# proto.net
KiCad netlist of a schematic drawn in EAGLE
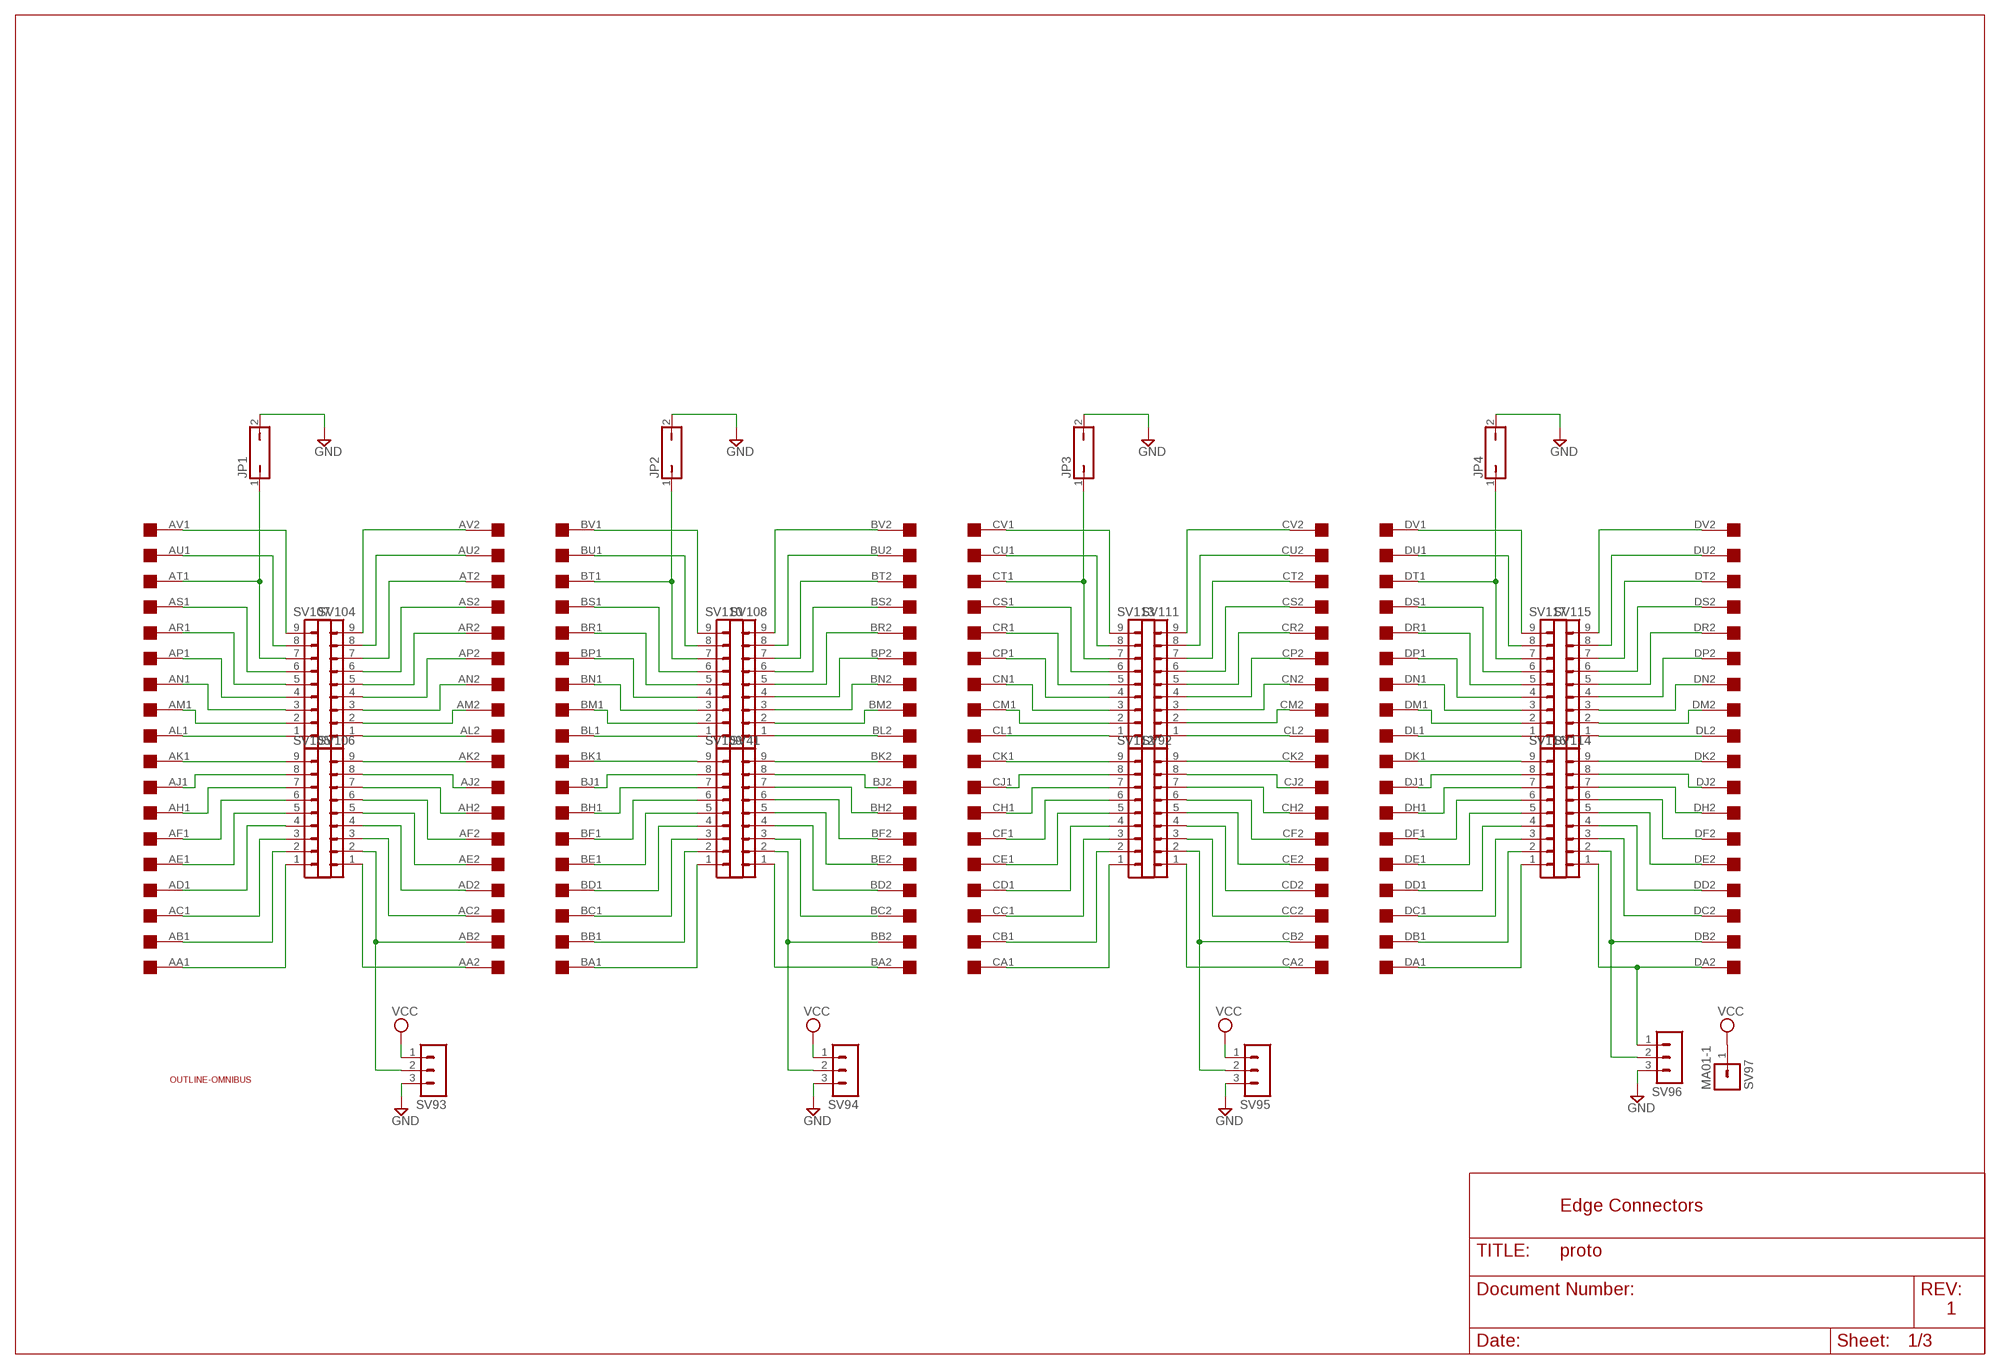
[diagram p0: schematic, sheet 1]
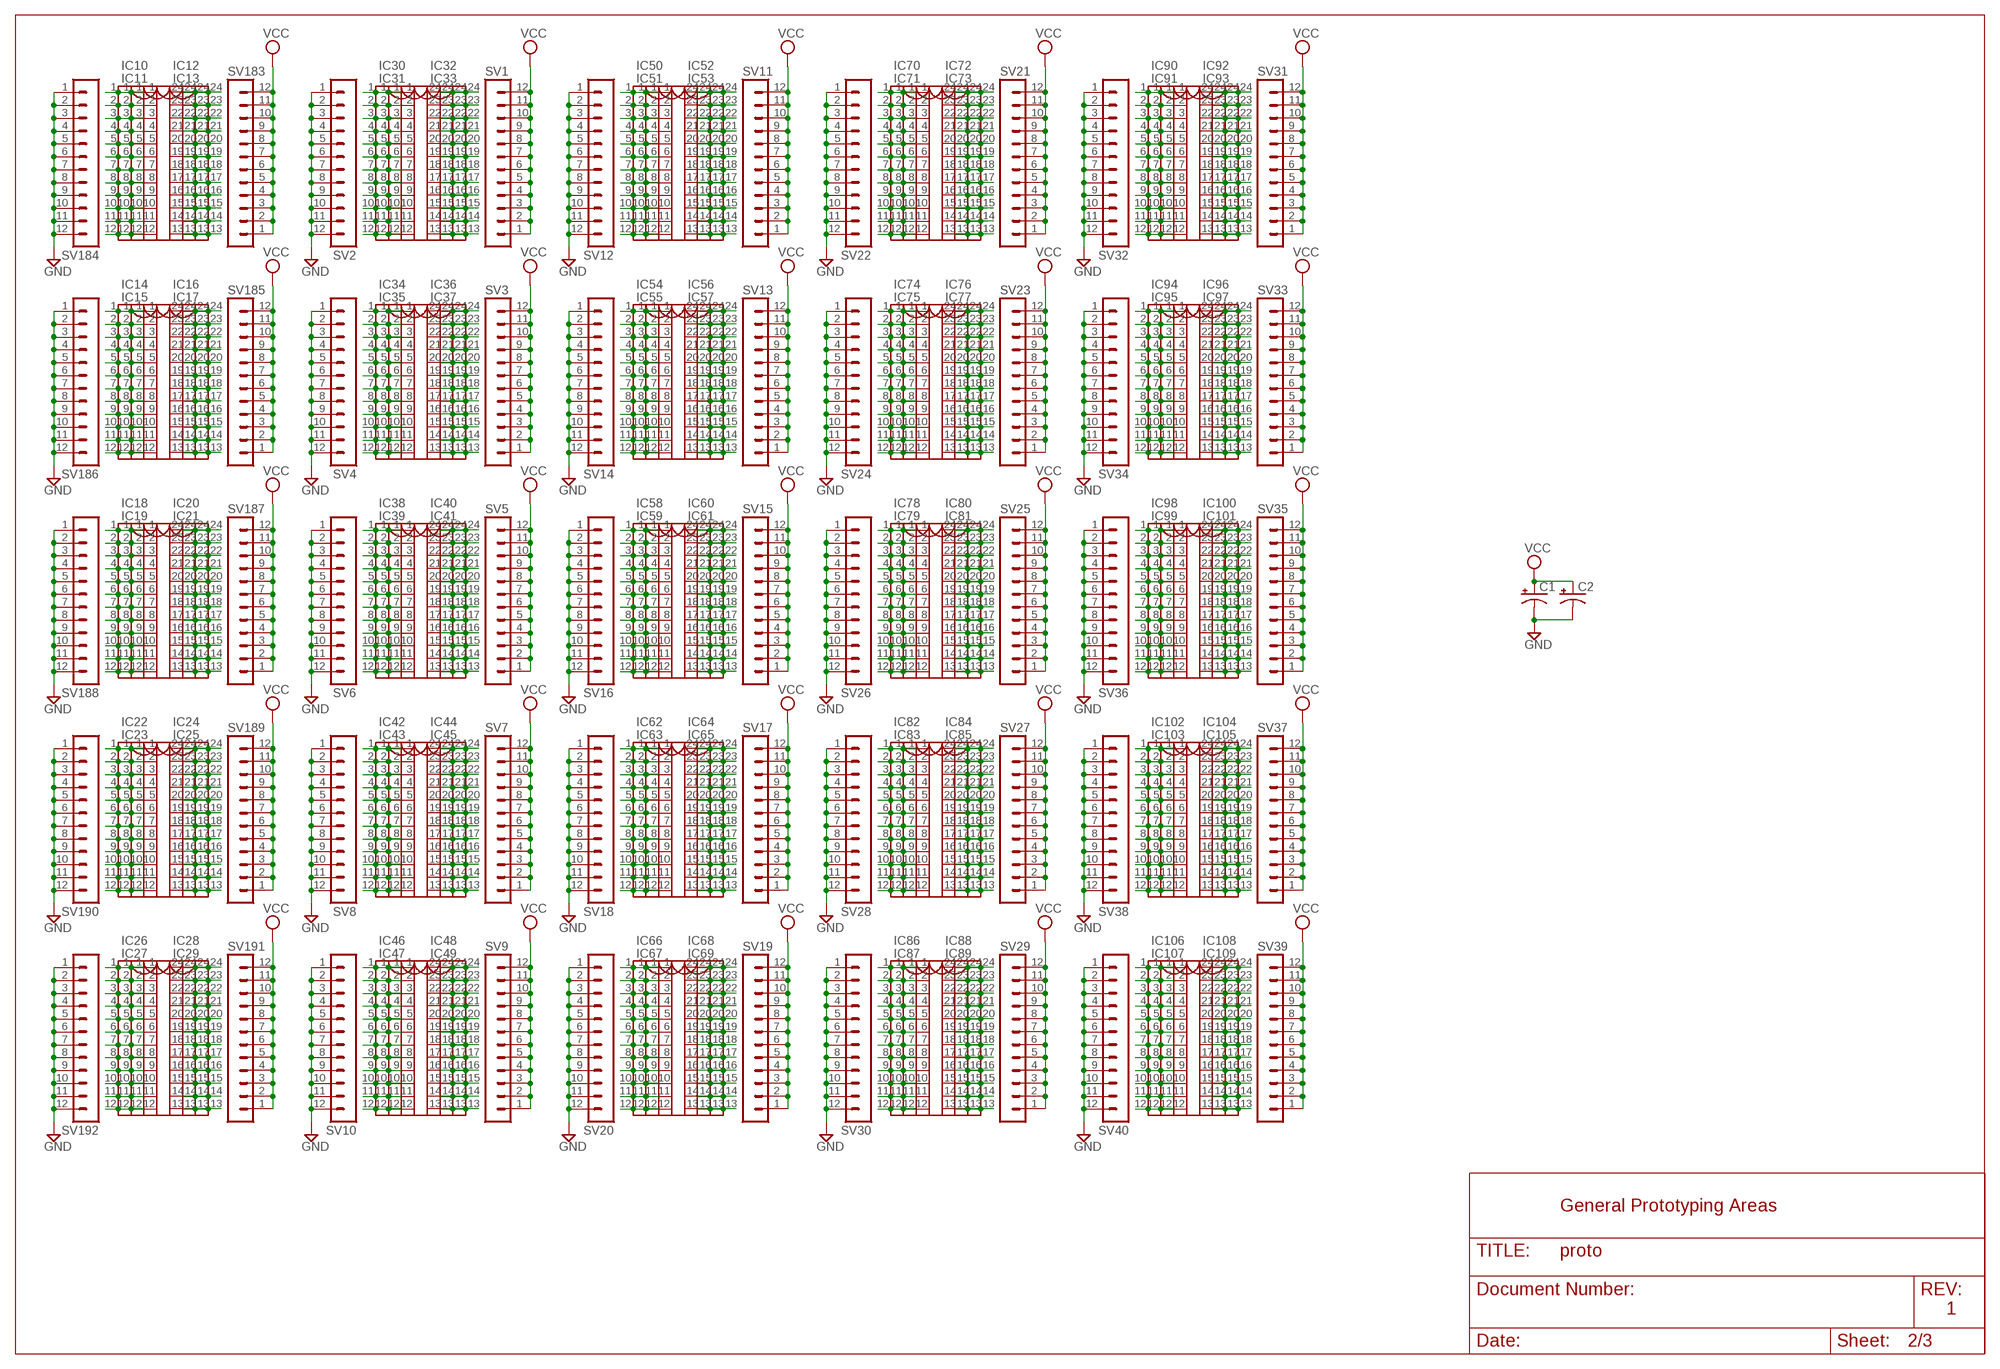
[diagram p1: schematic, sheet 2]
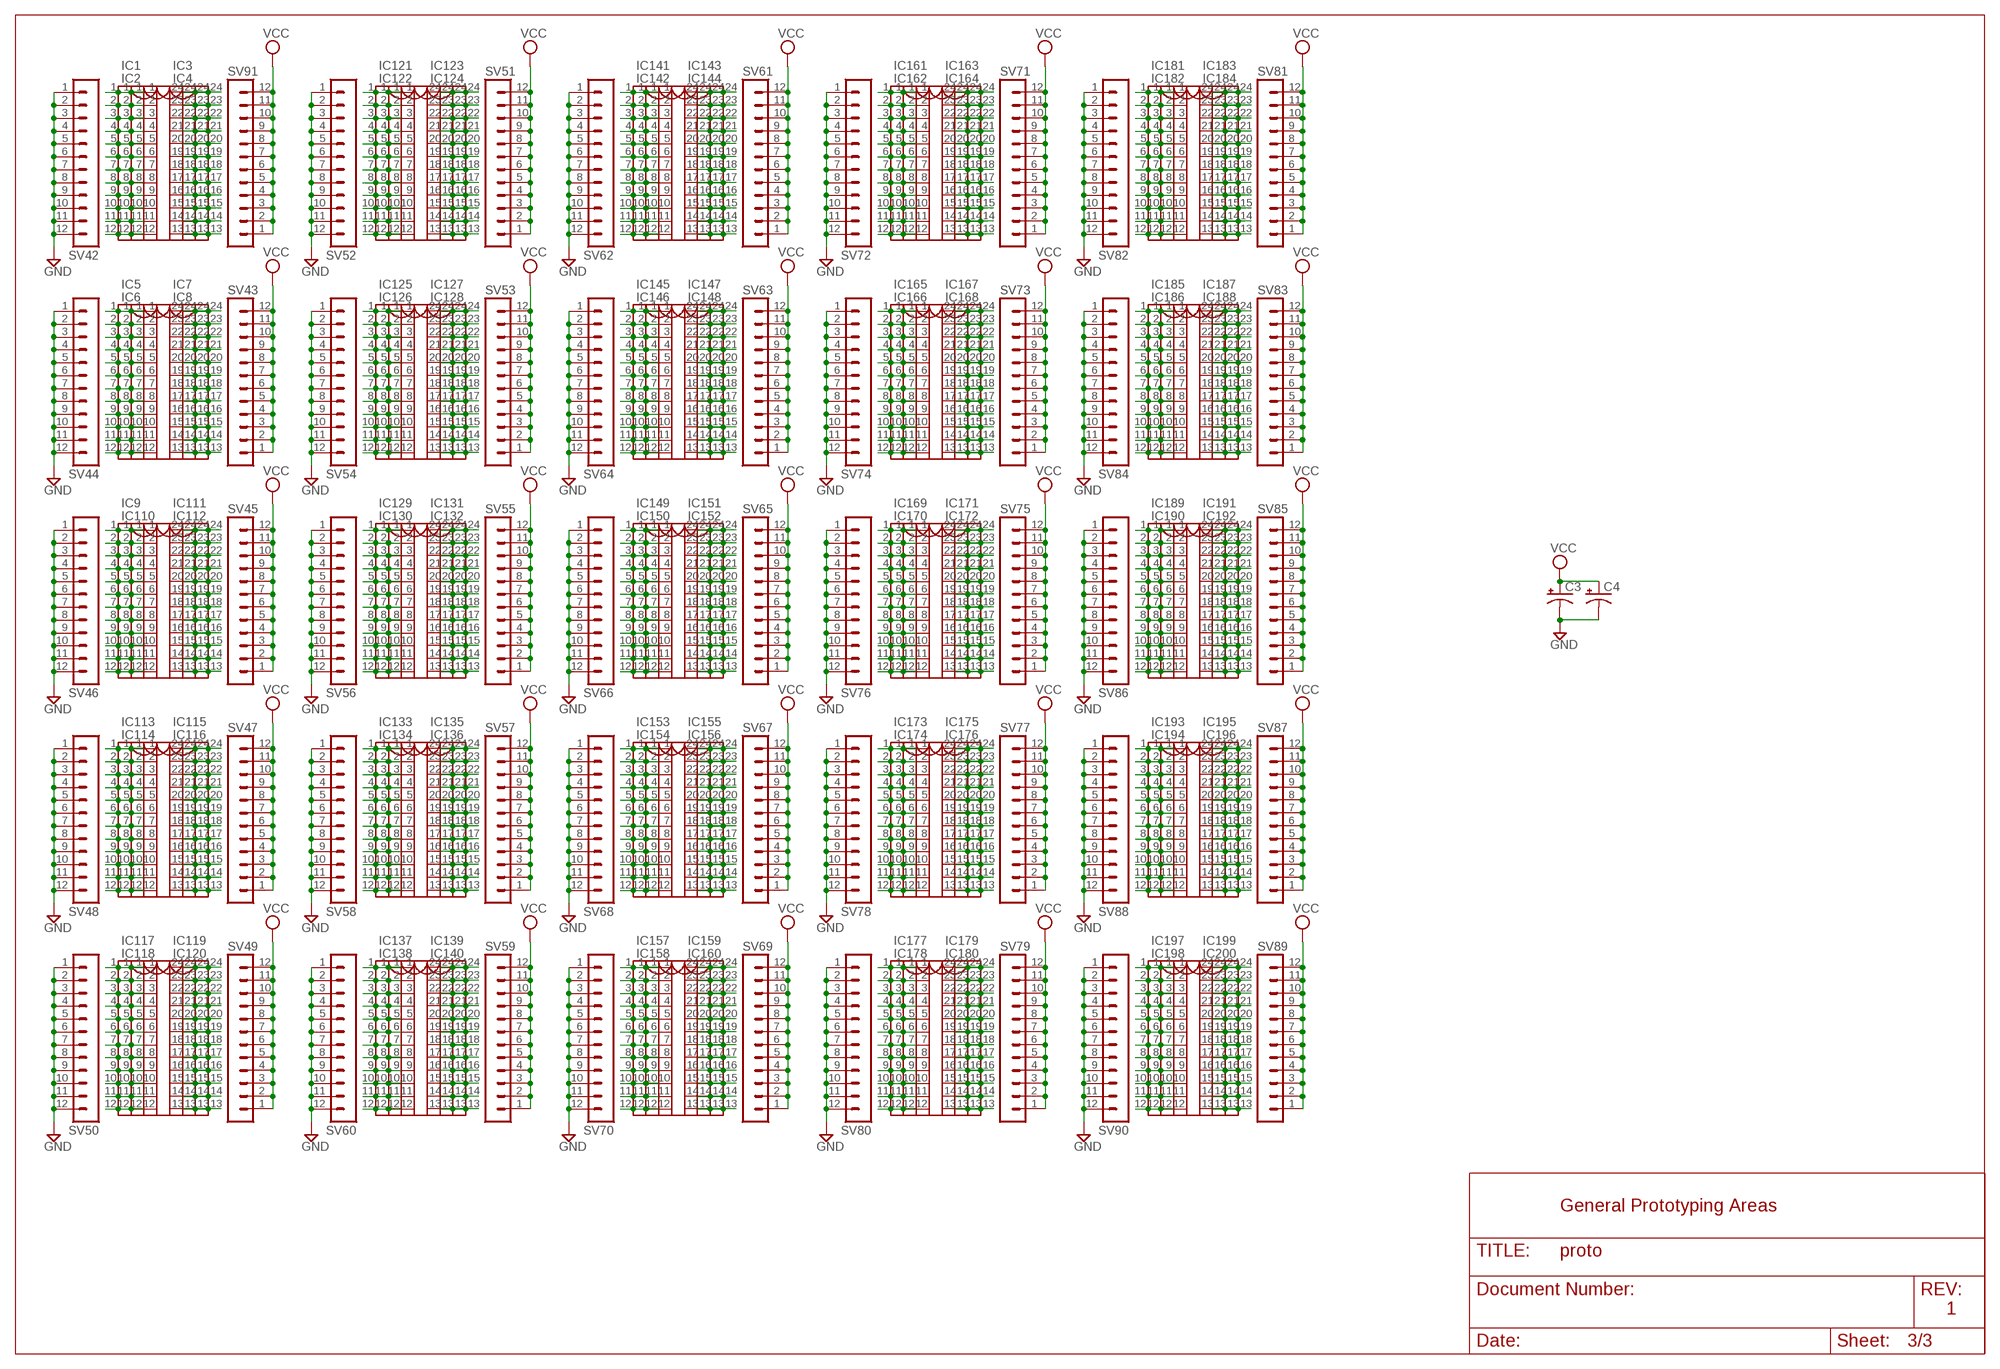
[diagram p2: schematic, sheet 3]

(export (version "E")
  (design (tool "Eeschema 10.0.6"))
  (components
    (comp (ref "C3")
      (value "CPOL-USE20-8AXIAL")
      (footprint "eagle-import:E12-8")
      (libsource (lib "eagle-import") (part "CPOL-USE20-8AXIAL"))
    )
    (comp (ref "C4")
      (value "CPOL-USE20-8AXIAL")
      (footprint "eagle-import:E12-8")
      (libsource (lib "eagle-import") (part "CPOL-USE20-8AXIAL"))
    )
    (comp (ref "IC1")
      (value "DIL24-3")
      (footprint "eagle-import:DIL24-3")
      (libsource (lib "eagle-import") (part "DIL24-3"))
    )
    (comp (ref "IC2")
      (value "DIL24-6")
      (footprint "eagle-import:DIL24-6")
      (libsource (lib "eagle-import") (part "DIL24-6"))
    )
    (comp (ref "IC3")
      (value "DIL24-9")
      (footprint "eagle-import:DIL24-9")
      (libsource (lib "eagle-import") (part "DIL24-9"))
    )
    (comp (ref "IC4")
      (value "DIL24-6")
      (footprint "eagle-import:DIL24-6")
      (libsource (lib "eagle-import") (part "DIL24-6"))
    )
    (comp (ref "IC5")
      (value "DIL24-3")
      (footprint "eagle-import:DIL24-3")
      (libsource (lib "eagle-import") (part "DIL24-3"))
    )
    (comp (ref "IC6")
      (value "DIL24-6")
      (footprint "eagle-import:DIL24-6")
      (libsource (lib "eagle-import") (part "DIL24-6"))
    )
    (comp (ref "IC7")
      (value "DIL24-9")
      (footprint "eagle-import:DIL24-9")
      (libsource (lib "eagle-import") (part "DIL24-9"))
    )
    (comp (ref "IC8")
      (value "DIL24-6")
      (footprint "eagle-import:DIL24-6")
      (libsource (lib "eagle-import") (part "DIL24-6"))
    )
    (comp (ref "IC9")
      (value "DIL24-3")
      (footprint "eagle-import:DIL24-3")
      (libsource (lib "eagle-import") (part "DIL24-3"))
    )
    (comp (ref "IC110")
      (value "DIL24-6")
      (footprint "eagle-import:DIL24-6")
      (libsource (lib "eagle-import") (part "DIL24-6"))
    )
    (comp (ref "IC111")
      (value "DIL24-9")
      (footprint "eagle-import:DIL24-9")
      (libsource (lib "eagle-import") (part "DIL24-9"))
    )
    (comp (ref "IC112")
      (value "DIL24-6")
      (footprint "eagle-import:DIL24-6")
      (libsource (lib "eagle-import") (part "DIL24-6"))
    )
    (comp (ref "IC113")
      (value "DIL24-3")
      (footprint "eagle-import:DIL24-3")
      (libsource (lib "eagle-import") (part "DIL24-3"))
    )
    (comp (ref "IC114")
      (value "DIL24-6")
      (footprint "eagle-import:DIL24-6")
      (libsource (lib "eagle-import") (part "DIL24-6"))
    )
    (comp (ref "IC115")
      (value "DIL24-9")
      (footprint "eagle-import:DIL24-9")
      (libsource (lib "eagle-import") (part "DIL24-9"))
    )
    (comp (ref "IC116")
      (value "DIL24-6")
      (footprint "eagle-import:DIL24-6")
      (libsource (lib "eagle-import") (part "DIL24-6"))
    )
    (comp (ref "IC117")
      (value "DIL24-3")
      (footprint "eagle-import:DIL24-3")
      (libsource (lib "eagle-import") (part "DIL24-3"))
    )
    (comp (ref "IC118")
      (value "DIL24-6")
      (footprint "eagle-import:DIL24-6")
      (libsource (lib "eagle-import") (part "DIL24-6"))
    )
    (comp (ref "IC119")
      (value "DIL24-9")
      (footprint "eagle-import:DIL24-9")
      (libsource (lib "eagle-import") (part "DIL24-9"))
    )
    (comp (ref "IC120")
      (value "DIL24-6")
      (footprint "eagle-import:DIL24-6")
      (libsource (lib "eagle-import") (part "DIL24-6"))
    )
    (comp (ref "IC121")
      (value "DIL24-3")
      (footprint "eagle-import:DIL24-3")
      (libsource (lib "eagle-import") (part "DIL24-3"))
    )
    (comp (ref "IC122")
      (value "DIL24-6")
      (footprint "eagle-import:DIL24-6")
      (libsource (lib "eagle-import") (part "DIL24-6"))
    )
    (comp (ref "IC123")
      (value "DIL24-9")
      (footprint "eagle-import:DIL24-9")
      (libsource (lib "eagle-import") (part "DIL24-9"))
    )
    (comp (ref "IC124")
      (value "DIL24-6")
      (footprint "eagle-import:DIL24-6")
      (libsource (lib "eagle-import") (part "DIL24-6"))
    )
    (comp (ref "IC125")
      (value "DIL24-3")
      (footprint "eagle-import:DIL24-3")
      (libsource (lib "eagle-import") (part "DIL24-3"))
    )
    (comp (ref "IC126")
      (value "DIL24-6")
      (footprint "eagle-import:DIL24-6")
      (libsource (lib "eagle-import") (part "DIL24-6"))
    )
    (comp (ref "IC127")
      (value "DIL24-9")
      (footprint "eagle-import:DIL24-9")
      (libsource (lib "eagle-import") (part "DIL24-9"))
    )
    (comp (ref "IC128")
      (value "DIL24-6")
      (footprint "eagle-import:DIL24-6")
      (libsource (lib "eagle-import") (part "DIL24-6"))
    )
    (comp (ref "IC129")
      (value "DIL24-3")
      (footprint "eagle-import:DIL24-3")
      (libsource (lib "eagle-import") (part "DIL24-3"))
    )
    (comp (ref "IC130")
      (value "DIL24-6")
      (footprint "eagle-import:DIL24-6")
      (libsource (lib "eagle-import") (part "DIL24-6"))
    )
    (comp (ref "IC131")
      (value "DIL24-9")
      (footprint "eagle-import:DIL24-9")
      (libsource (lib "eagle-import") (part "DIL24-9"))
    )
    (comp (ref "IC132")
      (value "DIL24-6")
      (footprint "eagle-import:DIL24-6")
      (libsource (lib "eagle-import") (part "DIL24-6"))
    )
    (comp (ref "IC133")
      (value "DIL24-3")
      (footprint "eagle-import:DIL24-3")
      (libsource (lib "eagle-import") (part "DIL24-3"))
    )
    (comp (ref "IC134")
      (value "DIL24-6")
      (footprint "eagle-import:DIL24-6")
      (libsource (lib "eagle-import") (part "DIL24-6"))
    )
    (comp (ref "IC135")
      (value "DIL24-9")
      (footprint "eagle-import:DIL24-9")
      (libsource (lib "eagle-import") (part "DIL24-9"))
    )
    (comp (ref "IC136")
      (value "DIL24-6")
      (footprint "eagle-import:DIL24-6")
      (libsource (lib "eagle-import") (part "DIL24-6"))
    )
    (comp (ref "IC137")
      (value "DIL24-3")
      (footprint "eagle-import:DIL24-3")
      (libsource (lib "eagle-import") (part "DIL24-3"))
    )
    (comp (ref "IC138")
      (value "DIL24-6")
      (footprint "eagle-import:DIL24-6")
      (libsource (lib "eagle-import") (part "DIL24-6"))
    )
    (comp (ref "IC139")
      (value "DIL24-9")
      (footprint "eagle-import:DIL24-9")
      (libsource (lib "eagle-import") (part "DIL24-9"))
    )
    (comp (ref "IC140")
      (value "DIL24-6")
      (footprint "eagle-import:DIL24-6")
      (libsource (lib "eagle-import") (part "DIL24-6"))
    )
    (comp (ref "IC141")
      (value "DIL24-3")
      (footprint "eagle-import:DIL24-3")
      (libsource (lib "eagle-import") (part "DIL24-3"))
    )
    (comp (ref "IC142")
      (value "DIL24-6")
      (footprint "eagle-import:DIL24-6")
      (libsource (lib "eagle-import") (part "DIL24-6"))
    )
    (comp (ref "IC143")
      (value "DIL24-9")
      (footprint "eagle-import:DIL24-9")
      (libsource (lib "eagle-import") (part "DIL24-9"))
    )
    (comp (ref "IC144")
      (value "DIL24-6")
      (footprint "eagle-import:DIL24-6")
      (libsource (lib "eagle-import") (part "DIL24-6"))
    )
    (comp (ref "IC145")
      (value "DIL24-3")
      (footprint "eagle-import:DIL24-3")
      (libsource (lib "eagle-import") (part "DIL24-3"))
    )
    (comp (ref "IC146")
      (value "DIL24-6")
      (footprint "eagle-import:DIL24-6")
      (libsource (lib "eagle-import") (part "DIL24-6"))
    )
    (comp (ref "IC147")
      (value "DIL24-9")
      (footprint "eagle-import:DIL24-9")
      (libsource (lib "eagle-import") (part "DIL24-9"))
    )
    (comp (ref "IC148")
      (value "DIL24-6")
      (footprint "eagle-import:DIL24-6")
      (libsource (lib "eagle-import") (part "DIL24-6"))
    )
    (comp (ref "IC149")
      (value "DIL24-3")
      (footprint "eagle-import:DIL24-3")
      (libsource (lib "eagle-import") (part "DIL24-3"))
    )
    (comp (ref "IC150")
      (value "DIL24-6")
      (footprint "eagle-import:DIL24-6")
      (libsource (lib "eagle-import") (part "DIL24-6"))
    )
    (comp (ref "IC151")
      (value "DIL24-9")
      (footprint "eagle-import:DIL24-9")
      (libsource (lib "eagle-import") (part "DIL24-9"))
    )
    (comp (ref "IC152")
      (value "DIL24-6")
      (footprint "eagle-import:DIL24-6")
      (libsource (lib "eagle-import") (part "DIL24-6"))
    )
    (comp (ref "IC153")
      (value "DIL24-3")
      (footprint "eagle-import:DIL24-3")
      (libsource (lib "eagle-import") (part "DIL24-3"))
    )
    (comp (ref "IC154")
      (value "DIL24-6")
      (footprint "eagle-import:DIL24-6")
      (libsource (lib "eagle-import") (part "DIL24-6"))
    )
    (comp (ref "IC155")
      (value "DIL24-9")
      (footprint "eagle-import:DIL24-9")
      (libsource (lib "eagle-import") (part "DIL24-9"))
    )
    (comp (ref "IC156")
      (value "DIL24-6")
      (footprint "eagle-import:DIL24-6")
      (libsource (lib "eagle-import") (part "DIL24-6"))
    )
    (comp (ref "IC157")
      (value "DIL24-3")
      (footprint "eagle-import:DIL24-3")
      (libsource (lib "eagle-import") (part "DIL24-3"))
    )
    (comp (ref "IC158")
      (value "DIL24-6")
      (footprint "eagle-import:DIL24-6")
      (libsource (lib "eagle-import") (part "DIL24-6"))
    )
    (comp (ref "IC159")
      (value "DIL24-9")
      (footprint "eagle-import:DIL24-9")
      (libsource (lib "eagle-import") (part "DIL24-9"))
    )
    (comp (ref "IC160")
      (value "DIL24-6")
      (footprint "eagle-import:DIL24-6")
      (libsource (lib "eagle-import") (part "DIL24-6"))
    )
    (comp (ref "IC161")
      (value "DIL24-3")
      (footprint "eagle-import:DIL24-3")
      (libsource (lib "eagle-import") (part "DIL24-3"))
    )
    (comp (ref "IC162")
      (value "DIL24-6")
      (footprint "eagle-import:DIL24-6")
      (libsource (lib "eagle-import") (part "DIL24-6"))
    )
    (comp (ref "IC163")
      (value "DIL24-9")
      (footprint "eagle-import:DIL24-9")
      (libsource (lib "eagle-import") (part "DIL24-9"))
    )
    (comp (ref "IC164")
      (value "DIL24-6")
      (footprint "eagle-import:DIL24-6")
      (libsource (lib "eagle-import") (part "DIL24-6"))
    )
    (comp (ref "IC165")
      (value "DIL24-3")
      (footprint "eagle-import:DIL24-3")
      (libsource (lib "eagle-import") (part "DIL24-3"))
    )
    (comp (ref "IC166")
      (value "DIL24-6")
      (footprint "eagle-import:DIL24-6")
      (libsource (lib "eagle-import") (part "DIL24-6"))
    )
    (comp (ref "IC167")
      (value "DIL24-9")
      (footprint "eagle-import:DIL24-9")
      (libsource (lib "eagle-import") (part "DIL24-9"))
    )
    (comp (ref "IC168")
      (value "DIL24-6")
      (footprint "eagle-import:DIL24-6")
      (libsource (lib "eagle-import") (part "DIL24-6"))
    )
    (comp (ref "IC169")
      (value "DIL24-3")
      (footprint "eagle-import:DIL24-3")
      (libsource (lib "eagle-import") (part "DIL24-3"))
    )
    (comp (ref "IC170")
      (value "DIL24-6")
      (footprint "eagle-import:DIL24-6")
      (libsource (lib "eagle-import") (part "DIL24-6"))
    )
    (comp (ref "IC171")
      (value "DIL24-9")
      (footprint "eagle-import:DIL24-9")
      (libsource (lib "eagle-import") (part "DIL24-9"))
    )
    (comp (ref "IC172")
      (value "DIL24-6")
      (footprint "eagle-import:DIL24-6")
      (libsource (lib "eagle-import") (part "DIL24-6"))
    )
    (comp (ref "IC173")
      (value "DIL24-3")
      (footprint "eagle-import:DIL24-3")
      (libsource (lib "eagle-import") (part "DIL24-3"))
    )
    (comp (ref "IC174")
      (value "DIL24-6")
      (footprint "eagle-import:DIL24-6")
      (libsource (lib "eagle-import") (part "DIL24-6"))
    )
    (comp (ref "IC175")
      (value "DIL24-9")
      (footprint "eagle-import:DIL24-9")
      (libsource (lib "eagle-import") (part "DIL24-9"))
    )
    (comp (ref "IC176")
      (value "DIL24-6")
      (footprint "eagle-import:DIL24-6")
      (libsource (lib "eagle-import") (part "DIL24-6"))
    )
    (comp (ref "IC177")
      (value "DIL24-3")
      (footprint "eagle-import:DIL24-3")
      (libsource (lib "eagle-import") (part "DIL24-3"))
    )
    (comp (ref "IC178")
      (value "DIL24-6")
      (footprint "eagle-import:DIL24-6")
      (libsource (lib "eagle-import") (part "DIL24-6"))
    )
    (comp (ref "IC179")
      (value "DIL24-9")
      (footprint "eagle-import:DIL24-9")
      (libsource (lib "eagle-import") (part "DIL24-9"))
    )
    (comp (ref "IC180")
      (value "DIL24-6")
      (footprint "eagle-import:DIL24-6")
      (libsource (lib "eagle-import") (part "DIL24-6"))
    )
    (comp (ref "IC181")
      (value "DIL24-3")
      (footprint "eagle-import:DIL24-3")
      (libsource (lib "eagle-import") (part "DIL24-3"))
    )
    (comp (ref "IC182")
      (value "DIL24-6")
      (footprint "eagle-import:DIL24-6")
      (libsource (lib "eagle-import") (part "DIL24-6"))
    )
    (comp (ref "IC183")
      (value "DIL24-9")
      (footprint "eagle-import:DIL24-9")
      (libsource (lib "eagle-import") (part "DIL24-9"))
    )
    (comp (ref "IC184")
      (value "DIL24-6")
      (footprint "eagle-import:DIL24-6")
      (libsource (lib "eagle-import") (part "DIL24-6"))
    )
    (comp (ref "IC185")
      (value "DIL24-3")
      (footprint "eagle-import:DIL24-3")
      (libsource (lib "eagle-import") (part "DIL24-3"))
    )
    (comp (ref "IC186")
      (value "DIL24-6")
      (footprint "eagle-import:DIL24-6")
      (libsource (lib "eagle-import") (part "DIL24-6"))
    )
    (comp (ref "IC187")
      (value "DIL24-9")
      (footprint "eagle-import:DIL24-9")
      (libsource (lib "eagle-import") (part "DIL24-9"))
    )
    (comp (ref "IC188")
      (value "DIL24-6")
      (footprint "eagle-import:DIL24-6")
      (libsource (lib "eagle-import") (part "DIL24-6"))
    )
    (comp (ref "IC189")
      (value "DIL24-3")
      (footprint "eagle-import:DIL24-3")
      (libsource (lib "eagle-import") (part "DIL24-3"))
    )
    (comp (ref "IC190")
      (value "DIL24-6")
      (footprint "eagle-import:DIL24-6")
      (libsource (lib "eagle-import") (part "DIL24-6"))
    )
    (comp (ref "IC191")
      (value "DIL24-9")
      (footprint "eagle-import:DIL24-9")
      (libsource (lib "eagle-import") (part "DIL24-9"))
    )
    (comp (ref "IC192")
      (value "DIL24-6")
      (footprint "eagle-import:DIL24-6")
      (libsource (lib "eagle-import") (part "DIL24-6"))
    )
    (comp (ref "IC193")
      (value "DIL24-3")
      (footprint "eagle-import:DIL24-3")
      (libsource (lib "eagle-import") (part "DIL24-3"))
    )
    (comp (ref "IC194")
      (value "DIL24-6")
      (footprint "eagle-import:DIL24-6")
      (libsource (lib "eagle-import") (part "DIL24-6"))
    )
    (comp (ref "IC195")
      (value "DIL24-9")
      (footprint "eagle-import:DIL24-9")
      (libsource (lib "eagle-import") (part "DIL24-9"))
    )
    (comp (ref "IC196")
      (value "DIL24-6")
      (footprint "eagle-import:DIL24-6")
      (libsource (lib "eagle-import") (part "DIL24-6"))
    )
    (comp (ref "IC197")
      (value "DIL24-3")
      (footprint "eagle-import:DIL24-3")
      (libsource (lib "eagle-import") (part "DIL24-3"))
    )
    (comp (ref "IC198")
      (value "DIL24-6")
      (footprint "eagle-import:DIL24-6")
      (libsource (lib "eagle-import") (part "DIL24-6"))
    )
    (comp (ref "IC199")
      (value "DIL24-9")
      (footprint "eagle-import:DIL24-9")
      (libsource (lib "eagle-import") (part "DIL24-9"))
    )
    (comp (ref "IC200")
      (value "DIL24-6")
      (footprint "eagle-import:DIL24-6")
      (libsource (lib "eagle-import") (part "DIL24-6"))
    )
    (comp (ref "SV42")
      (value "MA12-1")
      (footprint "eagle-import:MA12-1")
      (libsource (lib "eagle-import") (part "MA12-1"))
    )
    (comp (ref "SV43")
      (value "MA12-1")
      (footprint "eagle-import:MA12-1")
      (libsource (lib "eagle-import") (part "MA12-1"))
    )
    (comp (ref "SV44")
      (value "MA12-1")
      (footprint "eagle-import:MA12-1")
      (libsource (lib "eagle-import") (part "MA12-1"))
    )
    (comp (ref "SV45")
      (value "MA12-1")
      (footprint "eagle-import:MA12-1")
      (libsource (lib "eagle-import") (part "MA12-1"))
    )
    (comp (ref "SV46")
      (value "MA12-1")
      (footprint "eagle-import:MA12-1")
      (libsource (lib "eagle-import") (part "MA12-1"))
    )
    (comp (ref "SV47")
      (value "MA12-1")
      (footprint "eagle-import:MA12-1")
      (libsource (lib "eagle-import") (part "MA12-1"))
    )
    (comp (ref "SV48")
      (value "MA12-1")
      (footprint "eagle-import:MA12-1")
      (libsource (lib "eagle-import") (part "MA12-1"))
    )
    (comp (ref "SV49")
      (value "MA12-1")
      (footprint "eagle-import:MA12-1")
      (libsource (lib "eagle-import") (part "MA12-1"))
    )
    (comp (ref "SV50")
      (value "MA12-1")
      (footprint "eagle-import:MA12-1")
      (libsource (lib "eagle-import") (part "MA12-1"))
    )
    (comp (ref "SV51")
      (value "MA12-1")
      (footprint "eagle-import:MA12-1")
      (libsource (lib "eagle-import") (part "MA12-1"))
    )
    (comp (ref "SV52")
      (value "MA12-1")
      (footprint "eagle-import:MA12-1")
      (libsource (lib "eagle-import") (part "MA12-1"))
    )
    (comp (ref "SV53")
      (value "MA12-1")
      (footprint "eagle-import:MA12-1")
      (libsource (lib "eagle-import") (part "MA12-1"))
    )
    (comp (ref "SV54")
      (value "MA12-1")
      (footprint "eagle-import:MA12-1")
      (libsource (lib "eagle-import") (part "MA12-1"))
    )
    (comp (ref "SV55")
      (value "MA12-1")
      (footprint "eagle-import:MA12-1")
      (libsource (lib "eagle-import") (part "MA12-1"))
    )
    (comp (ref "SV56")
      (value "MA12-1")
      (footprint "eagle-import:MA12-1")
      (libsource (lib "eagle-import") (part "MA12-1"))
    )
    (comp (ref "SV57")
      (value "MA12-1")
      (footprint "eagle-import:MA12-1")
      (libsource (lib "eagle-import") (part "MA12-1"))
    )
    (comp (ref "SV58")
      (value "MA12-1")
      (footprint "eagle-import:MA12-1")
      (libsource (lib "eagle-import") (part "MA12-1"))
    )
    (comp (ref "SV59")
      (value "MA12-1")
      (footprint "eagle-import:MA12-1")
      (libsource (lib "eagle-import") (part "MA12-1"))
    )
    (comp (ref "SV60")
      (value "MA12-1")
      (footprint "eagle-import:MA12-1")
      (libsource (lib "eagle-import") (part "MA12-1"))
    )
    (comp (ref "SV61")
      (value "MA12-1")
      (footprint "eagle-import:MA12-1")
      (libsource (lib "eagle-import") (part "MA12-1"))
    )
    (comp (ref "SV62")
      (value "MA12-1")
      (footprint "eagle-import:MA12-1")
      (libsource (lib "eagle-import") (part "MA12-1"))
    )
    (comp (ref "SV63")
      (value "MA12-1")
      (footprint "eagle-import:MA12-1")
      (libsource (lib "eagle-import") (part "MA12-1"))
    )
    (comp (ref "SV64")
      (value "MA12-1")
      (footprint "eagle-import:MA12-1")
      (libsource (lib "eagle-import") (part "MA12-1"))
    )
    (comp (ref "SV65")
      (value "MA12-1")
      (footprint "eagle-import:MA12-1")
      (libsource (lib "eagle-import") (part "MA12-1"))
    )
    (comp (ref "SV66")
      (value "MA12-1")
      (footprint "eagle-import:MA12-1")
      (libsource (lib "eagle-import") (part "MA12-1"))
    )
    (comp (ref "SV67")
      (value "MA12-1")
      (footprint "eagle-import:MA12-1")
      (libsource (lib "eagle-import") (part "MA12-1"))
    )
    (comp (ref "SV68")
      (value "MA12-1")
      (footprint "eagle-import:MA12-1")
      (libsource (lib "eagle-import") (part "MA12-1"))
    )
    (comp (ref "SV69")
      (value "MA12-1")
      (footprint "eagle-import:MA12-1")
      (libsource (lib "eagle-import") (part "MA12-1"))
    )
    (comp (ref "SV70")
      (value "MA12-1")
      (footprint "eagle-import:MA12-1")
      (libsource (lib "eagle-import") (part "MA12-1"))
    )
    (comp (ref "SV71")
      (value "MA12-1")
      (footprint "eagle-import:MA12-1")
      (libsource (lib "eagle-import") (part "MA12-1"))
    )
    (comp (ref "SV72")
      (value "MA12-1")
      (footprint "eagle-import:MA12-1")
      (libsource (lib "eagle-import") (part "MA12-1"))
    )
    (comp (ref "SV73")
      (value "MA12-1")
      (footprint "eagle-import:MA12-1")
      (libsource (lib "eagle-import") (part "MA12-1"))
    )
    (comp (ref "SV74")
      (value "MA12-1")
      (footprint "eagle-import:MA12-1")
      (libsource (lib "eagle-import") (part "MA12-1"))
    )
    (comp (ref "SV75")
      (value "MA12-1")
      (footprint "eagle-import:MA12-1")
      (libsource (lib "eagle-import") (part "MA12-1"))
    )
    (comp (ref "SV76")
      (value "MA12-1")
      (footprint "eagle-import:MA12-1")
      (libsource (lib "eagle-import") (part "MA12-1"))
    )
    (comp (ref "SV77")
      (value "MA12-1")
      (footprint "eagle-import:MA12-1")
      (libsource (lib "eagle-import") (part "MA12-1"))
    )
    (comp (ref "SV78")
      (value "MA12-1")
      (footprint "eagle-import:MA12-1")
      (libsource (lib "eagle-import") (part "MA12-1"))
    )
    (comp (ref "SV79")
      (value "MA12-1")
      (footprint "eagle-import:MA12-1")
      (libsource (lib "eagle-import") (part "MA12-1"))
    )
    (comp (ref "SV80")
      (value "MA12-1")
      (footprint "eagle-import:MA12-1")
      (libsource (lib "eagle-import") (part "MA12-1"))
    )
    (comp (ref "SV81")
      (value "MA12-1")
      (footprint "eagle-import:MA12-1")
      (libsource (lib "eagle-import") (part "MA12-1"))
    )
    (comp (ref "SV82")
      (value "MA12-1")
      (footprint "eagle-import:MA12-1")
      (libsource (lib "eagle-import") (part "MA12-1"))
    )
    (comp (ref "SV83")
      (value "MA12-1")
      (footprint "eagle-import:MA12-1")
      (libsource (lib "eagle-import") (part "MA12-1"))
    )
    (comp (ref "SV84")
      (value "MA12-1")
      (footprint "eagle-import:MA12-1")
      (libsource (lib "eagle-import") (part "MA12-1"))
    )
    (comp (ref "SV85")
      (value "MA12-1")
      (footprint "eagle-import:MA12-1")
      (libsource (lib "eagle-import") (part "MA12-1"))
    )
    (comp (ref "SV86")
      (value "MA12-1")
      (footprint "eagle-import:MA12-1")
      (libsource (lib "eagle-import") (part "MA12-1"))
    )
    (comp (ref "SV87")
      (value "MA12-1")
      (footprint "eagle-import:MA12-1")
      (libsource (lib "eagle-import") (part "MA12-1"))
    )
    (comp (ref "SV88")
      (value "MA12-1")
      (footprint "eagle-import:MA12-1")
      (libsource (lib "eagle-import") (part "MA12-1"))
    )
    (comp (ref "SV89")
      (value "MA12-1")
      (footprint "eagle-import:MA12-1")
      (libsource (lib "eagle-import") (part "MA12-1"))
    )
    (comp (ref "SV90")
      (value "MA12-1")
      (footprint "eagle-import:MA12-1")
      (libsource (lib "eagle-import") (part "MA12-1"))
    )
    (comp (ref "SV91")
      (value "MA12-1")
      (footprint "eagle-import:MA12-1")
      (libsource (lib "eagle-import") (part "MA12-1"))
    )
    (comp (ref "C1")
      (value "CPOL-USE20-8AXIAL")
      (footprint "eagle-import:E12-8")
      (libsource (lib "eagle-import") (part "CPOL-USE20-8AXIAL"))
    )
    (comp (ref "C2")
      (value "CPOL-USE20-8AXIAL")
      (footprint "eagle-import:E12-8")
      (libsource (lib "eagle-import") (part "CPOL-USE20-8AXIAL"))
    )
    (comp (ref "IC10")
      (value "DIL24-3")
      (footprint "eagle-import:DIL24-3")
      (libsource (lib "eagle-import") (part "DIL24-3"))
    )
    (comp (ref "IC11")
      (value "DIL24-6")
      (footprint "eagle-import:DIL24-6")
      (libsource (lib "eagle-import") (part "DIL24-6"))
    )
    (comp (ref "IC12")
      (value "DIL24-9")
      (footprint "eagle-import:DIL24-9")
      (libsource (lib "eagle-import") (part "DIL24-9"))
    )
    (comp (ref "IC13")
      (value "DIL24-6")
      (footprint "eagle-import:DIL24-6")
      (libsource (lib "eagle-import") (part "DIL24-6"))
    )
    (comp (ref "IC14")
      (value "DIL24-3")
      (footprint "eagle-import:DIL24-3")
      (libsource (lib "eagle-import") (part "DIL24-3"))
    )
    (comp (ref "IC15")
      (value "DIL24-6")
      (footprint "eagle-import:DIL24-6")
      (libsource (lib "eagle-import") (part "DIL24-6"))
    )
    (comp (ref "IC16")
      (value "DIL24-9")
      (footprint "eagle-import:DIL24-9")
      (libsource (lib "eagle-import") (part "DIL24-9"))
    )
    (comp (ref "IC17")
      (value "DIL24-6")
      (footprint "eagle-import:DIL24-6")
      (libsource (lib "eagle-import") (part "DIL24-6"))
    )
    (comp (ref "IC18")
      (value "DIL24-3")
      (footprint "eagle-import:DIL24-3")
      (libsource (lib "eagle-import") (part "DIL24-3"))
    )
    (comp (ref "IC19")
      (value "DIL24-6")
      (footprint "eagle-import:DIL24-6")
      (libsource (lib "eagle-import") (part "DIL24-6"))
    )
    (comp (ref "IC20")
      (value "DIL24-9")
      (footprint "eagle-import:DIL24-9")
      (libsource (lib "eagle-import") (part "DIL24-9"))
    )
    (comp (ref "IC21")
      (value "DIL24-6")
      (footprint "eagle-import:DIL24-6")
      (libsource (lib "eagle-import") (part "DIL24-6"))
    )
    (comp (ref "IC22")
      (value "DIL24-3")
      (footprint "eagle-import:DIL24-3")
      (libsource (lib "eagle-import") (part "DIL24-3"))
    )
    (comp (ref "IC23")
      (value "DIL24-6")
      (footprint "eagle-import:DIL24-6")
      (libsource (lib "eagle-import") (part "DIL24-6"))
    )
    (comp (ref "IC24")
      (value "DIL24-9")
      (footprint "eagle-import:DIL24-9")
      (libsource (lib "eagle-import") (part "DIL24-9"))
    )
    (comp (ref "IC25")
      (value "DIL24-6")
      (footprint "eagle-import:DIL24-6")
      (libsource (lib "eagle-import") (part "DIL24-6"))
    )
    (comp (ref "IC26")
      (value "DIL24-3")
      (footprint "eagle-import:DIL24-3")
      (libsource (lib "eagle-import") (part "DIL24-3"))
    )
    (comp (ref "IC27")
      (value "DIL24-6")
      (footprint "eagle-import:DIL24-6")
      (libsource (lib "eagle-import") (part "DIL24-6"))
    )
    (comp (ref "IC28")
      (value "DIL24-9")
      (footprint "eagle-import:DIL24-9")
      (libsource (lib "eagle-import") (part "DIL24-9"))
    )
    (comp (ref "IC29")
      (value "DIL24-6")
      (footprint "eagle-import:DIL24-6")
      (libsource (lib "eagle-import") (part "DIL24-6"))
    )
    (comp (ref "IC30")
      (value "DIL24-3")
      (footprint "eagle-import:DIL24-3")
      (libsource (lib "eagle-import") (part "DIL24-3"))
    )
    (comp (ref "IC31")
      (value "DIL24-6")
      (footprint "eagle-import:DIL24-6")
      (libsource (lib "eagle-import") (part "DIL24-6"))
    )
    (comp (ref "IC32")
      (value "DIL24-9")
      (footprint "eagle-import:DIL24-9")
      (libsource (lib "eagle-import") (part "DIL24-9"))
    )
    (comp (ref "IC33")
      (value "DIL24-6")
      (footprint "eagle-import:DIL24-6")
      (libsource (lib "eagle-import") (part "DIL24-6"))
    )
    (comp (ref "IC34")
      (value "DIL24-3")
      (footprint "eagle-import:DIL24-3")
      (libsource (lib "eagle-import") (part "DIL24-3"))
    )
    (comp (ref "IC35")
      (value "DIL24-6")
      (footprint "eagle-import:DIL24-6")
      (libsource (lib "eagle-import") (part "DIL24-6"))
    )
    (comp (ref "IC36")
      (value "DIL24-9")
      (footprint "eagle-import:DIL24-9")
      (libsource (lib "eagle-import") (part "DIL24-9"))
    )
    (comp (ref "IC37")
      (value "DIL24-6")
      (footprint "eagle-import:DIL24-6")
      (libsource (lib "eagle-import") (part "DIL24-6"))
    )
    (comp (ref "IC38")
      (value "DIL24-3")
      (footprint "eagle-import:DIL24-3")
      (libsource (lib "eagle-import") (part "DIL24-3"))
    )
    (comp (ref "IC39")
      (value "DIL24-6")
      (footprint "eagle-import:DIL24-6")
      (libsource (lib "eagle-import") (part "DIL24-6"))
    )
    (comp (ref "IC40")
      (value "DIL24-9")
      (footprint "eagle-import:DIL24-9")
      (libsource (lib "eagle-import") (part "DIL24-9"))
    )
    (comp (ref "IC41")
      (value "DIL24-6")
      (footprint "eagle-import:DIL24-6")
      (libsource (lib "eagle-import") (part "DIL24-6"))
    )
    (comp (ref "IC42")
      (value "DIL24-3")
      (footprint "eagle-import:DIL24-3")
      (libsource (lib "eagle-import") (part "DIL24-3"))
    )
    (comp (ref "IC43")
      (value "DIL24-6")
      (footprint "eagle-import:DIL24-6")
      (libsource (lib "eagle-import") (part "DIL24-6"))
    )
    (comp (ref "IC44")
      (value "DIL24-9")
      (footprint "eagle-import:DIL24-9")
      (libsource (lib "eagle-import") (part "DIL24-9"))
    )
    (comp (ref "IC45")
      (value "DIL24-6")
      (footprint "eagle-import:DIL24-6")
      (libsource (lib "eagle-import") (part "DIL24-6"))
    )
    (comp (ref "IC46")
      (value "DIL24-3")
      (footprint "eagle-import:DIL24-3")
      (libsource (lib "eagle-import") (part "DIL24-3"))
    )
    (comp (ref "IC47")
      (value "DIL24-6")
      (footprint "eagle-import:DIL24-6")
      (libsource (lib "eagle-import") (part "DIL24-6"))
    )
    (comp (ref "IC48")
      (value "DIL24-9")
      (footprint "eagle-import:DIL24-9")
      (libsource (lib "eagle-import") (part "DIL24-9"))
    )
    (comp (ref "IC49")
      (value "DIL24-6")
      (footprint "eagle-import:DIL24-6")
      (libsource (lib "eagle-import") (part "DIL24-6"))
    )
    (comp (ref "IC50")
      (value "DIL24-3")
      (footprint "eagle-import:DIL24-3")
      (libsource (lib "eagle-import") (part "DIL24-3"))
    )
    (comp (ref "IC51")
      (value "DIL24-6")
      (footprint "eagle-import:DIL24-6")
      (libsource (lib "eagle-import") (part "DIL24-6"))
    )
    (comp (ref "IC52")
      (value "DIL24-9")
      (footprint "eagle-import:DIL24-9")
      (libsource (lib "eagle-import") (part "DIL24-9"))
    )
    (comp (ref "IC53")
      (value "DIL24-6")
      (footprint "eagle-import:DIL24-6")
      (libsource (lib "eagle-import") (part "DIL24-6"))
    )
    (comp (ref "IC54")
      (value "DIL24-3")
      (footprint "eagle-import:DIL24-3")
      (libsource (lib "eagle-import") (part "DIL24-3"))
    )
    (comp (ref "IC55")
      (value "DIL24-6")
      (footprint "eagle-import:DIL24-6")
      (libsource (lib "eagle-import") (part "DIL24-6"))
    )
    (comp (ref "IC56")
      (value "DIL24-9")
      (footprint "eagle-import:DIL24-9")
      (libsource (lib "eagle-import") (part "DIL24-9"))
    )
    (comp (ref "IC57")
      (value "DIL24-6")
      (footprint "eagle-import:DIL24-6")
      (libsource (lib "eagle-import") (part "DIL24-6"))
    )
    (comp (ref "IC58")
      (value "DIL24-3")
      (footprint "eagle-import:DIL24-3")
      (libsource (lib "eagle-import") (part "DIL24-3"))
    )
    (comp (ref "IC59")
      (value "DIL24-6")
      (footprint "eagle-import:DIL24-6")
      (libsource (lib "eagle-import") (part "DIL24-6"))
    )
    (comp (ref "IC60")
      (value "DIL24-9")
      (footprint "eagle-import:DIL24-9")
      (libsource (lib "eagle-import") (part "DIL24-9"))
    )
    (comp (ref "IC61")
      (value "DIL24-6")
      (footprint "eagle-import:DIL24-6")
      (libsource (lib "eagle-import") (part "DIL24-6"))
    )
    (comp (ref "IC62")
      (value "DIL24-3")
      (footprint "eagle-import:DIL24-3")
      (libsource (lib "eagle-import") (part "DIL24-3"))
    )
    (comp (ref "IC63")
      (value "DIL24-6")
      (footprint "eagle-import:DIL24-6")
      (libsource (lib "eagle-import") (part "DIL24-6"))
    )
    (comp (ref "IC64")
      (value "DIL24-9")
      (footprint "eagle-import:DIL24-9")
      (libsource (lib "eagle-import") (part "DIL24-9"))
    )
    (comp (ref "IC65")
      (value "DIL24-6")
      (footprint "eagle-import:DIL24-6")
      (libsource (lib "eagle-import") (part "DIL24-6"))
    )
    (comp (ref "IC66")
      (value "DIL24-3")
      (footprint "eagle-import:DIL24-3")
      (libsource (lib "eagle-import") (part "DIL24-3"))
    )
    (comp (ref "IC67")
      (value "DIL24-6")
      (footprint "eagle-import:DIL24-6")
      (libsource (lib "eagle-import") (part "DIL24-6"))
    )
    (comp (ref "IC68")
      (value "DIL24-9")
      (footprint "eagle-import:DIL24-9")
      (libsource (lib "eagle-import") (part "DIL24-9"))
    )
    (comp (ref "IC69")
      (value "DIL24-6")
      (footprint "eagle-import:DIL24-6")
      (libsource (lib "eagle-import") (part "DIL24-6"))
    )
    (comp (ref "IC70")
      (value "DIL24-3")
      (footprint "eagle-import:DIL24-3")
      (libsource (lib "eagle-import") (part "DIL24-3"))
    )
    (comp (ref "IC71")
      (value "DIL24-6")
      (footprint "eagle-import:DIL24-6")
      (libsource (lib "eagle-import") (part "DIL24-6"))
    )
    (comp (ref "IC72")
      (value "DIL24-9")
      (footprint "eagle-import:DIL24-9")
      (libsource (lib "eagle-import") (part "DIL24-9"))
    )
    (comp (ref "IC73")
      (value "DIL24-6")
      (footprint "eagle-import:DIL24-6")
      (libsource (lib "eagle-import") (part "DIL24-6"))
    )
    (comp (ref "IC74")
      (value "DIL24-3")
      (footprint "eagle-import:DIL24-3")
      (libsource (lib "eagle-import") (part "DIL24-3"))
    )
    (comp (ref "IC75")
      (value "DIL24-6")
      (footprint "eagle-import:DIL24-6")
      (libsource (lib "eagle-import") (part "DIL24-6"))
    )
    (comp (ref "IC76")
      (value "DIL24-9")
      (footprint "eagle-import:DIL24-9")
      (libsource (lib "eagle-import") (part "DIL24-9"))
    )
    (comp (ref "IC77")
      (value "DIL24-6")
      (footprint "eagle-import:DIL24-6")
      (libsource (lib "eagle-import") (part "DIL24-6"))
    )
    (comp (ref "IC78")
      (value "DIL24-3")
      (footprint "eagle-import:DIL24-3")
      (libsource (lib "eagle-import") (part "DIL24-3"))
    )
    (comp (ref "IC79")
      (value "DIL24-6")
      (footprint "eagle-import:DIL24-6")
      (libsource (lib "eagle-import") (part "DIL24-6"))
    )
    (comp (ref "IC80")
      (value "DIL24-9")
      (footprint "eagle-import:DIL24-9")
      (libsource (lib "eagle-import") (part "DIL24-9"))
    )
    (comp (ref "IC81")
      (value "DIL24-6")
      (footprint "eagle-import:DIL24-6")
      (libsource (lib "eagle-import") (part "DIL24-6"))
    )
    (comp (ref "IC82")
      (value "DIL24-3")
      (footprint "eagle-import:DIL24-3")
      (libsource (lib "eagle-import") (part "DIL24-3"))
    )
    (comp (ref "IC83")
      (value "DIL24-6")
      (footprint "eagle-import:DIL24-6")
      (libsource (lib "eagle-import") (part "DIL24-6"))
    )
    (comp (ref "IC84")
      (value "DIL24-9")
      (footprint "eagle-import:DIL24-9")
      (libsource (lib "eagle-import") (part "DIL24-9"))
    )
    (comp (ref "IC85")
      (value "DIL24-6")
      (footprint "eagle-import:DIL24-6")
      (libsource (lib "eagle-import") (part "DIL24-6"))
    )
    (comp (ref "IC86")
      (value "DIL24-3")
      (footprint "eagle-import:DIL24-3")
      (libsource (lib "eagle-import") (part "DIL24-3"))
    )
    (comp (ref "IC87")
      (value "DIL24-6")
      (footprint "eagle-import:DIL24-6")
      (libsource (lib "eagle-import") (part "DIL24-6"))
    )
    (comp (ref "IC88")
      (value "DIL24-9")
      (footprint "eagle-import:DIL24-9")
      (libsource (lib "eagle-import") (part "DIL24-9"))
    )
    (comp (ref "IC89")
      (value "DIL24-6")
      (footprint "eagle-import:DIL24-6")
      (libsource (lib "eagle-import") (part "DIL24-6"))
    )
    (comp (ref "IC90")
      (value "DIL24-3")
      (footprint "eagle-import:DIL24-3")
      (libsource (lib "eagle-import") (part "DIL24-3"))
    )
    (comp (ref "IC91")
      (value "DIL24-6")
      (footprint "eagle-import:DIL24-6")
      (libsource (lib "eagle-import") (part "DIL24-6"))
    )
    (comp (ref "IC92")
      (value "DIL24-9")
      (footprint "eagle-import:DIL24-9")
      (libsource (lib "eagle-import") (part "DIL24-9"))
    )
    (comp (ref "IC93")
      (value "DIL24-6")
      (footprint "eagle-import:DIL24-6")
      (libsource (lib "eagle-import") (part "DIL24-6"))
    )
    (comp (ref "IC94")
      (value "DIL24-3")
      (footprint "eagle-import:DIL24-3")
      (libsource (lib "eagle-import") (part "DIL24-3"))
    )
    (comp (ref "IC95")
      (value "DIL24-6")
      (footprint "eagle-import:DIL24-6")
      (libsource (lib "eagle-import") (part "DIL24-6"))
    )
    (comp (ref "IC96")
      (value "DIL24-9")
      (footprint "eagle-import:DIL24-9")
      (libsource (lib "eagle-import") (part "DIL24-9"))
    )
    (comp (ref "IC97")
      (value "DIL24-6")
      (footprint "eagle-import:DIL24-6")
      (libsource (lib "eagle-import") (part "DIL24-6"))
    )
    (comp (ref "IC98")
      (value "DIL24-3")
      (footprint "eagle-import:DIL24-3")
      (libsource (lib "eagle-import") (part "DIL24-3"))
    )
    (comp (ref "IC99")
      (value "DIL24-6")
      (footprint "eagle-import:DIL24-6")
      (libsource (lib "eagle-import") (part "DIL24-6"))
    )
    (comp (ref "IC100")
      (value "DIL24-9")
      (footprint "eagle-import:DIL24-9")
      (libsource (lib "eagle-import") (part "DIL24-9"))
    )
    (comp (ref "IC101")
      (value "DIL24-6")
      (footprint "eagle-import:DIL24-6")
      (libsource (lib "eagle-import") (part "DIL24-6"))
    )
    (comp (ref "IC102")
      (value "DIL24-3")
      (footprint "eagle-import:DIL24-3")
      (libsource (lib "eagle-import") (part "DIL24-3"))
    )
    (comp (ref "IC103")
      (value "DIL24-6")
      (footprint "eagle-import:DIL24-6")
      (libsource (lib "eagle-import") (part "DIL24-6"))
    )
    (comp (ref "IC104")
      (value "DIL24-9")
      (footprint "eagle-import:DIL24-9")
      (libsource (lib "eagle-import") (part "DIL24-9"))
    )
    (comp (ref "IC105")
      (value "DIL24-6")
      (footprint "eagle-import:DIL24-6")
      (libsource (lib "eagle-import") (part "DIL24-6"))
    )
    (comp (ref "IC106")
      (value "DIL24-3")
      (footprint "eagle-import:DIL24-3")
      (libsource (lib "eagle-import") (part "DIL24-3"))
    )
    (comp (ref "IC107")
      (value "DIL24-6")
      (footprint "eagle-import:DIL24-6")
      (libsource (lib "eagle-import") (part "DIL24-6"))
    )
    (comp (ref "IC108")
      (value "DIL24-9")
      (footprint "eagle-import:DIL24-9")
      (libsource (lib "eagle-import") (part "DIL24-9"))
    )
    (comp (ref "IC109")
      (value "DIL24-6")
      (footprint "eagle-import:DIL24-6")
      (libsource (lib "eagle-import") (part "DIL24-6"))
    )
    (comp (ref "SV1")
      (value "MA12-1")
      (footprint "eagle-import:MA12-1")
      (libsource (lib "eagle-import") (part "MA12-1"))
    )
    (comp (ref "SV2")
      (value "MA12-1")
      (footprint "eagle-import:MA12-1")
      (libsource (lib "eagle-import") (part "MA12-1"))
    )
    (comp (ref "SV3")
      (value "MA12-1")
      (footprint "eagle-import:MA12-1")
      (libsource (lib "eagle-import") (part "MA12-1"))
    )
    (comp (ref "SV4")
      (value "MA12-1")
      (footprint "eagle-import:MA12-1")
      (libsource (lib "eagle-import") (part "MA12-1"))
    )
    (comp (ref "SV5")
      (value "MA12-1")
      (footprint "eagle-import:MA12-1")
      (libsource (lib "eagle-import") (part "MA12-1"))
    )
    (comp (ref "SV6")
      (value "MA12-1")
      (footprint "eagle-import:MA12-1")
      (libsource (lib "eagle-import") (part "MA12-1"))
    )
    (comp (ref "SV7")
      (value "MA12-1")
      (footprint "eagle-import:MA12-1")
      (libsource (lib "eagle-import") (part "MA12-1"))
    )
    (comp (ref "SV8")
      (value "MA12-1")
      (footprint "eagle-import:MA12-1")
      (libsource (lib "eagle-import") (part "MA12-1"))
    )
    (comp (ref "SV9")
      (value "MA12-1")
      (footprint "eagle-import:MA12-1")
      (libsource (lib "eagle-import") (part "MA12-1"))
    )
    (comp (ref "SV10")
      (value "MA12-1")
      (footprint "eagle-import:MA12-1")
      (libsource (lib "eagle-import") (part "MA12-1"))
    )
    (comp (ref "SV11")
      (value "MA12-1")
      (footprint "eagle-import:MA12-1")
      (libsource (lib "eagle-import") (part "MA12-1"))
    )
    (comp (ref "SV12")
      (value "MA12-1")
      (footprint "eagle-import:MA12-1")
      (libsource (lib "eagle-import") (part "MA12-1"))
    )
    (comp (ref "SV13")
      (value "MA12-1")
      (footprint "eagle-import:MA12-1")
      (libsource (lib "eagle-import") (part "MA12-1"))
    )
    (comp (ref "SV14")
      (value "MA12-1")
      (footprint "eagle-import:MA12-1")
      (libsource (lib "eagle-import") (part "MA12-1"))
    )
    (comp (ref "SV15")
      (value "MA12-1")
      (footprint "eagle-import:MA12-1")
      (libsource (lib "eagle-import") (part "MA12-1"))
    )
    (comp (ref "SV16")
      (value "MA12-1")
      (footprint "eagle-import:MA12-1")
      (libsource (lib "eagle-import") (part "MA12-1"))
    )
    (comp (ref "SV17")
      (value "MA12-1")
      (footprint "eagle-import:MA12-1")
      (libsource (lib "eagle-import") (part "MA12-1"))
    )
    (comp (ref "SV18")
      (value "MA12-1")
      (footprint "eagle-import:MA12-1")
      (libsource (lib "eagle-import") (part "MA12-1"))
    )
    (comp (ref "SV19")
      (value "MA12-1")
      (footprint "eagle-import:MA12-1")
      (libsource (lib "eagle-import") (part "MA12-1"))
    )
    (comp (ref "SV20")
      (value "MA12-1")
      (footprint "eagle-import:MA12-1")
      (libsource (lib "eagle-import") (part "MA12-1"))
    )
    (comp (ref "SV21")
      (value "MA12-1")
      (footprint "eagle-import:MA12-1")
      (libsource (lib "eagle-import") (part "MA12-1"))
    )
    (comp (ref "SV22")
      (value "MA12-1")
      (footprint "eagle-import:MA12-1")
      (libsource (lib "eagle-import") (part "MA12-1"))
    )
    (comp (ref "SV23")
      (value "MA12-1")
      (footprint "eagle-import:MA12-1")
      (libsource (lib "eagle-import") (part "MA12-1"))
    )
    (comp (ref "SV24")
      (value "MA12-1")
      (footprint "eagle-import:MA12-1")
      (libsource (lib "eagle-import") (part "MA12-1"))
    )
    (comp (ref "SV25")
      (value "MA12-1")
      (footprint "eagle-import:MA12-1")
      (libsource (lib "eagle-import") (part "MA12-1"))
    )
    (comp (ref "SV26")
      (value "MA12-1")
      (footprint "eagle-import:MA12-1")
      (libsource (lib "eagle-import") (part "MA12-1"))
    )
    (comp (ref "SV27")
      (value "MA12-1")
      (footprint "eagle-import:MA12-1")
      (libsource (lib "eagle-import") (part "MA12-1"))
    )
    (comp (ref "SV28")
      (value "MA12-1")
      (footprint "eagle-import:MA12-1")
      (libsource (lib "eagle-import") (part "MA12-1"))
    )
    (comp (ref "SV29")
      (value "MA12-1")
      (footprint "eagle-import:MA12-1")
      (libsource (lib "eagle-import") (part "MA12-1"))
    )
    (comp (ref "SV30")
      (value "MA12-1")
      (footprint "eagle-import:MA12-1")
      (libsource (lib "eagle-import") (part "MA12-1"))
    )
    (comp (ref "SV31")
      (value "MA12-1")
      (footprint "eagle-import:MA12-1")
      (libsource (lib "eagle-import") (part "MA12-1"))
    )
    (comp (ref "SV32")
      (value "MA12-1")
      (footprint "eagle-import:MA12-1")
      (libsource (lib "eagle-import") (part "MA12-1"))
    )
    (comp (ref "SV33")
      (value "MA12-1")
      (footprint "eagle-import:MA12-1")
      (libsource (lib "eagle-import") (part "MA12-1"))
    )
    (comp (ref "SV34")
      (value "MA12-1")
      (footprint "eagle-import:MA12-1")
      (libsource (lib "eagle-import") (part "MA12-1"))
    )
    (comp (ref "SV35")
      (value "MA12-1")
      (footprint "eagle-import:MA12-1")
      (libsource (lib "eagle-import") (part "MA12-1"))
    )
    (comp (ref "SV36")
      (value "MA12-1")
      (footprint "eagle-import:MA12-1")
      (libsource (lib "eagle-import") (part "MA12-1"))
    )
    (comp (ref "SV37")
      (value "MA12-1")
      (footprint "eagle-import:MA12-1")
      (libsource (lib "eagle-import") (part "MA12-1"))
    )
    (comp (ref "SV38")
      (value "MA12-1")
      (footprint "eagle-import:MA12-1")
      (libsource (lib "eagle-import") (part "MA12-1"))
    )
    (comp (ref "SV39")
      (value "MA12-1")
      (footprint "eagle-import:MA12-1")
      (libsource (lib "eagle-import") (part "MA12-1"))
    )
    (comp (ref "SV40")
      (value "MA12-1")
      (footprint "eagle-import:MA12-1")
      (libsource (lib "eagle-import") (part "MA12-1"))
    )
    (comp (ref "SV183")
      (value "MA12-1")
      (footprint "eagle-import:MA12-1")
      (libsource (lib "eagle-import") (part "MA12-1"))
    )
    (comp (ref "SV184")
      (value "MA12-1")
      (footprint "eagle-import:MA12-1")
      (libsource (lib "eagle-import") (part "MA12-1"))
    )
    (comp (ref "SV185")
      (value "MA12-1")
      (footprint "eagle-import:MA12-1")
      (libsource (lib "eagle-import") (part "MA12-1"))
    )
    (comp (ref "SV186")
      (value "MA12-1")
      (footprint "eagle-import:MA12-1")
      (libsource (lib "eagle-import") (part "MA12-1"))
    )
    (comp (ref "SV187")
      (value "MA12-1")
      (footprint "eagle-import:MA12-1")
      (libsource (lib "eagle-import") (part "MA12-1"))
    )
    (comp (ref "SV188")
      (value "MA12-1")
      (footprint "eagle-import:MA12-1")
      (libsource (lib "eagle-import") (part "MA12-1"))
    )
    (comp (ref "SV189")
      (value "MA12-1")
      (footprint "eagle-import:MA12-1")
      (libsource (lib "eagle-import") (part "MA12-1"))
    )
    (comp (ref "SV190")
      (value "MA12-1")
      (footprint "eagle-import:MA12-1")
      (libsource (lib "eagle-import") (part "MA12-1"))
    )
    (comp (ref "SV191")
      (value "MA12-1")
      (footprint "eagle-import:MA12-1")
      (libsource (lib "eagle-import") (part "MA12-1"))
    )
    (comp (ref "SV192")
      (value "MA12-1")
      (footprint "eagle-import:MA12-1")
      (libsource (lib "eagle-import") (part "MA12-1"))
    )
    (comp (ref "JP1")
      (value "JP1Q")
      (footprint "eagle-import:JP1")
      (libsource (lib "eagle-import") (part "JP1Q"))
    )
    (comp (ref "JP2")
      (value "JP1Q")
      (footprint "eagle-import:JP1")
      (libsource (lib "eagle-import") (part "JP1Q"))
    )
    (comp (ref "JP3")
      (value "JP1Q")
      (footprint "eagle-import:JP1")
      (libsource (lib "eagle-import") (part "JP1Q"))
    )
    (comp (ref "JP4")
      (value "JP1Q")
      (footprint "eagle-import:JP1")
      (libsource (lib "eagle-import") (part "JP1Q"))
    )
    (comp (ref "SV41")
      (value "MA09-1")
      (footprint "eagle-import:MA09-1")
      (libsource (lib "eagle-import") (part "MA09-1"))
    )
    (comp (ref "SV92")
      (value "MA09-1")
      (footprint "eagle-import:MA09-1")
      (libsource (lib "eagle-import") (part "MA09-1"))
    )
    (comp (ref "SV93")
      (value "MA03-1")
      (footprint "eagle-import:MA03-1")
      (libsource (lib "eagle-import") (part "MA03-1"))
    )
    (comp (ref "SV94")
      (value "MA03-1")
      (footprint "eagle-import:MA03-1")
      (libsource (lib "eagle-import") (part "MA03-1"))
    )
    (comp (ref "SV95")
      (value "MA03-1")
      (footprint "eagle-import:MA03-1")
      (libsource (lib "eagle-import") (part "MA03-1"))
    )
    (comp (ref "SV96")
      (value "MA03-1")
      (footprint "eagle-import:MA03-1")
      (libsource (lib "eagle-import") (part "MA03-1"))
    )
    (comp (ref "SV97")
      (value "MA01-1")
      (footprint "eagle-import:MA01-1")
      (libsource (lib "eagle-import") (part "MA01-1"))
    )
    (comp (ref "SV104")
      (value "MA09-1")
      (footprint "eagle-import:MA09-1")
      (libsource (lib "eagle-import") (part "MA09-1"))
    )
    (comp (ref "SV105")
      (value "MA09-1")
      (footprint "eagle-import:MA09-1")
      (libsource (lib "eagle-import") (part "MA09-1"))
    )
    (comp (ref "SV106")
      (value "MA09-1")
      (footprint "eagle-import:MA09-1")
      (libsource (lib "eagle-import") (part "MA09-1"))
    )
    (comp (ref "SV107")
      (value "MA09-1")
      (footprint "eagle-import:MA09-1")
      (libsource (lib "eagle-import") (part "MA09-1"))
    )
    (comp (ref "SV108")
      (value "MA09-1")
      (footprint "eagle-import:MA09-1")
      (libsource (lib "eagle-import") (part "MA09-1"))
    )
    (comp (ref "SV109")
      (value "MA09-1")
      (footprint "eagle-import:MA09-1")
      (libsource (lib "eagle-import") (part "MA09-1"))
    )
    (comp (ref "SV110")
      (value "MA09-1")
      (footprint "eagle-import:MA09-1")
      (libsource (lib "eagle-import") (part "MA09-1"))
    )
    (comp (ref "SV111")
      (value "MA09-1")
      (footprint "eagle-import:MA09-1")
      (libsource (lib "eagle-import") (part "MA09-1"))
    )
    (comp (ref "SV112")
      (value "MA09-1")
      (footprint "eagle-import:MA09-1")
      (libsource (lib "eagle-import") (part "MA09-1"))
    )
    (comp (ref "SV113")
      (value "MA09-1")
      (footprint "eagle-import:MA09-1")
      (libsource (lib "eagle-import") (part "MA09-1"))
    )
    (comp (ref "SV114")
      (value "MA09-1")
      (footprint "eagle-import:MA09-1")
      (libsource (lib "eagle-import") (part "MA09-1"))
    )
    (comp (ref "SV115")
      (value "MA09-1")
      (footprint "eagle-import:MA09-1")
      (libsource (lib "eagle-import") (part "MA09-1"))
    )
    (comp (ref "SV116")
      (value "MA09-1")
      (footprint "eagle-import:MA09-1")
      (libsource (lib "eagle-import") (part "MA09-1"))
    )
    (comp (ref "SV117")
      (value "MA09-1")
      (footprint "eagle-import:MA09-1")
      (libsource (lib "eagle-import") (part "MA09-1"))
    )
    (comp (ref "U$1")
      (value "OUTLINE-OMNIBUS")
      (footprint "eagle-import:OMNIBUS")
      (libsource (lib "eagle-import") (part "OUTLINE-OMNIBUS"))
    )
    (comp (ref "U$2")
      (value "QUAD")
      (footprint "eagle-import:EDGE-CON8")
      (libsource (lib "eagle-import") (part "QUAD"))
    )
  )
  (nets
    (net (code "1") (name "GND") (class "Default")
      (node (ref "C1") (pin "-") (pinfunction "-_-") (pintype "passive"))
      (node (ref "C2") (pin "-") (pinfunction "-_-") (pintype "passive"))
      (node (ref "C3") (pin "-") (pinfunction "-_-") (pintype "passive"))
      (node (ref "C4") (pin "-") (pinfunction "-_-") (pintype "passive"))
      (node (ref "JP1") (pin "2") (pinfunction "2_2") (pintype "passive"))
      (node (ref "JP2") (pin "2") (pinfunction "2_2") (pintype "passive"))
      (node (ref "JP3") (pin "2") (pinfunction "2_2") (pintype "passive"))
      (node (ref "JP4") (pin "2") (pinfunction "2_2") (pintype "passive"))
      (node (ref "SV10") (pin "1") (pinfunction "1_1") (pintype "passive"))
      (node (ref "SV10") (pin "10") (pinfunction "10_10") (pintype "passive"))
      (node (ref "SV10") (pin "11") (pinfunction "11_11") (pintype "passive"))
      (node (ref "SV10") (pin "12") (pinfunction "12_12") (pintype "passive"))
      (node (ref "SV10") (pin "2") (pinfunction "2_2") (pintype "passive"))
      (node (ref "SV10") (pin "3") (pinfunction "3_3") (pintype "passive"))
      (node (ref "SV10") (pin "4") (pinfunction "4_4") (pintype "passive"))
      (node (ref "SV10") (pin "5") (pinfunction "5_5") (pintype "passive"))
      (node (ref "SV10") (pin "6") (pinfunction "6_6") (pintype "passive"))
      (node (ref "SV10") (pin "7") (pinfunction "7_7") (pintype "passive"))
      (node (ref "SV10") (pin "8") (pinfunction "8_8") (pintype "passive"))
      (node (ref "SV10") (pin "9") (pinfunction "9_9") (pintype "passive"))
      (node (ref "SV12") (pin "1") (pinfunction "1_1") (pintype "passive"))
      (node (ref "SV12") (pin "10") (pinfunction "10_10") (pintype "passive"))
      (node (ref "SV12") (pin "11") (pinfunction "11_11") (pintype "passive"))
      (node (ref "SV12") (pin "12") (pinfunction "12_12") (pintype "passive"))
      (node (ref "SV12") (pin "2") (pinfunction "2_2") (pintype "passive"))
      (node (ref "SV12") (pin "3") (pinfunction "3_3") (pintype "passive"))
      (node (ref "SV12") (pin "4") (pinfunction "4_4") (pintype "passive"))
      (node (ref "SV12") (pin "5") (pinfunction "5_5") (pintype "passive"))
      (node (ref "SV12") (pin "6") (pinfunction "6_6") (pintype "passive"))
      (node (ref "SV12") (pin "7") (pinfunction "7_7") (pintype "passive"))
      (node (ref "SV12") (pin "8") (pinfunction "8_8") (pintype "passive"))
      (node (ref "SV12") (pin "9") (pinfunction "9_9") (pintype "passive"))
      (node (ref "SV14") (pin "1") (pinfunction "1_1") (pintype "passive"))
      (node (ref "SV14") (pin "10") (pinfunction "10_10") (pintype "passive"))
      (node (ref "SV14") (pin "11") (pinfunction "11_11") (pintype "passive"))
      (node (ref "SV14") (pin "12") (pinfunction "12_12") (pintype "passive"))
      (node (ref "SV14") (pin "2") (pinfunction "2_2") (pintype "passive"))
      (node (ref "SV14") (pin "3") (pinfunction "3_3") (pintype "passive"))
      (node (ref "SV14") (pin "4") (pinfunction "4_4") (pintype "passive"))
      (node (ref "SV14") (pin "5") (pinfunction "5_5") (pintype "passive"))
      (node (ref "SV14") (pin "6") (pinfunction "6_6") (pintype "passive"))
      (node (ref "SV14") (pin "7") (pinfunction "7_7") (pintype "passive"))
      (node (ref "SV14") (pin "8") (pinfunction "8_8") (pintype "passive"))
      (node (ref "SV14") (pin "9") (pinfunction "9_9") (pintype "passive"))
      (node (ref "SV16") (pin "1") (pinfunction "1_1") (pintype "passive"))
      (node (ref "SV16") (pin "10") (pinfunction "10_10") (pintype "passive"))
      (node (ref "SV16") (pin "11") (pinfunction "11_11") (pintype "passive"))
      (node (ref "SV16") (pin "12") (pinfunction "12_12") (pintype "passive"))
      (node (ref "SV16") (pin "2") (pinfunction "2_2") (pintype "passive"))
      (node (ref "SV16") (pin "3") (pinfunction "3_3") (pintype "passive"))
      (node (ref "SV16") (pin "4") (pinfunction "4_4") (pintype "passive"))
      (node (ref "SV16") (pin "5") (pinfunction "5_5") (pintype "passive"))
      (node (ref "SV16") (pin "6") (pinfunction "6_6") (pintype "passive"))
      (node (ref "SV16") (pin "7") (pinfunction "7_7") (pintype "passive"))
      (node (ref "SV16") (pin "8") (pinfunction "8_8") (pintype "passive"))
      (node (ref "SV16") (pin "9") (pinfunction "9_9") (pintype "passive"))
      (node (ref "SV18") (pin "1") (pinfunction "1_1") (pintype "passive"))
      (node (ref "SV18") (pin "10") (pinfunction "10_10") (pintype "passive"))
      (node (ref "SV18") (pin "11") (pinfunction "11_11") (pintype "passive"))
      (node (ref "SV18") (pin "12") (pinfunction "12_12") (pintype "passive"))
      (node (ref "SV18") (pin "2") (pinfunction "2_2") (pintype "passive"))
      (node (ref "SV18") (pin "3") (pinfunction "3_3") (pintype "passive"))
      (node (ref "SV18") (pin "4") (pinfunction "4_4") (pintype "passive"))
      (node (ref "SV18") (pin "5") (pinfunction "5_5") (pintype "passive"))
      (node (ref "SV18") (pin "6") (pinfunction "6_6") (pintype "passive"))
      (node (ref "SV18") (pin "7") (pinfunction "7_7") (pintype "passive"))
      (node (ref "SV18") (pin "8") (pinfunction "8_8") (pintype "passive"))
      (node (ref "SV18") (pin "9") (pinfunction "9_9") (pintype "passive"))
      (node (ref "SV184") (pin "1") (pinfunction "1_1") (pintype "passive"))
      (node (ref "SV184") (pin "10") (pinfunction "10_10") (pintype "passive"))
      (node (ref "SV184") (pin "11") (pinfunction "11_11") (pintype "passive"))
      (node (ref "SV184") (pin "12") (pinfunction "12_12") (pintype "passive"))
      (node (ref "SV184") (pin "2") (pinfunction "2_2") (pintype "passive"))
      (node (ref "SV184") (pin "3") (pinfunction "3_3") (pintype "passive"))
      (node (ref "SV184") (pin "4") (pinfunction "4_4") (pintype "passive"))
      (node (ref "SV184") (pin "5") (pinfunction "5_5") (pintype "passive"))
      (node (ref "SV184") (pin "6") (pinfunction "6_6") (pintype "passive"))
      (node (ref "SV184") (pin "7") (pinfunction "7_7") (pintype "passive"))
      (node (ref "SV184") (pin "8") (pinfunction "8_8") (pintype "passive"))
      (node (ref "SV184") (pin "9") (pinfunction "9_9") (pintype "passive"))
      (node (ref "SV186") (pin "1") (pinfunction "1_1") (pintype "passive"))
      (node (ref "SV186") (pin "10") (pinfunction "10_10") (pintype "passive"))
      (node (ref "SV186") (pin "11") (pinfunction "11_11") (pintype "passive"))
      (node (ref "SV186") (pin "12") (pinfunction "12_12") (pintype "passive"))
      (node (ref "SV186") (pin "2") (pinfunction "2_2") (pintype "passive"))
      (node (ref "SV186") (pin "3") (pinfunction "3_3") (pintype "passive"))
      (node (ref "SV186") (pin "4") (pinfunction "4_4") (pintype "passive"))
      (node (ref "SV186") (pin "5") (pinfunction "5_5") (pintype "passive"))
      (node (ref "SV186") (pin "6") (pinfunction "6_6") (pintype "passive"))
      (node (ref "SV186") (pin "7") (pinfunction "7_7") (pintype "passive"))
      (node (ref "SV186") (pin "8") (pinfunction "8_8") (pintype "passive"))
      (node (ref "SV186") (pin "9") (pinfunction "9_9") (pintype "passive"))
      (node (ref "SV188") (pin "1") (pinfunction "1_1") (pintype "passive"))
      (node (ref "SV188") (pin "10") (pinfunction "10_10") (pintype "passive"))
      (node (ref "SV188") (pin "11") (pinfunction "11_11") (pintype "passive"))
      (node (ref "SV188") (pin "12") (pinfunction "12_12") (pintype "passive"))
      (node (ref "SV188") (pin "2") (pinfunction "2_2") (pintype "passive"))
      (node (ref "SV188") (pin "3") (pinfunction "3_3") (pintype "passive"))
      (node (ref "SV188") (pin "4") (pinfunction "4_4") (pintype "passive"))
      (node (ref "SV188") (pin "5") (pinfunction "5_5") (pintype "passive"))
      (node (ref "SV188") (pin "6") (pinfunction "6_6") (pintype "passive"))
      (node (ref "SV188") (pin "7") (pinfunction "7_7") (pintype "passive"))
      (node (ref "SV188") (pin "8") (pinfunction "8_8") (pintype "passive"))
      (node (ref "SV188") (pin "9") (pinfunction "9_9") (pintype "passive"))
      (node (ref "SV190") (pin "1") (pinfunction "1_1") (pintype "passive"))
      (node (ref "SV190") (pin "10") (pinfunction "10_10") (pintype "passive"))
      (node (ref "SV190") (pin "11") (pinfunction "11_11") (pintype "passive"))
      (node (ref "SV190") (pin "12") (pinfunction "12_12") (pintype "passive"))
      (node (ref "SV190") (pin "2") (pinfunction "2_2") (pintype "passive"))
      (node (ref "SV190") (pin "3") (pinfunction "3_3") (pintype "passive"))
      (node (ref "SV190") (pin "4") (pinfunction "4_4") (pintype "passive"))
      (node (ref "SV190") (pin "5") (pinfunction "5_5") (pintype "passive"))
      (node (ref "SV190") (pin "6") (pinfunction "6_6") (pintype "passive"))
      (node (ref "SV190") (pin "7") (pinfunction "7_7") (pintype "passive"))
      (node (ref "SV190") (pin "8") (pinfunction "8_8") (pintype "passive"))
      (node (ref "SV190") (pin "9") (pinfunction "9_9") (pintype "passive"))
      (node (ref "SV192") (pin "1") (pinfunction "1_1") (pintype "passive"))
      (node (ref "SV192") (pin "10") (pinfunction "10_10") (pintype "passive"))
      (node (ref "SV192") (pin "11") (pinfunction "11_11") (pintype "passive"))
      (node (ref "SV192") (pin "12") (pinfunction "12_12") (pintype "passive"))
      (node (ref "SV192") (pin "2") (pinfunction "2_2") (pintype "passive"))
      (node (ref "SV192") (pin "3") (pinfunction "3_3") (pintype "passive"))
      (node (ref "SV192") (pin "4") (pinfunction "4_4") (pintype "passive"))
      (node (ref "SV192") (pin "5") (pinfunction "5_5") (pintype "passive"))
      (node (ref "SV192") (pin "6") (pinfunction "6_6") (pintype "passive"))
      (node (ref "SV192") (pin "7") (pinfunction "7_7") (pintype "passive"))
      (node (ref "SV192") (pin "8") (pinfunction "8_8") (pintype "passive"))
      (node (ref "SV192") (pin "9") (pinfunction "9_9") (pintype "passive"))
      (node (ref "SV2") (pin "1") (pinfunction "1_1") (pintype "passive"))
      (node (ref "SV2") (pin "10") (pinfunction "10_10") (pintype "passive"))
      (node (ref "SV2") (pin "11") (pinfunction "11_11") (pintype "passive"))
      (node (ref "SV2") (pin "12") (pinfunction "12_12") (pintype "passive"))
      (node (ref "SV2") (pin "2") (pinfunction "2_2") (pintype "passive"))
      (node (ref "SV2") (pin "3") (pinfunction "3_3") (pintype "passive"))
      (node (ref "SV2") (pin "4") (pinfunction "4_4") (pintype "passive"))
      (node (ref "SV2") (pin "5") (pinfunction "5_5") (pintype "passive"))
      (node (ref "SV2") (pin "6") (pinfunction "6_6") (pintype "passive"))
      (node (ref "SV2") (pin "7") (pinfunction "7_7") (pintype "passive"))
      (node (ref "SV2") (pin "8") (pinfunction "8_8") (pintype "passive"))
      (node (ref "SV2") (pin "9") (pinfunction "9_9") (pintype "passive"))
      (node (ref "SV20") (pin "1") (pinfunction "1_1") (pintype "passive"))
      (node (ref "SV20") (pin "10") (pinfunction "10_10") (pintype "passive"))
      (node (ref "SV20") (pin "11") (pinfunction "11_11") (pintype "passive"))
      (node (ref "SV20") (pin "12") (pinfunction "12_12") (pintype "passive"))
      (node (ref "SV20") (pin "2") (pinfunction "2_2") (pintype "passive"))
      (node (ref "SV20") (pin "3") (pinfunction "3_3") (pintype "passive"))
      (node (ref "SV20") (pin "4") (pinfunction "4_4") (pintype "passive"))
      (node (ref "SV20") (pin "5") (pinfunction "5_5") (pintype "passive"))
      (node (ref "SV20") (pin "6") (pinfunction "6_6") (pintype "passive"))
      (node (ref "SV20") (pin "7") (pinfunction "7_7") (pintype "passive"))
      (node (ref "SV20") (pin "8") (pinfunction "8_8") (pintype "passive"))
      (node (ref "SV20") (pin "9") (pinfunction "9_9") (pintype "passive"))
      (node (ref "SV22") (pin "1") (pinfunction "1_1") (pintype "passive"))
      (node (ref "SV22") (pin "10") (pinfunction "10_10") (pintype "passive"))
      (node (ref "SV22") (pin "11") (pinfunction "11_11") (pintype "passive"))
      (node (ref "SV22") (pin "12") (pinfunction "12_12") (pintype "passive"))
      (node (ref "SV22") (pin "2") (pinfunction "2_2") (pintype "passive"))
      (node (ref "SV22") (pin "3") (pinfunction "3_3") (pintype "passive"))
      (node (ref "SV22") (pin "4") (pinfunction "4_4") (pintype "passive"))
      (node (ref "SV22") (pin "5") (pinfunction "5_5") (pintype "passive"))
      (node (ref "SV22") (pin "6") (pinfunction "6_6") (pintype "passive"))
      (node (ref "SV22") (pin "7") (pinfunction "7_7") (pintype "passive"))
      (node (ref "SV22") (pin "8") (pinfunction "8_8") (pintype "passive"))
      (node (ref "SV22") (pin "9") (pinfunction "9_9") (pintype "passive"))
      (node (ref "SV24") (pin "1") (pinfunction "1_1") (pintype "passive"))
      (node (ref "SV24") (pin "10") (pinfunction "10_10") (pintype "passive"))
      (node (ref "SV24") (pin "11") (pinfunction "11_11") (pintype "passive"))
      (node (ref "SV24") (pin "12") (pinfunction "12_12") (pintype "passive"))
      (node (ref "SV24") (pin "2") (pinfunction "2_2") (pintype "passive"))
      (node (ref "SV24") (pin "3") (pinfunction "3_3") (pintype "passive"))
      (node (ref "SV24") (pin "4") (pinfunction "4_4") (pintype "passive"))
      (node (ref "SV24") (pin "5") (pinfunction "5_5") (pintype "passive"))
      (node (ref "SV24") (pin "6") (pinfunction "6_6") (pintype "passive"))
      (node (ref "SV24") (pin "7") (pinfunction "7_7") (pintype "passive"))
      (node (ref "SV24") (pin "8") (pinfunction "8_8") (pintype "passive"))
      (node (ref "SV24") (pin "9") (pinfunction "9_9") (pintype "passive"))
      (node (ref "SV26") (pin "1") (pinfunction "1_1") (pintype "passive"))
      (node (ref "SV26") (pin "10") (pinfunction "10_10") (pintype "passive"))
      (node (ref "SV26") (pin "11") (pinfunction "11_11") (pintype "passive"))
      (node (ref "SV26") (pin "12") (pinfunction "12_12") (pintype "passive"))
      (node (ref "SV26") (pin "2") (pinfunction "2_2") (pintype "passive"))
      (node (ref "SV26") (pin "3") (pinfunction "3_3") (pintype "passive"))
      (node (ref "SV26") (pin "4") (pinfunction "4_4") (pintype "passive"))
      (node (ref "SV26") (pin "5") (pinfunction "5_5") (pintype "passive"))
      (node (ref "SV26") (pin "6") (pinfunction "6_6") (pintype "passive"))
      (node (ref "SV26") (pin "7") (pinfunction "7_7") (pintype "passive"))
      (node (ref "SV26") (pin "8") (pinfunction "8_8") (pintype "passive"))
      (node (ref "SV26") (pin "9") (pinfunction "9_9") (pintype "passive"))
      (node (ref "SV28") (pin "1") (pinfunction "1_1") (pintype "passive"))
      (node (ref "SV28") (pin "10") (pinfunction "10_10") (pintype "passive"))
      (node (ref "SV28") (pin "11") (pinfunction "11_11") (pintype "passive"))
      (node (ref "SV28") (pin "12") (pinfunction "12_12") (pintype "passive"))
      (node (ref "SV28") (pin "2") (pinfunction "2_2") (pintype "passive"))
      (node (ref "SV28") (pin "3") (pinfunction "3_3") (pintype "passive"))
      (node (ref "SV28") (pin "4") (pinfunction "4_4") (pintype "passive"))
      (node (ref "SV28") (pin "5") (pinfunction "5_5") (pintype "passive"))
      (node (ref "SV28") (pin "6") (pinfunction "6_6") (pintype "passive"))
      (node (ref "SV28") (pin "7") (pinfunction "7_7") (pintype "passive"))
      (node (ref "SV28") (pin "8") (pinfunction "8_8") (pintype "passive"))
      (node (ref "SV28") (pin "9") (pinfunction "9_9") (pintype "passive"))
      (node (ref "SV30") (pin "1") (pinfunction "1_1") (pintype "passive"))
      (node (ref "SV30") (pin "10") (pinfunction "10_10") (pintype "passive"))
      (node (ref "SV30") (pin "11") (pinfunction "11_11") (pintype "passive"))
      (node (ref "SV30") (pin "12") (pinfunction "12_12") (pintype "passive"))
      (node (ref "SV30") (pin "2") (pinfunction "2_2") (pintype "passive"))
      (node (ref "SV30") (pin "3") (pinfunction "3_3") (pintype "passive"))
      (node (ref "SV30") (pin "4") (pinfunction "4_4") (pintype "passive"))
      (node (ref "SV30") (pin "5") (pinfunction "5_5") (pintype "passive"))
      (node (ref "SV30") (pin "6") (pinfunction "6_6") (pintype "passive"))
      (node (ref "SV30") (pin "7") (pinfunction "7_7") (pintype "passive"))
      (node (ref "SV30") (pin "8") (pinfunction "8_8") (pintype "passive"))
      (node (ref "SV30") (pin "9") (pinfunction "9_9") (pintype "passive"))
      (node (ref "SV32") (pin "1") (pinfunction "1_1") (pintype "passive"))
      (node (ref "SV32") (pin "10") (pinfunction "10_10") (pintype "passive"))
      (node (ref "SV32") (pin "11") (pinfunction "11_11") (pintype "passive"))
      (node (ref "SV32") (pin "12") (pinfunction "12_12") (pintype "passive"))
      (node (ref "SV32") (pin "2") (pinfunction "2_2") (pintype "passive"))
      (node (ref "SV32") (pin "3") (pinfunction "3_3") (pintype "passive"))
      (node (ref "SV32") (pin "4") (pinfunction "4_4") (pintype "passive"))
      (node (ref "SV32") (pin "5") (pinfunction "5_5") (pintype "passive"))
      (node (ref "SV32") (pin "6") (pinfunction "6_6") (pintype "passive"))
      (node (ref "SV32") (pin "7") (pinfunction "7_7") (pintype "passive"))
      (node (ref "SV32") (pin "8") (pinfunction "8_8") (pintype "passive"))
      (node (ref "SV32") (pin "9") (pinfunction "9_9") (pintype "passive"))
      (node (ref "SV34") (pin "1") (pinfunction "1_1") (pintype "passive"))
      (node (ref "SV34") (pin "10") (pinfunction "10_10") (pintype "passive"))
      (node (ref "SV34") (pin "11") (pinfunction "11_11") (pintype "passive"))
      (node (ref "SV34") (pin "12") (pinfunction "12_12") (pintype "passive"))
      (node (ref "SV34") (pin "2") (pinfunction "2_2") (pintype "passive"))
      (node (ref "SV34") (pin "3") (pinfunction "3_3") (pintype "passive"))
      (node (ref "SV34") (pin "4") (pinfunction "4_4") (pintype "passive"))
      (node (ref "SV34") (pin "5") (pinfunction "5_5") (pintype "passive"))
      (node (ref "SV34") (pin "6") (pinfunction "6_6") (pintype "passive"))
      (node (ref "SV34") (pin "7") (pinfunction "7_7") (pintype "passive"))
      (node (ref "SV34") (pin "8") (pinfunction "8_8") (pintype "passive"))
      (node (ref "SV34") (pin "9") (pinfunction "9_9") (pintype "passive"))
      (node (ref "SV36") (pin "1") (pinfunction "1_1") (pintype "passive"))
      (node (ref "SV36") (pin "10") (pinfunction "10_10") (pintype "passive"))
      (node (ref "SV36") (pin "11") (pinfunction "11_11") (pintype "passive"))
      (node (ref "SV36") (pin "12") (pinfunction "12_12") (pintype "passive"))
      (node (ref "SV36") (pin "2") (pinfunction "2_2") (pintype "passive"))
      (node (ref "SV36") (pin "3") (pinfunction "3_3") (pintype "passive"))
      (node (ref "SV36") (pin "4") (pinfunction "4_4") (pintype "passive"))
      (node (ref "SV36") (pin "5") (pinfunction "5_5") (pintype "passive"))
      (node (ref "SV36") (pin "6") (pinfunction "6_6") (pintype "passive"))
      (node (ref "SV36") (pin "7") (pinfunction "7_7") (pintype "passive"))
      (node (ref "SV36") (pin "8") (pinfunction "8_8") (pintype "passive"))
      (node (ref "SV36") (pin "9") (pinfunction "9_9") (pintype "passive"))
      (node (ref "SV38") (pin "1") (pinfunction "1_1") (pintype "passive"))
      (node (ref "SV38") (pin "10") (pinfunction "10_10") (pintype "passive"))
      (node (ref "SV38") (pin "11") (pinfunction "11_11") (pintype "passive"))
      (node (ref "SV38") (pin "12") (pinfunction "12_12") (pintype "passive"))
      (node (ref "SV38") (pin "2") (pinfunction "2_2") (pintype "passive"))
      (node (ref "SV38") (pin "3") (pinfunction "3_3") (pintype "passive"))
      (node (ref "SV38") (pin "4") (pinfunction "4_4") (pintype "passive"))
      (node (ref "SV38") (pin "5") (pinfunction "5_5") (pintype "passive"))
      (node (ref "SV38") (pin "6") (pinfunction "6_6") (pintype "passive"))
      (node (ref "SV38") (pin "7") (pinfunction "7_7") (pintype "passive"))
      (node (ref "SV38") (pin "8") (pinfunction "8_8") (pintype "passive"))
      (node (ref "SV38") (pin "9") (pinfunction "9_9") (pintype "passive"))
      (node (ref "SV4") (pin "1") (pinfunction "1_1") (pintype "passive"))
      (node (ref "SV4") (pin "10") (pinfunction "10_10") (pintype "passive"))
      (node (ref "SV4") (pin "11") (pinfunction "11_11") (pintype "passive"))
      (node (ref "SV4") (pin "12") (pinfunction "12_12") (pintype "passive"))
      (node (ref "SV4") (pin "2") (pinfunction "2_2") (pintype "passive"))
      (node (ref "SV4") (pin "3") (pinfunction "3_3") (pintype "passive"))
      (node (ref "SV4") (pin "4") (pinfunction "4_4") (pintype "passive"))
      (node (ref "SV4") (pin "5") (pinfunction "5_5") (pintype "passive"))
      (node (ref "SV4") (pin "6") (pinfunction "6_6") (pintype "passive"))
      (node (ref "SV4") (pin "7") (pinfunction "7_7") (pintype "passive"))
      (node (ref "SV4") (pin "8") (pinfunction "8_8") (pintype "passive"))
      (node (ref "SV4") (pin "9") (pinfunction "9_9") (pintype "passive"))
      (node (ref "SV40") (pin "1") (pinfunction "1_1") (pintype "passive"))
      (node (ref "SV40") (pin "10") (pinfunction "10_10") (pintype "passive"))
      (node (ref "SV40") (pin "11") (pinfunction "11_11") (pintype "passive"))
      (node (ref "SV40") (pin "12") (pinfunction "12_12") (pintype "passive"))
      (node (ref "SV40") (pin "2") (pinfunction "2_2") (pintype "passive"))
      (node (ref "SV40") (pin "3") (pinfunction "3_3") (pintype "passive"))
      (node (ref "SV40") (pin "4") (pinfunction "4_4") (pintype "passive"))
      (node (ref "SV40") (pin "5") (pinfunction "5_5") (pintype "passive"))
      (node (ref "SV40") (pin "6") (pinfunction "6_6") (pintype "passive"))
      (node (ref "SV40") (pin "7") (pinfunction "7_7") (pintype "passive"))
      (node (ref "SV40") (pin "8") (pinfunction "8_8") (pintype "passive"))
      (node (ref "SV40") (pin "9") (pinfunction "9_9") (pintype "passive"))
      (node (ref "SV42") (pin "1") (pinfunction "1_1") (pintype "passive"))
      (node (ref "SV42") (pin "10") (pinfunction "10_10") (pintype "passive"))
      (node (ref "SV42") (pin "11") (pinfunction "11_11") (pintype "passive"))
      (node (ref "SV42") (pin "12") (pinfunction "12_12") (pintype "passive"))
      (node (ref "SV42") (pin "2") (pinfunction "2_2") (pintype "passive"))
      (node (ref "SV42") (pin "3") (pinfunction "3_3") (pintype "passive"))
      (node (ref "SV42") (pin "4") (pinfunction "4_4") (pintype "passive"))
      (node (ref "SV42") (pin "5") (pinfunction "5_5") (pintype "passive"))
      (node (ref "SV42") (pin "6") (pinfunction "6_6") (pintype "passive"))
      (node (ref "SV42") (pin "7") (pinfunction "7_7") (pintype "passive"))
      (node (ref "SV42") (pin "8") (pinfunction "8_8") (pintype "passive"))
      (node (ref "SV42") (pin "9") (pinfunction "9_9") (pintype "passive"))
      (node (ref "SV44") (pin "1") (pinfunction "1_1") (pintype "passive"))
      (node (ref "SV44") (pin "10") (pinfunction "10_10") (pintype "passive"))
      (node (ref "SV44") (pin "11") (pinfunction "11_11") (pintype "passive"))
      (node (ref "SV44") (pin "12") (pinfunction "12_12") (pintype "passive"))
      (node (ref "SV44") (pin "2") (pinfunction "2_2") (pintype "passive"))
      (node (ref "SV44") (pin "3") (pinfunction "3_3") (pintype "passive"))
      (node (ref "SV44") (pin "4") (pinfunction "4_4") (pintype "passive"))
      (node (ref "SV44") (pin "5") (pinfunction "5_5") (pintype "passive"))
      (node (ref "SV44") (pin "6") (pinfunction "6_6") (pintype "passive"))
      (node (ref "SV44") (pin "7") (pinfunction "7_7") (pintype "passive"))
      (node (ref "SV44") (pin "8") (pinfunction "8_8") (pintype "passive"))
      (node (ref "SV44") (pin "9") (pinfunction "9_9") (pintype "passive"))
      (node (ref "SV46") (pin "1") (pinfunction "1_1") (pintype "passive"))
      (node (ref "SV46") (pin "10") (pinfunction "10_10") (pintype "passive"))
      (node (ref "SV46") (pin "11") (pinfunction "11_11") (pintype "passive"))
      (node (ref "SV46") (pin "12") (pinfunction "12_12") (pintype "passive"))
      (node (ref "SV46") (pin "2") (pinfunction "2_2") (pintype "passive"))
      (node (ref "SV46") (pin "3") (pinfunction "3_3") (pintype "passive"))
      (node (ref "SV46") (pin "4") (pinfunction "4_4") (pintype "passive"))
      (node (ref "SV46") (pin "5") (pinfunction "5_5") (pintype "passive"))
      (node (ref "SV46") (pin "6") (pinfunction "6_6") (pintype "passive"))
      (node (ref "SV46") (pin "7") (pinfunction "7_7") (pintype "passive"))
      (node (ref "SV46") (pin "8") (pinfunction "8_8") (pintype "passive"))
      (node (ref "SV46") (pin "9") (pinfunction "9_9") (pintype "passive"))
      (node (ref "SV48") (pin "1") (pinfunction "1_1") (pintype "passive"))
      (node (ref "SV48") (pin "10") (pinfunction "10_10") (pintype "passive"))
      (node (ref "SV48") (pin "11") (pinfunction "11_11") (pintype "passive"))
      (node (ref "SV48") (pin "12") (pinfunction "12_12") (pintype "passive"))
      (node (ref "SV48") (pin "2") (pinfunction "2_2") (pintype "passive"))
      (node (ref "SV48") (pin "3") (pinfunction "3_3") (pintype "passive"))
      (node (ref "SV48") (pin "4") (pinfunction "4_4") (pintype "passive"))
      (node (ref "SV48") (pin "5") (pinfunction "5_5") (pintype "passive"))
      (node (ref "SV48") (pin "6") (pinfunction "6_6") (pintype "passive"))
      (node (ref "SV48") (pin "7") (pinfunction "7_7") (pintype "passive"))
      (node (ref "SV48") (pin "8") (pinfunction "8_8") (pintype "passive"))
      (node (ref "SV48") (pin "9") (pinfunction "9_9") (pintype "passive"))
      (node (ref "SV50") (pin "1") (pinfunction "1_1") (pintype "passive"))
      (node (ref "SV50") (pin "10") (pinfunction "10_10") (pintype "passive"))
      (node (ref "SV50") (pin "11") (pinfunction "11_11") (pintype "passive"))
      (node (ref "SV50") (pin "12") (pinfunction "12_12") (pintype "passive"))
      (node (ref "SV50") (pin "2") (pinfunction "2_2") (pintype "passive"))
      (node (ref "SV50") (pin "3") (pinfunction "3_3") (pintype "passive"))
      (node (ref "SV50") (pin "4") (pinfunction "4_4") (pintype "passive"))
      (node (ref "SV50") (pin "5") (pinfunction "5_5") (pintype "passive"))
      (node (ref "SV50") (pin "6") (pinfunction "6_6") (pintype "passive"))
      (node (ref "SV50") (pin "7") (pinfunction "7_7") (pintype "passive"))
      (node (ref "SV50") (pin "8") (pinfunction "8_8") (pintype "passive"))
      (node (ref "SV50") (pin "9") (pinfunction "9_9") (pintype "passive"))
      (node (ref "SV52") (pin "1") (pinfunction "1_1") (pintype "passive"))
      (node (ref "SV52") (pin "10") (pinfunction "10_10") (pintype "passive"))
      (node (ref "SV52") (pin "11") (pinfunction "11_11") (pintype "passive"))
      (node (ref "SV52") (pin "12") (pinfunction "12_12") (pintype "passive"))
      (node (ref "SV52") (pin "2") (pinfunction "2_2") (pintype "passive"))
      (node (ref "SV52") (pin "3") (pinfunction "3_3") (pintype "passive"))
      (node (ref "SV52") (pin "4") (pinfunction "4_4") (pintype "passive"))
      (node (ref "SV52") (pin "5") (pinfunction "5_5") (pintype "passive"))
      (node (ref "SV52") (pin "6") (pinfunction "6_6") (pintype "passive"))
      (node (ref "SV52") (pin "7") (pinfunction "7_7") (pintype "passive"))
      (node (ref "SV52") (pin "8") (pinfunction "8_8") (pintype "passive"))
      (node (ref "SV52") (pin "9") (pinfunction "9_9") (pintype "passive"))
      (node (ref "SV54") (pin "1") (pinfunction "1_1") (pintype "passive"))
      (node (ref "SV54") (pin "10") (pinfunction "10_10") (pintype "passive"))
      (node (ref "SV54") (pin "11") (pinfunction "11_11") (pintype "passive"))
      (node (ref "SV54") (pin "12") (pinfunction "12_12") (pintype "passive"))
      (node (ref "SV54") (pin "2") (pinfunction "2_2") (pintype "passive"))
      (node (ref "SV54") (pin "3") (pinfunction "3_3") (pintype "passive"))
      (node (ref "SV54") (pin "4") (pinfunction "4_4") (pintype "passive"))
      (node (ref "SV54") (pin "5") (pinfunction "5_5") (pintype "passive"))
      (node (ref "SV54") (pin "6") (pinfunction "6_6") (pintype "passive"))
      (node (ref "SV54") (pin "7") (pinfunction "7_7") (pintype "passive"))
      (node (ref "SV54") (pin "8") (pinfunction "8_8") (pintype "passive"))
      (node (ref "SV54") (pin "9") (pinfunction "9_9") (pintype "passive"))
      (node (ref "SV56") (pin "1") (pinfunction "1_1") (pintype "passive"))
      (node (ref "SV56") (pin "10") (pinfunction "10_10") (pintype "passive"))
      (node (ref "SV56") (pin "11") (pinfunction "11_11") (pintype "passive"))
      (node (ref "SV56") (pin "12") (pinfunction "12_12") (pintype "passive"))
      (node (ref "SV56") (pin "2") (pinfunction "2_2") (pintype "passive"))
      (node (ref "SV56") (pin "3") (pinfunction "3_3") (pintype "passive"))
      (node (ref "SV56") (pin "4") (pinfunction "4_4") (pintype "passive"))
      (node (ref "SV56") (pin "5") (pinfunction "5_5") (pintype "passive"))
      (node (ref "SV56") (pin "6") (pinfunction "6_6") (pintype "passive"))
      (node (ref "SV56") (pin "7") (pinfunction "7_7") (pintype "passive"))
      (node (ref "SV56") (pin "8") (pinfunction "8_8") (pintype "passive"))
      (node (ref "SV56") (pin "9") (pinfunction "9_9") (pintype "passive"))
      (node (ref "SV58") (pin "1") (pinfunction "1_1") (pintype "passive"))
      (node (ref "SV58") (pin "10") (pinfunction "10_10") (pintype "passive"))
      (node (ref "SV58") (pin "11") (pinfunction "11_11") (pintype "passive"))
      (node (ref "SV58") (pin "12") (pinfunction "12_12") (pintype "passive"))
      (node (ref "SV58") (pin "2") (pinfunction "2_2") (pintype "passive"))
      (node (ref "SV58") (pin "3") (pinfunction "3_3") (pintype "passive"))
      (node (ref "SV58") (pin "4") (pinfunction "4_4") (pintype "passive"))
      (node (ref "SV58") (pin "5") (pinfunction "5_5") (pintype "passive"))
      (node (ref "SV58") (pin "6") (pinfunction "6_6") (pintype "passive"))
      (node (ref "SV58") (pin "7") (pinfunction "7_7") (pintype "passive"))
      (node (ref "SV58") (pin "8") (pinfunction "8_8") (pintype "passive"))
      (node (ref "SV58") (pin "9") (pinfunction "9_9") (pintype "passive"))
      (node (ref "SV6") (pin "1") (pinfunction "1_1") (pintype "passive"))
      (node (ref "SV6") (pin "10") (pinfunction "10_10") (pintype "passive"))
      (node (ref "SV6") (pin "11") (pinfunction "11_11") (pintype "passive"))
      (node (ref "SV6") (pin "12") (pinfunction "12_12") (pintype "passive"))
      (node (ref "SV6") (pin "2") (pinfunction "2_2") (pintype "passive"))
      (node (ref "SV6") (pin "3") (pinfunction "3_3") (pintype "passive"))
      (node (ref "SV6") (pin "4") (pinfunction "4_4") (pintype "passive"))
      (node (ref "SV6") (pin "5") (pinfunction "5_5") (pintype "passive"))
      (node (ref "SV6") (pin "6") (pinfunction "6_6") (pintype "passive"))
      (node (ref "SV6") (pin "7") (pinfunction "7_7") (pintype "passive"))
      (node (ref "SV6") (pin "8") (pinfunction "8_8") (pintype "passive"))
      (node (ref "SV6") (pin "9") (pinfunction "9_9") (pintype "passive"))
      (node (ref "SV60") (pin "1") (pinfunction "1_1") (pintype "passive"))
      (node (ref "SV60") (pin "10") (pinfunction "10_10") (pintype "passive"))
      (node (ref "SV60") (pin "11") (pinfunction "11_11") (pintype "passive"))
      (node (ref "SV60") (pin "12") (pinfunction "12_12") (pintype "passive"))
      (node (ref "SV60") (pin "2") (pinfunction "2_2") (pintype "passive"))
      (node (ref "SV60") (pin "3") (pinfunction "3_3") (pintype "passive"))
      (node (ref "SV60") (pin "4") (pinfunction "4_4") (pintype "passive"))
      (node (ref "SV60") (pin "5") (pinfunction "5_5") (pintype "passive"))
      (node (ref "SV60") (pin "6") (pinfunction "6_6") (pintype "passive"))
      (node (ref "SV60") (pin "7") (pinfunction "7_7") (pintype "passive"))
      (node (ref "SV60") (pin "8") (pinfunction "8_8") (pintype "passive"))
      (node (ref "SV60") (pin "9") (pinfunction "9_9") (pintype "passive"))
      (node (ref "SV62") (pin "1") (pinfunction "1_1") (pintype "passive"))
      (node (ref "SV62") (pin "10") (pinfunction "10_10") (pintype "passive"))
      (node (ref "SV62") (pin "11") (pinfunction "11_11") (pintype "passive"))
      (node (ref "SV62") (pin "12") (pinfunction "12_12") (pintype "passive"))
      (node (ref "SV62") (pin "2") (pinfunction "2_2") (pintype "passive"))
      (node (ref "SV62") (pin "3") (pinfunction "3_3") (pintype "passive"))
      (node (ref "SV62") (pin "4") (pinfunction "4_4") (pintype "passive"))
      (node (ref "SV62") (pin "5") (pinfunction "5_5") (pintype "passive"))
      (node (ref "SV62") (pin "6") (pinfunction "6_6") (pintype "passive"))
      (node (ref "SV62") (pin "7") (pinfunction "7_7") (pintype "passive"))
      (node (ref "SV62") (pin "8") (pinfunction "8_8") (pintype "passive"))
      (node (ref "SV62") (pin "9") (pinfunction "9_9") (pintype "passive"))
      (node (ref "SV64") (pin "1") (pinfunction "1_1") (pintype "passive"))
      (node (ref "SV64") (pin "10") (pinfunction "10_10") (pintype "passive"))
      (node (ref "SV64") (pin "11") (pinfunction "11_11") (pintype "passive"))
      (node (ref "SV64") (pin "12") (pinfunction "12_12") (pintype "passive"))
      (node (ref "SV64") (pin "2") (pinfunction "2_2") (pintype "passive"))
      (node (ref "SV64") (pin "3") (pinfunction "3_3") (pintype "passive"))
      (node (ref "SV64") (pin "4") (pinfunction "4_4") (pintype "passive"))
      (node (ref "SV64") (pin "5") (pinfunction "5_5") (pintype "passive"))
      (node (ref "SV64") (pin "6") (pinfunction "6_6") (pintype "passive"))
      (node (ref "SV64") (pin "7") (pinfunction "7_7") (pintype "passive"))
      (node (ref "SV64") (pin "8") (pinfunction "8_8") (pintype "passive"))
      (node (ref "SV64") (pin "9") (pinfunction "9_9") (pintype "passive"))
      (node (ref "SV66") (pin "1") (pinfunction "1_1") (pintype "passive"))
      (node (ref "SV66") (pin "10") (pinfunction "10_10") (pintype "passive"))
      (node (ref "SV66") (pin "11") (pinfunction "11_11") (pintype "passive"))
      (node (ref "SV66") (pin "12") (pinfunction "12_12") (pintype "passive"))
      (node (ref "SV66") (pin "2") (pinfunction "2_2") (pintype "passive"))
      (node (ref "SV66") (pin "3") (pinfunction "3_3") (pintype "passive"))
      (node (ref "SV66") (pin "4") (pinfunction "4_4") (pintype "passive"))
      (node (ref "SV66") (pin "5") (pinfunction "5_5") (pintype "passive"))
      (node (ref "SV66") (pin "6") (pinfunction "6_6") (pintype "passive"))
      (node (ref "SV66") (pin "7") (pinfunction "7_7") (pintype "passive"))
      (node (ref "SV66") (pin "8") (pinfunction "8_8") (pintype "passive"))
      (node (ref "SV66") (pin "9") (pinfunction "9_9") (pintype "passive"))
      (node (ref "SV68") (pin "1") (pinfunction "1_1") (pintype "passive"))
      (node (ref "SV68") (pin "10") (pinfunction "10_10") (pintype "passive"))
      (node (ref "SV68") (pin "11") (pinfunction "11_11") (pintype "passive"))
      (node (ref "SV68") (pin "12") (pinfunction "12_12") (pintype "passive"))
      (node (ref "SV68") (pin "2") (pinfunction "2_2") (pintype "passive"))
      (node (ref "SV68") (pin "3") (pinfunction "3_3") (pintype "passive"))
      (node (ref "SV68") (pin "4") (pinfunction "4_4") (pintype "passive"))
      (node (ref "SV68") (pin "5") (pinfunction "5_5") (pintype "passive"))
      (node (ref "SV68") (pin "6") (pinfunction "6_6") (pintype "passive"))
      (node (ref "SV68") (pin "7") (pinfunction "7_7") (pintype "passive"))
      (node (ref "SV68") (pin "8") (pinfunction "8_8") (pintype "passive"))
      (node (ref "SV68") (pin "9") (pinfunction "9_9") (pintype "passive"))
      (node (ref "SV70") (pin "1") (pinfunction "1_1") (pintype "passive"))
      (node (ref "SV70") (pin "10") (pinfunction "10_10") (pintype "passive"))
      (node (ref "SV70") (pin "11") (pinfunction "11_11") (pintype "passive"))
      (node (ref "SV70") (pin "12") (pinfunction "12_12") (pintype "passive"))
      (node (ref "SV70") (pin "2") (pinfunction "2_2") (pintype "passive"))
      (node (ref "SV70") (pin "3") (pinfunction "3_3") (pintype "passive"))
      (node (ref "SV70") (pin "4") (pinfunction "4_4") (pintype "passive"))
      (node (ref "SV70") (pin "5") (pinfunction "5_5") (pintype "passive"))
      (node (ref "SV70") (pin "6") (pinfunction "6_6") (pintype "passive"))
      (node (ref "SV70") (pin "7") (pinfunction "7_7") (pintype "passive"))
      (node (ref "SV70") (pin "8") (pinfunction "8_8") (pintype "passive"))
      (node (ref "SV70") (pin "9") (pinfunction "9_9") (pintype "passive"))
      (node (ref "SV72") (pin "1") (pinfunction "1_1") (pintype "passive"))
      (node (ref "SV72") (pin "10") (pinfunction "10_10") (pintype "passive"))
      (node (ref "SV72") (pin "11") (pinfunction "11_11") (pintype "passive"))
      (node (ref "SV72") (pin "12") (pinfunction "12_12") (pintype "passive"))
      (node (ref "SV72") (pin "2") (pinfunction "2_2") (pintype "passive"))
      (node (ref "SV72") (pin "3") (pinfunction "3_3") (pintype "passive"))
      (node (ref "SV72") (pin "4") (pinfunction "4_4") (pintype "passive"))
      (node (ref "SV72") (pin "5") (pinfunction "5_5") (pintype "passive"))
      (node (ref "SV72") (pin "6") (pinfunction "6_6") (pintype "passive"))
      (node (ref "SV72") (pin "7") (pinfunction "7_7") (pintype "passive"))
      (node (ref "SV72") (pin "8") (pinfunction "8_8") (pintype "passive"))
      (node (ref "SV72") (pin "9") (pinfunction "9_9") (pintype "passive"))
      (node (ref "SV74") (pin "1") (pinfunction "1_1") (pintype "passive"))
      (node (ref "SV74") (pin "10") (pinfunction "10_10") (pintype "passive"))
      (node (ref "SV74") (pin "11") (pinfunction "11_11") (pintype "passive"))
      (node (ref "SV74") (pin "12") (pinfunction "12_12") (pintype "passive"))
      (node (ref "SV74") (pin "2") (pinfunction "2_2") (pintype "passive"))
      (node (ref "SV74") (pin "3") (pinfunction "3_3") (pintype "passive"))
      (node (ref "SV74") (pin "4") (pinfunction "4_4") (pintype "passive"))
      (node (ref "SV74") (pin "5") (pinfunction "5_5") (pintype "passive"))
      (node (ref "SV74") (pin "6") (pinfunction "6_6") (pintype "passive"))
      (node (ref "SV74") (pin "7") (pinfunction "7_7") (pintype "passive"))
      (node (ref "SV74") (pin "8") (pinfunction "8_8") (pintype "passive"))
      (node (ref "SV74") (pin "9") (pinfunction "9_9") (pintype "passive"))
      (node (ref "SV76") (pin "1") (pinfunction "1_1") (pintype "passive"))
      (node (ref "SV76") (pin "10") (pinfunction "10_10") (pintype "passive"))
      (node (ref "SV76") (pin "11") (pinfunction "11_11") (pintype "passive"))
      (node (ref "SV76") (pin "12") (pinfunction "12_12") (pintype "passive"))
      (node (ref "SV76") (pin "2") (pinfunction "2_2") (pintype "passive"))
      (node (ref "SV76") (pin "3") (pinfunction "3_3") (pintype "passive"))
      (node (ref "SV76") (pin "4") (pinfunction "4_4") (pintype "passive"))
      (node (ref "SV76") (pin "5") (pinfunction "5_5") (pintype "passive"))
      (node (ref "SV76") (pin "6") (pinfunction "6_6") (pintype "passive"))
      (node (ref "SV76") (pin "7") (pinfunction "7_7") (pintype "passive"))
      (node (ref "SV76") (pin "8") (pinfunction "8_8") (pintype "passive"))
      (node (ref "SV76") (pin "9") (pinfunction "9_9") (pintype "passive"))
      (node (ref "SV78") (pin "1") (pinfunction "1_1") (pintype "passive"))
      (node (ref "SV78") (pin "10") (pinfunction "10_10") (pintype "passive"))
      (node (ref "SV78") (pin "11") (pinfunction "11_11") (pintype "passive"))
      (node (ref "SV78") (pin "12") (pinfunction "12_12") (pintype "passive"))
      (node (ref "SV78") (pin "2") (pinfunction "2_2") (pintype "passive"))
      (node (ref "SV78") (pin "3") (pinfunction "3_3") (pintype "passive"))
      (node (ref "SV78") (pin "4") (pinfunction "4_4") (pintype "passive"))
      (node (ref "SV78") (pin "5") (pinfunction "5_5") (pintype "passive"))
      (node (ref "SV78") (pin "6") (pinfunction "6_6") (pintype "passive"))
      (node (ref "SV78") (pin "7") (pinfunction "7_7") (pintype "passive"))
      (node (ref "SV78") (pin "8") (pinfunction "8_8") (pintype "passive"))
      (node (ref "SV78") (pin "9") (pinfunction "9_9") (pintype "passive"))
      (node (ref "SV8") (pin "1") (pinfunction "1_1") (pintype "passive"))
      (node (ref "SV8") (pin "10") (pinfunction "10_10") (pintype "passive"))
      (node (ref "SV8") (pin "11") (pinfunction "11_11") (pintype "passive"))
      (node (ref "SV8") (pin "12") (pinfunction "12_12") (pintype "passive"))
      (node (ref "SV8") (pin "2") (pinfunction "2_2") (pintype "passive"))
      (node (ref "SV8") (pin "3") (pinfunction "3_3") (pintype "passive"))
      (node (ref "SV8") (pin "4") (pinfunction "4_4") (pintype "passive"))
      (node (ref "SV8") (pin "5") (pinfunction "5_5") (pintype "passive"))
      (node (ref "SV8") (pin "6") (pinfunction "6_6") (pintype "passive"))
      (node (ref "SV8") (pin "7") (pinfunction "7_7") (pintype "passive"))
      (node (ref "SV8") (pin "8") (pinfunction "8_8") (pintype "passive"))
      (node (ref "SV8") (pin "9") (pinfunction "9_9") (pintype "passive"))
      (node (ref "SV80") (pin "1") (pinfunction "1_1") (pintype "passive"))
      (node (ref "SV80") (pin "10") (pinfunction "10_10") (pintype "passive"))
      (node (ref "SV80") (pin "11") (pinfunction "11_11") (pintype "passive"))
      (node (ref "SV80") (pin "12") (pinfunction "12_12") (pintype "passive"))
      (node (ref "SV80") (pin "2") (pinfunction "2_2") (pintype "passive"))
      (node (ref "SV80") (pin "3") (pinfunction "3_3") (pintype "passive"))
      (node (ref "SV80") (pin "4") (pinfunction "4_4") (pintype "passive"))
      (node (ref "SV80") (pin "5") (pinfunction "5_5") (pintype "passive"))
      (node (ref "SV80") (pin "6") (pinfunction "6_6") (pintype "passive"))
      (node (ref "SV80") (pin "7") (pinfunction "7_7") (pintype "passive"))
      (node (ref "SV80") (pin "8") (pinfunction "8_8") (pintype "passive"))
      (node (ref "SV80") (pin "9") (pinfunction "9_9") (pintype "passive"))
      (node (ref "SV82") (pin "1") (pinfunction "1_1") (pintype "passive"))
      (node (ref "SV82") (pin "10") (pinfunction "10_10") (pintype "passive"))
      (node (ref "SV82") (pin "11") (pinfunction "11_11") (pintype "passive"))
      (node (ref "SV82") (pin "12") (pinfunction "12_12") (pintype "passive"))
      (node (ref "SV82") (pin "2") (pinfunction "2_2") (pintype "passive"))
      (node (ref "SV82") (pin "3") (pinfunction "3_3") (pintype "passive"))
      (node (ref "SV82") (pin "4") (pinfunction "4_4") (pintype "passive"))
      (node (ref "SV82") (pin "5") (pinfunction "5_5") (pintype "passive"))
      (node (ref "SV82") (pin "6") (pinfunction "6_6") (pintype "passive"))
      (node (ref "SV82") (pin "7") (pinfunction "7_7") (pintype "passive"))
      (node (ref "SV82") (pin "8") (pinfunction "8_8") (pintype "passive"))
      (node (ref "SV82") (pin "9") (pinfunction "9_9") (pintype "passive"))
      (node (ref "SV84") (pin "1") (pinfunction "1_1") (pintype "passive"))
      (node (ref "SV84") (pin "10") (pinfunction "10_10") (pintype "passive"))
      (node (ref "SV84") (pin "11") (pinfunction "11_11") (pintype "passive"))
      (node (ref "SV84") (pin "12") (pinfunction "12_12") (pintype "passive"))
      (node (ref "SV84") (pin "2") (pinfunction "2_2") (pintype "passive"))
      (node (ref "SV84") (pin "3") (pinfunction "3_3") (pintype "passive"))
      (node (ref "SV84") (pin "4") (pinfunction "4_4") (pintype "passive"))
      (node (ref "SV84") (pin "5") (pinfunction "5_5") (pintype "passive"))
      (node (ref "SV84") (pin "6") (pinfunction "6_6") (pintype "passive"))
      (node (ref "SV84") (pin "7") (pinfunction "7_7") (pintype "passive"))
      (node (ref "SV84") (pin "8") (pinfunction "8_8") (pintype "passive"))
      (node (ref "SV84") (pin "9") (pinfunction "9_9") (pintype "passive"))
      (node (ref "SV86") (pin "1") (pinfunction "1_1") (pintype "passive"))
      (node (ref "SV86") (pin "10") (pinfunction "10_10") (pintype "passive"))
      (node (ref "SV86") (pin "11") (pinfunction "11_11") (pintype "passive"))
      (node (ref "SV86") (pin "12") (pinfunction "12_12") (pintype "passive"))
      (node (ref "SV86") (pin "2") (pinfunction "2_2") (pintype "passive"))
      (node (ref "SV86") (pin "3") (pinfunction "3_3") (pintype "passive"))
      (node (ref "SV86") (pin "4") (pinfunction "4_4") (pintype "passive"))
      (node (ref "SV86") (pin "5") (pinfunction "5_5") (pintype "passive"))
      (node (ref "SV86") (pin "6") (pinfunction "6_6") (pintype "passive"))
      (node (ref "SV86") (pin "7") (pinfunction "7_7") (pintype "passive"))
      (node (ref "SV86") (pin "8") (pinfunction "8_8") (pintype "passive"))
      (node (ref "SV86") (pin "9") (pinfunction "9_9") (pintype "passive"))
      (node (ref "SV88") (pin "1") (pinfunction "1_1") (pintype "passive"))
      (node (ref "SV88") (pin "10") (pinfunction "10_10") (pintype "passive"))
      (node (ref "SV88") (pin "11") (pinfunction "11_11") (pintype "passive"))
      (node (ref "SV88") (pin "12") (pinfunction "12_12") (pintype "passive"))
      (node (ref "SV88") (pin "2") (pinfunction "2_2") (pintype "passive"))
      (node (ref "SV88") (pin "3") (pinfunction "3_3") (pintype "passive"))
      (node (ref "SV88") (pin "4") (pinfunction "4_4") (pintype "passive"))
      (node (ref "SV88") (pin "5") (pinfunction "5_5") (pintype "passive"))
      (node (ref "SV88") (pin "6") (pinfunction "6_6") (pintype "passive"))
      (node (ref "SV88") (pin "7") (pinfunction "7_7") (pintype "passive"))
      (node (ref "SV88") (pin "8") (pinfunction "8_8") (pintype "passive"))
      (node (ref "SV88") (pin "9") (pinfunction "9_9") (pintype "passive"))
      (node (ref "SV90") (pin "1") (pinfunction "1_1") (pintype "passive"))
      (node (ref "SV90") (pin "10") (pinfunction "10_10") (pintype "passive"))
      (node (ref "SV90") (pin "11") (pinfunction "11_11") (pintype "passive"))
      (node (ref "SV90") (pin "12") (pinfunction "12_12") (pintype "passive"))
      (node (ref "SV90") (pin "2") (pinfunction "2_2") (pintype "passive"))
      (node (ref "SV90") (pin "3") (pinfunction "3_3") (pintype "passive"))
      (node (ref "SV90") (pin "4") (pinfunction "4_4") (pintype "passive"))
      (node (ref "SV90") (pin "5") (pinfunction "5_5") (pintype "passive"))
      (node (ref "SV90") (pin "6") (pinfunction "6_6") (pintype "passive"))
      (node (ref "SV90") (pin "7") (pinfunction "7_7") (pintype "passive"))
      (node (ref "SV90") (pin "8") (pinfunction "8_8") (pintype "passive"))
      (node (ref "SV90") (pin "9") (pinfunction "9_9") (pintype "passive"))
      (node (ref "SV93") (pin "3") (pinfunction "3_3") (pintype "passive"))
      (node (ref "SV94") (pin "3") (pinfunction "3_3") (pintype "passive"))
      (node (ref "SV95") (pin "3") (pinfunction "3_3") (pintype "passive"))
      (node (ref "SV96") (pin "3") (pinfunction "3_3") (pintype "passive"))
    )
    (net (code "2") (name "Net-(IC1-Pad1)") (class "Default")
      (node (ref "IC1") (pin "1") (pinfunction "1_1") (pintype "passive"))
      (node (ref "IC2") (pin "1") (pinfunction "1_1") (pintype "passive"))
      (node (ref "IC3") (pin "1") (pinfunction "1_1") (pintype "passive"))
      (node (ref "IC4") (pin "1") (pinfunction "1_1") (pintype "passive"))
    )
    (net (code "3") (name "Net-(IC1-Pad2)") (class "Default")
      (node (ref "IC1") (pin "2") (pinfunction "2_2") (pintype "passive"))
      (node (ref "IC2") (pin "2") (pinfunction "2_2") (pintype "passive"))
      (node (ref "IC3") (pin "2") (pinfunction "2_2") (pintype "passive"))
      (node (ref "IC4") (pin "2") (pinfunction "2_2") (pintype "passive"))
    )
    (net (code "4") (name "Net-(IC1-Pad3)") (class "Default")
      (node (ref "IC1") (pin "3") (pinfunction "3_3") (pintype "passive"))
      (node (ref "IC2") (pin "3") (pinfunction "3_3") (pintype "passive"))
      (node (ref "IC3") (pin "3") (pinfunction "3_3") (pintype "passive"))
      (node (ref "IC4") (pin "3") (pinfunction "3_3") (pintype "passive"))
    )
    (net (code "5") (name "Net-(IC1-Pad4)") (class "Default")
      (node (ref "IC1") (pin "4") (pinfunction "4_4") (pintype "passive"))
      (node (ref "IC2") (pin "4") (pinfunction "4_4") (pintype "passive"))
      (node (ref "IC3") (pin "4") (pinfunction "4_4") (pintype "passive"))
      (node (ref "IC4") (pin "4") (pinfunction "4_4") (pintype "passive"))
    )
    (net (code "6") (name "Net-(IC1-Pad5)") (class "Default")
      (node (ref "IC1") (pin "5") (pinfunction "5_5") (pintype "passive"))
      (node (ref "IC2") (pin "5") (pinfunction "5_5") (pintype "passive"))
      (node (ref "IC3") (pin "5") (pinfunction "5_5") (pintype "passive"))
      (node (ref "IC4") (pin "5") (pinfunction "5_5") (pintype "passive"))
    )
    (net (code "7") (name "Net-(IC1-Pad6)") (class "Default")
      (node (ref "IC1") (pin "6") (pinfunction "6_6") (pintype "passive"))
      (node (ref "IC2") (pin "6") (pinfunction "6_6") (pintype "passive"))
      (node (ref "IC3") (pin "6") (pinfunction "6_6") (pintype "passive"))
      (node (ref "IC4") (pin "6") (pinfunction "6_6") (pintype "passive"))
    )
    (net (code "8") (name "Net-(IC1-Pad7)") (class "Default")
      (node (ref "IC1") (pin "7") (pinfunction "7_7") (pintype "passive"))
      (node (ref "IC2") (pin "7") (pinfunction "7_7") (pintype "passive"))
      (node (ref "IC3") (pin "7") (pinfunction "7_7") (pintype "passive"))
      (node (ref "IC4") (pin "7") (pinfunction "7_7") (pintype "passive"))
    )
    (net (code "9") (name "Net-(IC1-Pad8)") (class "Default")
      (node (ref "IC1") (pin "8") (pinfunction "8_8") (pintype "passive"))
      (node (ref "IC2") (pin "8") (pinfunction "8_8") (pintype "passive"))
      (node (ref "IC3") (pin "8") (pinfunction "8_8") (pintype "passive"))
      (node (ref "IC4") (pin "8") (pinfunction "8_8") (pintype "passive"))
    )
    (net (code "10") (name "Net-(IC1-Pad9)") (class "Default")
      (node (ref "IC1") (pin "9") (pinfunction "9_9") (pintype "passive"))
      (node (ref "IC2") (pin "9") (pinfunction "9_9") (pintype "passive"))
      (node (ref "IC3") (pin "9") (pinfunction "9_9") (pintype "passive"))
      (node (ref "IC4") (pin "9") (pinfunction "9_9") (pintype "passive"))
    )
    (net (code "11") (name "Net-(IC1-Pad10)") (class "Default")
      (node (ref "IC1") (pin "10") (pinfunction "10_10") (pintype "passive"))
      (node (ref "IC2") (pin "10") (pinfunction "10_10") (pintype "passive"))
      (node (ref "IC3") (pin "10") (pinfunction "10_10") (pintype "passive"))
      (node (ref "IC4") (pin "10") (pinfunction "10_10") (pintype "passive"))
    )
    (net (code "12") (name "Net-(IC1-Pad11)") (class "Default")
      (node (ref "IC1") (pin "11") (pinfunction "11_11") (pintype "passive"))
      (node (ref "IC2") (pin "11") (pinfunction "11_11") (pintype "passive"))
      (node (ref "IC3") (pin "11") (pinfunction "11_11") (pintype "passive"))
      (node (ref "IC4") (pin "11") (pinfunction "11_11") (pintype "passive"))
    )
    (net (code "13") (name "Net-(IC1-Pad12)") (class "Default")
      (node (ref "IC1") (pin "12") (pinfunction "12_12") (pintype "passive"))
      (node (ref "IC2") (pin "12") (pinfunction "12_12") (pintype "passive"))
      (node (ref "IC3") (pin "12") (pinfunction "12_12") (pintype "passive"))
      (node (ref "IC4") (pin "12") (pinfunction "12_12") (pintype "passive"))
    )
    (net (code "14") (name "Net-(IC1-Pad13)") (class "Default")
      (node (ref "IC1") (pin "13") (pinfunction "13_13") (pintype "passive"))
      (node (ref "IC2") (pin "13") (pinfunction "13_13") (pintype "passive"))
      (node (ref "IC3") (pin "13") (pinfunction "13_13") (pintype "passive"))
      (node (ref "IC4") (pin "13") (pinfunction "13_13") (pintype "passive"))
    )
    (net (code "15") (name "Net-(IC1-Pad14)") (class "Default")
      (node (ref "IC1") (pin "14") (pinfunction "14_14") (pintype "passive"))
      (node (ref "IC2") (pin "14") (pinfunction "14_14") (pintype "passive"))
      (node (ref "IC3") (pin "14") (pinfunction "14_14") (pintype "passive"))
      (node (ref "IC4") (pin "14") (pinfunction "14_14") (pintype "passive"))
    )
    (net (code "16") (name "Net-(IC1-Pad15)") (class "Default")
      (node (ref "IC1") (pin "15") (pinfunction "15_15") (pintype "passive"))
      (node (ref "IC2") (pin "15") (pinfunction "15_15") (pintype "passive"))
      (node (ref "IC3") (pin "15") (pinfunction "15_15") (pintype "passive"))
      (node (ref "IC4") (pin "15") (pinfunction "15_15") (pintype "passive"))
    )
    (net (code "17") (name "Net-(IC1-Pad16)") (class "Default")
      (node (ref "IC1") (pin "16") (pinfunction "16_16") (pintype "passive"))
      (node (ref "IC2") (pin "16") (pinfunction "16_16") (pintype "passive"))
      (node (ref "IC3") (pin "16") (pinfunction "16_16") (pintype "passive"))
      (node (ref "IC4") (pin "16") (pinfunction "16_16") (pintype "passive"))
    )
    (net (code "18") (name "Net-(IC1-Pad17)") (class "Default")
      (node (ref "IC1") (pin "17") (pinfunction "17_17") (pintype "passive"))
      (node (ref "IC2") (pin "17") (pinfunction "17_17") (pintype "passive"))
      (node (ref "IC3") (pin "17") (pinfunction "17_17") (pintype "passive"))
      (node (ref "IC4") (pin "17") (pinfunction "17_17") (pintype "passive"))
    )
    (net (code "19") (name "Net-(IC1-Pad18)") (class "Default")
      (node (ref "IC1") (pin "18") (pinfunction "18_18") (pintype "passive"))
      (node (ref "IC2") (pin "18") (pinfunction "18_18") (pintype "passive"))
      (node (ref "IC3") (pin "18") (pinfunction "18_18") (pintype "passive"))
      (node (ref "IC4") (pin "18") (pinfunction "18_18") (pintype "passive"))
    )
    (net (code "20") (name "Net-(IC1-Pad19)") (class "Default")
      (node (ref "IC1") (pin "19") (pinfunction "19_19") (pintype "passive"))
      (node (ref "IC2") (pin "19") (pinfunction "19_19") (pintype "passive"))
      (node (ref "IC3") (pin "19") (pinfunction "19_19") (pintype "passive"))
      (node (ref "IC4") (pin "19") (pinfunction "19_19") (pintype "passive"))
    )
    (net (code "21") (name "Net-(IC1-Pad20)") (class "Default")
      (node (ref "IC1") (pin "20") (pinfunction "20_20") (pintype "passive"))
      (node (ref "IC2") (pin "20") (pinfunction "20_20") (pintype "passive"))
      (node (ref "IC3") (pin "20") (pinfunction "20_20") (pintype "passive"))
      (node (ref "IC4") (pin "20") (pinfunction "20_20") (pintype "passive"))
    )
    (net (code "22") (name "Net-(IC1-Pad21)") (class "Default")
      (node (ref "IC1") (pin "21") (pinfunction "21_21") (pintype "passive"))
      (node (ref "IC2") (pin "21") (pinfunction "21_21") (pintype "passive"))
      (node (ref "IC3") (pin "21") (pinfunction "21_21") (pintype "passive"))
      (node (ref "IC4") (pin "21") (pinfunction "21_21") (pintype "passive"))
    )
    (net (code "23") (name "Net-(IC1-Pad22)") (class "Default")
      (node (ref "IC1") (pin "22") (pinfunction "22_22") (pintype "passive"))
      (node (ref "IC2") (pin "22") (pinfunction "22_22") (pintype "passive"))
      (node (ref "IC3") (pin "22") (pinfunction "22_22") (pintype "passive"))
      (node (ref "IC4") (pin "22") (pinfunction "22_22") (pintype "passive"))
    )
    (net (code "24") (name "Net-(IC1-Pad23)") (class "Default")
      (node (ref "IC1") (pin "23") (pinfunction "23_23") (pintype "passive"))
      (node (ref "IC2") (pin "23") (pinfunction "23_23") (pintype "passive"))
      (node (ref "IC3") (pin "23") (pinfunction "23_23") (pintype "passive"))
      (node (ref "IC4") (pin "23") (pinfunction "23_23") (pintype "passive"))
    )
    (net (code "25") (name "Net-(IC1-Pad24)") (class "Default")
      (node (ref "IC1") (pin "24") (pinfunction "24_24") (pintype "passive"))
      (node (ref "IC2") (pin "24") (pinfunction "24_24") (pintype "passive"))
      (node (ref "IC3") (pin "24") (pinfunction "24_24") (pintype "passive"))
      (node (ref "IC4") (pin "24") (pinfunction "24_24") (pintype "passive"))
    )
    (net (code "26") (name "Net-(IC5-Pad1)") (class "Default")
      (node (ref "IC5") (pin "1") (pinfunction "1_1") (pintype "passive"))
      (node (ref "IC6") (pin "1") (pinfunction "1_1") (pintype "passive"))
      (node (ref "IC7") (pin "1") (pinfunction "1_1") (pintype "passive"))
      (node (ref "IC8") (pin "1") (pinfunction "1_1") (pintype "passive"))
    )
    (net (code "27") (name "Net-(IC5-Pad2)") (class "Default")
      (node (ref "IC5") (pin "2") (pinfunction "2_2") (pintype "passive"))
      (node (ref "IC6") (pin "2") (pinfunction "2_2") (pintype "passive"))
      (node (ref "IC7") (pin "2") (pinfunction "2_2") (pintype "passive"))
      (node (ref "IC8") (pin "2") (pinfunction "2_2") (pintype "passive"))
    )
    (net (code "28") (name "Net-(IC5-Pad3)") (class "Default")
      (node (ref "IC5") (pin "3") (pinfunction "3_3") (pintype "passive"))
      (node (ref "IC6") (pin "3") (pinfunction "3_3") (pintype "passive"))
      (node (ref "IC7") (pin "3") (pinfunction "3_3") (pintype "passive"))
      (node (ref "IC8") (pin "3") (pinfunction "3_3") (pintype "passive"))
    )
    (net (code "29") (name "Net-(IC5-Pad4)") (class "Default")
      (node (ref "IC5") (pin "4") (pinfunction "4_4") (pintype "passive"))
      (node (ref "IC6") (pin "4") (pinfunction "4_4") (pintype "passive"))
      (node (ref "IC7") (pin "4") (pinfunction "4_4") (pintype "passive"))
      (node (ref "IC8") (pin "4") (pinfunction "4_4") (pintype "passive"))
    )
    (net (code "30") (name "Net-(IC5-Pad5)") (class "Default")
      (node (ref "IC5") (pin "5") (pinfunction "5_5") (pintype "passive"))
      (node (ref "IC6") (pin "5") (pinfunction "5_5") (pintype "passive"))
      (node (ref "IC7") (pin "5") (pinfunction "5_5") (pintype "passive"))
      (node (ref "IC8") (pin "5") (pinfunction "5_5") (pintype "passive"))
    )
    (net (code "31") (name "Net-(IC5-Pad6)") (class "Default")
      (node (ref "IC5") (pin "6") (pinfunction "6_6") (pintype "passive"))
      (node (ref "IC6") (pin "6") (pinfunction "6_6") (pintype "passive"))
      (node (ref "IC7") (pin "6") (pinfunction "6_6") (pintype "passive"))
      (node (ref "IC8") (pin "6") (pinfunction "6_6") (pintype "passive"))
    )
    (net (code "32") (name "Net-(IC5-Pad7)") (class "Default")
      (node (ref "IC5") (pin "7") (pinfunction "7_7") (pintype "passive"))
      (node (ref "IC6") (pin "7") (pinfunction "7_7") (pintype "passive"))
      (node (ref "IC7") (pin "7") (pinfunction "7_7") (pintype "passive"))
      (node (ref "IC8") (pin "7") (pinfunction "7_7") (pintype "passive"))
    )
    (net (code "33") (name "Net-(IC5-Pad8)") (class "Default")
      (node (ref "IC5") (pin "8") (pinfunction "8_8") (pintype "passive"))
      (node (ref "IC6") (pin "8") (pinfunction "8_8") (pintype "passive"))
      (node (ref "IC7") (pin "8") (pinfunction "8_8") (pintype "passive"))
      (node (ref "IC8") (pin "8") (pinfunction "8_8") (pintype "passive"))
    )
    (net (code "34") (name "Net-(IC5-Pad9)") (class "Default")
      (node (ref "IC5") (pin "9") (pinfunction "9_9") (pintype "passive"))
      (node (ref "IC6") (pin "9") (pinfunction "9_9") (pintype "passive"))
      (node (ref "IC7") (pin "9") (pinfunction "9_9") (pintype "passive"))
      (node (ref "IC8") (pin "9") (pinfunction "9_9") (pintype "passive"))
    )
    (net (code "35") (name "Net-(IC5-Pad10)") (class "Default")
      (node (ref "IC5") (pin "10") (pinfunction "10_10") (pintype "passive"))
      (node (ref "IC6") (pin "10") (pinfunction "10_10") (pintype "passive"))
      (node (ref "IC7") (pin "10") (pinfunction "10_10") (pintype "passive"))
      (node (ref "IC8") (pin "10") (pinfunction "10_10") (pintype "passive"))
    )
    (net (code "36") (name "Net-(IC5-Pad11)") (class "Default")
      (node (ref "IC5") (pin "11") (pinfunction "11_11") (pintype "passive"))
      (node (ref "IC6") (pin "11") (pinfunction "11_11") (pintype "passive"))
      (node (ref "IC7") (pin "11") (pinfunction "11_11") (pintype "passive"))
      (node (ref "IC8") (pin "11") (pinfunction "11_11") (pintype "passive"))
    )
    (net (code "37") (name "Net-(IC5-Pad12)") (class "Default")
      (node (ref "IC5") (pin "12") (pinfunction "12_12") (pintype "passive"))
      (node (ref "IC6") (pin "12") (pinfunction "12_12") (pintype "passive"))
      (node (ref "IC7") (pin "12") (pinfunction "12_12") (pintype "passive"))
      (node (ref "IC8") (pin "12") (pinfunction "12_12") (pintype "passive"))
    )
    (net (code "38") (name "Net-(IC5-Pad13)") (class "Default")
      (node (ref "IC5") (pin "13") (pinfunction "13_13") (pintype "passive"))
      (node (ref "IC6") (pin "13") (pinfunction "13_13") (pintype "passive"))
      (node (ref "IC7") (pin "13") (pinfunction "13_13") (pintype "passive"))
      (node (ref "IC8") (pin "13") (pinfunction "13_13") (pintype "passive"))
    )
    (net (code "39") (name "Net-(IC5-Pad14)") (class "Default")
      (node (ref "IC5") (pin "14") (pinfunction "14_14") (pintype "passive"))
      (node (ref "IC6") (pin "14") (pinfunction "14_14") (pintype "passive"))
      (node (ref "IC7") (pin "14") (pinfunction "14_14") (pintype "passive"))
      (node (ref "IC8") (pin "14") (pinfunction "14_14") (pintype "passive"))
    )
    (net (code "40") (name "Net-(IC5-Pad15)") (class "Default")
      (node (ref "IC5") (pin "15") (pinfunction "15_15") (pintype "passive"))
      (node (ref "IC6") (pin "15") (pinfunction "15_15") (pintype "passive"))
      (node (ref "IC7") (pin "15") (pinfunction "15_15") (pintype "passive"))
      (node (ref "IC8") (pin "15") (pinfunction "15_15") (pintype "passive"))
    )
    (net (code "41") (name "Net-(IC5-Pad16)") (class "Default")
      (node (ref "IC5") (pin "16") (pinfunction "16_16") (pintype "passive"))
      (node (ref "IC6") (pin "16") (pinfunction "16_16") (pintype "passive"))
      (node (ref "IC7") (pin "16") (pinfunction "16_16") (pintype "passive"))
      (node (ref "IC8") (pin "16") (pinfunction "16_16") (pintype "passive"))
    )
    (net (code "42") (name "Net-(IC5-Pad17)") (class "Default")
      (node (ref "IC5") (pin "17") (pinfunction "17_17") (pintype "passive"))
      (node (ref "IC6") (pin "17") (pinfunction "17_17") (pintype "passive"))
      (node (ref "IC7") (pin "17") (pinfunction "17_17") (pintype "passive"))
      (node (ref "IC8") (pin "17") (pinfunction "17_17") (pintype "passive"))
    )
    (net (code "43") (name "Net-(IC5-Pad18)") (class "Default")
      (node (ref "IC5") (pin "18") (pinfunction "18_18") (pintype "passive"))
      (node (ref "IC6") (pin "18") (pinfunction "18_18") (pintype "passive"))
      (node (ref "IC7") (pin "18") (pinfunction "18_18") (pintype "passive"))
      (node (ref "IC8") (pin "18") (pinfunction "18_18") (pintype "passive"))
    )
    (net (code "44") (name "Net-(IC5-Pad19)") (class "Default")
      (node (ref "IC5") (pin "19") (pinfunction "19_19") (pintype "passive"))
      (node (ref "IC6") (pin "19") (pinfunction "19_19") (pintype "passive"))
      (node (ref "IC7") (pin "19") (pinfunction "19_19") (pintype "passive"))
      (node (ref "IC8") (pin "19") (pinfunction "19_19") (pintype "passive"))
    )
    (net (code "45") (name "Net-(IC5-Pad20)") (class "Default")
      (node (ref "IC5") (pin "20") (pinfunction "20_20") (pintype "passive"))
      (node (ref "IC6") (pin "20") (pinfunction "20_20") (pintype "passive"))
      (node (ref "IC7") (pin "20") (pinfunction "20_20") (pintype "passive"))
      (node (ref "IC8") (pin "20") (pinfunction "20_20") (pintype "passive"))
    )
    (net (code "46") (name "Net-(IC5-Pad21)") (class "Default")
      (node (ref "IC5") (pin "21") (pinfunction "21_21") (pintype "passive"))
      (node (ref "IC6") (pin "21") (pinfunction "21_21") (pintype "passive"))
      (node (ref "IC7") (pin "21") (pinfunction "21_21") (pintype "passive"))
      (node (ref "IC8") (pin "21") (pinfunction "21_21") (pintype "passive"))
    )
    (net (code "47") (name "Net-(IC5-Pad22)") (class "Default")
      (node (ref "IC5") (pin "22") (pinfunction "22_22") (pintype "passive"))
      (node (ref "IC6") (pin "22") (pinfunction "22_22") (pintype "passive"))
      (node (ref "IC7") (pin "22") (pinfunction "22_22") (pintype "passive"))
      (node (ref "IC8") (pin "22") (pinfunction "22_22") (pintype "passive"))
    )
    (net (code "48") (name "Net-(IC5-Pad23)") (class "Default")
      (node (ref "IC5") (pin "23") (pinfunction "23_23") (pintype "passive"))
      (node (ref "IC6") (pin "23") (pinfunction "23_23") (pintype "passive"))
      (node (ref "IC7") (pin "23") (pinfunction "23_23") (pintype "passive"))
      (node (ref "IC8") (pin "23") (pinfunction "23_23") (pintype "passive"))
    )
    (net (code "49") (name "Net-(IC5-Pad24)") (class "Default")
      (node (ref "IC5") (pin "24") (pinfunction "24_24") (pintype "passive"))
      (node (ref "IC6") (pin "24") (pinfunction "24_24") (pintype "passive"))
      (node (ref "IC7") (pin "24") (pinfunction "24_24") (pintype "passive"))
      (node (ref "IC8") (pin "24") (pinfunction "24_24") (pintype "passive"))
    )
    (net (code "50") (name "Net-(IC10-Pad1)") (class "Default")
      (node (ref "IC10") (pin "1") (pinfunction "1_1") (pintype "passive"))
      (node (ref "IC11") (pin "1") (pinfunction "1_1") (pintype "passive"))
      (node (ref "IC12") (pin "1") (pinfunction "1_1") (pintype "passive"))
      (node (ref "IC13") (pin "1") (pinfunction "1_1") (pintype "passive"))
    )
    (net (code "51") (name "Net-(IC10-Pad2)") (class "Default")
      (node (ref "IC10") (pin "2") (pinfunction "2_2") (pintype "passive"))
      (node (ref "IC11") (pin "2") (pinfunction "2_2") (pintype "passive"))
      (node (ref "IC12") (pin "2") (pinfunction "2_2") (pintype "passive"))
      (node (ref "IC13") (pin "2") (pinfunction "2_2") (pintype "passive"))
    )
    (net (code "52") (name "Net-(IC10-Pad3)") (class "Default")
      (node (ref "IC10") (pin "3") (pinfunction "3_3") (pintype "passive"))
      (node (ref "IC11") (pin "3") (pinfunction "3_3") (pintype "passive"))
      (node (ref "IC12") (pin "3") (pinfunction "3_3") (pintype "passive"))
      (node (ref "IC13") (pin "3") (pinfunction "3_3") (pintype "passive"))
    )
    (net (code "53") (name "Net-(IC10-Pad4)") (class "Default")
      (node (ref "IC10") (pin "4") (pinfunction "4_4") (pintype "passive"))
      (node (ref "IC11") (pin "4") (pinfunction "4_4") (pintype "passive"))
      (node (ref "IC12") (pin "4") (pinfunction "4_4") (pintype "passive"))
      (node (ref "IC13") (pin "4") (pinfunction "4_4") (pintype "passive"))
    )
    (net (code "54") (name "Net-(IC10-Pad5)") (class "Default")
      (node (ref "IC10") (pin "5") (pinfunction "5_5") (pintype "passive"))
      (node (ref "IC11") (pin "5") (pinfunction "5_5") (pintype "passive"))
      (node (ref "IC12") (pin "5") (pinfunction "5_5") (pintype "passive"))
      (node (ref "IC13") (pin "5") (pinfunction "5_5") (pintype "passive"))
    )
    (net (code "55") (name "Net-(IC10-Pad6)") (class "Default")
      (node (ref "IC10") (pin "6") (pinfunction "6_6") (pintype "passive"))
      (node (ref "IC11") (pin "6") (pinfunction "6_6") (pintype "passive"))
      (node (ref "IC12") (pin "6") (pinfunction "6_6") (pintype "passive"))
      (node (ref "IC13") (pin "6") (pinfunction "6_6") (pintype "passive"))
    )
    (net (code "56") (name "Net-(IC10-Pad7)") (class "Default")
      (node (ref "IC10") (pin "7") (pinfunction "7_7") (pintype "passive"))
      (node (ref "IC11") (pin "7") (pinfunction "7_7") (pintype "passive"))
      (node (ref "IC12") (pin "7") (pinfunction "7_7") (pintype "passive"))
      (node (ref "IC13") (pin "7") (pinfunction "7_7") (pintype "passive"))
    )
    (net (code "57") (name "Net-(IC10-Pad8)") (class "Default")
      (node (ref "IC10") (pin "8") (pinfunction "8_8") (pintype "passive"))
      (node (ref "IC11") (pin "8") (pinfunction "8_8") (pintype "passive"))
      (node (ref "IC12") (pin "8") (pinfunction "8_8") (pintype "passive"))
      (node (ref "IC13") (pin "8") (pinfunction "8_8") (pintype "passive"))
    )
    (net (code "58") (name "Net-(IC10-Pad9)") (class "Default")
      (node (ref "IC10") (pin "9") (pinfunction "9_9") (pintype "passive"))
      (node (ref "IC11") (pin "9") (pinfunction "9_9") (pintype "passive"))
      (node (ref "IC12") (pin "9") (pinfunction "9_9") (pintype "passive"))
      (node (ref "IC13") (pin "9") (pinfunction "9_9") (pintype "passive"))
    )
    (net (code "59") (name "Net-(IC10-Pad10)") (class "Default")
      (node (ref "IC10") (pin "10") (pinfunction "10_10") (pintype "passive"))
      (node (ref "IC11") (pin "10") (pinfunction "10_10") (pintype "passive"))
      (node (ref "IC12") (pin "10") (pinfunction "10_10") (pintype "passive"))
      (node (ref "IC13") (pin "10") (pinfunction "10_10") (pintype "passive"))
    )
    (net (code "60") (name "Net-(IC10-Pad11)") (class "Default")
      (node (ref "IC10") (pin "11") (pinfunction "11_11") (pintype "passive"))
      (node (ref "IC11") (pin "11") (pinfunction "11_11") (pintype "passive"))
      (node (ref "IC12") (pin "11") (pinfunction "11_11") (pintype "passive"))
      (node (ref "IC13") (pin "11") (pinfunction "11_11") (pintype "passive"))
    )
    (net (code "61") (name "Net-(IC10-Pad12)") (class "Default")
      (node (ref "IC10") (pin "12") (pinfunction "12_12") (pintype "passive"))
      (node (ref "IC11") (pin "12") (pinfunction "12_12") (pintype "passive"))
      (node (ref "IC12") (pin "12") (pinfunction "12_12") (pintype "passive"))
      (node (ref "IC13") (pin "12") (pinfunction "12_12") (pintype "passive"))
    )
    (net (code "62") (name "Net-(IC10-Pad13)") (class "Default")
      (node (ref "IC10") (pin "13") (pinfunction "13_13") (pintype "passive"))
      (node (ref "IC11") (pin "13") (pinfunction "13_13") (pintype "passive"))
      (node (ref "IC12") (pin "13") (pinfunction "13_13") (pintype "passive"))
      (node (ref "IC13") (pin "13") (pinfunction "13_13") (pintype "passive"))
    )
    (net (code "63") (name "Net-(IC10-Pad14)") (class "Default")
      (node (ref "IC10") (pin "14") (pinfunction "14_14") (pintype "passive"))
      (node (ref "IC11") (pin "14") (pinfunction "14_14") (pintype "passive"))
      (node (ref "IC12") (pin "14") (pinfunction "14_14") (pintype "passive"))
      (node (ref "IC13") (pin "14") (pinfunction "14_14") (pintype "passive"))
    )
    (net (code "64") (name "Net-(IC10-Pad15)") (class "Default")
      (node (ref "IC10") (pin "15") (pinfunction "15_15") (pintype "passive"))
      (node (ref "IC11") (pin "15") (pinfunction "15_15") (pintype "passive"))
      (node (ref "IC12") (pin "15") (pinfunction "15_15") (pintype "passive"))
      (node (ref "IC13") (pin "15") (pinfunction "15_15") (pintype "passive"))
    )
    (net (code "65") (name "Net-(IC10-Pad16)") (class "Default")
      (node (ref "IC10") (pin "16") (pinfunction "16_16") (pintype "passive"))
      (node (ref "IC11") (pin "16") (pinfunction "16_16") (pintype "passive"))
      (node (ref "IC12") (pin "16") (pinfunction "16_16") (pintype "passive"))
      (node (ref "IC13") (pin "16") (pinfunction "16_16") (pintype "passive"))
    )
    (net (code "66") (name "Net-(IC10-Pad17)") (class "Default")
      (node (ref "IC10") (pin "17") (pinfunction "17_17") (pintype "passive"))
      (node (ref "IC11") (pin "17") (pinfunction "17_17") (pintype "passive"))
      (node (ref "IC12") (pin "17") (pinfunction "17_17") (pintype "passive"))
      (node (ref "IC13") (pin "17") (pinfunction "17_17") (pintype "passive"))
    )
    (net (code "67") (name "Net-(IC10-Pad18)") (class "Default")
      (node (ref "IC10") (pin "18") (pinfunction "18_18") (pintype "passive"))
      (node (ref "IC11") (pin "18") (pinfunction "18_18") (pintype "passive"))
      (node (ref "IC12") (pin "18") (pinfunction "18_18") (pintype "passive"))
      (node (ref "IC13") (pin "18") (pinfunction "18_18") (pintype "passive"))
    )
    (net (code "68") (name "Net-(IC10-Pad19)") (class "Default")
      (node (ref "IC10") (pin "19") (pinfunction "19_19") (pintype "passive"))
      (node (ref "IC11") (pin "19") (pinfunction "19_19") (pintype "passive"))
      (node (ref "IC12") (pin "19") (pinfunction "19_19") (pintype "passive"))
      (node (ref "IC13") (pin "19") (pinfunction "19_19") (pintype "passive"))
    )
    (net (code "69") (name "Net-(IC10-Pad20)") (class "Default")
      (node (ref "IC10") (pin "20") (pinfunction "20_20") (pintype "passive"))
      (node (ref "IC11") (pin "20") (pinfunction "20_20") (pintype "passive"))
      (node (ref "IC12") (pin "20") (pinfunction "20_20") (pintype "passive"))
      (node (ref "IC13") (pin "20") (pinfunction "20_20") (pintype "passive"))
    )
    (net (code "70") (name "Net-(IC10-Pad21)") (class "Default")
      (node (ref "IC10") (pin "21") (pinfunction "21_21") (pintype "passive"))
      (node (ref "IC11") (pin "21") (pinfunction "21_21") (pintype "passive"))
      (node (ref "IC12") (pin "21") (pinfunction "21_21") (pintype "passive"))
      (node (ref "IC13") (pin "21") (pinfunction "21_21") (pintype "passive"))
    )
    (net (code "71") (name "Net-(IC10-Pad22)") (class "Default")
      (node (ref "IC10") (pin "22") (pinfunction "22_22") (pintype "passive"))
      (node (ref "IC11") (pin "22") (pinfunction "22_22") (pintype "passive"))
      (node (ref "IC12") (pin "22") (pinfunction "22_22") (pintype "passive"))
      (node (ref "IC13") (pin "22") (pinfunction "22_22") (pintype "passive"))
    )
    (net (code "72") (name "Net-(IC10-Pad23)") (class "Default")
      (node (ref "IC10") (pin "23") (pinfunction "23_23") (pintype "passive"))
      (node (ref "IC11") (pin "23") (pinfunction "23_23") (pintype "passive"))
      (node (ref "IC12") (pin "23") (pinfunction "23_23") (pintype "passive"))
      (node (ref "IC13") (pin "23") (pinfunction "23_23") (pintype "passive"))
    )
    (net (code "73") (name "Net-(IC10-Pad24)") (class "Default")
      (node (ref "IC10") (pin "24") (pinfunction "24_24") (pintype "passive"))
      (node (ref "IC11") (pin "24") (pinfunction "24_24") (pintype "passive"))
      (node (ref "IC12") (pin "24") (pinfunction "24_24") (pintype "passive"))
      (node (ref "IC13") (pin "24") (pinfunction "24_24") (pintype "passive"))
    )
    (net (code "74") (name "Net-(IC14-Pad1)") (class "Default")
      (node (ref "IC14") (pin "1") (pinfunction "1_1") (pintype "passive"))
      (node (ref "IC15") (pin "1") (pinfunction "1_1") (pintype "passive"))
      (node (ref "IC16") (pin "1") (pinfunction "1_1") (pintype "passive"))
      (node (ref "IC17") (pin "1") (pinfunction "1_1") (pintype "passive"))
    )
    (net (code "75") (name "Net-(IC14-Pad2)") (class "Default")
      (node (ref "IC14") (pin "2") (pinfunction "2_2") (pintype "passive"))
      (node (ref "IC15") (pin "2") (pinfunction "2_2") (pintype "passive"))
      (node (ref "IC16") (pin "2") (pinfunction "2_2") (pintype "passive"))
      (node (ref "IC17") (pin "2") (pinfunction "2_2") (pintype "passive"))
    )
    (net (code "76") (name "Net-(IC14-Pad3)") (class "Default")
      (node (ref "IC14") (pin "3") (pinfunction "3_3") (pintype "passive"))
      (node (ref "IC15") (pin "3") (pinfunction "3_3") (pintype "passive"))
      (node (ref "IC16") (pin "3") (pinfunction "3_3") (pintype "passive"))
      (node (ref "IC17") (pin "3") (pinfunction "3_3") (pintype "passive"))
    )
    (net (code "77") (name "Net-(IC14-Pad4)") (class "Default")
      (node (ref "IC14") (pin "4") (pinfunction "4_4") (pintype "passive"))
      (node (ref "IC15") (pin "4") (pinfunction "4_4") (pintype "passive"))
      (node (ref "IC16") (pin "4") (pinfunction "4_4") (pintype "passive"))
      (node (ref "IC17") (pin "4") (pinfunction "4_4") (pintype "passive"))
    )
    (net (code "78") (name "Net-(IC14-Pad5)") (class "Default")
      (node (ref "IC14") (pin "5") (pinfunction "5_5") (pintype "passive"))
      (node (ref "IC15") (pin "5") (pinfunction "5_5") (pintype "passive"))
      (node (ref "IC16") (pin "5") (pinfunction "5_5") (pintype "passive"))
      (node (ref "IC17") (pin "5") (pinfunction "5_5") (pintype "passive"))
    )
    (net (code "79") (name "Net-(IC14-Pad6)") (class "Default")
      (node (ref "IC14") (pin "6") (pinfunction "6_6") (pintype "passive"))
      (node (ref "IC15") (pin "6") (pinfunction "6_6") (pintype "passive"))
      (node (ref "IC16") (pin "6") (pinfunction "6_6") (pintype "passive"))
      (node (ref "IC17") (pin "6") (pinfunction "6_6") (pintype "passive"))
    )
    (net (code "80") (name "Net-(IC14-Pad7)") (class "Default")
      (node (ref "IC14") (pin "7") (pinfunction "7_7") (pintype "passive"))
      (node (ref "IC15") (pin "7") (pinfunction "7_7") (pintype "passive"))
      (node (ref "IC16") (pin "7") (pinfunction "7_7") (pintype "passive"))
      (node (ref "IC17") (pin "7") (pinfunction "7_7") (pintype "passive"))
    )
    (net (code "81") (name "Net-(IC14-Pad8)") (class "Default")
      (node (ref "IC14") (pin "8") (pinfunction "8_8") (pintype "passive"))
      (node (ref "IC15") (pin "8") (pinfunction "8_8") (pintype "passive"))
      (node (ref "IC16") (pin "8") (pinfunction "8_8") (pintype "passive"))
      (node (ref "IC17") (pin "8") (pinfunction "8_8") (pintype "passive"))
    )
    (net (code "82") (name "Net-(IC14-Pad9)") (class "Default")
      (node (ref "IC14") (pin "9") (pinfunction "9_9") (pintype "passive"))
      (node (ref "IC15") (pin "9") (pinfunction "9_9") (pintype "passive"))
      (node (ref "IC16") (pin "9") (pinfunction "9_9") (pintype "passive"))
      (node (ref "IC17") (pin "9") (pinfunction "9_9") (pintype "passive"))
    )
    (net (code "83") (name "Net-(IC14-Pad10)") (class "Default")
      (node (ref "IC14") (pin "10") (pinfunction "10_10") (pintype "passive"))
      (node (ref "IC15") (pin "10") (pinfunction "10_10") (pintype "passive"))
      (node (ref "IC16") (pin "10") (pinfunction "10_10") (pintype "passive"))
      (node (ref "IC17") (pin "10") (pinfunction "10_10") (pintype "passive"))
    )
    (net (code "84") (name "Net-(IC14-Pad11)") (class "Default")
      (node (ref "IC14") (pin "11") (pinfunction "11_11") (pintype "passive"))
      (node (ref "IC15") (pin "11") (pinfunction "11_11") (pintype "passive"))
      (node (ref "IC16") (pin "11") (pinfunction "11_11") (pintype "passive"))
      (node (ref "IC17") (pin "11") (pinfunction "11_11") (pintype "passive"))
    )
    (net (code "85") (name "Net-(IC14-Pad12)") (class "Default")
      (node (ref "IC14") (pin "12") (pinfunction "12_12") (pintype "passive"))
      (node (ref "IC15") (pin "12") (pinfunction "12_12") (pintype "passive"))
      (node (ref "IC16") (pin "12") (pinfunction "12_12") (pintype "passive"))
      (node (ref "IC17") (pin "12") (pinfunction "12_12") (pintype "passive"))
    )
    (net (code "86") (name "Net-(IC14-Pad13)") (class "Default")
      (node (ref "IC14") (pin "13") (pinfunction "13_13") (pintype "passive"))
      (node (ref "IC15") (pin "13") (pinfunction "13_13") (pintype "passive"))
      (node (ref "IC16") (pin "13") (pinfunction "13_13") (pintype "passive"))
      (node (ref "IC17") (pin "13") (pinfunction "13_13") (pintype "passive"))
    )
    (net (code "87") (name "Net-(IC14-Pad14)") (class "Default")
      (node (ref "IC14") (pin "14") (pinfunction "14_14") (pintype "passive"))
      (node (ref "IC15") (pin "14") (pinfunction "14_14") (pintype "passive"))
      (node (ref "IC16") (pin "14") (pinfunction "14_14") (pintype "passive"))
      (node (ref "IC17") (pin "14") (pinfunction "14_14") (pintype "passive"))
    )
    (net (code "88") (name "Net-(IC14-Pad15)") (class "Default")
      (node (ref "IC14") (pin "15") (pinfunction "15_15") (pintype "passive"))
      (node (ref "IC15") (pin "15") (pinfunction "15_15") (pintype "passive"))
      (node (ref "IC16") (pin "15") (pinfunction "15_15") (pintype "passive"))
      (node (ref "IC17") (pin "15") (pinfunction "15_15") (pintype "passive"))
    )
    (net (code "89") (name "Net-(IC14-Pad16)") (class "Default")
      (node (ref "IC14") (pin "16") (pinfunction "16_16") (pintype "passive"))
      (node (ref "IC15") (pin "16") (pinfunction "16_16") (pintype "passive"))
      (node (ref "IC16") (pin "16") (pinfunction "16_16") (pintype "passive"))
      (node (ref "IC17") (pin "16") (pinfunction "16_16") (pintype "passive"))
    )
    (net (code "90") (name "Net-(IC14-Pad17)") (class "Default")
      (node (ref "IC14") (pin "17") (pinfunction "17_17") (pintype "passive"))
      (node (ref "IC15") (pin "17") (pinfunction "17_17") (pintype "passive"))
      (node (ref "IC16") (pin "17") (pinfunction "17_17") (pintype "passive"))
      (node (ref "IC17") (pin "17") (pinfunction "17_17") (pintype "passive"))
    )
    (net (code "91") (name "Net-(IC14-Pad18)") (class "Default")
      (node (ref "IC14") (pin "18") (pinfunction "18_18") (pintype "passive"))
      (node (ref "IC15") (pin "18") (pinfunction "18_18") (pintype "passive"))
      (node (ref "IC16") (pin "18") (pinfunction "18_18") (pintype "passive"))
      (node (ref "IC17") (pin "18") (pinfunction "18_18") (pintype "passive"))
    )
    (net (code "92") (name "Net-(IC14-Pad19)") (class "Default")
      (node (ref "IC14") (pin "19") (pinfunction "19_19") (pintype "passive"))
      (node (ref "IC15") (pin "19") (pinfunction "19_19") (pintype "passive"))
      (node (ref "IC16") (pin "19") (pinfunction "19_19") (pintype "passive"))
      (node (ref "IC17") (pin "19") (pinfunction "19_19") (pintype "passive"))
    )
    (net (code "93") (name "Net-(IC14-Pad20)") (class "Default")
      (node (ref "IC14") (pin "20") (pinfunction "20_20") (pintype "passive"))
      (node (ref "IC15") (pin "20") (pinfunction "20_20") (pintype "passive"))
      (node (ref "IC16") (pin "20") (pinfunction "20_20") (pintype "passive"))
      (node (ref "IC17") (pin "20") (pinfunction "20_20") (pintype "passive"))
    )
    (net (code "94") (name "Net-(IC14-Pad21)") (class "Default")
      (node (ref "IC14") (pin "21") (pinfunction "21_21") (pintype "passive"))
      (node (ref "IC15") (pin "21") (pinfunction "21_21") (pintype "passive"))
      (node (ref "IC16") (pin "21") (pinfunction "21_21") (pintype "passive"))
      (node (ref "IC17") (pin "21") (pinfunction "21_21") (pintype "passive"))
    )
    (net (code "95") (name "Net-(IC14-Pad22)") (class "Default")
      (node (ref "IC14") (pin "22") (pinfunction "22_22") (pintype "passive"))
      (node (ref "IC15") (pin "22") (pinfunction "22_22") (pintype "passive"))
      (node (ref "IC16") (pin "22") (pinfunction "22_22") (pintype "passive"))
      (node (ref "IC17") (pin "22") (pinfunction "22_22") (pintype "passive"))
    )
    (net (code "96") (name "Net-(IC14-Pad23)") (class "Default")
      (node (ref "IC14") (pin "23") (pinfunction "23_23") (pintype "passive"))
      (node (ref "IC15") (pin "23") (pinfunction "23_23") (pintype "passive"))
      (node (ref "IC16") (pin "23") (pinfunction "23_23") (pintype "passive"))
      (node (ref "IC17") (pin "23") (pinfunction "23_23") (pintype "passive"))
    )
    (net (code "97") (name "Net-(IC14-Pad24)") (class "Default")
      (node (ref "IC14") (pin "24") (pinfunction "24_24") (pintype "passive"))
      (node (ref "IC15") (pin "24") (pinfunction "24_24") (pintype "passive"))
      (node (ref "IC16") (pin "24") (pinfunction "24_24") (pintype "passive"))
      (node (ref "IC17") (pin "24") (pinfunction "24_24") (pintype "passive"))
    )
    (net (code "98") (name "Net-(IC18-Pad1)") (class "Default")
      (node (ref "IC18") (pin "1") (pinfunction "1_1") (pintype "passive"))
      (node (ref "IC19") (pin "1") (pinfunction "1_1") (pintype "passive"))
      (node (ref "IC20") (pin "1") (pinfunction "1_1") (pintype "passive"))
      (node (ref "IC21") (pin "1") (pinfunction "1_1") (pintype "passive"))
    )
    (net (code "99") (name "Net-(IC18-Pad2)") (class "Default")
      (node (ref "IC18") (pin "2") (pinfunction "2_2") (pintype "passive"))
      (node (ref "IC19") (pin "2") (pinfunction "2_2") (pintype "passive"))
      (node (ref "IC20") (pin "2") (pinfunction "2_2") (pintype "passive"))
      (node (ref "IC21") (pin "2") (pinfunction "2_2") (pintype "passive"))
    )
    (net (code "100") (name "Net-(IC18-Pad3)") (class "Default")
      (node (ref "IC18") (pin "3") (pinfunction "3_3") (pintype "passive"))
      (node (ref "IC19") (pin "3") (pinfunction "3_3") (pintype "passive"))
      (node (ref "IC20") (pin "3") (pinfunction "3_3") (pintype "passive"))
      (node (ref "IC21") (pin "3") (pinfunction "3_3") (pintype "passive"))
    )
    (net (code "101") (name "Net-(IC18-Pad4)") (class "Default")
      (node (ref "IC18") (pin "4") (pinfunction "4_4") (pintype "passive"))
      (node (ref "IC19") (pin "4") (pinfunction "4_4") (pintype "passive"))
      (node (ref "IC20") (pin "4") (pinfunction "4_4") (pintype "passive"))
      (node (ref "IC21") (pin "4") (pinfunction "4_4") (pintype "passive"))
    )
    (net (code "102") (name "Net-(IC18-Pad5)") (class "Default")
      (node (ref "IC18") (pin "5") (pinfunction "5_5") (pintype "passive"))
      (node (ref "IC19") (pin "5") (pinfunction "5_5") (pintype "passive"))
      (node (ref "IC20") (pin "5") (pinfunction "5_5") (pintype "passive"))
      (node (ref "IC21") (pin "5") (pinfunction "5_5") (pintype "passive"))
    )
    (net (code "103") (name "Net-(IC18-Pad6)") (class "Default")
      (node (ref "IC18") (pin "6") (pinfunction "6_6") (pintype "passive"))
      (node (ref "IC19") (pin "6") (pinfunction "6_6") (pintype "passive"))
      (node (ref "IC20") (pin "6") (pinfunction "6_6") (pintype "passive"))
      (node (ref "IC21") (pin "6") (pinfunction "6_6") (pintype "passive"))
    )
    (net (code "104") (name "Net-(IC18-Pad7)") (class "Default")
      (node (ref "IC18") (pin "7") (pinfunction "7_7") (pintype "passive"))
      (node (ref "IC19") (pin "7") (pinfunction "7_7") (pintype "passive"))
      (node (ref "IC20") (pin "7") (pinfunction "7_7") (pintype "passive"))
      (node (ref "IC21") (pin "7") (pinfunction "7_7") (pintype "passive"))
    )
    (net (code "105") (name "Net-(IC18-Pad8)") (class "Default")
      (node (ref "IC18") (pin "8") (pinfunction "8_8") (pintype "passive"))
      (node (ref "IC19") (pin "8") (pinfunction "8_8") (pintype "passive"))
      (node (ref "IC20") (pin "8") (pinfunction "8_8") (pintype "passive"))
      (node (ref "IC21") (pin "8") (pinfunction "8_8") (pintype "passive"))
    )
    (net (code "106") (name "Net-(IC18-Pad9)") (class "Default")
      (node (ref "IC18") (pin "9") (pinfunction "9_9") (pintype "passive"))
      (node (ref "IC19") (pin "9") (pinfunction "9_9") (pintype "passive"))
      (node (ref "IC20") (pin "9") (pinfunction "9_9") (pintype "passive"))
      (node (ref "IC21") (pin "9") (pinfunction "9_9") (pintype "passive"))
    )
    (net (code "107") (name "Net-(IC18-Pad10)") (class "Default")
      (node (ref "IC18") (pin "10") (pinfunction "10_10") (pintype "passive"))
      (node (ref "IC19") (pin "10") (pinfunction "10_10") (pintype "passive"))
      (node (ref "IC20") (pin "10") (pinfunction "10_10") (pintype "passive"))
      (node (ref "IC21") (pin "10") (pinfunction "10_10") (pintype "passive"))
    )
    (net (code "108") (name "Net-(IC18-Pad11)") (class "Default")
      (node (ref "IC18") (pin "11") (pinfunction "11_11") (pintype "passive"))
      (node (ref "IC19") (pin "11") (pinfunction "11_11") (pintype "passive"))
      (node (ref "IC20") (pin "11") (pinfunction "11_11") (pintype "passive"))
      (node (ref "IC21") (pin "11") (pinfunction "11_11") (pintype "passive"))
    )
    (net (code "109") (name "Net-(IC18-Pad12)") (class "Default")
      (node (ref "IC18") (pin "12") (pinfunction "12_12") (pintype "passive"))
      (node (ref "IC19") (pin "12") (pinfunction "12_12") (pintype "passive"))
      (node (ref "IC20") (pin "12") (pinfunction "12_12") (pintype "passive"))
      (node (ref "IC21") (pin "12") (pinfunction "12_12") (pintype "passive"))
    )
    (net (code "110") (name "Net-(IC18-Pad13)") (class "Default")
      (node (ref "IC18") (pin "13") (pinfunction "13_13") (pintype "passive"))
      (node (ref "IC19") (pin "13") (pinfunction "13_13") (pintype "passive"))
      (node (ref "IC20") (pin "13") (pinfunction "13_13") (pintype "passive"))
      (node (ref "IC21") (pin "13") (pinfunction "13_13") (pintype "passive"))
    )
    (net (code "111") (name "Net-(IC18-Pad14)") (class "Default")
      (node (ref "IC18") (pin "14") (pinfunction "14_14") (pintype "passive"))
      (node (ref "IC19") (pin "14") (pinfunction "14_14") (pintype "passive"))
      (node (ref "IC20") (pin "14") (pinfunction "14_14") (pintype "passive"))
      (node (ref "IC21") (pin "14") (pinfunction "14_14") (pintype "passive"))
    )
    (net (code "112") (name "Net-(IC18-Pad15)") (class "Default")
      (node (ref "IC18") (pin "15") (pinfunction "15_15") (pintype "passive"))
      (node (ref "IC19") (pin "15") (pinfunction "15_15") (pintype "passive"))
      (node (ref "IC20") (pin "15") (pinfunction "15_15") (pintype "passive"))
      (node (ref "IC21") (pin "15") (pinfunction "15_15") (pintype "passive"))
    )
    (net (code "113") (name "Net-(IC18-Pad16)") (class "Default")
      (node (ref "IC18") (pin "16") (pinfunction "16_16") (pintype "passive"))
      (node (ref "IC19") (pin "16") (pinfunction "16_16") (pintype "passive"))
      (node (ref "IC20") (pin "16") (pinfunction "16_16") (pintype "passive"))
      (node (ref "IC21") (pin "16") (pinfunction "16_16") (pintype "passive"))
    )
    (net (code "114") (name "Net-(IC18-Pad17)") (class "Default")
      (node (ref "IC18") (pin "17") (pinfunction "17_17") (pintype "passive"))
      (node (ref "IC19") (pin "17") (pinfunction "17_17") (pintype "passive"))
      (node (ref "IC20") (pin "17") (pinfunction "17_17") (pintype "passive"))
      (node (ref "IC21") (pin "17") (pinfunction "17_17") (pintype "passive"))
    )
    (net (code "115") (name "Net-(IC18-Pad18)") (class "Default")
      (node (ref "IC18") (pin "18") (pinfunction "18_18") (pintype "passive"))
      (node (ref "IC19") (pin "18") (pinfunction "18_18") (pintype "passive"))
      (node (ref "IC20") (pin "18") (pinfunction "18_18") (pintype "passive"))
      (node (ref "IC21") (pin "18") (pinfunction "18_18") (pintype "passive"))
    )
    (net (code "116") (name "Net-(IC18-Pad19)") (class "Default")
      (node (ref "IC18") (pin "19") (pinfunction "19_19") (pintype "passive"))
      (node (ref "IC19") (pin "19") (pinfunction "19_19") (pintype "passive"))
      (node (ref "IC20") (pin "19") (pinfunction "19_19") (pintype "passive"))
      (node (ref "IC21") (pin "19") (pinfunction "19_19") (pintype "passive"))
    )
    (net (code "117") (name "Net-(IC18-Pad20)") (class "Default")
      (node (ref "IC18") (pin "20") (pinfunction "20_20") (pintype "passive"))
      (node (ref "IC19") (pin "20") (pinfunction "20_20") (pintype "passive"))
      (node (ref "IC20") (pin "20") (pinfunction "20_20") (pintype "passive"))
      (node (ref "IC21") (pin "20") (pinfunction "20_20") (pintype "passive"))
    )
    (net (code "118") (name "Net-(IC18-Pad21)") (class "Default")
      (node (ref "IC18") (pin "21") (pinfunction "21_21") (pintype "passive"))
      (node (ref "IC19") (pin "21") (pinfunction "21_21") (pintype "passive"))
      (node (ref "IC20") (pin "21") (pinfunction "21_21") (pintype "passive"))
      (node (ref "IC21") (pin "21") (pinfunction "21_21") (pintype "passive"))
    )
    (net (code "119") (name "Net-(IC18-Pad22)") (class "Default")
      (node (ref "IC18") (pin "22") (pinfunction "22_22") (pintype "passive"))
      (node (ref "IC19") (pin "22") (pinfunction "22_22") (pintype "passive"))
      (node (ref "IC20") (pin "22") (pinfunction "22_22") (pintype "passive"))
      (node (ref "IC21") (pin "22") (pinfunction "22_22") (pintype "passive"))
    )
    (net (code "120") (name "Net-(IC18-Pad23)") (class "Default")
      (node (ref "IC18") (pin "23") (pinfunction "23_23") (pintype "passive"))
      (node (ref "IC19") (pin "23") (pinfunction "23_23") (pintype "passive"))
      (node (ref "IC20") (pin "23") (pinfunction "23_23") (pintype "passive"))
      (node (ref "IC21") (pin "23") (pinfunction "23_23") (pintype "passive"))
    )
    (net (code "121") (name "Net-(IC18-Pad24)") (class "Default")
      (node (ref "IC18") (pin "24") (pinfunction "24_24") (pintype "passive"))
      (node (ref "IC19") (pin "24") (pinfunction "24_24") (pintype "passive"))
      (node (ref "IC20") (pin "24") (pinfunction "24_24") (pintype "passive"))
      (node (ref "IC21") (pin "24") (pinfunction "24_24") (pintype "passive"))
    )
    (net (code "122") (name "Net-(IC22-Pad1)") (class "Default")
      (node (ref "IC22") (pin "1") (pinfunction "1_1") (pintype "passive"))
      (node (ref "IC23") (pin "1") (pinfunction "1_1") (pintype "passive"))
      (node (ref "IC24") (pin "1") (pinfunction "1_1") (pintype "passive"))
      (node (ref "IC25") (pin "1") (pinfunction "1_1") (pintype "passive"))
    )
    (net (code "123") (name "Net-(IC22-Pad2)") (class "Default")
      (node (ref "IC22") (pin "2") (pinfunction "2_2") (pintype "passive"))
      (node (ref "IC23") (pin "2") (pinfunction "2_2") (pintype "passive"))
      (node (ref "IC24") (pin "2") (pinfunction "2_2") (pintype "passive"))
      (node (ref "IC25") (pin "2") (pinfunction "2_2") (pintype "passive"))
    )
    (net (code "124") (name "Net-(IC22-Pad3)") (class "Default")
      (node (ref "IC22") (pin "3") (pinfunction "3_3") (pintype "passive"))
      (node (ref "IC23") (pin "3") (pinfunction "3_3") (pintype "passive"))
      (node (ref "IC24") (pin "3") (pinfunction "3_3") (pintype "passive"))
      (node (ref "IC25") (pin "3") (pinfunction "3_3") (pintype "passive"))
    )
    (net (code "125") (name "Net-(IC22-Pad4)") (class "Default")
      (node (ref "IC22") (pin "4") (pinfunction "4_4") (pintype "passive"))
      (node (ref "IC23") (pin "4") (pinfunction "4_4") (pintype "passive"))
      (node (ref "IC24") (pin "4") (pinfunction "4_4") (pintype "passive"))
      (node (ref "IC25") (pin "4") (pinfunction "4_4") (pintype "passive"))
    )
    (net (code "126") (name "Net-(IC22-Pad5)") (class "Default")
      (node (ref "IC22") (pin "5") (pinfunction "5_5") (pintype "passive"))
      (node (ref "IC23") (pin "5") (pinfunction "5_5") (pintype "passive"))
      (node (ref "IC24") (pin "5") (pinfunction "5_5") (pintype "passive"))
      (node (ref "IC25") (pin "5") (pinfunction "5_5") (pintype "passive"))
    )
    (net (code "127") (name "Net-(IC22-Pad6)") (class "Default")
      (node (ref "IC22") (pin "6") (pinfunction "6_6") (pintype "passive"))
      (node (ref "IC23") (pin "6") (pinfunction "6_6") (pintype "passive"))
      (node (ref "IC24") (pin "6") (pinfunction "6_6") (pintype "passive"))
      (node (ref "IC25") (pin "6") (pinfunction "6_6") (pintype "passive"))
    )
    (net (code "128") (name "Net-(IC22-Pad7)") (class "Default")
      (node (ref "IC22") (pin "7") (pinfunction "7_7") (pintype "passive"))
      (node (ref "IC23") (pin "7") (pinfunction "7_7") (pintype "passive"))
      (node (ref "IC24") (pin "7") (pinfunction "7_7") (pintype "passive"))
      (node (ref "IC25") (pin "7") (pinfunction "7_7") (pintype "passive"))
    )
    (net (code "129") (name "Net-(IC22-Pad8)") (class "Default")
      (node (ref "IC22") (pin "8") (pinfunction "8_8") (pintype "passive"))
      (node (ref "IC23") (pin "8") (pinfunction "8_8") (pintype "passive"))
      (node (ref "IC24") (pin "8") (pinfunction "8_8") (pintype "passive"))
      (node (ref "IC25") (pin "8") (pinfunction "8_8") (pintype "passive"))
    )
    (net (code "130") (name "Net-(IC22-Pad9)") (class "Default")
      (node (ref "IC22") (pin "9") (pinfunction "9_9") (pintype "passive"))
      (node (ref "IC23") (pin "9") (pinfunction "9_9") (pintype "passive"))
      (node (ref "IC24") (pin "9") (pinfunction "9_9") (pintype "passive"))
      (node (ref "IC25") (pin "9") (pinfunction "9_9") (pintype "passive"))
    )
    (net (code "131") (name "Net-(IC22-Pad10)") (class "Default")
      (node (ref "IC22") (pin "10") (pinfunction "10_10") (pintype "passive"))
      (node (ref "IC23") (pin "10") (pinfunction "10_10") (pintype "passive"))
      (node (ref "IC24") (pin "10") (pinfunction "10_10") (pintype "passive"))
      (node (ref "IC25") (pin "10") (pinfunction "10_10") (pintype "passive"))
    )
    (net (code "132") (name "Net-(IC22-Pad11)") (class "Default")
      (node (ref "IC22") (pin "11") (pinfunction "11_11") (pintype "passive"))
      (node (ref "IC23") (pin "11") (pinfunction "11_11") (pintype "passive"))
      (node (ref "IC24") (pin "11") (pinfunction "11_11") (pintype "passive"))
      (node (ref "IC25") (pin "11") (pinfunction "11_11") (pintype "passive"))
    )
    (net (code "133") (name "Net-(IC22-Pad12)") (class "Default")
      (node (ref "IC22") (pin "12") (pinfunction "12_12") (pintype "passive"))
      (node (ref "IC23") (pin "12") (pinfunction "12_12") (pintype "passive"))
      (node (ref "IC24") (pin "12") (pinfunction "12_12") (pintype "passive"))
      (node (ref "IC25") (pin "12") (pinfunction "12_12") (pintype "passive"))
    )
    (net (code "134") (name "Net-(IC22-Pad13)") (class "Default")
      (node (ref "IC22") (pin "13") (pinfunction "13_13") (pintype "passive"))
      (node (ref "IC23") (pin "13") (pinfunction "13_13") (pintype "passive"))
      (node (ref "IC24") (pin "13") (pinfunction "13_13") (pintype "passive"))
      (node (ref "IC25") (pin "13") (pinfunction "13_13") (pintype "passive"))
    )
    (net (code "135") (name "Net-(IC22-Pad14)") (class "Default")
      (node (ref "IC22") (pin "14") (pinfunction "14_14") (pintype "passive"))
      (node (ref "IC23") (pin "14") (pinfunction "14_14") (pintype "passive"))
      (node (ref "IC24") (pin "14") (pinfunction "14_14") (pintype "passive"))
      (node (ref "IC25") (pin "14") (pinfunction "14_14") (pintype "passive"))
    )
    (net (code "136") (name "Net-(IC22-Pad15)") (class "Default")
      (node (ref "IC22") (pin "15") (pinfunction "15_15") (pintype "passive"))
      (node (ref "IC23") (pin "15") (pinfunction "15_15") (pintype "passive"))
      (node (ref "IC24") (pin "15") (pinfunction "15_15") (pintype "passive"))
      (node (ref "IC25") (pin "15") (pinfunction "15_15") (pintype "passive"))
    )
    (net (code "137") (name "Net-(IC22-Pad16)") (class "Default")
      (node (ref "IC22") (pin "16") (pinfunction "16_16") (pintype "passive"))
      (node (ref "IC23") (pin "16") (pinfunction "16_16") (pintype "passive"))
      (node (ref "IC24") (pin "16") (pinfunction "16_16") (pintype "passive"))
      (node (ref "IC25") (pin "16") (pinfunction "16_16") (pintype "passive"))
    )
    (net (code "138") (name "Net-(IC22-Pad17)") (class "Default")
      (node (ref "IC22") (pin "17") (pinfunction "17_17") (pintype "passive"))
      (node (ref "IC23") (pin "17") (pinfunction "17_17") (pintype "passive"))
      (node (ref "IC24") (pin "17") (pinfunction "17_17") (pintype "passive"))
      (node (ref "IC25") (pin "17") (pinfunction "17_17") (pintype "passive"))
    )
    (net (code "139") (name "Net-(IC22-Pad18)") (class "Default")
      (node (ref "IC22") (pin "18") (pinfunction "18_18") (pintype "passive"))
      (node (ref "IC23") (pin "18") (pinfunction "18_18") (pintype "passive"))
      (node (ref "IC24") (pin "18") (pinfunction "18_18") (pintype "passive"))
      (node (ref "IC25") (pin "18") (pinfunction "18_18") (pintype "passive"))
    )
    (net (code "140") (name "Net-(IC22-Pad19)") (class "Default")
      (node (ref "IC22") (pin "19") (pinfunction "19_19") (pintype "passive"))
      (node (ref "IC23") (pin "19") (pinfunction "19_19") (pintype "passive"))
      (node (ref "IC24") (pin "19") (pinfunction "19_19") (pintype "passive"))
      (node (ref "IC25") (pin "19") (pinfunction "19_19") (pintype "passive"))
    )
    (net (code "141") (name "Net-(IC22-Pad20)") (class "Default")
      (node (ref "IC22") (pin "20") (pinfunction "20_20") (pintype "passive"))
      (node (ref "IC23") (pin "20") (pinfunction "20_20") (pintype "passive"))
      (node (ref "IC24") (pin "20") (pinfunction "20_20") (pintype "passive"))
      (node (ref "IC25") (pin "20") (pinfunction "20_20") (pintype "passive"))
    )
    (net (code "142") (name "Net-(IC22-Pad21)") (class "Default")
      (node (ref "IC22") (pin "21") (pinfunction "21_21") (pintype "passive"))
      (node (ref "IC23") (pin "21") (pinfunction "21_21") (pintype "passive"))
      (node (ref "IC24") (pin "21") (pinfunction "21_21") (pintype "passive"))
      (node (ref "IC25") (pin "21") (pinfunction "21_21") (pintype "passive"))
    )
    (net (code "143") (name "Net-(IC22-Pad22)") (class "Default")
      (node (ref "IC22") (pin "22") (pinfunction "22_22") (pintype "passive"))
      (node (ref "IC23") (pin "22") (pinfunction "22_22") (pintype "passive"))
      (node (ref "IC24") (pin "22") (pinfunction "22_22") (pintype "passive"))
      (node (ref "IC25") (pin "22") (pinfunction "22_22") (pintype "passive"))
    )
    (net (code "144") (name "Net-(IC22-Pad23)") (class "Default")
      (node (ref "IC22") (pin "23") (pinfunction "23_23") (pintype "passive"))
      (node (ref "IC23") (pin "23") (pinfunction "23_23") (pintype "passive"))
      (node (ref "IC24") (pin "23") (pinfunction "23_23") (pintype "passive"))
      (node (ref "IC25") (pin "23") (pinfunction "23_23") (pintype "passive"))
    )
    (net (code "145") (name "Net-(IC22-Pad24)") (class "Default")
      (node (ref "IC22") (pin "24") (pinfunction "24_24") (pintype "passive"))
      (node (ref "IC23") (pin "24") (pinfunction "24_24") (pintype "passive"))
      (node (ref "IC24") (pin "24") (pinfunction "24_24") (pintype "passive"))
      (node (ref "IC25") (pin "24") (pinfunction "24_24") (pintype "passive"))
    )
    (net (code "146") (name "Net-(IC26-Pad1)") (class "Default")
      (node (ref "IC26") (pin "1") (pinfunction "1_1") (pintype "passive"))
      (node (ref "IC27") (pin "1") (pinfunction "1_1") (pintype "passive"))
      (node (ref "IC28") (pin "1") (pinfunction "1_1") (pintype "passive"))
      (node (ref "IC29") (pin "1") (pinfunction "1_1") (pintype "passive"))
    )
    (net (code "147") (name "Net-(IC26-Pad2)") (class "Default")
      (node (ref "IC26") (pin "2") (pinfunction "2_2") (pintype "passive"))
      (node (ref "IC27") (pin "2") (pinfunction "2_2") (pintype "passive"))
      (node (ref "IC28") (pin "2") (pinfunction "2_2") (pintype "passive"))
      (node (ref "IC29") (pin "2") (pinfunction "2_2") (pintype "passive"))
    )
    (net (code "148") (name "Net-(IC26-Pad3)") (class "Default")
      (node (ref "IC26") (pin "3") (pinfunction "3_3") (pintype "passive"))
      (node (ref "IC27") (pin "3") (pinfunction "3_3") (pintype "passive"))
      (node (ref "IC28") (pin "3") (pinfunction "3_3") (pintype "passive"))
      (node (ref "IC29") (pin "3") (pinfunction "3_3") (pintype "passive"))
    )
    (net (code "149") (name "Net-(IC26-Pad4)") (class "Default")
      (node (ref "IC26") (pin "4") (pinfunction "4_4") (pintype "passive"))
      (node (ref "IC27") (pin "4") (pinfunction "4_4") (pintype "passive"))
      (node (ref "IC28") (pin "4") (pinfunction "4_4") (pintype "passive"))
      (node (ref "IC29") (pin "4") (pinfunction "4_4") (pintype "passive"))
    )
    (net (code "150") (name "Net-(IC26-Pad5)") (class "Default")
      (node (ref "IC26") (pin "5") (pinfunction "5_5") (pintype "passive"))
      (node (ref "IC27") (pin "5") (pinfunction "5_5") (pintype "passive"))
      (node (ref "IC28") (pin "5") (pinfunction "5_5") (pintype "passive"))
      (node (ref "IC29") (pin "5") (pinfunction "5_5") (pintype "passive"))
    )
    (net (code "151") (name "Net-(IC26-Pad6)") (class "Default")
      (node (ref "IC26") (pin "6") (pinfunction "6_6") (pintype "passive"))
      (node (ref "IC27") (pin "6") (pinfunction "6_6") (pintype "passive"))
      (node (ref "IC28") (pin "6") (pinfunction "6_6") (pintype "passive"))
      (node (ref "IC29") (pin "6") (pinfunction "6_6") (pintype "passive"))
    )
    (net (code "152") (name "Net-(IC26-Pad7)") (class "Default")
      (node (ref "IC26") (pin "7") (pinfunction "7_7") (pintype "passive"))
      (node (ref "IC27") (pin "7") (pinfunction "7_7") (pintype "passive"))
      (node (ref "IC28") (pin "7") (pinfunction "7_7") (pintype "passive"))
      (node (ref "IC29") (pin "7") (pinfunction "7_7") (pintype "passive"))
    )
    (net (code "153") (name "Net-(IC26-Pad8)") (class "Default")
      (node (ref "IC26") (pin "8") (pinfunction "8_8") (pintype "passive"))
      (node (ref "IC27") (pin "8") (pinfunction "8_8") (pintype "passive"))
      (node (ref "IC28") (pin "8") (pinfunction "8_8") (pintype "passive"))
      (node (ref "IC29") (pin "8") (pinfunction "8_8") (pintype "passive"))
    )
    (net (code "154") (name "Net-(IC26-Pad9)") (class "Default")
      (node (ref "IC26") (pin "9") (pinfunction "9_9") (pintype "passive"))
      (node (ref "IC27") (pin "9") (pinfunction "9_9") (pintype "passive"))
      (node (ref "IC28") (pin "9") (pinfunction "9_9") (pintype "passive"))
      (node (ref "IC29") (pin "9") (pinfunction "9_9") (pintype "passive"))
    )
    (net (code "155") (name "Net-(IC26-Pad10)") (class "Default")
      (node (ref "IC26") (pin "10") (pinfunction "10_10") (pintype "passive"))
      (node (ref "IC27") (pin "10") (pinfunction "10_10") (pintype "passive"))
      (node (ref "IC28") (pin "10") (pinfunction "10_10") (pintype "passive"))
      (node (ref "IC29") (pin "10") (pinfunction "10_10") (pintype "passive"))
    )
    (net (code "156") (name "Net-(IC26-Pad11)") (class "Default")
      (node (ref "IC26") (pin "11") (pinfunction "11_11") (pintype "passive"))
      (node (ref "IC27") (pin "11") (pinfunction "11_11") (pintype "passive"))
      (node (ref "IC28") (pin "11") (pinfunction "11_11") (pintype "passive"))
      (node (ref "IC29") (pin "11") (pinfunction "11_11") (pintype "passive"))
    )
    (net (code "157") (name "Net-(IC26-Pad12)") (class "Default")
      (node (ref "IC26") (pin "12") (pinfunction "12_12") (pintype "passive"))
      (node (ref "IC27") (pin "12") (pinfunction "12_12") (pintype "passive"))
      (node (ref "IC28") (pin "12") (pinfunction "12_12") (pintype "passive"))
      (node (ref "IC29") (pin "12") (pinfunction "12_12") (pintype "passive"))
    )
    (net (code "158") (name "Net-(IC26-Pad13)") (class "Default")
      (node (ref "IC26") (pin "13") (pinfunction "13_13") (pintype "passive"))
      (node (ref "IC27") (pin "13") (pinfunction "13_13") (pintype "passive"))
      (node (ref "IC28") (pin "13") (pinfunction "13_13") (pintype "passive"))
      (node (ref "IC29") (pin "13") (pinfunction "13_13") (pintype "passive"))
    )
    (net (code "159") (name "Net-(IC26-Pad14)") (class "Default")
      (node (ref "IC26") (pin "14") (pinfunction "14_14") (pintype "passive"))
      (node (ref "IC27") (pin "14") (pinfunction "14_14") (pintype "passive"))
      (node (ref "IC28") (pin "14") (pinfunction "14_14") (pintype "passive"))
      (node (ref "IC29") (pin "14") (pinfunction "14_14") (pintype "passive"))
    )
    (net (code "160") (name "Net-(IC26-Pad15)") (class "Default")
      (node (ref "IC26") (pin "15") (pinfunction "15_15") (pintype "passive"))
      (node (ref "IC27") (pin "15") (pinfunction "15_15") (pintype "passive"))
      (node (ref "IC28") (pin "15") (pinfunction "15_15") (pintype "passive"))
      (node (ref "IC29") (pin "15") (pinfunction "15_15") (pintype "passive"))
    )
    (net (code "161") (name "Net-(IC26-Pad16)") (class "Default")
      (node (ref "IC26") (pin "16") (pinfunction "16_16") (pintype "passive"))
      (node (ref "IC27") (pin "16") (pinfunction "16_16") (pintype "passive"))
      (node (ref "IC28") (pin "16") (pinfunction "16_16") (pintype "passive"))
      (node (ref "IC29") (pin "16") (pinfunction "16_16") (pintype "passive"))
    )
    (net (code "162") (name "Net-(IC26-Pad17)") (class "Default")
      (node (ref "IC26") (pin "17") (pinfunction "17_17") (pintype "passive"))
      (node (ref "IC27") (pin "17") (pinfunction "17_17") (pintype "passive"))
      (node (ref "IC28") (pin "17") (pinfunction "17_17") (pintype "passive"))
      (node (ref "IC29") (pin "17") (pinfunction "17_17") (pintype "passive"))
    )
    (net (code "163") (name "Net-(IC26-Pad18)") (class "Default")
      (node (ref "IC26") (pin "18") (pinfunction "18_18") (pintype "passive"))
      (node (ref "IC27") (pin "18") (pinfunction "18_18") (pintype "passive"))
      (node (ref "IC28") (pin "18") (pinfunction "18_18") (pintype "passive"))
      (node (ref "IC29") (pin "18") (pinfunction "18_18") (pintype "passive"))
    )
    (net (code "164") (name "Net-(IC26-Pad19)") (class "Default")
      (node (ref "IC26") (pin "19") (pinfunction "19_19") (pintype "passive"))
      (node (ref "IC27") (pin "19") (pinfunction "19_19") (pintype "passive"))
      (node (ref "IC28") (pin "19") (pinfunction "19_19") (pintype "passive"))
      (node (ref "IC29") (pin "19") (pinfunction "19_19") (pintype "passive"))
    )
    (net (code "165") (name "Net-(IC26-Pad20)") (class "Default")
      (node (ref "IC26") (pin "20") (pinfunction "20_20") (pintype "passive"))
      (node (ref "IC27") (pin "20") (pinfunction "20_20") (pintype "passive"))
      (node (ref "IC28") (pin "20") (pinfunction "20_20") (pintype "passive"))
      (node (ref "IC29") (pin "20") (pinfunction "20_20") (pintype "passive"))
    )
    (net (code "166") (name "Net-(IC26-Pad21)") (class "Default")
      (node (ref "IC26") (pin "21") (pinfunction "21_21") (pintype "passive"))
      (node (ref "IC27") (pin "21") (pinfunction "21_21") (pintype "passive"))
      (node (ref "IC28") (pin "21") (pinfunction "21_21") (pintype "passive"))
      (node (ref "IC29") (pin "21") (pinfunction "21_21") (pintype "passive"))
    )
    (net (code "167") (name "Net-(IC26-Pad22)") (class "Default")
      (node (ref "IC26") (pin "22") (pinfunction "22_22") (pintype "passive"))
      (node (ref "IC27") (pin "22") (pinfunction "22_22") (pintype "passive"))
      (node (ref "IC28") (pin "22") (pinfunction "22_22") (pintype "passive"))
      (node (ref "IC29") (pin "22") (pinfunction "22_22") (pintype "passive"))
    )
    (net (code "168") (name "Net-(IC26-Pad23)") (class "Default")
      (node (ref "IC26") (pin "23") (pinfunction "23_23") (pintype "passive"))
      (node (ref "IC27") (pin "23") (pinfunction "23_23") (pintype "passive"))
      (node (ref "IC28") (pin "23") (pinfunction "23_23") (pintype "passive"))
      (node (ref "IC29") (pin "23") (pinfunction "23_23") (pintype "passive"))
    )
    (net (code "169") (name "Net-(IC26-Pad24)") (class "Default")
      (node (ref "IC26") (pin "24") (pinfunction "24_24") (pintype "passive"))
      (node (ref "IC27") (pin "24") (pinfunction "24_24") (pintype "passive"))
      (node (ref "IC28") (pin "24") (pinfunction "24_24") (pintype "passive"))
      (node (ref "IC29") (pin "24") (pinfunction "24_24") (pintype "passive"))
    )
    (net (code "170") (name "Net-(IC30-Pad1)") (class "Default")
      (node (ref "IC30") (pin "1") (pinfunction "1_1") (pintype "passive"))
      (node (ref "IC31") (pin "1") (pinfunction "1_1") (pintype "passive"))
      (node (ref "IC32") (pin "1") (pinfunction "1_1") (pintype "passive"))
      (node (ref "IC33") (pin "1") (pinfunction "1_1") (pintype "passive"))
    )
    (net (code "171") (name "Net-(IC30-Pad2)") (class "Default")
      (node (ref "IC30") (pin "2") (pinfunction "2_2") (pintype "passive"))
      (node (ref "IC31") (pin "2") (pinfunction "2_2") (pintype "passive"))
      (node (ref "IC32") (pin "2") (pinfunction "2_2") (pintype "passive"))
      (node (ref "IC33") (pin "2") (pinfunction "2_2") (pintype "passive"))
    )
    (net (code "172") (name "Net-(IC30-Pad3)") (class "Default")
      (node (ref "IC30") (pin "3") (pinfunction "3_3") (pintype "passive"))
      (node (ref "IC31") (pin "3") (pinfunction "3_3") (pintype "passive"))
      (node (ref "IC32") (pin "3") (pinfunction "3_3") (pintype "passive"))
      (node (ref "IC33") (pin "3") (pinfunction "3_3") (pintype "passive"))
    )
    (net (code "173") (name "Net-(IC30-Pad4)") (class "Default")
      (node (ref "IC30") (pin "4") (pinfunction "4_4") (pintype "passive"))
      (node (ref "IC31") (pin "4") (pinfunction "4_4") (pintype "passive"))
      (node (ref "IC32") (pin "4") (pinfunction "4_4") (pintype "passive"))
      (node (ref "IC33") (pin "4") (pinfunction "4_4") (pintype "passive"))
    )
    (net (code "174") (name "Net-(IC30-Pad5)") (class "Default")
      (node (ref "IC30") (pin "5") (pinfunction "5_5") (pintype "passive"))
      (node (ref "IC31") (pin "5") (pinfunction "5_5") (pintype "passive"))
      (node (ref "IC32") (pin "5") (pinfunction "5_5") (pintype "passive"))
      (node (ref "IC33") (pin "5") (pinfunction "5_5") (pintype "passive"))
    )
    (net (code "175") (name "Net-(IC30-Pad6)") (class "Default")
      (node (ref "IC30") (pin "6") (pinfunction "6_6") (pintype "passive"))
      (node (ref "IC31") (pin "6") (pinfunction "6_6") (pintype "passive"))
      (node (ref "IC32") (pin "6") (pinfunction "6_6") (pintype "passive"))
      (node (ref "IC33") (pin "6") (pinfunction "6_6") (pintype "passive"))
    )
    (net (code "176") (name "Net-(IC30-Pad7)") (class "Default")
      (node (ref "IC30") (pin "7") (pinfunction "7_7") (pintype "passive"))
      (node (ref "IC31") (pin "7") (pinfunction "7_7") (pintype "passive"))
      (node (ref "IC32") (pin "7") (pinfunction "7_7") (pintype "passive"))
      (node (ref "IC33") (pin "7") (pinfunction "7_7") (pintype "passive"))
    )
    (net (code "177") (name "Net-(IC30-Pad8)") (class "Default")
      (node (ref "IC30") (pin "8") (pinfunction "8_8") (pintype "passive"))
      (node (ref "IC31") (pin "8") (pinfunction "8_8") (pintype "passive"))
      (node (ref "IC32") (pin "8") (pinfunction "8_8") (pintype "passive"))
      (node (ref "IC33") (pin "8") (pinfunction "8_8") (pintype "passive"))
    )
    (net (code "178") (name "Net-(IC30-Pad9)") (class "Default")
      (node (ref "IC30") (pin "9") (pinfunction "9_9") (pintype "passive"))
      (node (ref "IC31") (pin "9") (pinfunction "9_9") (pintype "passive"))
      (node (ref "IC32") (pin "9") (pinfunction "9_9") (pintype "passive"))
      (node (ref "IC33") (pin "9") (pinfunction "9_9") (pintype "passive"))
    )
    (net (code "179") (name "Net-(IC30-Pad10)") (class "Default")
      (node (ref "IC30") (pin "10") (pinfunction "10_10") (pintype "passive"))
      (node (ref "IC31") (pin "10") (pinfunction "10_10") (pintype "passive"))
      (node (ref "IC32") (pin "10") (pinfunction "10_10") (pintype "passive"))
      (node (ref "IC33") (pin "10") (pinfunction "10_10") (pintype "passive"))
    )
    (net (code "180") (name "Net-(IC30-Pad11)") (class "Default")
      (node (ref "IC30") (pin "11") (pinfunction "11_11") (pintype "passive"))
      (node (ref "IC31") (pin "11") (pinfunction "11_11") (pintype "passive"))
      (node (ref "IC32") (pin "11") (pinfunction "11_11") (pintype "passive"))
      (node (ref "IC33") (pin "11") (pinfunction "11_11") (pintype "passive"))
    )
    (net (code "181") (name "Net-(IC30-Pad12)") (class "Default")
      (node (ref "IC30") (pin "12") (pinfunction "12_12") (pintype "passive"))
      (node (ref "IC31") (pin "12") (pinfunction "12_12") (pintype "passive"))
      (node (ref "IC32") (pin "12") (pinfunction "12_12") (pintype "passive"))
      (node (ref "IC33") (pin "12") (pinfunction "12_12") (pintype "passive"))
    )
    (net (code "182") (name "Net-(IC30-Pad13)") (class "Default")
      (node (ref "IC30") (pin "13") (pinfunction "13_13") (pintype "passive"))
      (node (ref "IC31") (pin "13") (pinfunction "13_13") (pintype "passive"))
      (node (ref "IC32") (pin "13") (pinfunction "13_13") (pintype "passive"))
      (node (ref "IC33") (pin "13") (pinfunction "13_13") (pintype "passive"))
    )
    (net (code "183") (name "Net-(IC30-Pad14)") (class "Default")
      (node (ref "IC30") (pin "14") (pinfunction "14_14") (pintype "passive"))
      (node (ref "IC31") (pin "14") (pinfunction "14_14") (pintype "passive"))
      (node (ref "IC32") (pin "14") (pinfunction "14_14") (pintype "passive"))
      (node (ref "IC33") (pin "14") (pinfunction "14_14") (pintype "passive"))
    )
    (net (code "184") (name "Net-(IC30-Pad15)") (class "Default")
      (node (ref "IC30") (pin "15") (pinfunction "15_15") (pintype "passive"))
      (node (ref "IC31") (pin "15") (pinfunction "15_15") (pintype "passive"))
      (node (ref "IC32") (pin "15") (pinfunction "15_15") (pintype "passive"))
      (node (ref "IC33") (pin "15") (pinfunction "15_15") (pintype "passive"))
    )
    (net (code "185") (name "Net-(IC30-Pad16)") (class "Default")
      (node (ref "IC30") (pin "16") (pinfunction "16_16") (pintype "passive"))
      (node (ref "IC31") (pin "16") (pinfunction "16_16") (pintype "passive"))
      (node (ref "IC32") (pin "16") (pinfunction "16_16") (pintype "passive"))
      (node (ref "IC33") (pin "16") (pinfunction "16_16") (pintype "passive"))
    )
    (net (code "186") (name "Net-(IC30-Pad17)") (class "Default")
      (node (ref "IC30") (pin "17") (pinfunction "17_17") (pintype "passive"))
      (node (ref "IC31") (pin "17") (pinfunction "17_17") (pintype "passive"))
      (node (ref "IC32") (pin "17") (pinfunction "17_17") (pintype "passive"))
      (node (ref "IC33") (pin "17") (pinfunction "17_17") (pintype "passive"))
    )
    (net (code "187") (name "Net-(IC30-Pad18)") (class "Default")
      (node (ref "IC30") (pin "18") (pinfunction "18_18") (pintype "passive"))
      (node (ref "IC31") (pin "18") (pinfunction "18_18") (pintype "passive"))
      (node (ref "IC32") (pin "18") (pinfunction "18_18") (pintype "passive"))
      (node (ref "IC33") (pin "18") (pinfunction "18_18") (pintype "passive"))
    )
    (net (code "188") (name "Net-(IC30-Pad19)") (class "Default")
      (node (ref "IC30") (pin "19") (pinfunction "19_19") (pintype "passive"))
      (node (ref "IC31") (pin "19") (pinfunction "19_19") (pintype "passive"))
      (node (ref "IC32") (pin "19") (pinfunction "19_19") (pintype "passive"))
      (node (ref "IC33") (pin "19") (pinfunction "19_19") (pintype "passive"))
    )
    (net (code "189") (name "Net-(IC30-Pad20)") (class "Default")
      (node (ref "IC30") (pin "20") (pinfunction "20_20") (pintype "passive"))
      (node (ref "IC31") (pin "20") (pinfunction "20_20") (pintype "passive"))
      (node (ref "IC32") (pin "20") (pinfunction "20_20") (pintype "passive"))
      (node (ref "IC33") (pin "20") (pinfunction "20_20") (pintype "passive"))
    )
    (net (code "190") (name "Net-(IC30-Pad21)") (class "Default")
      (node (ref "IC30") (pin "21") (pinfunction "21_21") (pintype "passive"))
      (node (ref "IC31") (pin "21") (pinfunction "21_21") (pintype "passive"))
      (node (ref "IC32") (pin "21") (pinfunction "21_21") (pintype "passive"))
      (node (ref "IC33") (pin "21") (pinfunction "21_21") (pintype "passive"))
    )
    (net (code "191") (name "Net-(IC30-Pad22)") (class "Default")
      (node (ref "IC30") (pin "22") (pinfunction "22_22") (pintype "passive"))
      (node (ref "IC31") (pin "22") (pinfunction "22_22") (pintype "passive"))
      (node (ref "IC32") (pin "22") (pinfunction "22_22") (pintype "passive"))
      (node (ref "IC33") (pin "22") (pinfunction "22_22") (pintype "passive"))
    )
    (net (code "192") (name "Net-(IC30-Pad23)") (class "Default")
      (node (ref "IC30") (pin "23") (pinfunction "23_23") (pintype "passive"))
      (node (ref "IC31") (pin "23") (pinfunction "23_23") (pintype "passive"))
      (node (ref "IC32") (pin "23") (pinfunction "23_23") (pintype "passive"))
      (node (ref "IC33") (pin "23") (pinfunction "23_23") (pintype "passive"))
    )
    (net (code "193") (name "Net-(IC30-Pad24)") (class "Default")
      (node (ref "IC30") (pin "24") (pinfunction "24_24") (pintype "passive"))
      (node (ref "IC31") (pin "24") (pinfunction "24_24") (pintype "passive"))
      (node (ref "IC32") (pin "24") (pinfunction "24_24") (pintype "passive"))
      (node (ref "IC33") (pin "24") (pinfunction "24_24") (pintype "passive"))
    )
    (net (code "194") (name "Net-(IC34-Pad1)") (class "Default")
      (node (ref "IC34") (pin "1") (pinfunction "1_1") (pintype "passive"))
      (node (ref "IC35") (pin "1") (pinfunction "1_1") (pintype "passive"))
      (node (ref "IC36") (pin "1") (pinfunction "1_1") (pintype "passive"))
      (node (ref "IC37") (pin "1") (pinfunction "1_1") (pintype "passive"))
    )
    (net (code "195") (name "Net-(IC34-Pad2)") (class "Default")
      (node (ref "IC34") (pin "2") (pinfunction "2_2") (pintype "passive"))
      (node (ref "IC35") (pin "2") (pinfunction "2_2") (pintype "passive"))
      (node (ref "IC36") (pin "2") (pinfunction "2_2") (pintype "passive"))
      (node (ref "IC37") (pin "2") (pinfunction "2_2") (pintype "passive"))
    )
    (net (code "196") (name "Net-(IC34-Pad3)") (class "Default")
      (node (ref "IC34") (pin "3") (pinfunction "3_3") (pintype "passive"))
      (node (ref "IC35") (pin "3") (pinfunction "3_3") (pintype "passive"))
      (node (ref "IC36") (pin "3") (pinfunction "3_3") (pintype "passive"))
      (node (ref "IC37") (pin "3") (pinfunction "3_3") (pintype "passive"))
    )
    (net (code "197") (name "Net-(IC34-Pad4)") (class "Default")
      (node (ref "IC34") (pin "4") (pinfunction "4_4") (pintype "passive"))
      (node (ref "IC35") (pin "4") (pinfunction "4_4") (pintype "passive"))
      (node (ref "IC36") (pin "4") (pinfunction "4_4") (pintype "passive"))
      (node (ref "IC37") (pin "4") (pinfunction "4_4") (pintype "passive"))
    )
    (net (code "198") (name "Net-(IC34-Pad5)") (class "Default")
      (node (ref "IC34") (pin "5") (pinfunction "5_5") (pintype "passive"))
      (node (ref "IC35") (pin "5") (pinfunction "5_5") (pintype "passive"))
      (node (ref "IC36") (pin "5") (pinfunction "5_5") (pintype "passive"))
      (node (ref "IC37") (pin "5") (pinfunction "5_5") (pintype "passive"))
    )
    (net (code "199") (name "Net-(IC34-Pad6)") (class "Default")
      (node (ref "IC34") (pin "6") (pinfunction "6_6") (pintype "passive"))
      (node (ref "IC35") (pin "6") (pinfunction "6_6") (pintype "passive"))
      (node (ref "IC36") (pin "6") (pinfunction "6_6") (pintype "passive"))
      (node (ref "IC37") (pin "6") (pinfunction "6_6") (pintype "passive"))
    )
    (net (code "200") (name "Net-(IC34-Pad7)") (class "Default")
      (node (ref "IC34") (pin "7") (pinfunction "7_7") (pintype "passive"))
      (node (ref "IC35") (pin "7") (pinfunction "7_7") (pintype "passive"))
      (node (ref "IC36") (pin "7") (pinfunction "7_7") (pintype "passive"))
      (node (ref "IC37") (pin "7") (pinfunction "7_7") (pintype "passive"))
    )
    (net (code "201") (name "Net-(IC34-Pad8)") (class "Default")
      (node (ref "IC34") (pin "8") (pinfunction "8_8") (pintype "passive"))
      (node (ref "IC35") (pin "8") (pinfunction "8_8") (pintype "passive"))
      (node (ref "IC36") (pin "8") (pinfunction "8_8") (pintype "passive"))
      (node (ref "IC37") (pin "8") (pinfunction "8_8") (pintype "passive"))
    )
    (net (code "202") (name "Net-(IC34-Pad9)") (class "Default")
      (node (ref "IC34") (pin "9") (pinfunction "9_9") (pintype "passive"))
      (node (ref "IC35") (pin "9") (pinfunction "9_9") (pintype "passive"))
      (node (ref "IC36") (pin "9") (pinfunction "9_9") (pintype "passive"))
      (node (ref "IC37") (pin "9") (pinfunction "9_9") (pintype "passive"))
    )
    (net (code "203") (name "Net-(IC34-Pad10)") (class "Default")
      (node (ref "IC34") (pin "10") (pinfunction "10_10") (pintype "passive"))
      (node (ref "IC35") (pin "10") (pinfunction "10_10") (pintype "passive"))
      (node (ref "IC36") (pin "10") (pinfunction "10_10") (pintype "passive"))
      (node (ref "IC37") (pin "10") (pinfunction "10_10") (pintype "passive"))
    )
    (net (code "204") (name "Net-(IC34-Pad11)") (class "Default")
      (node (ref "IC34") (pin "11") (pinfunction "11_11") (pintype "passive"))
      (node (ref "IC35") (pin "11") (pinfunction "11_11") (pintype "passive"))
      (node (ref "IC36") (pin "11") (pinfunction "11_11") (pintype "passive"))
      (node (ref "IC37") (pin "11") (pinfunction "11_11") (pintype "passive"))
    )
    (net (code "205") (name "Net-(IC34-Pad12)") (class "Default")
      (node (ref "IC34") (pin "12") (pinfunction "12_12") (pintype "passive"))
      (node (ref "IC35") (pin "12") (pinfunction "12_12") (pintype "passive"))
      (node (ref "IC36") (pin "12") (pinfunction "12_12") (pintype "passive"))
      (node (ref "IC37") (pin "12") (pinfunction "12_12") (pintype "passive"))
    )
    (net (code "206") (name "Net-(IC34-Pad13)") (class "Default")
      (node (ref "IC34") (pin "13") (pinfunction "13_13") (pintype "passive"))
      (node (ref "IC35") (pin "13") (pinfunction "13_13") (pintype "passive"))
      (node (ref "IC36") (pin "13") (pinfunction "13_13") (pintype "passive"))
      (node (ref "IC37") (pin "13") (pinfunction "13_13") (pintype "passive"))
    )
    (net (code "207") (name "Net-(IC34-Pad14)") (class "Default")
      (node (ref "IC34") (pin "14") (pinfunction "14_14") (pintype "passive"))
      (node (ref "IC35") (pin "14") (pinfunction "14_14") (pintype "passive"))
      (node (ref "IC36") (pin "14") (pinfunction "14_14") (pintype "passive"))
      (node (ref "IC37") (pin "14") (pinfunction "14_14") (pintype "passive"))
    )
    (net (code "208") (name "Net-(IC34-Pad15)") (class "Default")
      (node (ref "IC34") (pin "15") (pinfunction "15_15") (pintype "passive"))
      (node (ref "IC35") (pin "15") (pinfunction "15_15") (pintype "passive"))
      (node (ref "IC36") (pin "15") (pinfunction "15_15") (pintype "passive"))
      (node (ref "IC37") (pin "15") (pinfunction "15_15") (pintype "passive"))
    )
    (net (code "209") (name "Net-(IC34-Pad16)") (class "Default")
      (node (ref "IC34") (pin "16") (pinfunction "16_16") (pintype "passive"))
      (node (ref "IC35") (pin "16") (pinfunction "16_16") (pintype "passive"))
      (node (ref "IC36") (pin "16") (pinfunction "16_16") (pintype "passive"))
      (node (ref "IC37") (pin "16") (pinfunction "16_16") (pintype "passive"))
    )
    (net (code "210") (name "Net-(IC34-Pad17)") (class "Default")
      (node (ref "IC34") (pin "17") (pinfunction "17_17") (pintype "passive"))
      (node (ref "IC35") (pin "17") (pinfunction "17_17") (pintype "passive"))
      (node (ref "IC36") (pin "17") (pinfunction "17_17") (pintype "passive"))
      (node (ref "IC37") (pin "17") (pinfunction "17_17") (pintype "passive"))
    )
    (net (code "211") (name "Net-(IC34-Pad18)") (class "Default")
      (node (ref "IC34") (pin "18") (pinfunction "18_18") (pintype "passive"))
      (node (ref "IC35") (pin "18") (pinfunction "18_18") (pintype "passive"))
      (node (ref "IC36") (pin "18") (pinfunction "18_18") (pintype "passive"))
      (node (ref "IC37") (pin "18") (pinfunction "18_18") (pintype "passive"))
    )
    (net (code "212") (name "Net-(IC34-Pad19)") (class "Default")
      (node (ref "IC34") (pin "19") (pinfunction "19_19") (pintype "passive"))
      (node (ref "IC35") (pin "19") (pinfunction "19_19") (pintype "passive"))
      (node (ref "IC36") (pin "19") (pinfunction "19_19") (pintype "passive"))
      (node (ref "IC37") (pin "19") (pinfunction "19_19") (pintype "passive"))
    )
    (net (code "213") (name "Net-(IC34-Pad20)") (class "Default")
      (node (ref "IC34") (pin "20") (pinfunction "20_20") (pintype "passive"))
      (node (ref "IC35") (pin "20") (pinfunction "20_20") (pintype "passive"))
      (node (ref "IC36") (pin "20") (pinfunction "20_20") (pintype "passive"))
      (node (ref "IC37") (pin "20") (pinfunction "20_20") (pintype "passive"))
    )
    (net (code "214") (name "Net-(IC34-Pad21)") (class "Default")
      (node (ref "IC34") (pin "21") (pinfunction "21_21") (pintype "passive"))
      (node (ref "IC35") (pin "21") (pinfunction "21_21") (pintype "passive"))
      (node (ref "IC36") (pin "21") (pinfunction "21_21") (pintype "passive"))
      (node (ref "IC37") (pin "21") (pinfunction "21_21") (pintype "passive"))
    )
    (net (code "215") (name "Net-(IC34-Pad22)") (class "Default")
      (node (ref "IC34") (pin "22") (pinfunction "22_22") (pintype "passive"))
      (node (ref "IC35") (pin "22") (pinfunction "22_22") (pintype "passive"))
      (node (ref "IC36") (pin "22") (pinfunction "22_22") (pintype "passive"))
      (node (ref "IC37") (pin "22") (pinfunction "22_22") (pintype "passive"))
    )
    (net (code "216") (name "Net-(IC34-Pad23)") (class "Default")
      (node (ref "IC34") (pin "23") (pinfunction "23_23") (pintype "passive"))
      (node (ref "IC35") (pin "23") (pinfunction "23_23") (pintype "passive"))
      (node (ref "IC36") (pin "23") (pinfunction "23_23") (pintype "passive"))
      (node (ref "IC37") (pin "23") (pinfunction "23_23") (pintype "passive"))
    )
    (net (code "217") (name "Net-(IC34-Pad24)") (class "Default")
      (node (ref "IC34") (pin "24") (pinfunction "24_24") (pintype "passive"))
      (node (ref "IC35") (pin "24") (pinfunction "24_24") (pintype "passive"))
      (node (ref "IC36") (pin "24") (pinfunction "24_24") (pintype "passive"))
      (node (ref "IC37") (pin "24") (pinfunction "24_24") (pintype "passive"))
    )
    (net (code "218") (name "Net-(IC38-Pad1)") (class "Default")
      (node (ref "IC38") (pin "1") (pinfunction "1_1") (pintype "passive"))
      (node (ref "IC39") (pin "1") (pinfunction "1_1") (pintype "passive"))
      (node (ref "IC40") (pin "1") (pinfunction "1_1") (pintype "passive"))
      (node (ref "IC41") (pin "1") (pinfunction "1_1") (pintype "passive"))
    )
    (net (code "219") (name "Net-(IC38-Pad2)") (class "Default")
      (node (ref "IC38") (pin "2") (pinfunction "2_2") (pintype "passive"))
      (node (ref "IC39") (pin "2") (pinfunction "2_2") (pintype "passive"))
      (node (ref "IC40") (pin "2") (pinfunction "2_2") (pintype "passive"))
      (node (ref "IC41") (pin "2") (pinfunction "2_2") (pintype "passive"))
    )
    (net (code "220") (name "Net-(IC38-Pad3)") (class "Default")
      (node (ref "IC38") (pin "3") (pinfunction "3_3") (pintype "passive"))
      (node (ref "IC39") (pin "3") (pinfunction "3_3") (pintype "passive"))
      (node (ref "IC40") (pin "3") (pinfunction "3_3") (pintype "passive"))
      (node (ref "IC41") (pin "3") (pinfunction "3_3") (pintype "passive"))
    )
    (net (code "221") (name "Net-(IC38-Pad4)") (class "Default")
      (node (ref "IC38") (pin "4") (pinfunction "4_4") (pintype "passive"))
      (node (ref "IC39") (pin "4") (pinfunction "4_4") (pintype "passive"))
      (node (ref "IC40") (pin "4") (pinfunction "4_4") (pintype "passive"))
      (node (ref "IC41") (pin "4") (pinfunction "4_4") (pintype "passive"))
    )
    (net (code "222") (name "Net-(IC38-Pad5)") (class "Default")
      (node (ref "IC38") (pin "5") (pinfunction "5_5") (pintype "passive"))
      (node (ref "IC39") (pin "5") (pinfunction "5_5") (pintype "passive"))
      (node (ref "IC40") (pin "5") (pinfunction "5_5") (pintype "passive"))
      (node (ref "IC41") (pin "5") (pinfunction "5_5") (pintype "passive"))
    )
    (net (code "223") (name "Net-(IC38-Pad6)") (class "Default")
      (node (ref "IC38") (pin "6") (pinfunction "6_6") (pintype "passive"))
      (node (ref "IC39") (pin "6") (pinfunction "6_6") (pintype "passive"))
      (node (ref "IC40") (pin "6") (pinfunction "6_6") (pintype "passive"))
      (node (ref "IC41") (pin "6") (pinfunction "6_6") (pintype "passive"))
    )
    (net (code "224") (name "Net-(IC38-Pad7)") (class "Default")
      (node (ref "IC38") (pin "7") (pinfunction "7_7") (pintype "passive"))
      (node (ref "IC39") (pin "7") (pinfunction "7_7") (pintype "passive"))
      (node (ref "IC40") (pin "7") (pinfunction "7_7") (pintype "passive"))
      (node (ref "IC41") (pin "7") (pinfunction "7_7") (pintype "passive"))
    )
    (net (code "225") (name "Net-(IC38-Pad8)") (class "Default")
      (node (ref "IC38") (pin "8") (pinfunction "8_8") (pintype "passive"))
      (node (ref "IC39") (pin "8") (pinfunction "8_8") (pintype "passive"))
      (node (ref "IC40") (pin "8") (pinfunction "8_8") (pintype "passive"))
      (node (ref "IC41") (pin "8") (pinfunction "8_8") (pintype "passive"))
    )
    (net (code "226") (name "Net-(IC38-Pad9)") (class "Default")
      (node (ref "IC38") (pin "9") (pinfunction "9_9") (pintype "passive"))
      (node (ref "IC39") (pin "9") (pinfunction "9_9") (pintype "passive"))
      (node (ref "IC40") (pin "9") (pinfunction "9_9") (pintype "passive"))
      (node (ref "IC41") (pin "9") (pinfunction "9_9") (pintype "passive"))
    )
    (net (code "227") (name "Net-(IC38-Pad10)") (class "Default")
      (node (ref "IC38") (pin "10") (pinfunction "10_10") (pintype "passive"))
      (node (ref "IC39") (pin "10") (pinfunction "10_10") (pintype "passive"))
      (node (ref "IC40") (pin "10") (pinfunction "10_10") (pintype "passive"))
      (node (ref "IC41") (pin "10") (pinfunction "10_10") (pintype "passive"))
    )
    (net (code "228") (name "Net-(IC38-Pad11)") (class "Default")
      (node (ref "IC38") (pin "11") (pinfunction "11_11") (pintype "passive"))
      (node (ref "IC39") (pin "11") (pinfunction "11_11") (pintype "passive"))
      (node (ref "IC40") (pin "11") (pinfunction "11_11") (pintype "passive"))
      (node (ref "IC41") (pin "11") (pinfunction "11_11") (pintype "passive"))
    )
    (net (code "229") (name "Net-(IC38-Pad12)") (class "Default")
      (node (ref "IC38") (pin "12") (pinfunction "12_12") (pintype "passive"))
      (node (ref "IC39") (pin "12") (pinfunction "12_12") (pintype "passive"))
      (node (ref "IC40") (pin "12") (pinfunction "12_12") (pintype "passive"))
      (node (ref "IC41") (pin "12") (pinfunction "12_12") (pintype "passive"))
    )
    (net (code "230") (name "Net-(IC38-Pad13)") (class "Default")
      (node (ref "IC38") (pin "13") (pinfunction "13_13") (pintype "passive"))
      (node (ref "IC39") (pin "13") (pinfunction "13_13") (pintype "passive"))
      (node (ref "IC40") (pin "13") (pinfunction "13_13") (pintype "passive"))
      (node (ref "IC41") (pin "13") (pinfunction "13_13") (pintype "passive"))
    )
    (net (code "231") (name "Net-(IC38-Pad14)") (class "Default")
      (node (ref "IC38") (pin "14") (pinfunction "14_14") (pintype "passive"))
      (node (ref "IC39") (pin "14") (pinfunction "14_14") (pintype "passive"))
      (node (ref "IC40") (pin "14") (pinfunction "14_14") (pintype "passive"))
      (node (ref "IC41") (pin "14") (pinfunction "14_14") (pintype "passive"))
    )
    (net (code "232") (name "Net-(IC38-Pad15)") (class "Default")
      (node (ref "IC38") (pin "15") (pinfunction "15_15") (pintype "passive"))
      (node (ref "IC39") (pin "15") (pinfunction "15_15") (pintype "passive"))
      (node (ref "IC40") (pin "15") (pinfunction "15_15") (pintype "passive"))
      (node (ref "IC41") (pin "15") (pinfunction "15_15") (pintype "passive"))
    )
    (net (code "233") (name "Net-(IC38-Pad16)") (class "Default")
      (node (ref "IC38") (pin "16") (pinfunction "16_16") (pintype "passive"))
      (node (ref "IC39") (pin "16") (pinfunction "16_16") (pintype "passive"))
      (node (ref "IC40") (pin "16") (pinfunction "16_16") (pintype "passive"))
      (node (ref "IC41") (pin "16") (pinfunction "16_16") (pintype "passive"))
    )
    (net (code "234") (name "Net-(IC38-Pad17)") (class "Default")
      (node (ref "IC38") (pin "17") (pinfunction "17_17") (pintype "passive"))
      (node (ref "IC39") (pin "17") (pinfunction "17_17") (pintype "passive"))
      (node (ref "IC40") (pin "17") (pinfunction "17_17") (pintype "passive"))
      (node (ref "IC41") (pin "17") (pinfunction "17_17") (pintype "passive"))
    )
    (net (code "235") (name "Net-(IC38-Pad18)") (class "Default")
      (node (ref "IC38") (pin "18") (pinfunction "18_18") (pintype "passive"))
      (node (ref "IC39") (pin "18") (pinfunction "18_18") (pintype "passive"))
      (node (ref "IC40") (pin "18") (pinfunction "18_18") (pintype "passive"))
      (node (ref "IC41") (pin "18") (pinfunction "18_18") (pintype "passive"))
    )
    (net (code "236") (name "Net-(IC38-Pad19)") (class "Default")
      (node (ref "IC38") (pin "19") (pinfunction "19_19") (pintype "passive"))
      (node (ref "IC39") (pin "19") (pinfunction "19_19") (pintype "passive"))
      (node (ref "IC40") (pin "19") (pinfunction "19_19") (pintype "passive"))
      (node (ref "IC41") (pin "19") (pinfunction "19_19") (pintype "passive"))
    )
    (net (code "237") (name "Net-(IC38-Pad20)") (class "Default")
      (node (ref "IC38") (pin "20") (pinfunction "20_20") (pintype "passive"))
      (node (ref "IC39") (pin "20") (pinfunction "20_20") (pintype "passive"))
      (node (ref "IC40") (pin "20") (pinfunction "20_20") (pintype "passive"))
      (node (ref "IC41") (pin "20") (pinfunction "20_20") (pintype "passive"))
    )
    (net (code "238") (name "Net-(IC38-Pad21)") (class "Default")
      (node (ref "IC38") (pin "21") (pinfunction "21_21") (pintype "passive"))
      (node (ref "IC39") (pin "21") (pinfunction "21_21") (pintype "passive"))
      (node (ref "IC40") (pin "21") (pinfunction "21_21") (pintype "passive"))
      (node (ref "IC41") (pin "21") (pinfunction "21_21") (pintype "passive"))
    )
    (net (code "239") (name "Net-(IC38-Pad22)") (class "Default")
      (node (ref "IC38") (pin "22") (pinfunction "22_22") (pintype "passive"))
      (node (ref "IC39") (pin "22") (pinfunction "22_22") (pintype "passive"))
      (node (ref "IC40") (pin "22") (pinfunction "22_22") (pintype "passive"))
      (node (ref "IC41") (pin "22") (pinfunction "22_22") (pintype "passive"))
    )
    (net (code "240") (name "Net-(IC38-Pad23)") (class "Default")
      (node (ref "IC38") (pin "23") (pinfunction "23_23") (pintype "passive"))
      (node (ref "IC39") (pin "23") (pinfunction "23_23") (pintype "passive"))
      (node (ref "IC40") (pin "23") (pinfunction "23_23") (pintype "passive"))
      (node (ref "IC41") (pin "23") (pinfunction "23_23") (pintype "passive"))
    )
    (net (code "241") (name "Net-(IC38-Pad24)") (class "Default")
      (node (ref "IC38") (pin "24") (pinfunction "24_24") (pintype "passive"))
      (node (ref "IC39") (pin "24") (pinfunction "24_24") (pintype "passive"))
      (node (ref "IC40") (pin "24") (pinfunction "24_24") (pintype "passive"))
      (node (ref "IC41") (pin "24") (pinfunction "24_24") (pintype "passive"))
    )
    (net (code "242") (name "Net-(IC42-Pad1)") (class "Default")
      (node (ref "IC42") (pin "1") (pinfunction "1_1") (pintype "passive"))
      (node (ref "IC43") (pin "1") (pinfunction "1_1") (pintype "passive"))
      (node (ref "IC44") (pin "1") (pinfunction "1_1") (pintype "passive"))
      (node (ref "IC45") (pin "1") (pinfunction "1_1") (pintype "passive"))
    )
    (net (code "243") (name "Net-(IC42-Pad2)") (class "Default")
      (node (ref "IC42") (pin "2") (pinfunction "2_2") (pintype "passive"))
      (node (ref "IC43") (pin "2") (pinfunction "2_2") (pintype "passive"))
      (node (ref "IC44") (pin "2") (pinfunction "2_2") (pintype "passive"))
      (node (ref "IC45") (pin "2") (pinfunction "2_2") (pintype "passive"))
    )
    (net (code "244") (name "Net-(IC42-Pad3)") (class "Default")
      (node (ref "IC42") (pin "3") (pinfunction "3_3") (pintype "passive"))
      (node (ref "IC43") (pin "3") (pinfunction "3_3") (pintype "passive"))
      (node (ref "IC44") (pin "3") (pinfunction "3_3") (pintype "passive"))
      (node (ref "IC45") (pin "3") (pinfunction "3_3") (pintype "passive"))
    )
    (net (code "245") (name "Net-(IC42-Pad4)") (class "Default")
      (node (ref "IC42") (pin "4") (pinfunction "4_4") (pintype "passive"))
      (node (ref "IC43") (pin "4") (pinfunction "4_4") (pintype "passive"))
      (node (ref "IC44") (pin "4") (pinfunction "4_4") (pintype "passive"))
      (node (ref "IC45") (pin "4") (pinfunction "4_4") (pintype "passive"))
    )
    (net (code "246") (name "Net-(IC42-Pad5)") (class "Default")
      (node (ref "IC42") (pin "5") (pinfunction "5_5") (pintype "passive"))
      (node (ref "IC43") (pin "5") (pinfunction "5_5") (pintype "passive"))
      (node (ref "IC44") (pin "5") (pinfunction "5_5") (pintype "passive"))
      (node (ref "IC45") (pin "5") (pinfunction "5_5") (pintype "passive"))
    )
    (net (code "247") (name "Net-(IC42-Pad6)") (class "Default")
      (node (ref "IC42") (pin "6") (pinfunction "6_6") (pintype "passive"))
      (node (ref "IC43") (pin "6") (pinfunction "6_6") (pintype "passive"))
      (node (ref "IC44") (pin "6") (pinfunction "6_6") (pintype "passive"))
      (node (ref "IC45") (pin "6") (pinfunction "6_6") (pintype "passive"))
    )
    (net (code "248") (name "Net-(IC42-Pad7)") (class "Default")
      (node (ref "IC42") (pin "7") (pinfunction "7_7") (pintype "passive"))
      (node (ref "IC43") (pin "7") (pinfunction "7_7") (pintype "passive"))
      (node (ref "IC44") (pin "7") (pinfunction "7_7") (pintype "passive"))
      (node (ref "IC45") (pin "7") (pinfunction "7_7") (pintype "passive"))
    )
    (net (code "249") (name "Net-(IC42-Pad8)") (class "Default")
      (node (ref "IC42") (pin "8") (pinfunction "8_8") (pintype "passive"))
      (node (ref "IC43") (pin "8") (pinfunction "8_8") (pintype "passive"))
      (node (ref "IC44") (pin "8") (pinfunction "8_8") (pintype "passive"))
      (node (ref "IC45") (pin "8") (pinfunction "8_8") (pintype "passive"))
    )
    (net (code "250") (name "Net-(IC42-Pad9)") (class "Default")
      (node (ref "IC42") (pin "9") (pinfunction "9_9") (pintype "passive"))
      (node (ref "IC43") (pin "9") (pinfunction "9_9") (pintype "passive"))
      (node (ref "IC44") (pin "9") (pinfunction "9_9") (pintype "passive"))
      (node (ref "IC45") (pin "9") (pinfunction "9_9") (pintype "passive"))
    )
    (net (code "251") (name "Net-(IC42-Pad10)") (class "Default")
      (node (ref "IC42") (pin "10") (pinfunction "10_10") (pintype "passive"))
      (node (ref "IC43") (pin "10") (pinfunction "10_10") (pintype "passive"))
      (node (ref "IC44") (pin "10") (pinfunction "10_10") (pintype "passive"))
      (node (ref "IC45") (pin "10") (pinfunction "10_10") (pintype "passive"))
    )
    (net (code "252") (name "Net-(IC42-Pad11)") (class "Default")
      (node (ref "IC42") (pin "11") (pinfunction "11_11") (pintype "passive"))
      (node (ref "IC43") (pin "11") (pinfunction "11_11") (pintype "passive"))
      (node (ref "IC44") (pin "11") (pinfunction "11_11") (pintype "passive"))
      (node (ref "IC45") (pin "11") (pinfunction "11_11") (pintype "passive"))
    )
    (net (code "253") (name "Net-(IC42-Pad12)") (class "Default")
      (node (ref "IC42") (pin "12") (pinfunction "12_12") (pintype "passive"))
      (node (ref "IC43") (pin "12") (pinfunction "12_12") (pintype "passive"))
      (node (ref "IC44") (pin "12") (pinfunction "12_12") (pintype "passive"))
      (node (ref "IC45") (pin "12") (pinfunction "12_12") (pintype "passive"))
    )
    (net (code "254") (name "Net-(IC42-Pad13)") (class "Default")
      (node (ref "IC42") (pin "13") (pinfunction "13_13") (pintype "passive"))
      (node (ref "IC43") (pin "13") (pinfunction "13_13") (pintype "passive"))
      (node (ref "IC44") (pin "13") (pinfunction "13_13") (pintype "passive"))
      (node (ref "IC45") (pin "13") (pinfunction "13_13") (pintype "passive"))
    )
    (net (code "255") (name "Net-(IC42-Pad14)") (class "Default")
      (node (ref "IC42") (pin "14") (pinfunction "14_14") (pintype "passive"))
      (node (ref "IC43") (pin "14") (pinfunction "14_14") (pintype "passive"))
      (node (ref "IC44") (pin "14") (pinfunction "14_14") (pintype "passive"))
      (node (ref "IC45") (pin "14") (pinfunction "14_14") (pintype "passive"))
    )
    (net (code "256") (name "Net-(IC42-Pad15)") (class "Default")
      (node (ref "IC42") (pin "15") (pinfunction "15_15") (pintype "passive"))
      (node (ref "IC43") (pin "15") (pinfunction "15_15") (pintype "passive"))
      (node (ref "IC44") (pin "15") (pinfunction "15_15") (pintype "passive"))
      (node (ref "IC45") (pin "15") (pinfunction "15_15") (pintype "passive"))
    )
    (net (code "257") (name "Net-(IC42-Pad16)") (class "Default")
      (node (ref "IC42") (pin "16") (pinfunction "16_16") (pintype "passive"))
      (node (ref "IC43") (pin "16") (pinfunction "16_16") (pintype "passive"))
      (node (ref "IC44") (pin "16") (pinfunction "16_16") (pintype "passive"))
      (node (ref "IC45") (pin "16") (pinfunction "16_16") (pintype "passive"))
    )
    (net (code "258") (name "Net-(IC42-Pad17)") (class "Default")
      (node (ref "IC42") (pin "17") (pinfunction "17_17") (pintype "passive"))
      (node (ref "IC43") (pin "17") (pinfunction "17_17") (pintype "passive"))
      (node (ref "IC44") (pin "17") (pinfunction "17_17") (pintype "passive"))
      (node (ref "IC45") (pin "17") (pinfunction "17_17") (pintype "passive"))
    )
    (net (code "259") (name "Net-(IC42-Pad18)") (class "Default")
      (node (ref "IC42") (pin "18") (pinfunction "18_18") (pintype "passive"))
      (node (ref "IC43") (pin "18") (pinfunction "18_18") (pintype "passive"))
      (node (ref "IC44") (pin "18") (pinfunction "18_18") (pintype "passive"))
      (node (ref "IC45") (pin "18") (pinfunction "18_18") (pintype "passive"))
    )
    (net (code "260") (name "Net-(IC42-Pad19)") (class "Default")
      (node (ref "IC42") (pin "19") (pinfunction "19_19") (pintype "passive"))
      (node (ref "IC43") (pin "19") (pinfunction "19_19") (pintype "passive"))
      (node (ref "IC44") (pin "19") (pinfunction "19_19") (pintype "passive"))
      (node (ref "IC45") (pin "19") (pinfunction "19_19") (pintype "passive"))
    )
    (net (code "261") (name "Net-(IC42-Pad20)") (class "Default")
      (node (ref "IC42") (pin "20") (pinfunction "20_20") (pintype "passive"))
      (node (ref "IC43") (pin "20") (pinfunction "20_20") (pintype "passive"))
      (node (ref "IC44") (pin "20") (pinfunction "20_20") (pintype "passive"))
      (node (ref "IC45") (pin "20") (pinfunction "20_20") (pintype "passive"))
    )
    (net (code "262") (name "Net-(IC42-Pad21)") (class "Default")
      (node (ref "IC42") (pin "21") (pinfunction "21_21") (pintype "passive"))
      (node (ref "IC43") (pin "21") (pinfunction "21_21") (pintype "passive"))
      (node (ref "IC44") (pin "21") (pinfunction "21_21") (pintype "passive"))
      (node (ref "IC45") (pin "21") (pinfunction "21_21") (pintype "passive"))
    )
    (net (code "263") (name "Net-(IC42-Pad22)") (class "Default")
      (node (ref "IC42") (pin "22") (pinfunction "22_22") (pintype "passive"))
      (node (ref "IC43") (pin "22") (pinfunction "22_22") (pintype "passive"))
      (node (ref "IC44") (pin "22") (pinfunction "22_22") (pintype "passive"))
      (node (ref "IC45") (pin "22") (pinfunction "22_22") (pintype "passive"))
    )
    (net (code "264") (name "Net-(IC42-Pad23)") (class "Default")
      (node (ref "IC42") (pin "23") (pinfunction "23_23") (pintype "passive"))
      (node (ref "IC43") (pin "23") (pinfunction "23_23") (pintype "passive"))
      (node (ref "IC44") (pin "23") (pinfunction "23_23") (pintype "passive"))
      (node (ref "IC45") (pin "23") (pinfunction "23_23") (pintype "passive"))
    )
    (net (code "265") (name "Net-(IC42-Pad24)") (class "Default")
      (node (ref "IC42") (pin "24") (pinfunction "24_24") (pintype "passive"))
      (node (ref "IC43") (pin "24") (pinfunction "24_24") (pintype "passive"))
      (node (ref "IC44") (pin "24") (pinfunction "24_24") (pintype "passive"))
      (node (ref "IC45") (pin "24") (pinfunction "24_24") (pintype "passive"))
    )
    (net (code "266") (name "Net-(IC46-Pad1)") (class "Default")
      (node (ref "IC46") (pin "1") (pinfunction "1_1") (pintype "passive"))
      (node (ref "IC47") (pin "1") (pinfunction "1_1") (pintype "passive"))
      (node (ref "IC48") (pin "1") (pinfunction "1_1") (pintype "passive"))
      (node (ref "IC49") (pin "1") (pinfunction "1_1") (pintype "passive"))
    )
    (net (code "267") (name "Net-(IC46-Pad2)") (class "Default")
      (node (ref "IC46") (pin "2") (pinfunction "2_2") (pintype "passive"))
      (node (ref "IC47") (pin "2") (pinfunction "2_2") (pintype "passive"))
      (node (ref "IC48") (pin "2") (pinfunction "2_2") (pintype "passive"))
      (node (ref "IC49") (pin "2") (pinfunction "2_2") (pintype "passive"))
    )
    (net (code "268") (name "Net-(IC46-Pad3)") (class "Default")
      (node (ref "IC46") (pin "3") (pinfunction "3_3") (pintype "passive"))
      (node (ref "IC47") (pin "3") (pinfunction "3_3") (pintype "passive"))
      (node (ref "IC48") (pin "3") (pinfunction "3_3") (pintype "passive"))
      (node (ref "IC49") (pin "3") (pinfunction "3_3") (pintype "passive"))
    )
    (net (code "269") (name "Net-(IC46-Pad4)") (class "Default")
      (node (ref "IC46") (pin "4") (pinfunction "4_4") (pintype "passive"))
      (node (ref "IC47") (pin "4") (pinfunction "4_4") (pintype "passive"))
      (node (ref "IC48") (pin "4") (pinfunction "4_4") (pintype "passive"))
      (node (ref "IC49") (pin "4") (pinfunction "4_4") (pintype "passive"))
    )
    (net (code "270") (name "Net-(IC46-Pad5)") (class "Default")
      (node (ref "IC46") (pin "5") (pinfunction "5_5") (pintype "passive"))
      (node (ref "IC47") (pin "5") (pinfunction "5_5") (pintype "passive"))
      (node (ref "IC48") (pin "5") (pinfunction "5_5") (pintype "passive"))
      (node (ref "IC49") (pin "5") (pinfunction "5_5") (pintype "passive"))
    )
    (net (code "271") (name "Net-(IC46-Pad6)") (class "Default")
      (node (ref "IC46") (pin "6") (pinfunction "6_6") (pintype "passive"))
      (node (ref "IC47") (pin "6") (pinfunction "6_6") (pintype "passive"))
      (node (ref "IC48") (pin "6") (pinfunction "6_6") (pintype "passive"))
      (node (ref "IC49") (pin "6") (pinfunction "6_6") (pintype "passive"))
    )
    (net (code "272") (name "Net-(IC46-Pad7)") (class "Default")
      (node (ref "IC46") (pin "7") (pinfunction "7_7") (pintype "passive"))
      (node (ref "IC47") (pin "7") (pinfunction "7_7") (pintype "passive"))
      (node (ref "IC48") (pin "7") (pinfunction "7_7") (pintype "passive"))
      (node (ref "IC49") (pin "7") (pinfunction "7_7") (pintype "passive"))
    )
    (net (code "273") (name "Net-(IC46-Pad8)") (class "Default")
      (node (ref "IC46") (pin "8") (pinfunction "8_8") (pintype "passive"))
      (node (ref "IC47") (pin "8") (pinfunction "8_8") (pintype "passive"))
      (node (ref "IC48") (pin "8") (pinfunction "8_8") (pintype "passive"))
      (node (ref "IC49") (pin "8") (pinfunction "8_8") (pintype "passive"))
    )
    (net (code "274") (name "Net-(IC46-Pad9)") (class "Default")
      (node (ref "IC46") (pin "9") (pinfunction "9_9") (pintype "passive"))
      (node (ref "IC47") (pin "9") (pinfunction "9_9") (pintype "passive"))
      (node (ref "IC48") (pin "9") (pinfunction "9_9") (pintype "passive"))
      (node (ref "IC49") (pin "9") (pinfunction "9_9") (pintype "passive"))
    )
    (net (code "275") (name "Net-(IC46-Pad10)") (class "Default")
      (node (ref "IC46") (pin "10") (pinfunction "10_10") (pintype "passive"))
      (node (ref "IC47") (pin "10") (pinfunction "10_10") (pintype "passive"))
      (node (ref "IC48") (pin "10") (pinfunction "10_10") (pintype "passive"))
      (node (ref "IC49") (pin "10") (pinfunction "10_10") (pintype "passive"))
    )
    (net (code "276") (name "Net-(IC46-Pad11)") (class "Default")
      (node (ref "IC46") (pin "11") (pinfunction "11_11") (pintype "passive"))
      (node (ref "IC47") (pin "11") (pinfunction "11_11") (pintype "passive"))
      (node (ref "IC48") (pin "11") (pinfunction "11_11") (pintype "passive"))
      (node (ref "IC49") (pin "11") (pinfunction "11_11") (pintype "passive"))
    )
    (net (code "277") (name "Net-(IC46-Pad12)") (class "Default")
      (node (ref "IC46") (pin "12") (pinfunction "12_12") (pintype "passive"))
      (node (ref "IC47") (pin "12") (pinfunction "12_12") (pintype "passive"))
      (node (ref "IC48") (pin "12") (pinfunction "12_12") (pintype "passive"))
      (node (ref "IC49") (pin "12") (pinfunction "12_12") (pintype "passive"))
    )
    (net (code "278") (name "Net-(IC46-Pad13)") (class "Default")
      (node (ref "IC46") (pin "13") (pinfunction "13_13") (pintype "passive"))
      (node (ref "IC47") (pin "13") (pinfunction "13_13") (pintype "passive"))
      (node (ref "IC48") (pin "13") (pinfunction "13_13") (pintype "passive"))
      (node (ref "IC49") (pin "13") (pinfunction "13_13") (pintype "passive"))
    )
    (net (code "279") (name "Net-(IC46-Pad14)") (class "Default")
      (node (ref "IC46") (pin "14") (pinfunction "14_14") (pintype "passive"))
      (node (ref "IC47") (pin "14") (pinfunction "14_14") (pintype "passive"))
      (node (ref "IC48") (pin "14") (pinfunction "14_14") (pintype "passive"))
      (node (ref "IC49") (pin "14") (pinfunction "14_14") (pintype "passive"))
    )
    (net (code "280") (name "Net-(IC46-Pad15)") (class "Default")
      (node (ref "IC46") (pin "15") (pinfunction "15_15") (pintype "passive"))
      (node (ref "IC47") (pin "15") (pinfunction "15_15") (pintype "passive"))
      (node (ref "IC48") (pin "15") (pinfunction "15_15") (pintype "passive"))
      (node (ref "IC49") (pin "15") (pinfunction "15_15") (pintype "passive"))
    )
    (net (code "281") (name "Net-(IC46-Pad16)") (class "Default")
      (node (ref "IC46") (pin "16") (pinfunction "16_16") (pintype "passive"))
      (node (ref "IC47") (pin "16") (pinfunction "16_16") (pintype "passive"))
      (node (ref "IC48") (pin "16") (pinfunction "16_16") (pintype "passive"))
      (node (ref "IC49") (pin "16") (pinfunction "16_16") (pintype "passive"))
    )
    (net (code "282") (name "Net-(IC46-Pad17)") (class "Default")
      (node (ref "IC46") (pin "17") (pinfunction "17_17") (pintype "passive"))
      (node (ref "IC47") (pin "17") (pinfunction "17_17") (pintype "passive"))
      (node (ref "IC48") (pin "17") (pinfunction "17_17") (pintype "passive"))
      (node (ref "IC49") (pin "17") (pinfunction "17_17") (pintype "passive"))
    )
    (net (code "283") (name "Net-(IC46-Pad18)") (class "Default")
      (node (ref "IC46") (pin "18") (pinfunction "18_18") (pintype "passive"))
      (node (ref "IC47") (pin "18") (pinfunction "18_18") (pintype "passive"))
      (node (ref "IC48") (pin "18") (pinfunction "18_18") (pintype "passive"))
      (node (ref "IC49") (pin "18") (pinfunction "18_18") (pintype "passive"))
    )
    (net (code "284") (name "Net-(IC46-Pad19)") (class "Default")
      (node (ref "IC46") (pin "19") (pinfunction "19_19") (pintype "passive"))
      (node (ref "IC47") (pin "19") (pinfunction "19_19") (pintype "passive"))
      (node (ref "IC48") (pin "19") (pinfunction "19_19") (pintype "passive"))
      (node (ref "IC49") (pin "19") (pinfunction "19_19") (pintype "passive"))
    )
    (net (code "285") (name "Net-(IC46-Pad20)") (class "Default")
      (node (ref "IC46") (pin "20") (pinfunction "20_20") (pintype "passive"))
      (node (ref "IC47") (pin "20") (pinfunction "20_20") (pintype "passive"))
      (node (ref "IC48") (pin "20") (pinfunction "20_20") (pintype "passive"))
      (node (ref "IC49") (pin "20") (pinfunction "20_20") (pintype "passive"))
    )
    (net (code "286") (name "Net-(IC46-Pad21)") (class "Default")
      (node (ref "IC46") (pin "21") (pinfunction "21_21") (pintype "passive"))
      (node (ref "IC47") (pin "21") (pinfunction "21_21") (pintype "passive"))
      (node (ref "IC48") (pin "21") (pinfunction "21_21") (pintype "passive"))
      (node (ref "IC49") (pin "21") (pinfunction "21_21") (pintype "passive"))
    )
    (net (code "287") (name "Net-(IC46-Pad22)") (class "Default")
      (node (ref "IC46") (pin "22") (pinfunction "22_22") (pintype "passive"))
      (node (ref "IC47") (pin "22") (pinfunction "22_22") (pintype "passive"))
      (node (ref "IC48") (pin "22") (pinfunction "22_22") (pintype "passive"))
      (node (ref "IC49") (pin "22") (pinfunction "22_22") (pintype "passive"))
    )
    (net (code "288") (name "Net-(IC46-Pad23)") (class "Default")
      (node (ref "IC46") (pin "23") (pinfunction "23_23") (pintype "passive"))
      (node (ref "IC47") (pin "23") (pinfunction "23_23") (pintype "passive"))
      (node (ref "IC48") (pin "23") (pinfunction "23_23") (pintype "passive"))
      (node (ref "IC49") (pin "23") (pinfunction "23_23") (pintype "passive"))
    )
    (net (code "289") (name "Net-(IC46-Pad24)") (class "Default")
      (node (ref "IC46") (pin "24") (pinfunction "24_24") (pintype "passive"))
      (node (ref "IC47") (pin "24") (pinfunction "24_24") (pintype "passive"))
      (node (ref "IC48") (pin "24") (pinfunction "24_24") (pintype "passive"))
      (node (ref "IC49") (pin "24") (pinfunction "24_24") (pintype "passive"))
    )
    (net (code "290") (name "Net-(IC50-Pad1)") (class "Default")
      (node (ref "IC50") (pin "1") (pinfunction "1_1") (pintype "passive"))
      (node (ref "IC51") (pin "1") (pinfunction "1_1") (pintype "passive"))
      (node (ref "IC52") (pin "1") (pinfunction "1_1") (pintype "passive"))
      (node (ref "IC53") (pin "1") (pinfunction "1_1") (pintype "passive"))
    )
    (net (code "291") (name "Net-(IC50-Pad2)") (class "Default")
      (node (ref "IC50") (pin "2") (pinfunction "2_2") (pintype "passive"))
      (node (ref "IC51") (pin "2") (pinfunction "2_2") (pintype "passive"))
      (node (ref "IC52") (pin "2") (pinfunction "2_2") (pintype "passive"))
      (node (ref "IC53") (pin "2") (pinfunction "2_2") (pintype "passive"))
    )
    (net (code "292") (name "Net-(IC50-Pad3)") (class "Default")
      (node (ref "IC50") (pin "3") (pinfunction "3_3") (pintype "passive"))
      (node (ref "IC51") (pin "3") (pinfunction "3_3") (pintype "passive"))
      (node (ref "IC52") (pin "3") (pinfunction "3_3") (pintype "passive"))
      (node (ref "IC53") (pin "3") (pinfunction "3_3") (pintype "passive"))
    )
    (net (code "293") (name "Net-(IC50-Pad4)") (class "Default")
      (node (ref "IC50") (pin "4") (pinfunction "4_4") (pintype "passive"))
      (node (ref "IC51") (pin "4") (pinfunction "4_4") (pintype "passive"))
      (node (ref "IC52") (pin "4") (pinfunction "4_4") (pintype "passive"))
      (node (ref "IC53") (pin "4") (pinfunction "4_4") (pintype "passive"))
    )
    (net (code "294") (name "Net-(IC50-Pad5)") (class "Default")
      (node (ref "IC50") (pin "5") (pinfunction "5_5") (pintype "passive"))
      (node (ref "IC51") (pin "5") (pinfunction "5_5") (pintype "passive"))
      (node (ref "IC52") (pin "5") (pinfunction "5_5") (pintype "passive"))
      (node (ref "IC53") (pin "5") (pinfunction "5_5") (pintype "passive"))
    )
    (net (code "295") (name "Net-(IC50-Pad6)") (class "Default")
      (node (ref "IC50") (pin "6") (pinfunction "6_6") (pintype "passive"))
      (node (ref "IC51") (pin "6") (pinfunction "6_6") (pintype "passive"))
      (node (ref "IC52") (pin "6") (pinfunction "6_6") (pintype "passive"))
      (node (ref "IC53") (pin "6") (pinfunction "6_6") (pintype "passive"))
    )
    (net (code "296") (name "Net-(IC50-Pad7)") (class "Default")
      (node (ref "IC50") (pin "7") (pinfunction "7_7") (pintype "passive"))
      (node (ref "IC51") (pin "7") (pinfunction "7_7") (pintype "passive"))
      (node (ref "IC52") (pin "7") (pinfunction "7_7") (pintype "passive"))
      (node (ref "IC53") (pin "7") (pinfunction "7_7") (pintype "passive"))
    )
    (net (code "297") (name "Net-(IC50-Pad8)") (class "Default")
      (node (ref "IC50") (pin "8") (pinfunction "8_8") (pintype "passive"))
      (node (ref "IC51") (pin "8") (pinfunction "8_8") (pintype "passive"))
      (node (ref "IC52") (pin "8") (pinfunction "8_8") (pintype "passive"))
      (node (ref "IC53") (pin "8") (pinfunction "8_8") (pintype "passive"))
    )
    (net (code "298") (name "Net-(IC50-Pad9)") (class "Default")
      (node (ref "IC50") (pin "9") (pinfunction "9_9") (pintype "passive"))
      (node (ref "IC51") (pin "9") (pinfunction "9_9") (pintype "passive"))
      (node (ref "IC52") (pin "9") (pinfunction "9_9") (pintype "passive"))
      (node (ref "IC53") (pin "9") (pinfunction "9_9") (pintype "passive"))
    )
    (net (code "299") (name "Net-(IC50-Pad10)") (class "Default")
      (node (ref "IC50") (pin "10") (pinfunction "10_10") (pintype "passive"))
      (node (ref "IC51") (pin "10") (pinfunction "10_10") (pintype "passive"))
      (node (ref "IC52") (pin "10") (pinfunction "10_10") (pintype "passive"))
      (node (ref "IC53") (pin "10") (pinfunction "10_10") (pintype "passive"))
    )
    (net (code "300") (name "Net-(IC50-Pad11)") (class "Default")
      (node (ref "IC50") (pin "11") (pinfunction "11_11") (pintype "passive"))
      (node (ref "IC51") (pin "11") (pinfunction "11_11") (pintype "passive"))
      (node (ref "IC52") (pin "11") (pinfunction "11_11") (pintype "passive"))
      (node (ref "IC53") (pin "11") (pinfunction "11_11") (pintype "passive"))
    )
    (net (code "301") (name "Net-(IC50-Pad12)") (class "Default")
      (node (ref "IC50") (pin "12") (pinfunction "12_12") (pintype "passive"))
      (node (ref "IC51") (pin "12") (pinfunction "12_12") (pintype "passive"))
      (node (ref "IC52") (pin "12") (pinfunction "12_12") (pintype "passive"))
      (node (ref "IC53") (pin "12") (pinfunction "12_12") (pintype "passive"))
    )
    (net (code "302") (name "Net-(IC50-Pad13)") (class "Default")
      (node (ref "IC50") (pin "13") (pinfunction "13_13") (pintype "passive"))
      (node (ref "IC51") (pin "13") (pinfunction "13_13") (pintype "passive"))
      (node (ref "IC52") (pin "13") (pinfunction "13_13") (pintype "passive"))
      (node (ref "IC53") (pin "13") (pinfunction "13_13") (pintype "passive"))
    )
    (net (code "303") (name "Net-(IC50-Pad14)") (class "Default")
      (node (ref "IC50") (pin "14") (pinfunction "14_14") (pintype "passive"))
      (node (ref "IC51") (pin "14") (pinfunction "14_14") (pintype "passive"))
      (node (ref "IC52") (pin "14") (pinfunction "14_14") (pintype "passive"))
      (node (ref "IC53") (pin "14") (pinfunction "14_14") (pintype "passive"))
    )
    (net (code "304") (name "Net-(IC50-Pad15)") (class "Default")
      (node (ref "IC50") (pin "15") (pinfunction "15_15") (pintype "passive"))
      (node (ref "IC51") (pin "15") (pinfunction "15_15") (pintype "passive"))
      (node (ref "IC52") (pin "15") (pinfunction "15_15") (pintype "passive"))
      (node (ref "IC53") (pin "15") (pinfunction "15_15") (pintype "passive"))
    )
    (net (code "305") (name "Net-(IC50-Pad16)") (class "Default")
      (node (ref "IC50") (pin "16") (pinfunction "16_16") (pintype "passive"))
      (node (ref "IC51") (pin "16") (pinfunction "16_16") (pintype "passive"))
      (node (ref "IC52") (pin "16") (pinfunction "16_16") (pintype "passive"))
      (node (ref "IC53") (pin "16") (pinfunction "16_16") (pintype "passive"))
    )
    (net (code "306") (name "Net-(IC50-Pad17)") (class "Default")
      (node (ref "IC50") (pin "17") (pinfunction "17_17") (pintype "passive"))
      (node (ref "IC51") (pin "17") (pinfunction "17_17") (pintype "passive"))
      (node (ref "IC52") (pin "17") (pinfunction "17_17") (pintype "passive"))
      (node (ref "IC53") (pin "17") (pinfunction "17_17") (pintype "passive"))
    )
    (net (code "307") (name "Net-(IC50-Pad18)") (class "Default")
      (node (ref "IC50") (pin "18") (pinfunction "18_18") (pintype "passive"))
      (node (ref "IC51") (pin "18") (pinfunction "18_18") (pintype "passive"))
      (node (ref "IC52") (pin "18") (pinfunction "18_18") (pintype "passive"))
      (node (ref "IC53") (pin "18") (pinfunction "18_18") (pintype "passive"))
    )
    (net (code "308") (name "Net-(IC50-Pad19)") (class "Default")
      (node (ref "IC50") (pin "19") (pinfunction "19_19") (pintype "passive"))
      (node (ref "IC51") (pin "19") (pinfunction "19_19") (pintype "passive"))
      (node (ref "IC52") (pin "19") (pinfunction "19_19") (pintype "passive"))
      (node (ref "IC53") (pin "19") (pinfunction "19_19") (pintype "passive"))
    )
    (net (code "309") (name "Net-(IC50-Pad20)") (class "Default")
      (node (ref "IC50") (pin "20") (pinfunction "20_20") (pintype "passive"))
      (node (ref "IC51") (pin "20") (pinfunction "20_20") (pintype "passive"))
      (node (ref "IC52") (pin "20") (pinfunction "20_20") (pintype "passive"))
      (node (ref "IC53") (pin "20") (pinfunction "20_20") (pintype "passive"))
    )
    (net (code "310") (name "Net-(IC50-Pad21)") (class "Default")
      (node (ref "IC50") (pin "21") (pinfunction "21_21") (pintype "passive"))
      (node (ref "IC51") (pin "21") (pinfunction "21_21") (pintype "passive"))
      (node (ref "IC52") (pin "21") (pinfunction "21_21") (pintype "passive"))
      (node (ref "IC53") (pin "21") (pinfunction "21_21") (pintype "passive"))
    )
    (net (code "311") (name "Net-(IC50-Pad22)") (class "Default")
      (node (ref "IC50") (pin "22") (pinfunction "22_22") (pintype "passive"))
      (node (ref "IC51") (pin "22") (pinfunction "22_22") (pintype "passive"))
      (node (ref "IC52") (pin "22") (pinfunction "22_22") (pintype "passive"))
      (node (ref "IC53") (pin "22") (pinfunction "22_22") (pintype "passive"))
    )
    (net (code "312") (name "Net-(IC50-Pad23)") (class "Default")
      (node (ref "IC50") (pin "23") (pinfunction "23_23") (pintype "passive"))
      (node (ref "IC51") (pin "23") (pinfunction "23_23") (pintype "passive"))
      (node (ref "IC52") (pin "23") (pinfunction "23_23") (pintype "passive"))
      (node (ref "IC53") (pin "23") (pinfunction "23_23") (pintype "passive"))
    )
    (net (code "313") (name "Net-(IC50-Pad24)") (class "Default")
      (node (ref "IC50") (pin "24") (pinfunction "24_24") (pintype "passive"))
      (node (ref "IC51") (pin "24") (pinfunction "24_24") (pintype "passive"))
      (node (ref "IC52") (pin "24") (pinfunction "24_24") (pintype "passive"))
      (node (ref "IC53") (pin "24") (pinfunction "24_24") (pintype "passive"))
    )
    (net (code "314") (name "Net-(IC54-Pad1)") (class "Default")
      (node (ref "IC54") (pin "1") (pinfunction "1_1") (pintype "passive"))
      (node (ref "IC55") (pin "1") (pinfunction "1_1") (pintype "passive"))
      (node (ref "IC56") (pin "1") (pinfunction "1_1") (pintype "passive"))
      (node (ref "IC57") (pin "1") (pinfunction "1_1") (pintype "passive"))
    )
    (net (code "315") (name "Net-(IC54-Pad2)") (class "Default")
      (node (ref "IC54") (pin "2") (pinfunction "2_2") (pintype "passive"))
      (node (ref "IC55") (pin "2") (pinfunction "2_2") (pintype "passive"))
      (node (ref "IC56") (pin "2") (pinfunction "2_2") (pintype "passive"))
      (node (ref "IC57") (pin "2") (pinfunction "2_2") (pintype "passive"))
    )
    (net (code "316") (name "Net-(IC54-Pad3)") (class "Default")
      (node (ref "IC54") (pin "3") (pinfunction "3_3") (pintype "passive"))
      (node (ref "IC55") (pin "3") (pinfunction "3_3") (pintype "passive"))
      (node (ref "IC56") (pin "3") (pinfunction "3_3") (pintype "passive"))
      (node (ref "IC57") (pin "3") (pinfunction "3_3") (pintype "passive"))
    )
    (net (code "317") (name "Net-(IC54-Pad4)") (class "Default")
      (node (ref "IC54") (pin "4") (pinfunction "4_4") (pintype "passive"))
      (node (ref "IC55") (pin "4") (pinfunction "4_4") (pintype "passive"))
      (node (ref "IC56") (pin "4") (pinfunction "4_4") (pintype "passive"))
      (node (ref "IC57") (pin "4") (pinfunction "4_4") (pintype "passive"))
    )
    (net (code "318") (name "Net-(IC54-Pad5)") (class "Default")
      (node (ref "IC54") (pin "5") (pinfunction "5_5") (pintype "passive"))
      (node (ref "IC55") (pin "5") (pinfunction "5_5") (pintype "passive"))
      (node (ref "IC56") (pin "5") (pinfunction "5_5") (pintype "passive"))
      (node (ref "IC57") (pin "5") (pinfunction "5_5") (pintype "passive"))
    )
    (net (code "319") (name "Net-(IC54-Pad6)") (class "Default")
      (node (ref "IC54") (pin "6") (pinfunction "6_6") (pintype "passive"))
      (node (ref "IC55") (pin "6") (pinfunction "6_6") (pintype "passive"))
      (node (ref "IC56") (pin "6") (pinfunction "6_6") (pintype "passive"))
      (node (ref "IC57") (pin "6") (pinfunction "6_6") (pintype "passive"))
    )
    (net (code "320") (name "Net-(IC54-Pad7)") (class "Default")
      (node (ref "IC54") (pin "7") (pinfunction "7_7") (pintype "passive"))
      (node (ref "IC55") (pin "7") (pinfunction "7_7") (pintype "passive"))
      (node (ref "IC56") (pin "7") (pinfunction "7_7") (pintype "passive"))
      (node (ref "IC57") (pin "7") (pinfunction "7_7") (pintype "passive"))
    )
    (net (code "321") (name "Net-(IC54-Pad8)") (class "Default")
      (node (ref "IC54") (pin "8") (pinfunction "8_8") (pintype "passive"))
      (node (ref "IC55") (pin "8") (pinfunction "8_8") (pintype "passive"))
      (node (ref "IC56") (pin "8") (pinfunction "8_8") (pintype "passive"))
      (node (ref "IC57") (pin "8") (pinfunction "8_8") (pintype "passive"))
    )
    (net (code "322") (name "Net-(IC54-Pad9)") (class "Default")
      (node (ref "IC54") (pin "9") (pinfunction "9_9") (pintype "passive"))
      (node (ref "IC55") (pin "9") (pinfunction "9_9") (pintype "passive"))
      (node (ref "IC56") (pin "9") (pinfunction "9_9") (pintype "passive"))
      (node (ref "IC57") (pin "9") (pinfunction "9_9") (pintype "passive"))
    )
    (net (code "323") (name "Net-(IC54-Pad10)") (class "Default")
      (node (ref "IC54") (pin "10") (pinfunction "10_10") (pintype "passive"))
      (node (ref "IC55") (pin "10") (pinfunction "10_10") (pintype "passive"))
      (node (ref "IC56") (pin "10") (pinfunction "10_10") (pintype "passive"))
      (node (ref "IC57") (pin "10") (pinfunction "10_10") (pintype "passive"))
    )
    (net (code "324") (name "Net-(IC54-Pad11)") (class "Default")
      (node (ref "IC54") (pin "11") (pinfunction "11_11") (pintype "passive"))
      (node (ref "IC55") (pin "11") (pinfunction "11_11") (pintype "passive"))
      (node (ref "IC56") (pin "11") (pinfunction "11_11") (pintype "passive"))
      (node (ref "IC57") (pin "11") (pinfunction "11_11") (pintype "passive"))
    )
    (net (code "325") (name "Net-(IC54-Pad12)") (class "Default")
      (node (ref "IC54") (pin "12") (pinfunction "12_12") (pintype "passive"))
      (node (ref "IC55") (pin "12") (pinfunction "12_12") (pintype "passive"))
      (node (ref "IC56") (pin "12") (pinfunction "12_12") (pintype "passive"))
      (node (ref "IC57") (pin "12") (pinfunction "12_12") (pintype "passive"))
    )
    (net (code "326") (name "Net-(IC54-Pad13)") (class "Default")
      (node (ref "IC54") (pin "13") (pinfunction "13_13") (pintype "passive"))
      (node (ref "IC55") (pin "13") (pinfunction "13_13") (pintype "passive"))
      (node (ref "IC56") (pin "13") (pinfunction "13_13") (pintype "passive"))
      (node (ref "IC57") (pin "13") (pinfunction "13_13") (pintype "passive"))
    )
    (net (code "327") (name "Net-(IC54-Pad14)") (class "Default")
      (node (ref "IC54") (pin "14") (pinfunction "14_14") (pintype "passive"))
      (node (ref "IC55") (pin "14") (pinfunction "14_14") (pintype "passive"))
      (node (ref "IC56") (pin "14") (pinfunction "14_14") (pintype "passive"))
      (node (ref "IC57") (pin "14") (pinfunction "14_14") (pintype "passive"))
    )
    (net (code "328") (name "Net-(IC54-Pad15)") (class "Default")
      (node (ref "IC54") (pin "15") (pinfunction "15_15") (pintype "passive"))
      (node (ref "IC55") (pin "15") (pinfunction "15_15") (pintype "passive"))
      (node (ref "IC56") (pin "15") (pinfunction "15_15") (pintype "passive"))
      (node (ref "IC57") (pin "15") (pinfunction "15_15") (pintype "passive"))
    )
    (net (code "329") (name "Net-(IC54-Pad16)") (class "Default")
      (node (ref "IC54") (pin "16") (pinfunction "16_16") (pintype "passive"))
      (node (ref "IC55") (pin "16") (pinfunction "16_16") (pintype "passive"))
      (node (ref "IC56") (pin "16") (pinfunction "16_16") (pintype "passive"))
      (node (ref "IC57") (pin "16") (pinfunction "16_16") (pintype "passive"))
    )
    (net (code "330") (name "Net-(IC54-Pad17)") (class "Default")
      (node (ref "IC54") (pin "17") (pinfunction "17_17") (pintype "passive"))
      (node (ref "IC55") (pin "17") (pinfunction "17_17") (pintype "passive"))
      (node (ref "IC56") (pin "17") (pinfunction "17_17") (pintype "passive"))
      (node (ref "IC57") (pin "17") (pinfunction "17_17") (pintype "passive"))
    )
    (net (code "331") (name "Net-(IC54-Pad18)") (class "Default")
      (node (ref "IC54") (pin "18") (pinfunction "18_18") (pintype "passive"))
      (node (ref "IC55") (pin "18") (pinfunction "18_18") (pintype "passive"))
      (node (ref "IC56") (pin "18") (pinfunction "18_18") (pintype "passive"))
      (node (ref "IC57") (pin "18") (pinfunction "18_18") (pintype "passive"))
    )
    (net (code "332") (name "Net-(IC54-Pad19)") (class "Default")
      (node (ref "IC54") (pin "19") (pinfunction "19_19") (pintype "passive"))
      (node (ref "IC55") (pin "19") (pinfunction "19_19") (pintype "passive"))
      (node (ref "IC56") (pin "19") (pinfunction "19_19") (pintype "passive"))
      (node (ref "IC57") (pin "19") (pinfunction "19_19") (pintype "passive"))
    )
    (net (code "333") (name "Net-(IC54-Pad20)") (class "Default")
      (node (ref "IC54") (pin "20") (pinfunction "20_20") (pintype "passive"))
      (node (ref "IC55") (pin "20") (pinfunction "20_20") (pintype "passive"))
      (node (ref "IC56") (pin "20") (pinfunction "20_20") (pintype "passive"))
      (node (ref "IC57") (pin "20") (pinfunction "20_20") (pintype "passive"))
    )
    (net (code "334") (name "Net-(IC54-Pad21)") (class "Default")
      (node (ref "IC54") (pin "21") (pinfunction "21_21") (pintype "passive"))
      (node (ref "IC55") (pin "21") (pinfunction "21_21") (pintype "passive"))
      (node (ref "IC56") (pin "21") (pinfunction "21_21") (pintype "passive"))
      (node (ref "IC57") (pin "21") (pinfunction "21_21") (pintype "passive"))
    )
    (net (code "335") (name "Net-(IC54-Pad22)") (class "Default")
      (node (ref "IC54") (pin "22") (pinfunction "22_22") (pintype "passive"))
      (node (ref "IC55") (pin "22") (pinfunction "22_22") (pintype "passive"))
      (node (ref "IC56") (pin "22") (pinfunction "22_22") (pintype "passive"))
      (node (ref "IC57") (pin "22") (pinfunction "22_22") (pintype "passive"))
    )
    (net (code "336") (name "Net-(IC54-Pad23)") (class "Default")
      (node (ref "IC54") (pin "23") (pinfunction "23_23") (pintype "passive"))
      (node (ref "IC55") (pin "23") (pinfunction "23_23") (pintype "passive"))
      (node (ref "IC56") (pin "23") (pinfunction "23_23") (pintype "passive"))
      (node (ref "IC57") (pin "23") (pinfunction "23_23") (pintype "passive"))
    )
    (net (code "337") (name "Net-(IC54-Pad24)") (class "Default")
      (node (ref "IC54") (pin "24") (pinfunction "24_24") (pintype "passive"))
      (node (ref "IC55") (pin "24") (pinfunction "24_24") (pintype "passive"))
      (node (ref "IC56") (pin "24") (pinfunction "24_24") (pintype "passive"))
      (node (ref "IC57") (pin "24") (pinfunction "24_24") (pintype "passive"))
    )
    (net (code "338") (name "Net-(IC58-Pad1)") (class "Default")
      (node (ref "IC58") (pin "1") (pinfunction "1_1") (pintype "passive"))
      (node (ref "IC59") (pin "1") (pinfunction "1_1") (pintype "passive"))
      (node (ref "IC60") (pin "1") (pinfunction "1_1") (pintype "passive"))
      (node (ref "IC61") (pin "1") (pinfunction "1_1") (pintype "passive"))
    )
    (net (code "339") (name "Net-(IC58-Pad2)") (class "Default")
      (node (ref "IC58") (pin "2") (pinfunction "2_2") (pintype "passive"))
      (node (ref "IC59") (pin "2") (pinfunction "2_2") (pintype "passive"))
      (node (ref "IC60") (pin "2") (pinfunction "2_2") (pintype "passive"))
      (node (ref "IC61") (pin "2") (pinfunction "2_2") (pintype "passive"))
    )
    (net (code "340") (name "Net-(IC58-Pad3)") (class "Default")
      (node (ref "IC58") (pin "3") (pinfunction "3_3") (pintype "passive"))
      (node (ref "IC59") (pin "3") (pinfunction "3_3") (pintype "passive"))
      (node (ref "IC60") (pin "3") (pinfunction "3_3") (pintype "passive"))
      (node (ref "IC61") (pin "3") (pinfunction "3_3") (pintype "passive"))
    )
    (net (code "341") (name "Net-(IC58-Pad4)") (class "Default")
      (node (ref "IC58") (pin "4") (pinfunction "4_4") (pintype "passive"))
      (node (ref "IC59") (pin "4") (pinfunction "4_4") (pintype "passive"))
      (node (ref "IC60") (pin "4") (pinfunction "4_4") (pintype "passive"))
      (node (ref "IC61") (pin "4") (pinfunction "4_4") (pintype "passive"))
    )
    (net (code "342") (name "Net-(IC58-Pad5)") (class "Default")
      (node (ref "IC58") (pin "5") (pinfunction "5_5") (pintype "passive"))
      (node (ref "IC59") (pin "5") (pinfunction "5_5") (pintype "passive"))
      (node (ref "IC60") (pin "5") (pinfunction "5_5") (pintype "passive"))
      (node (ref "IC61") (pin "5") (pinfunction "5_5") (pintype "passive"))
    )
    (net (code "343") (name "Net-(IC58-Pad6)") (class "Default")
      (node (ref "IC58") (pin "6") (pinfunction "6_6") (pintype "passive"))
      (node (ref "IC59") (pin "6") (pinfunction "6_6") (pintype "passive"))
      (node (ref "IC60") (pin "6") (pinfunction "6_6") (pintype "passive"))
      (node (ref "IC61") (pin "6") (pinfunction "6_6") (pintype "passive"))
    )
    (net (code "344") (name "Net-(IC58-Pad7)") (class "Default")
      (node (ref "IC58") (pin "7") (pinfunction "7_7") (pintype "passive"))
      (node (ref "IC59") (pin "7") (pinfunction "7_7") (pintype "passive"))
      (node (ref "IC60") (pin "7") (pinfunction "7_7") (pintype "passive"))
      (node (ref "IC61") (pin "7") (pinfunction "7_7") (pintype "passive"))
    )
    (net (code "345") (name "Net-(IC58-Pad8)") (class "Default")
      (node (ref "IC58") (pin "8") (pinfunction "8_8") (pintype "passive"))
      (node (ref "IC59") (pin "8") (pinfunction "8_8") (pintype "passive"))
      (node (ref "IC60") (pin "8") (pinfunction "8_8") (pintype "passive"))
      (node (ref "IC61") (pin "8") (pinfunction "8_8") (pintype "passive"))
    )
    (net (code "346") (name "Net-(IC58-Pad9)") (class "Default")
      (node (ref "IC58") (pin "9") (pinfunction "9_9") (pintype "passive"))
      (node (ref "IC59") (pin "9") (pinfunction "9_9") (pintype "passive"))
      (node (ref "IC60") (pin "9") (pinfunction "9_9") (pintype "passive"))
      (node (ref "IC61") (pin "9") (pinfunction "9_9") (pintype "passive"))
    )
    (net (code "347") (name "Net-(IC58-Pad10)") (class "Default")
      (node (ref "IC58") (pin "10") (pinfunction "10_10") (pintype "passive"))
      (node (ref "IC59") (pin "10") (pinfunction "10_10") (pintype "passive"))
      (node (ref "IC60") (pin "10") (pinfunction "10_10") (pintype "passive"))
      (node (ref "IC61") (pin "10") (pinfunction "10_10") (pintype "passive"))
    )
    (net (code "348") (name "Net-(IC58-Pad11)") (class "Default")
      (node (ref "IC58") (pin "11") (pinfunction "11_11") (pintype "passive"))
      (node (ref "IC59") (pin "11") (pinfunction "11_11") (pintype "passive"))
      (node (ref "IC60") (pin "11") (pinfunction "11_11") (pintype "passive"))
      (node (ref "IC61") (pin "11") (pinfunction "11_11") (pintype "passive"))
    )
    (net (code "349") (name "Net-(IC58-Pad12)") (class "Default")
      (node (ref "IC58") (pin "12") (pinfunction "12_12") (pintype "passive"))
      (node (ref "IC59") (pin "12") (pinfunction "12_12") (pintype "passive"))
      (node (ref "IC60") (pin "12") (pinfunction "12_12") (pintype "passive"))
      (node (ref "IC61") (pin "12") (pinfunction "12_12") (pintype "passive"))
    )
    (net (code "350") (name "Net-(IC58-Pad13)") (class "Default")
      (node (ref "IC58") (pin "13") (pinfunction "13_13") (pintype "passive"))
      (node (ref "IC59") (pin "13") (pinfunction "13_13") (pintype "passive"))
      (node (ref "IC60") (pin "13") (pinfunction "13_13") (pintype "passive"))
      (node (ref "IC61") (pin "13") (pinfunction "13_13") (pintype "passive"))
    )
    (net (code "351") (name "Net-(IC58-Pad14)") (class "Default")
      (node (ref "IC58") (pin "14") (pinfunction "14_14") (pintype "passive"))
      (node (ref "IC59") (pin "14") (pinfunction "14_14") (pintype "passive"))
      (node (ref "IC60") (pin "14") (pinfunction "14_14") (pintype "passive"))
      (node (ref "IC61") (pin "14") (pinfunction "14_14") (pintype "passive"))
    )
    (net (code "352") (name "Net-(IC58-Pad15)") (class "Default")
      (node (ref "IC58") (pin "15") (pinfunction "15_15") (pintype "passive"))
      (node (ref "IC59") (pin "15") (pinfunction "15_15") (pintype "passive"))
      (node (ref "IC60") (pin "15") (pinfunction "15_15") (pintype "passive"))
      (node (ref "IC61") (pin "15") (pinfunction "15_15") (pintype "passive"))
    )
    (net (code "353") (name "Net-(IC58-Pad16)") (class "Default")
      (node (ref "IC58") (pin "16") (pinfunction "16_16") (pintype "passive"))
      (node (ref "IC59") (pin "16") (pinfunction "16_16") (pintype "passive"))
      (node (ref "IC60") (pin "16") (pinfunction "16_16") (pintype "passive"))
      (node (ref "IC61") (pin "16") (pinfunction "16_16") (pintype "passive"))
    )
    (net (code "354") (name "Net-(IC58-Pad17)") (class "Default")
      (node (ref "IC58") (pin "17") (pinfunction "17_17") (pintype "passive"))
      (node (ref "IC59") (pin "17") (pinfunction "17_17") (pintype "passive"))
      (node (ref "IC60") (pin "17") (pinfunction "17_17") (pintype "passive"))
      (node (ref "IC61") (pin "17") (pinfunction "17_17") (pintype "passive"))
    )
    (net (code "355") (name "Net-(IC58-Pad18)") (class "Default")
      (node (ref "IC58") (pin "18") (pinfunction "18_18") (pintype "passive"))
      (node (ref "IC59") (pin "18") (pinfunction "18_18") (pintype "passive"))
      (node (ref "IC60") (pin "18") (pinfunction "18_18") (pintype "passive"))
      (node (ref "IC61") (pin "18") (pinfunction "18_18") (pintype "passive"))
    )
    (net (code "356") (name "Net-(IC58-Pad19)") (class "Default")
      (node (ref "IC58") (pin "19") (pinfunction "19_19") (pintype "passive"))
      (node (ref "IC59") (pin "19") (pinfunction "19_19") (pintype "passive"))
      (node (ref "IC60") (pin "19") (pinfunction "19_19") (pintype "passive"))
      (node (ref "IC61") (pin "19") (pinfunction "19_19") (pintype "passive"))
    )
    (net (code "357") (name "Net-(IC58-Pad20)") (class "Default")
      (node (ref "IC58") (pin "20") (pinfunction "20_20") (pintype "passive"))
      (node (ref "IC59") (pin "20") (pinfunction "20_20") (pintype "passive"))
      (node (ref "IC60") (pin "20") (pinfunction "20_20") (pintype "passive"))
      (node (ref "IC61") (pin "20") (pinfunction "20_20") (pintype "passive"))
    )
    (net (code "358") (name "Net-(IC58-Pad21)") (class "Default")
      (node (ref "IC58") (pin "21") (pinfunction "21_21") (pintype "passive"))
      (node (ref "IC59") (pin "21") (pinfunction "21_21") (pintype "passive"))
      (node (ref "IC60") (pin "21") (pinfunction "21_21") (pintype "passive"))
      (node (ref "IC61") (pin "21") (pinfunction "21_21") (pintype "passive"))
    )
    (net (code "359") (name "Net-(IC58-Pad22)") (class "Default")
      (node (ref "IC58") (pin "22") (pinfunction "22_22") (pintype "passive"))
      (node (ref "IC59") (pin "22") (pinfunction "22_22") (pintype "passive"))
      (node (ref "IC60") (pin "22") (pinfunction "22_22") (pintype "passive"))
      (node (ref "IC61") (pin "22") (pinfunction "22_22") (pintype "passive"))
    )
    (net (code "360") (name "Net-(IC58-Pad23)") (class "Default")
      (node (ref "IC58") (pin "23") (pinfunction "23_23") (pintype "passive"))
      (node (ref "IC59") (pin "23") (pinfunction "23_23") (pintype "passive"))
      (node (ref "IC60") (pin "23") (pinfunction "23_23") (pintype "passive"))
      (node (ref "IC61") (pin "23") (pinfunction "23_23") (pintype "passive"))
    )
    (net (code "361") (name "Net-(IC58-Pad24)") (class "Default")
      (node (ref "IC58") (pin "24") (pinfunction "24_24") (pintype "passive"))
      (node (ref "IC59") (pin "24") (pinfunction "24_24") (pintype "passive"))
      (node (ref "IC60") (pin "24") (pinfunction "24_24") (pintype "passive"))
      (node (ref "IC61") (pin "24") (pinfunction "24_24") (pintype "passive"))
    )
    (net (code "362") (name "Net-(IC62-Pad1)") (class "Default")
      (node (ref "IC62") (pin "1") (pinfunction "1_1") (pintype "passive"))
      (node (ref "IC63") (pin "1") (pinfunction "1_1") (pintype "passive"))
      (node (ref "IC64") (pin "1") (pinfunction "1_1") (pintype "passive"))
      (node (ref "IC65") (pin "1") (pinfunction "1_1") (pintype "passive"))
    )
    (net (code "363") (name "Net-(IC62-Pad2)") (class "Default")
      (node (ref "IC62") (pin "2") (pinfunction "2_2") (pintype "passive"))
      (node (ref "IC63") (pin "2") (pinfunction "2_2") (pintype "passive"))
      (node (ref "IC64") (pin "2") (pinfunction "2_2") (pintype "passive"))
      (node (ref "IC65") (pin "2") (pinfunction "2_2") (pintype "passive"))
    )
    (net (code "364") (name "Net-(IC62-Pad3)") (class "Default")
      (node (ref "IC62") (pin "3") (pinfunction "3_3") (pintype "passive"))
      (node (ref "IC63") (pin "3") (pinfunction "3_3") (pintype "passive"))
      (node (ref "IC64") (pin "3") (pinfunction "3_3") (pintype "passive"))
      (node (ref "IC65") (pin "3") (pinfunction "3_3") (pintype "passive"))
    )
    (net (code "365") (name "Net-(IC62-Pad4)") (class "Default")
      (node (ref "IC62") (pin "4") (pinfunction "4_4") (pintype "passive"))
      (node (ref "IC63") (pin "4") (pinfunction "4_4") (pintype "passive"))
      (node (ref "IC64") (pin "4") (pinfunction "4_4") (pintype "passive"))
      (node (ref "IC65") (pin "4") (pinfunction "4_4") (pintype "passive"))
    )
    (net (code "366") (name "Net-(IC62-Pad5)") (class "Default")
      (node (ref "IC62") (pin "5") (pinfunction "5_5") (pintype "passive"))
      (node (ref "IC63") (pin "5") (pinfunction "5_5") (pintype "passive"))
      (node (ref "IC64") (pin "5") (pinfunction "5_5") (pintype "passive"))
      (node (ref "IC65") (pin "5") (pinfunction "5_5") (pintype "passive"))
    )
    (net (code "367") (name "Net-(IC62-Pad6)") (class "Default")
      (node (ref "IC62") (pin "6") (pinfunction "6_6") (pintype "passive"))
      (node (ref "IC63") (pin "6") (pinfunction "6_6") (pintype "passive"))
      (node (ref "IC64") (pin "6") (pinfunction "6_6") (pintype "passive"))
      (node (ref "IC65") (pin "6") (pinfunction "6_6") (pintype "passive"))
    )
    (net (code "368") (name "Net-(IC62-Pad7)") (class "Default")
      (node (ref "IC62") (pin "7") (pinfunction "7_7") (pintype "passive"))
      (node (ref "IC63") (pin "7") (pinfunction "7_7") (pintype "passive"))
      (node (ref "IC64") (pin "7") (pinfunction "7_7") (pintype "passive"))
      (node (ref "IC65") (pin "7") (pinfunction "7_7") (pintype "passive"))
    )
    (net (code "369") (name "Net-(IC62-Pad8)") (class "Default")
      (node (ref "IC62") (pin "8") (pinfunction "8_8") (pintype "passive"))
      (node (ref "IC63") (pin "8") (pinfunction "8_8") (pintype "passive"))
      (node (ref "IC64") (pin "8") (pinfunction "8_8") (pintype "passive"))
      (node (ref "IC65") (pin "8") (pinfunction "8_8") (pintype "passive"))
    )
    (net (code "370") (name "Net-(IC62-Pad9)") (class "Default")
      (node (ref "IC62") (pin "9") (pinfunction "9_9") (pintype "passive"))
      (node (ref "IC63") (pin "9") (pinfunction "9_9") (pintype "passive"))
      (node (ref "IC64") (pin "9") (pinfunction "9_9") (pintype "passive"))
      (node (ref "IC65") (pin "9") (pinfunction "9_9") (pintype "passive"))
    )
    (net (code "371") (name "Net-(IC62-Pad10)") (class "Default")
      (node (ref "IC62") (pin "10") (pinfunction "10_10") (pintype "passive"))
      (node (ref "IC63") (pin "10") (pinfunction "10_10") (pintype "passive"))
      (node (ref "IC64") (pin "10") (pinfunction "10_10") (pintype "passive"))
      (node (ref "IC65") (pin "10") (pinfunction "10_10") (pintype "passive"))
    )
    (net (code "372") (name "Net-(IC62-Pad11)") (class "Default")
      (node (ref "IC62") (pin "11") (pinfunction "11_11") (pintype "passive"))
      (node (ref "IC63") (pin "11") (pinfunction "11_11") (pintype "passive"))
      (node (ref "IC64") (pin "11") (pinfunction "11_11") (pintype "passive"))
      (node (ref "IC65") (pin "11") (pinfunction "11_11") (pintype "passive"))
    )
    (net (code "373") (name "Net-(IC62-Pad12)") (class "Default")
      (node (ref "IC62") (pin "12") (pinfunction "12_12") (pintype "passive"))
      (node (ref "IC63") (pin "12") (pinfunction "12_12") (pintype "passive"))
      (node (ref "IC64") (pin "12") (pinfunction "12_12") (pintype "passive"))
      (node (ref "IC65") (pin "12") (pinfunction "12_12") (pintype "passive"))
    )
    (net (code "374") (name "Net-(IC62-Pad13)") (class "Default")
      (node (ref "IC62") (pin "13") (pinfunction "13_13") (pintype "passive"))
      (node (ref "IC63") (pin "13") (pinfunction "13_13") (pintype "passive"))
      (node (ref "IC64") (pin "13") (pinfunction "13_13") (pintype "passive"))
      (node (ref "IC65") (pin "13") (pinfunction "13_13") (pintype "passive"))
    )
    (net (code "375") (name "Net-(IC62-Pad14)") (class "Default")
      (node (ref "IC62") (pin "14") (pinfunction "14_14") (pintype "passive"))
      (node (ref "IC63") (pin "14") (pinfunction "14_14") (pintype "passive"))
      (node (ref "IC64") (pin "14") (pinfunction "14_14") (pintype "passive"))
      (node (ref "IC65") (pin "14") (pinfunction "14_14") (pintype "passive"))
    )
    (net (code "376") (name "Net-(IC62-Pad15)") (class "Default")
      (node (ref "IC62") (pin "15") (pinfunction "15_15") (pintype "passive"))
      (node (ref "IC63") (pin "15") (pinfunction "15_15") (pintype "passive"))
      (node (ref "IC64") (pin "15") (pinfunction "15_15") (pintype "passive"))
      (node (ref "IC65") (pin "15") (pinfunction "15_15") (pintype "passive"))
    )
    (net (code "377") (name "Net-(IC62-Pad16)") (class "Default")
      (node (ref "IC62") (pin "16") (pinfunction "16_16") (pintype "passive"))
      (node (ref "IC63") (pin "16") (pinfunction "16_16") (pintype "passive"))
      (node (ref "IC64") (pin "16") (pinfunction "16_16") (pintype "passive"))
      (node (ref "IC65") (pin "16") (pinfunction "16_16") (pintype "passive"))
    )
    (net (code "378") (name "Net-(IC62-Pad17)") (class "Default")
      (node (ref "IC62") (pin "17") (pinfunction "17_17") (pintype "passive"))
      (node (ref "IC63") (pin "17") (pinfunction "17_17") (pintype "passive"))
      (node (ref "IC64") (pin "17") (pinfunction "17_17") (pintype "passive"))
      (node (ref "IC65") (pin "17") (pinfunction "17_17") (pintype "passive"))
    )
    (net (code "379") (name "Net-(IC62-Pad18)") (class "Default")
      (node (ref "IC62") (pin "18") (pinfunction "18_18") (pintype "passive"))
      (node (ref "IC63") (pin "18") (pinfunction "18_18") (pintype "passive"))
      (node (ref "IC64") (pin "18") (pinfunction "18_18") (pintype "passive"))
      (node (ref "IC65") (pin "18") (pinfunction "18_18") (pintype "passive"))
    )
    (net (code "380") (name "Net-(IC62-Pad19)") (class "Default")
      (node (ref "IC62") (pin "19") (pinfunction "19_19") (pintype "passive"))
      (node (ref "IC63") (pin "19") (pinfunction "19_19") (pintype "passive"))
      (node (ref "IC64") (pin "19") (pinfunction "19_19") (pintype "passive"))
      (node (ref "IC65") (pin "19") (pinfunction "19_19") (pintype "passive"))
    )
    (net (code "381") (name "Net-(IC62-Pad20)") (class "Default")
      (node (ref "IC62") (pin "20") (pinfunction "20_20") (pintype "passive"))
      (node (ref "IC63") (pin "20") (pinfunction "20_20") (pintype "passive"))
      (node (ref "IC64") (pin "20") (pinfunction "20_20") (pintype "passive"))
      (node (ref "IC65") (pin "20") (pinfunction "20_20") (pintype "passive"))
    )
    (net (code "382") (name "Net-(IC62-Pad21)") (class "Default")
      (node (ref "IC62") (pin "21") (pinfunction "21_21") (pintype "passive"))
      (node (ref "IC63") (pin "21") (pinfunction "21_21") (pintype "passive"))
      (node (ref "IC64") (pin "21") (pinfunction "21_21") (pintype "passive"))
      (node (ref "IC65") (pin "21") (pinfunction "21_21") (pintype "passive"))
    )
    (net (code "383") (name "Net-(IC62-Pad22)") (class "Default")
      (node (ref "IC62") (pin "22") (pinfunction "22_22") (pintype "passive"))
      (node (ref "IC63") (pin "22") (pinfunction "22_22") (pintype "passive"))
      (node (ref "IC64") (pin "22") (pinfunction "22_22") (pintype "passive"))
      (node (ref "IC65") (pin "22") (pinfunction "22_22") (pintype "passive"))
    )
    (net (code "384") (name "Net-(IC62-Pad23)") (class "Default")
      (node (ref "IC62") (pin "23") (pinfunction "23_23") (pintype "passive"))
      (node (ref "IC63") (pin "23") (pinfunction "23_23") (pintype "passive"))
      (node (ref "IC64") (pin "23") (pinfunction "23_23") (pintype "passive"))
      (node (ref "IC65") (pin "23") (pinfunction "23_23") (pintype "passive"))
    )
    (net (code "385") (name "Net-(IC62-Pad24)") (class "Default")
      (node (ref "IC62") (pin "24") (pinfunction "24_24") (pintype "passive"))
      (node (ref "IC63") (pin "24") (pinfunction "24_24") (pintype "passive"))
      (node (ref "IC64") (pin "24") (pinfunction "24_24") (pintype "passive"))
      (node (ref "IC65") (pin "24") (pinfunction "24_24") (pintype "passive"))
    )
    (net (code "386") (name "Net-(IC66-Pad1)") (class "Default")
      (node (ref "IC66") (pin "1") (pinfunction "1_1") (pintype "passive"))
      (node (ref "IC67") (pin "1") (pinfunction "1_1") (pintype "passive"))
      (node (ref "IC68") (pin "1") (pinfunction "1_1") (pintype "passive"))
      (node (ref "IC69") (pin "1") (pinfunction "1_1") (pintype "passive"))
    )
    (net (code "387") (name "Net-(IC66-Pad2)") (class "Default")
      (node (ref "IC66") (pin "2") (pinfunction "2_2") (pintype "passive"))
      (node (ref "IC67") (pin "2") (pinfunction "2_2") (pintype "passive"))
      (node (ref "IC68") (pin "2") (pinfunction "2_2") (pintype "passive"))
      (node (ref "IC69") (pin "2") (pinfunction "2_2") (pintype "passive"))
    )
    (net (code "388") (name "Net-(IC66-Pad3)") (class "Default")
      (node (ref "IC66") (pin "3") (pinfunction "3_3") (pintype "passive"))
      (node (ref "IC67") (pin "3") (pinfunction "3_3") (pintype "passive"))
      (node (ref "IC68") (pin "3") (pinfunction "3_3") (pintype "passive"))
      (node (ref "IC69") (pin "3") (pinfunction "3_3") (pintype "passive"))
    )
    (net (code "389") (name "Net-(IC66-Pad4)") (class "Default")
      (node (ref "IC66") (pin "4") (pinfunction "4_4") (pintype "passive"))
      (node (ref "IC67") (pin "4") (pinfunction "4_4") (pintype "passive"))
      (node (ref "IC68") (pin "4") (pinfunction "4_4") (pintype "passive"))
      (node (ref "IC69") (pin "4") (pinfunction "4_4") (pintype "passive"))
    )
    (net (code "390") (name "Net-(IC66-Pad5)") (class "Default")
      (node (ref "IC66") (pin "5") (pinfunction "5_5") (pintype "passive"))
      (node (ref "IC67") (pin "5") (pinfunction "5_5") (pintype "passive"))
      (node (ref "IC68") (pin "5") (pinfunction "5_5") (pintype "passive"))
      (node (ref "IC69") (pin "5") (pinfunction "5_5") (pintype "passive"))
    )
    (net (code "391") (name "Net-(IC66-Pad6)") (class "Default")
      (node (ref "IC66") (pin "6") (pinfunction "6_6") (pintype "passive"))
      (node (ref "IC67") (pin "6") (pinfunction "6_6") (pintype "passive"))
      (node (ref "IC68") (pin "6") (pinfunction "6_6") (pintype "passive"))
      (node (ref "IC69") (pin "6") (pinfunction "6_6") (pintype "passive"))
    )
    (net (code "392") (name "Net-(IC66-Pad7)") (class "Default")
      (node (ref "IC66") (pin "7") (pinfunction "7_7") (pintype "passive"))
      (node (ref "IC67") (pin "7") (pinfunction "7_7") (pintype "passive"))
      (node (ref "IC68") (pin "7") (pinfunction "7_7") (pintype "passive"))
      (node (ref "IC69") (pin "7") (pinfunction "7_7") (pintype "passive"))
    )
    (net (code "393") (name "Net-(IC66-Pad8)") (class "Default")
      (node (ref "IC66") (pin "8") (pinfunction "8_8") (pintype "passive"))
      (node (ref "IC67") (pin "8") (pinfunction "8_8") (pintype "passive"))
      (node (ref "IC68") (pin "8") (pinfunction "8_8") (pintype "passive"))
      (node (ref "IC69") (pin "8") (pinfunction "8_8") (pintype "passive"))
    )
    (net (code "394") (name "Net-(IC66-Pad9)") (class "Default")
      (node (ref "IC66") (pin "9") (pinfunction "9_9") (pintype "passive"))
      (node (ref "IC67") (pin "9") (pinfunction "9_9") (pintype "passive"))
      (node (ref "IC68") (pin "9") (pinfunction "9_9") (pintype "passive"))
      (node (ref "IC69") (pin "9") (pinfunction "9_9") (pintype "passive"))
    )
    (net (code "395") (name "Net-(IC66-Pad10)") (class "Default")
      (node (ref "IC66") (pin "10") (pinfunction "10_10") (pintype "passive"))
      (node (ref "IC67") (pin "10") (pinfunction "10_10") (pintype "passive"))
      (node (ref "IC68") (pin "10") (pinfunction "10_10") (pintype "passive"))
      (node (ref "IC69") (pin "10") (pinfunction "10_10") (pintype "passive"))
    )
    (net (code "396") (name "Net-(IC66-Pad11)") (class "Default")
      (node (ref "IC66") (pin "11") (pinfunction "11_11") (pintype "passive"))
      (node (ref "IC67") (pin "11") (pinfunction "11_11") (pintype "passive"))
      (node (ref "IC68") (pin "11") (pinfunction "11_11") (pintype "passive"))
      (node (ref "IC69") (pin "11") (pinfunction "11_11") (pintype "passive"))
    )
    (net (code "397") (name "Net-(IC66-Pad12)") (class "Default")
      (node (ref "IC66") (pin "12") (pinfunction "12_12") (pintype "passive"))
      (node (ref "IC67") (pin "12") (pinfunction "12_12") (pintype "passive"))
      (node (ref "IC68") (pin "12") (pinfunction "12_12") (pintype "passive"))
      (node (ref "IC69") (pin "12") (pinfunction "12_12") (pintype "passive"))
    )
    (net (code "398") (name "Net-(IC66-Pad13)") (class "Default")
      (node (ref "IC66") (pin "13") (pinfunction "13_13") (pintype "passive"))
      (node (ref "IC67") (pin "13") (pinfunction "13_13") (pintype "passive"))
      (node (ref "IC68") (pin "13") (pinfunction "13_13") (pintype "passive"))
      (node (ref "IC69") (pin "13") (pinfunction "13_13") (pintype "passive"))
    )
    (net (code "399") (name "Net-(IC66-Pad14)") (class "Default")
      (node (ref "IC66") (pin "14") (pinfunction "14_14") (pintype "passive"))
      (node (ref "IC67") (pin "14") (pinfunction "14_14") (pintype "passive"))
      (node (ref "IC68") (pin "14") (pinfunction "14_14") (pintype "passive"))
      (node (ref "IC69") (pin "14") (pinfunction "14_14") (pintype "passive"))
    )
    (net (code "400") (name "Net-(IC66-Pad15)") (class "Default")
      (node (ref "IC66") (pin "15") (pinfunction "15_15") (pintype "passive"))
      (node (ref "IC67") (pin "15") (pinfunction "15_15") (pintype "passive"))
      (node (ref "IC68") (pin "15") (pinfunction "15_15") (pintype "passive"))
      (node (ref "IC69") (pin "15") (pinfunction "15_15") (pintype "passive"))
    )
    (net (code "401") (name "Net-(IC66-Pad16)") (class "Default")
      (node (ref "IC66") (pin "16") (pinfunction "16_16") (pintype "passive"))
      (node (ref "IC67") (pin "16") (pinfunction "16_16") (pintype "passive"))
      (node (ref "IC68") (pin "16") (pinfunction "16_16") (pintype "passive"))
      (node (ref "IC69") (pin "16") (pinfunction "16_16") (pintype "passive"))
    )
    (net (code "402") (name "Net-(IC66-Pad17)") (class "Default")
      (node (ref "IC66") (pin "17") (pinfunction "17_17") (pintype "passive"))
      (node (ref "IC67") (pin "17") (pinfunction "17_17") (pintype "passive"))
      (node (ref "IC68") (pin "17") (pinfunction "17_17") (pintype "passive"))
      (node (ref "IC69") (pin "17") (pinfunction "17_17") (pintype "passive"))
    )
    (net (code "403") (name "Net-(IC66-Pad18)") (class "Default")
      (node (ref "IC66") (pin "18") (pinfunction "18_18") (pintype "passive"))
      (node (ref "IC67") (pin "18") (pinfunction "18_18") (pintype "passive"))
      (node (ref "IC68") (pin "18") (pinfunction "18_18") (pintype "passive"))
      (node (ref "IC69") (pin "18") (pinfunction "18_18") (pintype "passive"))
    )
    (net (code "404") (name "Net-(IC66-Pad19)") (class "Default")
      (node (ref "IC66") (pin "19") (pinfunction "19_19") (pintype "passive"))
      (node (ref "IC67") (pin "19") (pinfunction "19_19") (pintype "passive"))
      (node (ref "IC68") (pin "19") (pinfunction "19_19") (pintype "passive"))
      (node (ref "IC69") (pin "19") (pinfunction "19_19") (pintype "passive"))
    )
    (net (code "405") (name "Net-(IC66-Pad20)") (class "Default")
      (node (ref "IC66") (pin "20") (pinfunction "20_20") (pintype "passive"))
      (node (ref "IC67") (pin "20") (pinfunction "20_20") (pintype "passive"))
      (node (ref "IC68") (pin "20") (pinfunction "20_20") (pintype "passive"))
      (node (ref "IC69") (pin "20") (pinfunction "20_20") (pintype "passive"))
    )
    (net (code "406") (name "Net-(IC66-Pad21)") (class "Default")
      (node (ref "IC66") (pin "21") (pinfunction "21_21") (pintype "passive"))
      (node (ref "IC67") (pin "21") (pinfunction "21_21") (pintype "passive"))
      (node (ref "IC68") (pin "21") (pinfunction "21_21") (pintype "passive"))
      (node (ref "IC69") (pin "21") (pinfunction "21_21") (pintype "passive"))
    )
    (net (code "407") (name "Net-(IC66-Pad22)") (class "Default")
      (node (ref "IC66") (pin "22") (pinfunction "22_22") (pintype "passive"))
      (node (ref "IC67") (pin "22") (pinfunction "22_22") (pintype "passive"))
      (node (ref "IC68") (pin "22") (pinfunction "22_22") (pintype "passive"))
      (node (ref "IC69") (pin "22") (pinfunction "22_22") (pintype "passive"))
    )
    (net (code "408") (name "Net-(IC66-Pad23)") (class "Default")
      (node (ref "IC66") (pin "23") (pinfunction "23_23") (pintype "passive"))
      (node (ref "IC67") (pin "23") (pinfunction "23_23") (pintype "passive"))
      (node (ref "IC68") (pin "23") (pinfunction "23_23") (pintype "passive"))
      (node (ref "IC69") (pin "23") (pinfunction "23_23") (pintype "passive"))
    )
    (net (code "409") (name "Net-(IC66-Pad24)") (class "Default")
      (node (ref "IC66") (pin "24") (pinfunction "24_24") (pintype "passive"))
      (node (ref "IC67") (pin "24") (pinfunction "24_24") (pintype "passive"))
      (node (ref "IC68") (pin "24") (pinfunction "24_24") (pintype "passive"))
      (node (ref "IC69") (pin "24") (pinfunction "24_24") (pintype "passive"))
    )
    (net (code "410") (name "Net-(IC70-Pad1)") (class "Default")
      (node (ref "IC70") (pin "1") (pinfunction "1_1") (pintype "passive"))
      (node (ref "IC71") (pin "1") (pinfunction "1_1") (pintype "passive"))
      (node (ref "IC72") (pin "1") (pinfunction "1_1") (pintype "passive"))
      (node (ref "IC73") (pin "1") (pinfunction "1_1") (pintype "passive"))
    )
    (net (code "411") (name "Net-(IC70-Pad2)") (class "Default")
      (node (ref "IC70") (pin "2") (pinfunction "2_2") (pintype "passive"))
      (node (ref "IC71") (pin "2") (pinfunction "2_2") (pintype "passive"))
      (node (ref "IC72") (pin "2") (pinfunction "2_2") (pintype "passive"))
      (node (ref "IC73") (pin "2") (pinfunction "2_2") (pintype "passive"))
    )
    (net (code "412") (name "Net-(IC70-Pad3)") (class "Default")
      (node (ref "IC70") (pin "3") (pinfunction "3_3") (pintype "passive"))
      (node (ref "IC71") (pin "3") (pinfunction "3_3") (pintype "passive"))
      (node (ref "IC72") (pin "3") (pinfunction "3_3") (pintype "passive"))
      (node (ref "IC73") (pin "3") (pinfunction "3_3") (pintype "passive"))
    )
    (net (code "413") (name "Net-(IC70-Pad4)") (class "Default")
      (node (ref "IC70") (pin "4") (pinfunction "4_4") (pintype "passive"))
      (node (ref "IC71") (pin "4") (pinfunction "4_4") (pintype "passive"))
      (node (ref "IC72") (pin "4") (pinfunction "4_4") (pintype "passive"))
      (node (ref "IC73") (pin "4") (pinfunction "4_4") (pintype "passive"))
    )
    (net (code "414") (name "Net-(IC70-Pad5)") (class "Default")
      (node (ref "IC70") (pin "5") (pinfunction "5_5") (pintype "passive"))
      (node (ref "IC71") (pin "5") (pinfunction "5_5") (pintype "passive"))
      (node (ref "IC72") (pin "5") (pinfunction "5_5") (pintype "passive"))
      (node (ref "IC73") (pin "5") (pinfunction "5_5") (pintype "passive"))
    )
    (net (code "415") (name "Net-(IC70-Pad6)") (class "Default")
      (node (ref "IC70") (pin "6") (pinfunction "6_6") (pintype "passive"))
      (node (ref "IC71") (pin "6") (pinfunction "6_6") (pintype "passive"))
      (node (ref "IC72") (pin "6") (pinfunction "6_6") (pintype "passive"))
      (node (ref "IC73") (pin "6") (pinfunction "6_6") (pintype "passive"))
    )
    (net (code "416") (name "Net-(IC70-Pad7)") (class "Default")
      (node (ref "IC70") (pin "7") (pinfunction "7_7") (pintype "passive"))
      (node (ref "IC71") (pin "7") (pinfunction "7_7") (pintype "passive"))
      (node (ref "IC72") (pin "7") (pinfunction "7_7") (pintype "passive"))
      (node (ref "IC73") (pin "7") (pinfunction "7_7") (pintype "passive"))
    )
    (net (code "417") (name "Net-(IC70-Pad8)") (class "Default")
      (node (ref "IC70") (pin "8") (pinfunction "8_8") (pintype "passive"))
      (node (ref "IC71") (pin "8") (pinfunction "8_8") (pintype "passive"))
      (node (ref "IC72") (pin "8") (pinfunction "8_8") (pintype "passive"))
      (node (ref "IC73") (pin "8") (pinfunction "8_8") (pintype "passive"))
    )
    (net (code "418") (name "Net-(IC70-Pad9)") (class "Default")
      (node (ref "IC70") (pin "9") (pinfunction "9_9") (pintype "passive"))
      (node (ref "IC71") (pin "9") (pinfunction "9_9") (pintype "passive"))
      (node (ref "IC72") (pin "9") (pinfunction "9_9") (pintype "passive"))
      (node (ref "IC73") (pin "9") (pinfunction "9_9") (pintype "passive"))
    )
    (net (code "419") (name "Net-(IC70-Pad10)") (class "Default")
      (node (ref "IC70") (pin "10") (pinfunction "10_10") (pintype "passive"))
      (node (ref "IC71") (pin "10") (pinfunction "10_10") (pintype "passive"))
      (node (ref "IC72") (pin "10") (pinfunction "10_10") (pintype "passive"))
      (node (ref "IC73") (pin "10") (pinfunction "10_10") (pintype "passive"))
    )
    (net (code "420") (name "Net-(IC70-Pad11)") (class "Default")
      (node (ref "IC70") (pin "11") (pinfunction "11_11") (pintype "passive"))
      (node (ref "IC71") (pin "11") (pinfunction "11_11") (pintype "passive"))
      (node (ref "IC72") (pin "11") (pinfunction "11_11") (pintype "passive"))
      (node (ref "IC73") (pin "11") (pinfunction "11_11") (pintype "passive"))
    )
    (net (code "421") (name "Net-(IC70-Pad12)") (class "Default")
      (node (ref "IC70") (pin "12") (pinfunction "12_12") (pintype "passive"))
      (node (ref "IC71") (pin "12") (pinfunction "12_12") (pintype "passive"))
      (node (ref "IC72") (pin "12") (pinfunction "12_12") (pintype "passive"))
      (node (ref "IC73") (pin "12") (pinfunction "12_12") (pintype "passive"))
    )
    (net (code "422") (name "Net-(IC70-Pad13)") (class "Default")
      (node (ref "IC70") (pin "13") (pinfunction "13_13") (pintype "passive"))
      (node (ref "IC71") (pin "13") (pinfunction "13_13") (pintype "passive"))
      (node (ref "IC72") (pin "13") (pinfunction "13_13") (pintype "passive"))
      (node (ref "IC73") (pin "13") (pinfunction "13_13") (pintype "passive"))
    )
    (net (code "423") (name "Net-(IC70-Pad14)") (class "Default")
      (node (ref "IC70") (pin "14") (pinfunction "14_14") (pintype "passive"))
      (node (ref "IC71") (pin "14") (pinfunction "14_14") (pintype "passive"))
      (node (ref "IC72") (pin "14") (pinfunction "14_14") (pintype "passive"))
      (node (ref "IC73") (pin "14") (pinfunction "14_14") (pintype "passive"))
    )
    (net (code "424") (name "Net-(IC70-Pad15)") (class "Default")
      (node (ref "IC70") (pin "15") (pinfunction "15_15") (pintype "passive"))
      (node (ref "IC71") (pin "15") (pinfunction "15_15") (pintype "passive"))
      (node (ref "IC72") (pin "15") (pinfunction "15_15") (pintype "passive"))
      (node (ref "IC73") (pin "15") (pinfunction "15_15") (pintype "passive"))
    )
    (net (code "425") (name "Net-(IC70-Pad16)") (class "Default")
      (node (ref "IC70") (pin "16") (pinfunction "16_16") (pintype "passive"))
      (node (ref "IC71") (pin "16") (pinfunction "16_16") (pintype "passive"))
      (node (ref "IC72") (pin "16") (pinfunction "16_16") (pintype "passive"))
      (node (ref "IC73") (pin "16") (pinfunction "16_16") (pintype "passive"))
    )
    (net (code "426") (name "Net-(IC70-Pad17)") (class "Default")
      (node (ref "IC70") (pin "17") (pinfunction "17_17") (pintype "passive"))
      (node (ref "IC71") (pin "17") (pinfunction "17_17") (pintype "passive"))
      (node (ref "IC72") (pin "17") (pinfunction "17_17") (pintype "passive"))
      (node (ref "IC73") (pin "17") (pinfunction "17_17") (pintype "passive"))
    )
    (net (code "427") (name "Net-(IC70-Pad18)") (class "Default")
      (node (ref "IC70") (pin "18") (pinfunction "18_18") (pintype "passive"))
      (node (ref "IC71") (pin "18") (pinfunction "18_18") (pintype "passive"))
      (node (ref "IC72") (pin "18") (pinfunction "18_18") (pintype "passive"))
      (node (ref "IC73") (pin "18") (pinfunction "18_18") (pintype "passive"))
    )
    (net (code "428") (name "Net-(IC70-Pad19)") (class "Default")
      (node (ref "IC70") (pin "19") (pinfunction "19_19") (pintype "passive"))
      (node (ref "IC71") (pin "19") (pinfunction "19_19") (pintype "passive"))
      (node (ref "IC72") (pin "19") (pinfunction "19_19") (pintype "passive"))
      (node (ref "IC73") (pin "19") (pinfunction "19_19") (pintype "passive"))
    )
    (net (code "429") (name "Net-(IC70-Pad20)") (class "Default")
      (node (ref "IC70") (pin "20") (pinfunction "20_20") (pintype "passive"))
      (node (ref "IC71") (pin "20") (pinfunction "20_20") (pintype "passive"))
      (node (ref "IC72") (pin "20") (pinfunction "20_20") (pintype "passive"))
      (node (ref "IC73") (pin "20") (pinfunction "20_20") (pintype "passive"))
    )
    (net (code "430") (name "Net-(IC70-Pad21)") (class "Default")
      (node (ref "IC70") (pin "21") (pinfunction "21_21") (pintype "passive"))
      (node (ref "IC71") (pin "21") (pinfunction "21_21") (pintype "passive"))
      (node (ref "IC72") (pin "21") (pinfunction "21_21") (pintype "passive"))
      (node (ref "IC73") (pin "21") (pinfunction "21_21") (pintype "passive"))
    )
    (net (code "431") (name "Net-(IC70-Pad22)") (class "Default")
      (node (ref "IC70") (pin "22") (pinfunction "22_22") (pintype "passive"))
      (node (ref "IC71") (pin "22") (pinfunction "22_22") (pintype "passive"))
      (node (ref "IC72") (pin "22") (pinfunction "22_22") (pintype "passive"))
      (node (ref "IC73") (pin "22") (pinfunction "22_22") (pintype "passive"))
    )
    (net (code "432") (name "Net-(IC70-Pad23)") (class "Default")
      (node (ref "IC70") (pin "23") (pinfunction "23_23") (pintype "passive"))
      (node (ref "IC71") (pin "23") (pinfunction "23_23") (pintype "passive"))
      (node (ref "IC72") (pin "23") (pinfunction "23_23") (pintype "passive"))
      (node (ref "IC73") (pin "23") (pinfunction "23_23") (pintype "passive"))
    )
    (net (code "433") (name "Net-(IC70-Pad24)") (class "Default")
      (node (ref "IC70") (pin "24") (pinfunction "24_24") (pintype "passive"))
      (node (ref "IC71") (pin "24") (pinfunction "24_24") (pintype "passive"))
      (node (ref "IC72") (pin "24") (pinfunction "24_24") (pintype "passive"))
      (node (ref "IC73") (pin "24") (pinfunction "24_24") (pintype "passive"))
    )
    (net (code "434") (name "Net-(IC74-Pad1)") (class "Default")
      (node (ref "IC74") (pin "1") (pinfunction "1_1") (pintype "passive"))
      (node (ref "IC75") (pin "1") (pinfunction "1_1") (pintype "passive"))
      (node (ref "IC76") (pin "1") (pinfunction "1_1") (pintype "passive"))
      (node (ref "IC77") (pin "1") (pinfunction "1_1") (pintype "passive"))
    )
    (net (code "435") (name "Net-(IC74-Pad2)") (class "Default")
      (node (ref "IC74") (pin "2") (pinfunction "2_2") (pintype "passive"))
      (node (ref "IC75") (pin "2") (pinfunction "2_2") (pintype "passive"))
      (node (ref "IC76") (pin "2") (pinfunction "2_2") (pintype "passive"))
      (node (ref "IC77") (pin "2") (pinfunction "2_2") (pintype "passive"))
    )
    (net (code "436") (name "Net-(IC74-Pad3)") (class "Default")
      (node (ref "IC74") (pin "3") (pinfunction "3_3") (pintype "passive"))
      (node (ref "IC75") (pin "3") (pinfunction "3_3") (pintype "passive"))
      (node (ref "IC76") (pin "3") (pinfunction "3_3") (pintype "passive"))
      (node (ref "IC77") (pin "3") (pinfunction "3_3") (pintype "passive"))
    )
    (net (code "437") (name "Net-(IC74-Pad4)") (class "Default")
      (node (ref "IC74") (pin "4") (pinfunction "4_4") (pintype "passive"))
      (node (ref "IC75") (pin "4") (pinfunction "4_4") (pintype "passive"))
      (node (ref "IC76") (pin "4") (pinfunction "4_4") (pintype "passive"))
      (node (ref "IC77") (pin "4") (pinfunction "4_4") (pintype "passive"))
    )
    (net (code "438") (name "Net-(IC74-Pad5)") (class "Default")
      (node (ref "IC74") (pin "5") (pinfunction "5_5") (pintype "passive"))
      (node (ref "IC75") (pin "5") (pinfunction "5_5") (pintype "passive"))
      (node (ref "IC76") (pin "5") (pinfunction "5_5") (pintype "passive"))
      (node (ref "IC77") (pin "5") (pinfunction "5_5") (pintype "passive"))
    )
    (net (code "439") (name "Net-(IC74-Pad6)") (class "Default")
      (node (ref "IC74") (pin "6") (pinfunction "6_6") (pintype "passive"))
      (node (ref "IC75") (pin "6") (pinfunction "6_6") (pintype "passive"))
      (node (ref "IC76") (pin "6") (pinfunction "6_6") (pintype "passive"))
      (node (ref "IC77") (pin "6") (pinfunction "6_6") (pintype "passive"))
    )
    (net (code "440") (name "Net-(IC74-Pad7)") (class "Default")
      (node (ref "IC74") (pin "7") (pinfunction "7_7") (pintype "passive"))
      (node (ref "IC75") (pin "7") (pinfunction "7_7") (pintype "passive"))
      (node (ref "IC76") (pin "7") (pinfunction "7_7") (pintype "passive"))
      (node (ref "IC77") (pin "7") (pinfunction "7_7") (pintype "passive"))
    )
    (net (code "441") (name "Net-(IC74-Pad8)") (class "Default")
      (node (ref "IC74") (pin "8") (pinfunction "8_8") (pintype "passive"))
      (node (ref "IC75") (pin "8") (pinfunction "8_8") (pintype "passive"))
      (node (ref "IC76") (pin "8") (pinfunction "8_8") (pintype "passive"))
      (node (ref "IC77") (pin "8") (pinfunction "8_8") (pintype "passive"))
    )
    (net (code "442") (name "Net-(IC74-Pad9)") (class "Default")
      (node (ref "IC74") (pin "9") (pinfunction "9_9") (pintype "passive"))
      (node (ref "IC75") (pin "9") (pinfunction "9_9") (pintype "passive"))
      (node (ref "IC76") (pin "9") (pinfunction "9_9") (pintype "passive"))
      (node (ref "IC77") (pin "9") (pinfunction "9_9") (pintype "passive"))
    )
    (net (code "443") (name "Net-(IC74-Pad10)") (class "Default")
      (node (ref "IC74") (pin "10") (pinfunction "10_10") (pintype "passive"))
      (node (ref "IC75") (pin "10") (pinfunction "10_10") (pintype "passive"))
      (node (ref "IC76") (pin "10") (pinfunction "10_10") (pintype "passive"))
      (node (ref "IC77") (pin "10") (pinfunction "10_10") (pintype "passive"))
    )
    (net (code "444") (name "Net-(IC74-Pad11)") (class "Default")
      (node (ref "IC74") (pin "11") (pinfunction "11_11") (pintype "passive"))
      (node (ref "IC75") (pin "11") (pinfunction "11_11") (pintype "passive"))
      (node (ref "IC76") (pin "11") (pinfunction "11_11") (pintype "passive"))
      (node (ref "IC77") (pin "11") (pinfunction "11_11") (pintype "passive"))
    )
    (net (code "445") (name "Net-(IC74-Pad12)") (class "Default")
      (node (ref "IC74") (pin "12") (pinfunction "12_12") (pintype "passive"))
      (node (ref "IC75") (pin "12") (pinfunction "12_12") (pintype "passive"))
      (node (ref "IC76") (pin "12") (pinfunction "12_12") (pintype "passive"))
      (node (ref "IC77") (pin "12") (pinfunction "12_12") (pintype "passive"))
    )
    (net (code "446") (name "Net-(IC74-Pad13)") (class "Default")
      (node (ref "IC74") (pin "13") (pinfunction "13_13") (pintype "passive"))
      (node (ref "IC75") (pin "13") (pinfunction "13_13") (pintype "passive"))
      (node (ref "IC76") (pin "13") (pinfunction "13_13") (pintype "passive"))
      (node (ref "IC77") (pin "13") (pinfunction "13_13") (pintype "passive"))
    )
    (net (code "447") (name "Net-(IC74-Pad14)") (class "Default")
      (node (ref "IC74") (pin "14") (pinfunction "14_14") (pintype "passive"))
      (node (ref "IC75") (pin "14") (pinfunction "14_14") (pintype "passive"))
      (node (ref "IC76") (pin "14") (pinfunction "14_14") (pintype "passive"))
      (node (ref "IC77") (pin "14") (pinfunction "14_14") (pintype "passive"))
    )
    (net (code "448") (name "Net-(IC74-Pad15)") (class "Default")
      (node (ref "IC74") (pin "15") (pinfunction "15_15") (pintype "passive"))
      (node (ref "IC75") (pin "15") (pinfunction "15_15") (pintype "passive"))
      (node (ref "IC76") (pin "15") (pinfunction "15_15") (pintype "passive"))
      (node (ref "IC77") (pin "15") (pinfunction "15_15") (pintype "passive"))
    )
    (net (code "449") (name "Net-(IC74-Pad16)") (class "Default")
      (node (ref "IC74") (pin "16") (pinfunction "16_16") (pintype "passive"))
      (node (ref "IC75") (pin "16") (pinfunction "16_16") (pintype "passive"))
      (node (ref "IC76") (pin "16") (pinfunction "16_16") (pintype "passive"))
      (node (ref "IC77") (pin "16") (pinfunction "16_16") (pintype "passive"))
    )
    (net (code "450") (name "Net-(IC74-Pad17)") (class "Default")
      (node (ref "IC74") (pin "17") (pinfunction "17_17") (pintype "passive"))
      (node (ref "IC75") (pin "17") (pinfunction "17_17") (pintype "passive"))
      (node (ref "IC76") (pin "17") (pinfunction "17_17") (pintype "passive"))
      (node (ref "IC77") (pin "17") (pinfunction "17_17") (pintype "passive"))
    )
    (net (code "451") (name "Net-(IC74-Pad18)") (class "Default")
      (node (ref "IC74") (pin "18") (pinfunction "18_18") (pintype "passive"))
      (node (ref "IC75") (pin "18") (pinfunction "18_18") (pintype "passive"))
      (node (ref "IC76") (pin "18") (pinfunction "18_18") (pintype "passive"))
      (node (ref "IC77") (pin "18") (pinfunction "18_18") (pintype "passive"))
    )
    (net (code "452") (name "Net-(IC74-Pad19)") (class "Default")
      (node (ref "IC74") (pin "19") (pinfunction "19_19") (pintype "passive"))
      (node (ref "IC75") (pin "19") (pinfunction "19_19") (pintype "passive"))
      (node (ref "IC76") (pin "19") (pinfunction "19_19") (pintype "passive"))
      (node (ref "IC77") (pin "19") (pinfunction "19_19") (pintype "passive"))
    )
    (net (code "453") (name "Net-(IC74-Pad20)") (class "Default")
      (node (ref "IC74") (pin "20") (pinfunction "20_20") (pintype "passive"))
      (node (ref "IC75") (pin "20") (pinfunction "20_20") (pintype "passive"))
      (node (ref "IC76") (pin "20") (pinfunction "20_20") (pintype "passive"))
      (node (ref "IC77") (pin "20") (pinfunction "20_20") (pintype "passive"))
    )
    (net (code "454") (name "Net-(IC74-Pad21)") (class "Default")
      (node (ref "IC74") (pin "21") (pinfunction "21_21") (pintype "passive"))
      (node (ref "IC75") (pin "21") (pinfunction "21_21") (pintype "passive"))
      (node (ref "IC76") (pin "21") (pinfunction "21_21") (pintype "passive"))
      (node (ref "IC77") (pin "21") (pinfunction "21_21") (pintype "passive"))
    )
    (net (code "455") (name "Net-(IC74-Pad22)") (class "Default")
      (node (ref "IC74") (pin "22") (pinfunction "22_22") (pintype "passive"))
      (node (ref "IC75") (pin "22") (pinfunction "22_22") (pintype "passive"))
      (node (ref "IC76") (pin "22") (pinfunction "22_22") (pintype "passive"))
      (node (ref "IC77") (pin "22") (pinfunction "22_22") (pintype "passive"))
    )
    (net (code "456") (name "Net-(IC74-Pad23)") (class "Default")
      (node (ref "IC74") (pin "23") (pinfunction "23_23") (pintype "passive"))
      (node (ref "IC75") (pin "23") (pinfunction "23_23") (pintype "passive"))
      (node (ref "IC76") (pin "23") (pinfunction "23_23") (pintype "passive"))
      (node (ref "IC77") (pin "23") (pinfunction "23_23") (pintype "passive"))
    )
    (net (code "457") (name "Net-(IC74-Pad24)") (class "Default")
      (node (ref "IC74") (pin "24") (pinfunction "24_24") (pintype "passive"))
      (node (ref "IC75") (pin "24") (pinfunction "24_24") (pintype "passive"))
      (node (ref "IC76") (pin "24") (pinfunction "24_24") (pintype "passive"))
      (node (ref "IC77") (pin "24") (pinfunction "24_24") (pintype "passive"))
    )
    (net (code "458") (name "Net-(IC78-Pad1)") (class "Default")
      (node (ref "IC78") (pin "1") (pinfunction "1_1") (pintype "passive"))
      (node (ref "IC79") (pin "1") (pinfunction "1_1") (pintype "passive"))
      (node (ref "IC80") (pin "1") (pinfunction "1_1") (pintype "passive"))
      (node (ref "IC81") (pin "1") (pinfunction "1_1") (pintype "passive"))
    )
    (net (code "459") (name "Net-(IC78-Pad2)") (class "Default")
      (node (ref "IC78") (pin "2") (pinfunction "2_2") (pintype "passive"))
      (node (ref "IC79") (pin "2") (pinfunction "2_2") (pintype "passive"))
      (node (ref "IC80") (pin "2") (pinfunction "2_2") (pintype "passive"))
      (node (ref "IC81") (pin "2") (pinfunction "2_2") (pintype "passive"))
    )
    (net (code "460") (name "Net-(IC78-Pad3)") (class "Default")
      (node (ref "IC78") (pin "3") (pinfunction "3_3") (pintype "passive"))
      (node (ref "IC79") (pin "3") (pinfunction "3_3") (pintype "passive"))
      (node (ref "IC80") (pin "3") (pinfunction "3_3") (pintype "passive"))
      (node (ref "IC81") (pin "3") (pinfunction "3_3") (pintype "passive"))
    )
    (net (code "461") (name "Net-(IC78-Pad4)") (class "Default")
      (node (ref "IC78") (pin "4") (pinfunction "4_4") (pintype "passive"))
      (node (ref "IC79") (pin "4") (pinfunction "4_4") (pintype "passive"))
      (node (ref "IC80") (pin "4") (pinfunction "4_4") (pintype "passive"))
      (node (ref "IC81") (pin "4") (pinfunction "4_4") (pintype "passive"))
    )
    (net (code "462") (name "Net-(IC78-Pad5)") (class "Default")
      (node (ref "IC78") (pin "5") (pinfunction "5_5") (pintype "passive"))
      (node (ref "IC79") (pin "5") (pinfunction "5_5") (pintype "passive"))
      (node (ref "IC80") (pin "5") (pinfunction "5_5") (pintype "passive"))
      (node (ref "IC81") (pin "5") (pinfunction "5_5") (pintype "passive"))
    )
    (net (code "463") (name "Net-(IC78-Pad6)") (class "Default")
      (node (ref "IC78") (pin "6") (pinfunction "6_6") (pintype "passive"))
      (node (ref "IC79") (pin "6") (pinfunction "6_6") (pintype "passive"))
      (node (ref "IC80") (pin "6") (pinfunction "6_6") (pintype "passive"))
      (node (ref "IC81") (pin "6") (pinfunction "6_6") (pintype "passive"))
    )
    (net (code "464") (name "Net-(IC78-Pad7)") (class "Default")
      (node (ref "IC78") (pin "7") (pinfunction "7_7") (pintype "passive"))
      (node (ref "IC79") (pin "7") (pinfunction "7_7") (pintype "passive"))
      (node (ref "IC80") (pin "7") (pinfunction "7_7") (pintype "passive"))
      (node (ref "IC81") (pin "7") (pinfunction "7_7") (pintype "passive"))
    )
    (net (code "465") (name "Net-(IC78-Pad8)") (class "Default")
      (node (ref "IC78") (pin "8") (pinfunction "8_8") (pintype "passive"))
      (node (ref "IC79") (pin "8") (pinfunction "8_8") (pintype "passive"))
      (node (ref "IC80") (pin "8") (pinfunction "8_8") (pintype "passive"))
      (node (ref "IC81") (pin "8") (pinfunction "8_8") (pintype "passive"))
    )
    (net (code "466") (name "Net-(IC78-Pad9)") (class "Default")
      (node (ref "IC78") (pin "9") (pinfunction "9_9") (pintype "passive"))
      (node (ref "IC79") (pin "9") (pinfunction "9_9") (pintype "passive"))
      (node (ref "IC80") (pin "9") (pinfunction "9_9") (pintype "passive"))
      (node (ref "IC81") (pin "9") (pinfunction "9_9") (pintype "passive"))
    )
    (net (code "467") (name "Net-(IC78-Pad10)") (class "Default")
      (node (ref "IC78") (pin "10") (pinfunction "10_10") (pintype "passive"))
      (node (ref "IC79") (pin "10") (pinfunction "10_10") (pintype "passive"))
      (node (ref "IC80") (pin "10") (pinfunction "10_10") (pintype "passive"))
      (node (ref "IC81") (pin "10") (pinfunction "10_10") (pintype "passive"))
    )
    (net (code "468") (name "Net-(IC78-Pad11)") (class "Default")
      (node (ref "IC78") (pin "11") (pinfunction "11_11") (pintype "passive"))
      (node (ref "IC79") (pin "11") (pinfunction "11_11") (pintype "passive"))
      (node (ref "IC80") (pin "11") (pinfunction "11_11") (pintype "passive"))
      (node (ref "IC81") (pin "11") (pinfunction "11_11") (pintype "passive"))
    )
    (net (code "469") (name "Net-(IC78-Pad12)") (class "Default")
      (node (ref "IC78") (pin "12") (pinfunction "12_12") (pintype "passive"))
      (node (ref "IC79") (pin "12") (pinfunction "12_12") (pintype "passive"))
      (node (ref "IC80") (pin "12") (pinfunction "12_12") (pintype "passive"))
      (node (ref "IC81") (pin "12") (pinfunction "12_12") (pintype "passive"))
    )
    (net (code "470") (name "Net-(IC78-Pad13)") (class "Default")
      (node (ref "IC78") (pin "13") (pinfunction "13_13") (pintype "passive"))
      (node (ref "IC79") (pin "13") (pinfunction "13_13") (pintype "passive"))
      (node (ref "IC80") (pin "13") (pinfunction "13_13") (pintype "passive"))
      (node (ref "IC81") (pin "13") (pinfunction "13_13") (pintype "passive"))
    )
    (net (code "471") (name "Net-(IC78-Pad14)") (class "Default")
      (node (ref "IC78") (pin "14") (pinfunction "14_14") (pintype "passive"))
      (node (ref "IC79") (pin "14") (pinfunction "14_14") (pintype "passive"))
      (node (ref "IC80") (pin "14") (pinfunction "14_14") (pintype "passive"))
      (node (ref "IC81") (pin "14") (pinfunction "14_14") (pintype "passive"))
    )
    (net (code "472") (name "Net-(IC78-Pad15)") (class "Default")
      (node (ref "IC78") (pin "15") (pinfunction "15_15") (pintype "passive"))
      (node (ref "IC79") (pin "15") (pinfunction "15_15") (pintype "passive"))
      (node (ref "IC80") (pin "15") (pinfunction "15_15") (pintype "passive"))
      (node (ref "IC81") (pin "15") (pinfunction "15_15") (pintype "passive"))
    )
    (net (code "473") (name "Net-(IC78-Pad16)") (class "Default")
      (node (ref "IC78") (pin "16") (pinfunction "16_16") (pintype "passive"))
      (node (ref "IC79") (pin "16") (pinfunction "16_16") (pintype "passive"))
      (node (ref "IC80") (pin "16") (pinfunction "16_16") (pintype "passive"))
      (node (ref "IC81") (pin "16") (pinfunction "16_16") (pintype "passive"))
    )
    (net (code "474") (name "Net-(IC78-Pad17)") (class "Default")
      (node (ref "IC78") (pin "17") (pinfunction "17_17") (pintype "passive"))
      (node (ref "IC79") (pin "17") (pinfunction "17_17") (pintype "passive"))
      (node (ref "IC80") (pin "17") (pinfunction "17_17") (pintype "passive"))
      (node (ref "IC81") (pin "17") (pinfunction "17_17") (pintype "passive"))
    )
    (net (code "475") (name "Net-(IC78-Pad18)") (class "Default")
      (node (ref "IC78") (pin "18") (pinfunction "18_18") (pintype "passive"))
      (node (ref "IC79") (pin "18") (pinfunction "18_18") (pintype "passive"))
      (node (ref "IC80") (pin "18") (pinfunction "18_18") (pintype "passive"))
      (node (ref "IC81") (pin "18") (pinfunction "18_18") (pintype "passive"))
    )
    (net (code "476") (name "Net-(IC78-Pad19)") (class "Default")
      (node (ref "IC78") (pin "19") (pinfunction "19_19") (pintype "passive"))
      (node (ref "IC79") (pin "19") (pinfunction "19_19") (pintype "passive"))
      (node (ref "IC80") (pin "19") (pinfunction "19_19") (pintype "passive"))
      (node (ref "IC81") (pin "19") (pinfunction "19_19") (pintype "passive"))
    )
    (net (code "477") (name "Net-(IC78-Pad20)") (class "Default")
      (node (ref "IC78") (pin "20") (pinfunction "20_20") (pintype "passive"))
      (node (ref "IC79") (pin "20") (pinfunction "20_20") (pintype "passive"))
      (node (ref "IC80") (pin "20") (pinfunction "20_20") (pintype "passive"))
      (node (ref "IC81") (pin "20") (pinfunction "20_20") (pintype "passive"))
    )
    (net (code "478") (name "Net-(IC78-Pad21)") (class "Default")
      (node (ref "IC78") (pin "21") (pinfunction "21_21") (pintype "passive"))
      (node (ref "IC79") (pin "21") (pinfunction "21_21") (pintype "passive"))
      (node (ref "IC80") (pin "21") (pinfunction "21_21") (pintype "passive"))
      (node (ref "IC81") (pin "21") (pinfunction "21_21") (pintype "passive"))
    )
    (net (code "479") (name "Net-(IC78-Pad22)") (class "Default")
      (node (ref "IC78") (pin "22") (pinfunction "22_22") (pintype "passive"))
      (node (ref "IC79") (pin "22") (pinfunction "22_22") (pintype "passive"))
      (node (ref "IC80") (pin "22") (pinfunction "22_22") (pintype "passive"))
      (node (ref "IC81") (pin "22") (pinfunction "22_22") (pintype "passive"))
    )
    (net (code "480") (name "Net-(IC78-Pad23)") (class "Default")
      (node (ref "IC78") (pin "23") (pinfunction "23_23") (pintype "passive"))
      (node (ref "IC79") (pin "23") (pinfunction "23_23") (pintype "passive"))
      (node (ref "IC80") (pin "23") (pinfunction "23_23") (pintype "passive"))
      (node (ref "IC81") (pin "23") (pinfunction "23_23") (pintype "passive"))
    )
    (net (code "481") (name "Net-(IC78-Pad24)") (class "Default")
      (node (ref "IC78") (pin "24") (pinfunction "24_24") (pintype "passive"))
      (node (ref "IC79") (pin "24") (pinfunction "24_24") (pintype "passive"))
      (node (ref "IC80") (pin "24") (pinfunction "24_24") (pintype "passive"))
      (node (ref "IC81") (pin "24") (pinfunction "24_24") (pintype "passive"))
    )
    (net (code "482") (name "Net-(IC82-Pad1)") (class "Default")
      (node (ref "IC82") (pin "1") (pinfunction "1_1") (pintype "passive"))
      (node (ref "IC83") (pin "1") (pinfunction "1_1") (pintype "passive"))
      (node (ref "IC84") (pin "1") (pinfunction "1_1") (pintype "passive"))
      (node (ref "IC85") (pin "1") (pinfunction "1_1") (pintype "passive"))
    )
    (net (code "483") (name "Net-(IC82-Pad2)") (class "Default")
      (node (ref "IC82") (pin "2") (pinfunction "2_2") (pintype "passive"))
      (node (ref "IC83") (pin "2") (pinfunction "2_2") (pintype "passive"))
      (node (ref "IC84") (pin "2") (pinfunction "2_2") (pintype "passive"))
      (node (ref "IC85") (pin "2") (pinfunction "2_2") (pintype "passive"))
    )
    (net (code "484") (name "Net-(IC82-Pad3)") (class "Default")
      (node (ref "IC82") (pin "3") (pinfunction "3_3") (pintype "passive"))
      (node (ref "IC83") (pin "3") (pinfunction "3_3") (pintype "passive"))
      (node (ref "IC84") (pin "3") (pinfunction "3_3") (pintype "passive"))
      (node (ref "IC85") (pin "3") (pinfunction "3_3") (pintype "passive"))
    )
    (net (code "485") (name "Net-(IC82-Pad4)") (class "Default")
      (node (ref "IC82") (pin "4") (pinfunction "4_4") (pintype "passive"))
      (node (ref "IC83") (pin "4") (pinfunction "4_4") (pintype "passive"))
      (node (ref "IC84") (pin "4") (pinfunction "4_4") (pintype "passive"))
      (node (ref "IC85") (pin "4") (pinfunction "4_4") (pintype "passive"))
    )
    (net (code "486") (name "Net-(IC82-Pad5)") (class "Default")
      (node (ref "IC82") (pin "5") (pinfunction "5_5") (pintype "passive"))
      (node (ref "IC83") (pin "5") (pinfunction "5_5") (pintype "passive"))
      (node (ref "IC84") (pin "5") (pinfunction "5_5") (pintype "passive"))
      (node (ref "IC85") (pin "5") (pinfunction "5_5") (pintype "passive"))
    )
    (net (code "487") (name "Net-(IC82-Pad6)") (class "Default")
      (node (ref "IC82") (pin "6") (pinfunction "6_6") (pintype "passive"))
      (node (ref "IC83") (pin "6") (pinfunction "6_6") (pintype "passive"))
      (node (ref "IC84") (pin "6") (pinfunction "6_6") (pintype "passive"))
      (node (ref "IC85") (pin "6") (pinfunction "6_6") (pintype "passive"))
    )
    (net (code "488") (name "Net-(IC82-Pad7)") (class "Default")
      (node (ref "IC82") (pin "7") (pinfunction "7_7") (pintype "passive"))
      (node (ref "IC83") (pin "7") (pinfunction "7_7") (pintype "passive"))
      (node (ref "IC84") (pin "7") (pinfunction "7_7") (pintype "passive"))
      (node (ref "IC85") (pin "7") (pinfunction "7_7") (pintype "passive"))
    )
    (net (code "489") (name "Net-(IC82-Pad8)") (class "Default")
      (node (ref "IC82") (pin "8") (pinfunction "8_8") (pintype "passive"))
      (node (ref "IC83") (pin "8") (pinfunction "8_8") (pintype "passive"))
      (node (ref "IC84") (pin "8") (pinfunction "8_8") (pintype "passive"))
      (node (ref "IC85") (pin "8") (pinfunction "8_8") (pintype "passive"))
    )
    (net (code "490") (name "Net-(IC82-Pad9)") (class "Default")
      (node (ref "IC82") (pin "9") (pinfunction "9_9") (pintype "passive"))
      (node (ref "IC83") (pin "9") (pinfunction "9_9") (pintype "passive"))
      (node (ref "IC84") (pin "9") (pinfunction "9_9") (pintype "passive"))
      (node (ref "IC85") (pin "9") (pinfunction "9_9") (pintype "passive"))
    )
    (net (code "491") (name "Net-(IC82-Pad10)") (class "Default")
      (node (ref "IC82") (pin "10") (pinfunction "10_10") (pintype "passive"))
      (node (ref "IC83") (pin "10") (pinfunction "10_10") (pintype "passive"))
      (node (ref "IC84") (pin "10") (pinfunction "10_10") (pintype "passive"))
      (node (ref "IC85") (pin "10") (pinfunction "10_10") (pintype "passive"))
    )
    (net (code "492") (name "Net-(IC82-Pad11)") (class "Default")
      (node (ref "IC82") (pin "11") (pinfunction "11_11") (pintype "passive"))
      (node (ref "IC83") (pin "11") (pinfunction "11_11") (pintype "passive"))
      (node (ref "IC84") (pin "11") (pinfunction "11_11") (pintype "passive"))
      (node (ref "IC85") (pin "11") (pinfunction "11_11") (pintype "passive"))
    )
    (net (code "493") (name "Net-(IC82-Pad12)") (class "Default")
      (node (ref "IC82") (pin "12") (pinfunction "12_12") (pintype "passive"))
      (node (ref "IC83") (pin "12") (pinfunction "12_12") (pintype "passive"))
      (node (ref "IC84") (pin "12") (pinfunction "12_12") (pintype "passive"))
      (node (ref "IC85") (pin "12") (pinfunction "12_12") (pintype "passive"))
    )
    (net (code "494") (name "Net-(IC82-Pad13)") (class "Default")
      (node (ref "IC82") (pin "13") (pinfunction "13_13") (pintype "passive"))
      (node (ref "IC83") (pin "13") (pinfunction "13_13") (pintype "passive"))
      (node (ref "IC84") (pin "13") (pinfunction "13_13") (pintype "passive"))
      (node (ref "IC85") (pin "13") (pinfunction "13_13") (pintype "passive"))
    )
    (net (code "495") (name "Net-(IC82-Pad14)") (class "Default")
      (node (ref "IC82") (pin "14") (pinfunction "14_14") (pintype "passive"))
      (node (ref "IC83") (pin "14") (pinfunction "14_14") (pintype "passive"))
      (node (ref "IC84") (pin "14") (pinfunction "14_14") (pintype "passive"))
      (node (ref "IC85") (pin "14") (pinfunction "14_14") (pintype "passive"))
    )
    (net (code "496") (name "Net-(IC82-Pad15)") (class "Default")
      (node (ref "IC82") (pin "15") (pinfunction "15_15") (pintype "passive"))
      (node (ref "IC83") (pin "15") (pinfunction "15_15") (pintype "passive"))
      (node (ref "IC84") (pin "15") (pinfunction "15_15") (pintype "passive"))
      (node (ref "IC85") (pin "15") (pinfunction "15_15") (pintype "passive"))
    )
    (net (code "497") (name "Net-(IC82-Pad16)") (class "Default")
      (node (ref "IC82") (pin "16") (pinfunction "16_16") (pintype "passive"))
      (node (ref "IC83") (pin "16") (pinfunction "16_16") (pintype "passive"))
      (node (ref "IC84") (pin "16") (pinfunction "16_16") (pintype "passive"))
      (node (ref "IC85") (pin "16") (pinfunction "16_16") (pintype "passive"))
    )
    (net (code "498") (name "Net-(IC82-Pad17)") (class "Default")
      (node (ref "IC82") (pin "17") (pinfunction "17_17") (pintype "passive"))
      (node (ref "IC83") (pin "17") (pinfunction "17_17") (pintype "passive"))
      (node (ref "IC84") (pin "17") (pinfunction "17_17") (pintype "passive"))
      (node (ref "IC85") (pin "17") (pinfunction "17_17") (pintype "passive"))
    )
    (net (code "499") (name "Net-(IC82-Pad18)") (class "Default")
      (node (ref "IC82") (pin "18") (pinfunction "18_18") (pintype "passive"))
      (node (ref "IC83") (pin "18") (pinfunction "18_18") (pintype "passive"))
      (node (ref "IC84") (pin "18") (pinfunction "18_18") (pintype "passive"))
      (node (ref "IC85") (pin "18") (pinfunction "18_18") (pintype "passive"))
    )
    (net (code "500") (name "Net-(IC82-Pad19)") (class "Default")
      (node (ref "IC82") (pin "19") (pinfunction "19_19") (pintype "passive"))
      (node (ref "IC83") (pin "19") (pinfunction "19_19") (pintype "passive"))
      (node (ref "IC84") (pin "19") (pinfunction "19_19") (pintype "passive"))
      (node (ref "IC85") (pin "19") (pinfunction "19_19") (pintype "passive"))
    )
    (net (code "501") (name "Net-(IC82-Pad20)") (class "Default")
      (node (ref "IC82") (pin "20") (pinfunction "20_20") (pintype "passive"))
      (node (ref "IC83") (pin "20") (pinfunction "20_20") (pintype "passive"))
      (node (ref "IC84") (pin "20") (pinfunction "20_20") (pintype "passive"))
      (node (ref "IC85") (pin "20") (pinfunction "20_20") (pintype "passive"))
    )
    (net (code "502") (name "Net-(IC82-Pad21)") (class "Default")
      (node (ref "IC82") (pin "21") (pinfunction "21_21") (pintype "passive"))
      (node (ref "IC83") (pin "21") (pinfunction "21_21") (pintype "passive"))
      (node (ref "IC84") (pin "21") (pinfunction "21_21") (pintype "passive"))
      (node (ref "IC85") (pin "21") (pinfunction "21_21") (pintype "passive"))
    )
    (net (code "503") (name "Net-(IC82-Pad22)") (class "Default")
      (node (ref "IC82") (pin "22") (pinfunction "22_22") (pintype "passive"))
      (node (ref "IC83") (pin "22") (pinfunction "22_22") (pintype "passive"))
      (node (ref "IC84") (pin "22") (pinfunction "22_22") (pintype "passive"))
      (node (ref "IC85") (pin "22") (pinfunction "22_22") (pintype "passive"))
    )
    (net (code "504") (name "Net-(IC82-Pad23)") (class "Default")
      (node (ref "IC82") (pin "23") (pinfunction "23_23") (pintype "passive"))
      (node (ref "IC83") (pin "23") (pinfunction "23_23") (pintype "passive"))
      (node (ref "IC84") (pin "23") (pinfunction "23_23") (pintype "passive"))
      (node (ref "IC85") (pin "23") (pinfunction "23_23") (pintype "passive"))
    )
    (net (code "505") (name "Net-(IC82-Pad24)") (class "Default")
      (node (ref "IC82") (pin "24") (pinfunction "24_24") (pintype "passive"))
      (node (ref "IC83") (pin "24") (pinfunction "24_24") (pintype "passive"))
      (node (ref "IC84") (pin "24") (pinfunction "24_24") (pintype "passive"))
      (node (ref "IC85") (pin "24") (pinfunction "24_24") (pintype "passive"))
    )
    (net (code "506") (name "Net-(IC86-Pad1)") (class "Default")
      (node (ref "IC86") (pin "1") (pinfunction "1_1") (pintype "passive"))
      (node (ref "IC87") (pin "1") (pinfunction "1_1") (pintype "passive"))
      (node (ref "IC88") (pin "1") (pinfunction "1_1") (pintype "passive"))
      (node (ref "IC89") (pin "1") (pinfunction "1_1") (pintype "passive"))
    )
    (net (code "507") (name "Net-(IC86-Pad2)") (class "Default")
      (node (ref "IC86") (pin "2") (pinfunction "2_2") (pintype "passive"))
      (node (ref "IC87") (pin "2") (pinfunction "2_2") (pintype "passive"))
      (node (ref "IC88") (pin "2") (pinfunction "2_2") (pintype "passive"))
      (node (ref "IC89") (pin "2") (pinfunction "2_2") (pintype "passive"))
    )
    (net (code "508") (name "Net-(IC86-Pad3)") (class "Default")
      (node (ref "IC86") (pin "3") (pinfunction "3_3") (pintype "passive"))
      (node (ref "IC87") (pin "3") (pinfunction "3_3") (pintype "passive"))
      (node (ref "IC88") (pin "3") (pinfunction "3_3") (pintype "passive"))
      (node (ref "IC89") (pin "3") (pinfunction "3_3") (pintype "passive"))
    )
    (net (code "509") (name "Net-(IC86-Pad4)") (class "Default")
      (node (ref "IC86") (pin "4") (pinfunction "4_4") (pintype "passive"))
      (node (ref "IC87") (pin "4") (pinfunction "4_4") (pintype "passive"))
      (node (ref "IC88") (pin "4") (pinfunction "4_4") (pintype "passive"))
      (node (ref "IC89") (pin "4") (pinfunction "4_4") (pintype "passive"))
    )
    (net (code "510") (name "Net-(IC86-Pad5)") (class "Default")
      (node (ref "IC86") (pin "5") (pinfunction "5_5") (pintype "passive"))
      (node (ref "IC87") (pin "5") (pinfunction "5_5") (pintype "passive"))
      (node (ref "IC88") (pin "5") (pinfunction "5_5") (pintype "passive"))
      (node (ref "IC89") (pin "5") (pinfunction "5_5") (pintype "passive"))
    )
    (net (code "511") (name "Net-(IC86-Pad6)") (class "Default")
      (node (ref "IC86") (pin "6") (pinfunction "6_6") (pintype "passive"))
      (node (ref "IC87") (pin "6") (pinfunction "6_6") (pintype "passive"))
      (node (ref "IC88") (pin "6") (pinfunction "6_6") (pintype "passive"))
      (node (ref "IC89") (pin "6") (pinfunction "6_6") (pintype "passive"))
    )
    (net (code "512") (name "Net-(IC86-Pad7)") (class "Default")
      (node (ref "IC86") (pin "7") (pinfunction "7_7") (pintype "passive"))
      (node (ref "IC87") (pin "7") (pinfunction "7_7") (pintype "passive"))
      (node (ref "IC88") (pin "7") (pinfunction "7_7") (pintype "passive"))
      (node (ref "IC89") (pin "7") (pinfunction "7_7") (pintype "passive"))
    )
    (net (code "513") (name "Net-(IC86-Pad8)") (class "Default")
      (node (ref "IC86") (pin "8") (pinfunction "8_8") (pintype "passive"))
      (node (ref "IC87") (pin "8") (pinfunction "8_8") (pintype "passive"))
      (node (ref "IC88") (pin "8") (pinfunction "8_8") (pintype "passive"))
      (node (ref "IC89") (pin "8") (pinfunction "8_8") (pintype "passive"))
    )
    (net (code "514") (name "Net-(IC86-Pad9)") (class "Default")
      (node (ref "IC86") (pin "9") (pinfunction "9_9") (pintype "passive"))
      (node (ref "IC87") (pin "9") (pinfunction "9_9") (pintype "passive"))
      (node (ref "IC88") (pin "9") (pinfunction "9_9") (pintype "passive"))
      (node (ref "IC89") (pin "9") (pinfunction "9_9") (pintype "passive"))
    )
    (net (code "515") (name "Net-(IC86-Pad10)") (class "Default")
      (node (ref "IC86") (pin "10") (pinfunction "10_10") (pintype "passive"))
      (node (ref "IC87") (pin "10") (pinfunction "10_10") (pintype "passive"))
      (node (ref "IC88") (pin "10") (pinfunction "10_10") (pintype "passive"))
      (node (ref "IC89") (pin "10") (pinfunction "10_10") (pintype "passive"))
    )
    (net (code "516") (name "Net-(IC86-Pad11)") (class "Default")
      (node (ref "IC86") (pin "11") (pinfunction "11_11") (pintype "passive"))
      (node (ref "IC87") (pin "11") (pinfunction "11_11") (pintype "passive"))
      (node (ref "IC88") (pin "11") (pinfunction "11_11") (pintype "passive"))
      (node (ref "IC89") (pin "11") (pinfunction "11_11") (pintype "passive"))
    )
    (net (code "517") (name "Net-(IC86-Pad12)") (class "Default")
      (node (ref "IC86") (pin "12") (pinfunction "12_12") (pintype "passive"))
      (node (ref "IC87") (pin "12") (pinfunction "12_12") (pintype "passive"))
      (node (ref "IC88") (pin "12") (pinfunction "12_12") (pintype "passive"))
      (node (ref "IC89") (pin "12") (pinfunction "12_12") (pintype "passive"))
    )
    (net (code "518") (name "Net-(IC86-Pad13)") (class "Default")
      (node (ref "IC86") (pin "13") (pinfunction "13_13") (pintype "passive"))
      (node (ref "IC87") (pin "13") (pinfunction "13_13") (pintype "passive"))
      (node (ref "IC88") (pin "13") (pinfunction "13_13") (pintype "passive"))
      (node (ref "IC89") (pin "13") (pinfunction "13_13") (pintype "passive"))
    )
    (net (code "519") (name "Net-(IC86-Pad14)") (class "Default")
      (node (ref "IC86") (pin "14") (pinfunction "14_14") (pintype "passive"))
      (node (ref "IC87") (pin "14") (pinfunction "14_14") (pintype "passive"))
      (node (ref "IC88") (pin "14") (pinfunction "14_14") (pintype "passive"))
      (node (ref "IC89") (pin "14") (pinfunction "14_14") (pintype "passive"))
    )
    (net (code "520") (name "Net-(IC86-Pad15)") (class "Default")
      (node (ref "IC86") (pin "15") (pinfunction "15_15") (pintype "passive"))
      (node (ref "IC87") (pin "15") (pinfunction "15_15") (pintype "passive"))
      (node (ref "IC88") (pin "15") (pinfunction "15_15") (pintype "passive"))
      (node (ref "IC89") (pin "15") (pinfunction "15_15") (pintype "passive"))
    )
    (net (code "521") (name "Net-(IC86-Pad16)") (class "Default")
      (node (ref "IC86") (pin "16") (pinfunction "16_16") (pintype "passive"))
      (node (ref "IC87") (pin "16") (pinfunction "16_16") (pintype "passive"))
      (node (ref "IC88") (pin "16") (pinfunction "16_16") (pintype "passive"))
      (node (ref "IC89") (pin "16") (pinfunction "16_16") (pintype "passive"))
    )
    (net (code "522") (name "Net-(IC86-Pad17)") (class "Default")
      (node (ref "IC86") (pin "17") (pinfunction "17_17") (pintype "passive"))
      (node (ref "IC87") (pin "17") (pinfunction "17_17") (pintype "passive"))
      (node (ref "IC88") (pin "17") (pinfunction "17_17") (pintype "passive"))
      (node (ref "IC89") (pin "17") (pinfunction "17_17") (pintype "passive"))
    )
    (net (code "523") (name "Net-(IC86-Pad18)") (class "Default")
      (node (ref "IC86") (pin "18") (pinfunction "18_18") (pintype "passive"))
      (node (ref "IC87") (pin "18") (pinfunction "18_18") (pintype "passive"))
      (node (ref "IC88") (pin "18") (pinfunction "18_18") (pintype "passive"))
      (node (ref "IC89") (pin "18") (pinfunction "18_18") (pintype "passive"))
    )
    (net (code "524") (name "Net-(IC86-Pad19)") (class "Default")
      (node (ref "IC86") (pin "19") (pinfunction "19_19") (pintype "passive"))
      (node (ref "IC87") (pin "19") (pinfunction "19_19") (pintype "passive"))
      (node (ref "IC88") (pin "19") (pinfunction "19_19") (pintype "passive"))
      (node (ref "IC89") (pin "19") (pinfunction "19_19") (pintype "passive"))
    )
    (net (code "525") (name "Net-(IC86-Pad20)") (class "Default")
      (node (ref "IC86") (pin "20") (pinfunction "20_20") (pintype "passive"))
      (node (ref "IC87") (pin "20") (pinfunction "20_20") (pintype "passive"))
      (node (ref "IC88") (pin "20") (pinfunction "20_20") (pintype "passive"))
      (node (ref "IC89") (pin "20") (pinfunction "20_20") (pintype "passive"))
    )
    (net (code "526") (name "Net-(IC86-Pad21)") (class "Default")
      (node (ref "IC86") (pin "21") (pinfunction "21_21") (pintype "passive"))
      (node (ref "IC87") (pin "21") (pinfunction "21_21") (pintype "passive"))
      (node (ref "IC88") (pin "21") (pinfunction "21_21") (pintype "passive"))
      (node (ref "IC89") (pin "21") (pinfunction "21_21") (pintype "passive"))
    )
    (net (code "527") (name "Net-(IC86-Pad22)") (class "Default")
      (node (ref "IC86") (pin "22") (pinfunction "22_22") (pintype "passive"))
      (node (ref "IC87") (pin "22") (pinfunction "22_22") (pintype "passive"))
      (node (ref "IC88") (pin "22") (pinfunction "22_22") (pintype "passive"))
      (node (ref "IC89") (pin "22") (pinfunction "22_22") (pintype "passive"))
    )
    (net (code "528") (name "Net-(IC86-Pad23)") (class "Default")
      (node (ref "IC86") (pin "23") (pinfunction "23_23") (pintype "passive"))
      (node (ref "IC87") (pin "23") (pinfunction "23_23") (pintype "passive"))
      (node (ref "IC88") (pin "23") (pinfunction "23_23") (pintype "passive"))
      (node (ref "IC89") (pin "23") (pinfunction "23_23") (pintype "passive"))
    )
    (net (code "529") (name "Net-(IC86-Pad24)") (class "Default")
      (node (ref "IC86") (pin "24") (pinfunction "24_24") (pintype "passive"))
      (node (ref "IC87") (pin "24") (pinfunction "24_24") (pintype "passive"))
      (node (ref "IC88") (pin "24") (pinfunction "24_24") (pintype "passive"))
      (node (ref "IC89") (pin "24") (pinfunction "24_24") (pintype "passive"))
    )
    (net (code "530") (name "Net-(IC90-Pad1)") (class "Default")
      (node (ref "IC90") (pin "1") (pinfunction "1_1") (pintype "passive"))
      (node (ref "IC91") (pin "1") (pinfunction "1_1") (pintype "passive"))
      (node (ref "IC92") (pin "1") (pinfunction "1_1") (pintype "passive"))
      (node (ref "IC93") (pin "1") (pinfunction "1_1") (pintype "passive"))
    )
    (net (code "531") (name "Net-(IC90-Pad2)") (class "Default")
      (node (ref "IC90") (pin "2") (pinfunction "2_2") (pintype "passive"))
      (node (ref "IC91") (pin "2") (pinfunction "2_2") (pintype "passive"))
      (node (ref "IC92") (pin "2") (pinfunction "2_2") (pintype "passive"))
      (node (ref "IC93") (pin "2") (pinfunction "2_2") (pintype "passive"))
    )
    (net (code "532") (name "Net-(IC90-Pad3)") (class "Default")
      (node (ref "IC90") (pin "3") (pinfunction "3_3") (pintype "passive"))
      (node (ref "IC91") (pin "3") (pinfunction "3_3") (pintype "passive"))
      (node (ref "IC92") (pin "3") (pinfunction "3_3") (pintype "passive"))
      (node (ref "IC93") (pin "3") (pinfunction "3_3") (pintype "passive"))
    )
    (net (code "533") (name "Net-(IC90-Pad4)") (class "Default")
      (node (ref "IC90") (pin "4") (pinfunction "4_4") (pintype "passive"))
      (node (ref "IC91") (pin "4") (pinfunction "4_4") (pintype "passive"))
      (node (ref "IC92") (pin "4") (pinfunction "4_4") (pintype "passive"))
      (node (ref "IC93") (pin "4") (pinfunction "4_4") (pintype "passive"))
    )
    (net (code "534") (name "Net-(IC90-Pad5)") (class "Default")
      (node (ref "IC90") (pin "5") (pinfunction "5_5") (pintype "passive"))
      (node (ref "IC91") (pin "5") (pinfunction "5_5") (pintype "passive"))
      (node (ref "IC92") (pin "5") (pinfunction "5_5") (pintype "passive"))
      (node (ref "IC93") (pin "5") (pinfunction "5_5") (pintype "passive"))
    )
    (net (code "535") (name "Net-(IC90-Pad6)") (class "Default")
      (node (ref "IC90") (pin "6") (pinfunction "6_6") (pintype "passive"))
      (node (ref "IC91") (pin "6") (pinfunction "6_6") (pintype "passive"))
      (node (ref "IC92") (pin "6") (pinfunction "6_6") (pintype "passive"))
      (node (ref "IC93") (pin "6") (pinfunction "6_6") (pintype "passive"))
    )
    (net (code "536") (name "Net-(IC90-Pad7)") (class "Default")
      (node (ref "IC90") (pin "7") (pinfunction "7_7") (pintype "passive"))
      (node (ref "IC91") (pin "7") (pinfunction "7_7") (pintype "passive"))
      (node (ref "IC92") (pin "7") (pinfunction "7_7") (pintype "passive"))
      (node (ref "IC93") (pin "7") (pinfunction "7_7") (pintype "passive"))
    )
    (net (code "537") (name "Net-(IC90-Pad8)") (class "Default")
      (node (ref "IC90") (pin "8") (pinfunction "8_8") (pintype "passive"))
      (node (ref "IC91") (pin "8") (pinfunction "8_8") (pintype "passive"))
      (node (ref "IC92") (pin "8") (pinfunction "8_8") (pintype "passive"))
      (node (ref "IC93") (pin "8") (pinfunction "8_8") (pintype "passive"))
    )
    (net (code "538") (name "Net-(IC90-Pad9)") (class "Default")
      (node (ref "IC90") (pin "9") (pinfunction "9_9") (pintype "passive"))
      (node (ref "IC91") (pin "9") (pinfunction "9_9") (pintype "passive"))
      (node (ref "IC92") (pin "9") (pinfunction "9_9") (pintype "passive"))
      (node (ref "IC93") (pin "9") (pinfunction "9_9") (pintype "passive"))
    )
    (net (code "539") (name "Net-(IC90-Pad10)") (class "Default")
      (node (ref "IC90") (pin "10") (pinfunction "10_10") (pintype "passive"))
      (node (ref "IC91") (pin "10") (pinfunction "10_10") (pintype "passive"))
      (node (ref "IC92") (pin "10") (pinfunction "10_10") (pintype "passive"))
      (node (ref "IC93") (pin "10") (pinfunction "10_10") (pintype "passive"))
    )
    (net (code "540") (name "Net-(IC90-Pad11)") (class "Default")
      (node (ref "IC90") (pin "11") (pinfunction "11_11") (pintype "passive"))
      (node (ref "IC91") (pin "11") (pinfunction "11_11") (pintype "passive"))
      (node (ref "IC92") (pin "11") (pinfunction "11_11") (pintype "passive"))
      (node (ref "IC93") (pin "11") (pinfunction "11_11") (pintype "passive"))
    )
    (net (code "541") (name "Net-(IC90-Pad12)") (class "Default")
      (node (ref "IC90") (pin "12") (pinfunction "12_12") (pintype "passive"))
      (node (ref "IC91") (pin "12") (pinfunction "12_12") (pintype "passive"))
      (node (ref "IC92") (pin "12") (pinfunction "12_12") (pintype "passive"))
      (node (ref "IC93") (pin "12") (pinfunction "12_12") (pintype "passive"))
    )
    (net (code "542") (name "Net-(IC90-Pad13)") (class "Default")
      (node (ref "IC90") (pin "13") (pinfunction "13_13") (pintype "passive"))
      (node (ref "IC91") (pin "13") (pinfunction "13_13") (pintype "passive"))
      (node (ref "IC92") (pin "13") (pinfunction "13_13") (pintype "passive"))
      (node (ref "IC93") (pin "13") (pinfunction "13_13") (pintype "passive"))
    )
    (net (code "543") (name "Net-(IC90-Pad14)") (class "Default")
      (node (ref "IC90") (pin "14") (pinfunction "14_14") (pintype "passive"))
      (node (ref "IC91") (pin "14") (pinfunction "14_14") (pintype "passive"))
      (node (ref "IC92") (pin "14") (pinfunction "14_14") (pintype "passive"))
      (node (ref "IC93") (pin "14") (pinfunction "14_14") (pintype "passive"))
    )
    (net (code "544") (name "Net-(IC90-Pad15)") (class "Default")
      (node (ref "IC90") (pin "15") (pinfunction "15_15") (pintype "passive"))
      (node (ref "IC91") (pin "15") (pinfunction "15_15") (pintype "passive"))
      (node (ref "IC92") (pin "15") (pinfunction "15_15") (pintype "passive"))
      (node (ref "IC93") (pin "15") (pinfunction "15_15") (pintype "passive"))
    )
    (net (code "545") (name "Net-(IC90-Pad16)") (class "Default")
      (node (ref "IC90") (pin "16") (pinfunction "16_16") (pintype "passive"))
      (node (ref "IC91") (pin "16") (pinfunction "16_16") (pintype "passive"))
      (node (ref "IC92") (pin "16") (pinfunction "16_16") (pintype "passive"))
      (node (ref "IC93") (pin "16") (pinfunction "16_16") (pintype "passive"))
    )
    (net (code "546") (name "Net-(IC90-Pad17)") (class "Default")
      (node (ref "IC90") (pin "17") (pinfunction "17_17") (pintype "passive"))
      (node (ref "IC91") (pin "17") (pinfunction "17_17") (pintype "passive"))
      (node (ref "IC92") (pin "17") (pinfunction "17_17") (pintype "passive"))
      (node (ref "IC93") (pin "17") (pinfunction "17_17") (pintype "passive"))
    )
    (net (code "547") (name "Net-(IC90-Pad18)") (class "Default")
      (node (ref "IC90") (pin "18") (pinfunction "18_18") (pintype "passive"))
      (node (ref "IC91") (pin "18") (pinfunction "18_18") (pintype "passive"))
      (node (ref "IC92") (pin "18") (pinfunction "18_18") (pintype "passive"))
      (node (ref "IC93") (pin "18") (pinfunction "18_18") (pintype "passive"))
    )
    (net (code "548") (name "Net-(IC90-Pad19)") (class "Default")
      (node (ref "IC90") (pin "19") (pinfunction "19_19") (pintype "passive"))
      (node (ref "IC91") (pin "19") (pinfunction "19_19") (pintype "passive"))
      (node (ref "IC92") (pin "19") (pinfunction "19_19") (pintype "passive"))
      (node (ref "IC93") (pin "19") (pinfunction "19_19") (pintype "passive"))
    )
    (net (code "549") (name "Net-(IC90-Pad20)") (class "Default")
      (node (ref "IC90") (pin "20") (pinfunction "20_20") (pintype "passive"))
      (node (ref "IC91") (pin "20") (pinfunction "20_20") (pintype "passive"))
      (node (ref "IC92") (pin "20") (pinfunction "20_20") (pintype "passive"))
      (node (ref "IC93") (pin "20") (pinfunction "20_20") (pintype "passive"))
    )
    (net (code "550") (name "Net-(IC90-Pad21)") (class "Default")
      (node (ref "IC90") (pin "21") (pinfunction "21_21") (pintype "passive"))
      (node (ref "IC91") (pin "21") (pinfunction "21_21") (pintype "passive"))
      (node (ref "IC92") (pin "21") (pinfunction "21_21") (pintype "passive"))
      (node (ref "IC93") (pin "21") (pinfunction "21_21") (pintype "passive"))
    )
    (net (code "551") (name "Net-(IC90-Pad22)") (class "Default")
      (node (ref "IC90") (pin "22") (pinfunction "22_22") (pintype "passive"))
      (node (ref "IC91") (pin "22") (pinfunction "22_22") (pintype "passive"))
      (node (ref "IC92") (pin "22") (pinfunction "22_22") (pintype "passive"))
      (node (ref "IC93") (pin "22") (pinfunction "22_22") (pintype "passive"))
    )
    (net (code "552") (name "Net-(IC90-Pad23)") (class "Default")
      (node (ref "IC90") (pin "23") (pinfunction "23_23") (pintype "passive"))
      (node (ref "IC91") (pin "23") (pinfunction "23_23") (pintype "passive"))
      (node (ref "IC92") (pin "23") (pinfunction "23_23") (pintype "passive"))
      (node (ref "IC93") (pin "23") (pinfunction "23_23") (pintype "passive"))
    )
    (net (code "553") (name "Net-(IC90-Pad24)") (class "Default")
      (node (ref "IC90") (pin "24") (pinfunction "24_24") (pintype "passive"))
      (node (ref "IC91") (pin "24") (pinfunction "24_24") (pintype "passive"))
      (node (ref "IC92") (pin "24") (pinfunction "24_24") (pintype "passive"))
      (node (ref "IC93") (pin "24") (pinfunction "24_24") (pintype "passive"))
    )
    (net (code "554") (name "Net-(IC94-Pad1)") (class "Default")
      (node (ref "IC94") (pin "1") (pinfunction "1_1") (pintype "passive"))
      (node (ref "IC95") (pin "1") (pinfunction "1_1") (pintype "passive"))
      (node (ref "IC96") (pin "1") (pinfunction "1_1") (pintype "passive"))
      (node (ref "IC97") (pin "1") (pinfunction "1_1") (pintype "passive"))
    )
    (net (code "555") (name "Net-(IC94-Pad2)") (class "Default")
      (node (ref "IC94") (pin "2") (pinfunction "2_2") (pintype "passive"))
      (node (ref "IC95") (pin "2") (pinfunction "2_2") (pintype "passive"))
      (node (ref "IC96") (pin "2") (pinfunction "2_2") (pintype "passive"))
      (node (ref "IC97") (pin "2") (pinfunction "2_2") (pintype "passive"))
    )
    (net (code "556") (name "Net-(IC94-Pad3)") (class "Default")
      (node (ref "IC94") (pin "3") (pinfunction "3_3") (pintype "passive"))
      (node (ref "IC95") (pin "3") (pinfunction "3_3") (pintype "passive"))
      (node (ref "IC96") (pin "3") (pinfunction "3_3") (pintype "passive"))
      (node (ref "IC97") (pin "3") (pinfunction "3_3") (pintype "passive"))
    )
    (net (code "557") (name "Net-(IC94-Pad4)") (class "Default")
      (node (ref "IC94") (pin "4") (pinfunction "4_4") (pintype "passive"))
      (node (ref "IC95") (pin "4") (pinfunction "4_4") (pintype "passive"))
      (node (ref "IC96") (pin "4") (pinfunction "4_4") (pintype "passive"))
      (node (ref "IC97") (pin "4") (pinfunction "4_4") (pintype "passive"))
    )
    (net (code "558") (name "Net-(IC94-Pad5)") (class "Default")
      (node (ref "IC94") (pin "5") (pinfunction "5_5") (pintype "passive"))
      (node (ref "IC95") (pin "5") (pinfunction "5_5") (pintype "passive"))
      (node (ref "IC96") (pin "5") (pinfunction "5_5") (pintype "passive"))
      (node (ref "IC97") (pin "5") (pinfunction "5_5") (pintype "passive"))
    )
    (net (code "559") (name "Net-(IC94-Pad6)") (class "Default")
      (node (ref "IC94") (pin "6") (pinfunction "6_6") (pintype "passive"))
      (node (ref "IC95") (pin "6") (pinfunction "6_6") (pintype "passive"))
      (node (ref "IC96") (pin "6") (pinfunction "6_6") (pintype "passive"))
      (node (ref "IC97") (pin "6") (pinfunction "6_6") (pintype "passive"))
    )
    (net (code "560") (name "Net-(IC94-Pad7)") (class "Default")
      (node (ref "IC94") (pin "7") (pinfunction "7_7") (pintype "passive"))
      (node (ref "IC95") (pin "7") (pinfunction "7_7") (pintype "passive"))
      (node (ref "IC96") (pin "7") (pinfunction "7_7") (pintype "passive"))
      (node (ref "IC97") (pin "7") (pinfunction "7_7") (pintype "passive"))
    )
    (net (code "561") (name "Net-(IC94-Pad8)") (class "Default")
      (node (ref "IC94") (pin "8") (pinfunction "8_8") (pintype "passive"))
      (node (ref "IC95") (pin "8") (pinfunction "8_8") (pintype "passive"))
      (node (ref "IC96") (pin "8") (pinfunction "8_8") (pintype "passive"))
      (node (ref "IC97") (pin "8") (pinfunction "8_8") (pintype "passive"))
    )
    (net (code "562") (name "Net-(IC94-Pad9)") (class "Default")
      (node (ref "IC94") (pin "9") (pinfunction "9_9") (pintype "passive"))
      (node (ref "IC95") (pin "9") (pinfunction "9_9") (pintype "passive"))
      (node (ref "IC96") (pin "9") (pinfunction "9_9") (pintype "passive"))
      (node (ref "IC97") (pin "9") (pinfunction "9_9") (pintype "passive"))
    )
    (net (code "563") (name "Net-(IC94-Pad10)") (class "Default")
      (node (ref "IC94") (pin "10") (pinfunction "10_10") (pintype "passive"))
      (node (ref "IC95") (pin "10") (pinfunction "10_10") (pintype "passive"))
      (node (ref "IC96") (pin "10") (pinfunction "10_10") (pintype "passive"))
      (node (ref "IC97") (pin "10") (pinfunction "10_10") (pintype "passive"))
    )
    (net (code "564") (name "Net-(IC94-Pad11)") (class "Default")
      (node (ref "IC94") (pin "11") (pinfunction "11_11") (pintype "passive"))
      (node (ref "IC95") (pin "11") (pinfunction "11_11") (pintype "passive"))
      (node (ref "IC96") (pin "11") (pinfunction "11_11") (pintype "passive"))
      (node (ref "IC97") (pin "11") (pinfunction "11_11") (pintype "passive"))
    )
    (net (code "565") (name "Net-(IC94-Pad12)") (class "Default")
      (node (ref "IC94") (pin "12") (pinfunction "12_12") (pintype "passive"))
      (node (ref "IC95") (pin "12") (pinfunction "12_12") (pintype "passive"))
      (node (ref "IC96") (pin "12") (pinfunction "12_12") (pintype "passive"))
      (node (ref "IC97") (pin "12") (pinfunction "12_12") (pintype "passive"))
    )
    (net (code "566") (name "Net-(IC94-Pad13)") (class "Default")
      (node (ref "IC94") (pin "13") (pinfunction "13_13") (pintype "passive"))
      (node (ref "IC95") (pin "13") (pinfunction "13_13") (pintype "passive"))
      (node (ref "IC96") (pin "13") (pinfunction "13_13") (pintype "passive"))
      (node (ref "IC97") (pin "13") (pinfunction "13_13") (pintype "passive"))
    )
    (net (code "567") (name "Net-(IC94-Pad14)") (class "Default")
      (node (ref "IC94") (pin "14") (pinfunction "14_14") (pintype "passive"))
      (node (ref "IC95") (pin "14") (pinfunction "14_14") (pintype "passive"))
      (node (ref "IC96") (pin "14") (pinfunction "14_14") (pintype "passive"))
      (node (ref "IC97") (pin "14") (pinfunction "14_14") (pintype "passive"))
    )
    (net (code "568") (name "Net-(IC94-Pad15)") (class "Default")
      (node (ref "IC94") (pin "15") (pinfunction "15_15") (pintype "passive"))
      (node (ref "IC95") (pin "15") (pinfunction "15_15") (pintype "passive"))
      (node (ref "IC96") (pin "15") (pinfunction "15_15") (pintype "passive"))
      (node (ref "IC97") (pin "15") (pinfunction "15_15") (pintype "passive"))
    )
    (net (code "569") (name "Net-(IC94-Pad16)") (class "Default")
      (node (ref "IC94") (pin "16") (pinfunction "16_16") (pintype "passive"))
      (node (ref "IC95") (pin "16") (pinfunction "16_16") (pintype "passive"))
      (node (ref "IC96") (pin "16") (pinfunction "16_16") (pintype "passive"))
      (node (ref "IC97") (pin "16") (pinfunction "16_16") (pintype "passive"))
    )
    (net (code "570") (name "Net-(IC94-Pad17)") (class "Default")
      (node (ref "IC94") (pin "17") (pinfunction "17_17") (pintype "passive"))
      (node (ref "IC95") (pin "17") (pinfunction "17_17") (pintype "passive"))
      (node (ref "IC96") (pin "17") (pinfunction "17_17") (pintype "passive"))
      (node (ref "IC97") (pin "17") (pinfunction "17_17") (pintype "passive"))
    )
    (net (code "571") (name "Net-(IC94-Pad18)") (class "Default")
      (node (ref "IC94") (pin "18") (pinfunction "18_18") (pintype "passive"))
      (node (ref "IC95") (pin "18") (pinfunction "18_18") (pintype "passive"))
      (node (ref "IC96") (pin "18") (pinfunction "18_18") (pintype "passive"))
      (node (ref "IC97") (pin "18") (pinfunction "18_18") (pintype "passive"))
    )
    (net (code "572") (name "Net-(IC94-Pad19)") (class "Default")
      (node (ref "IC94") (pin "19") (pinfunction "19_19") (pintype "passive"))
      (node (ref "IC95") (pin "19") (pinfunction "19_19") (pintype "passive"))
      (node (ref "IC96") (pin "19") (pinfunction "19_19") (pintype "passive"))
      (node (ref "IC97") (pin "19") (pinfunction "19_19") (pintype "passive"))
    )
    (net (code "573") (name "Net-(IC94-Pad20)") (class "Default")
      (node (ref "IC94") (pin "20") (pinfunction "20_20") (pintype "passive"))
      (node (ref "IC95") (pin "20") (pinfunction "20_20") (pintype "passive"))
      (node (ref "IC96") (pin "20") (pinfunction "20_20") (pintype "passive"))
      (node (ref "IC97") (pin "20") (pinfunction "20_20") (pintype "passive"))
    )
    (net (code "574") (name "Net-(IC94-Pad21)") (class "Default")
      (node (ref "IC94") (pin "21") (pinfunction "21_21") (pintype "passive"))
      (node (ref "IC95") (pin "21") (pinfunction "21_21") (pintype "passive"))
      (node (ref "IC96") (pin "21") (pinfunction "21_21") (pintype "passive"))
      (node (ref "IC97") (pin "21") (pinfunction "21_21") (pintype "passive"))
    )
    (net (code "575") (name "Net-(IC94-Pad22)") (class "Default")
      (node (ref "IC94") (pin "22") (pinfunction "22_22") (pintype "passive"))
      (node (ref "IC95") (pin "22") (pinfunction "22_22") (pintype "passive"))
      (node (ref "IC96") (pin "22") (pinfunction "22_22") (pintype "passive"))
      (node (ref "IC97") (pin "22") (pinfunction "22_22") (pintype "passive"))
    )
    (net (code "576") (name "Net-(IC94-Pad23)") (class "Default")
      (node (ref "IC94") (pin "23") (pinfunction "23_23") (pintype "passive"))
      (node (ref "IC95") (pin "23") (pinfunction "23_23") (pintype "passive"))
      (node (ref "IC96") (pin "23") (pinfunction "23_23") (pintype "passive"))
      (node (ref "IC97") (pin "23") (pinfunction "23_23") (pintype "passive"))
    )
    (net (code "577") (name "Net-(IC94-Pad24)") (class "Default")
      (node (ref "IC94") (pin "24") (pinfunction "24_24") (pintype "passive"))
      (node (ref "IC95") (pin "24") (pinfunction "24_24") (pintype "passive"))
      (node (ref "IC96") (pin "24") (pinfunction "24_24") (pintype "passive"))
      (node (ref "IC97") (pin "24") (pinfunction "24_24") (pintype "passive"))
    )
    (net (code "578") (name "Net-(IC100-Pad1)") (class "Default")
      (node (ref "IC100") (pin "1") (pinfunction "1_1") (pintype "passive"))
      (node (ref "IC101") (pin "1") (pinfunction "1_1") (pintype "passive"))
      (node (ref "IC98") (pin "1") (pinfunction "1_1") (pintype "passive"))
      (node (ref "IC99") (pin "1") (pinfunction "1_1") (pintype "passive"))
    )
    (net (code "579") (name "Net-(IC100-Pad2)") (class "Default")
      (node (ref "IC100") (pin "2") (pinfunction "2_2") (pintype "passive"))
      (node (ref "IC101") (pin "2") (pinfunction "2_2") (pintype "passive"))
      (node (ref "IC98") (pin "2") (pinfunction "2_2") (pintype "passive"))
      (node (ref "IC99") (pin "2") (pinfunction "2_2") (pintype "passive"))
    )
    (net (code "580") (name "Net-(IC100-Pad3)") (class "Default")
      (node (ref "IC100") (pin "3") (pinfunction "3_3") (pintype "passive"))
      (node (ref "IC101") (pin "3") (pinfunction "3_3") (pintype "passive"))
      (node (ref "IC98") (pin "3") (pinfunction "3_3") (pintype "passive"))
      (node (ref "IC99") (pin "3") (pinfunction "3_3") (pintype "passive"))
    )
    (net (code "581") (name "Net-(IC100-Pad4)") (class "Default")
      (node (ref "IC100") (pin "4") (pinfunction "4_4") (pintype "passive"))
      (node (ref "IC101") (pin "4") (pinfunction "4_4") (pintype "passive"))
      (node (ref "IC98") (pin "4") (pinfunction "4_4") (pintype "passive"))
      (node (ref "IC99") (pin "4") (pinfunction "4_4") (pintype "passive"))
    )
    (net (code "582") (name "Net-(IC100-Pad5)") (class "Default")
      (node (ref "IC100") (pin "5") (pinfunction "5_5") (pintype "passive"))
      (node (ref "IC101") (pin "5") (pinfunction "5_5") (pintype "passive"))
      (node (ref "IC98") (pin "5") (pinfunction "5_5") (pintype "passive"))
      (node (ref "IC99") (pin "5") (pinfunction "5_5") (pintype "passive"))
    )
    (net (code "583") (name "Net-(IC100-Pad6)") (class "Default")
      (node (ref "IC100") (pin "6") (pinfunction "6_6") (pintype "passive"))
      (node (ref "IC101") (pin "6") (pinfunction "6_6") (pintype "passive"))
      (node (ref "IC98") (pin "6") (pinfunction "6_6") (pintype "passive"))
      (node (ref "IC99") (pin "6") (pinfunction "6_6") (pintype "passive"))
    )
    (net (code "584") (name "Net-(IC100-Pad7)") (class "Default")
      (node (ref "IC100") (pin "7") (pinfunction "7_7") (pintype "passive"))
      (node (ref "IC101") (pin "7") (pinfunction "7_7") (pintype "passive"))
      (node (ref "IC98") (pin "7") (pinfunction "7_7") (pintype "passive"))
      (node (ref "IC99") (pin "7") (pinfunction "7_7") (pintype "passive"))
    )
    (net (code "585") (name "Net-(IC100-Pad8)") (class "Default")
      (node (ref "IC100") (pin "8") (pinfunction "8_8") (pintype "passive"))
      (node (ref "IC101") (pin "8") (pinfunction "8_8") (pintype "passive"))
      (node (ref "IC98") (pin "8") (pinfunction "8_8") (pintype "passive"))
      (node (ref "IC99") (pin "8") (pinfunction "8_8") (pintype "passive"))
    )
    (net (code "586") (name "Net-(IC100-Pad9)") (class "Default")
      (node (ref "IC100") (pin "9") (pinfunction "9_9") (pintype "passive"))
      (node (ref "IC101") (pin "9") (pinfunction "9_9") (pintype "passive"))
      (node (ref "IC98") (pin "9") (pinfunction "9_9") (pintype "passive"))
      (node (ref "IC99") (pin "9") (pinfunction "9_9") (pintype "passive"))
    )
    (net (code "587") (name "Net-(IC100-Pad10)") (class "Default")
      (node (ref "IC100") (pin "10") (pinfunction "10_10") (pintype "passive"))
      (node (ref "IC101") (pin "10") (pinfunction "10_10") (pintype "passive"))
      (node (ref "IC98") (pin "10") (pinfunction "10_10") (pintype "passive"))
      (node (ref "IC99") (pin "10") (pinfunction "10_10") (pintype "passive"))
    )
    (net (code "588") (name "Net-(IC100-Pad11)") (class "Default")
      (node (ref "IC100") (pin "11") (pinfunction "11_11") (pintype "passive"))
      (node (ref "IC101") (pin "11") (pinfunction "11_11") (pintype "passive"))
      (node (ref "IC98") (pin "11") (pinfunction "11_11") (pintype "passive"))
      (node (ref "IC99") (pin "11") (pinfunction "11_11") (pintype "passive"))
    )
    (net (code "589") (name "Net-(IC100-Pad12)") (class "Default")
      (node (ref "IC100") (pin "12") (pinfunction "12_12") (pintype "passive"))
      (node (ref "IC101") (pin "12") (pinfunction "12_12") (pintype "passive"))
      (node (ref "IC98") (pin "12") (pinfunction "12_12") (pintype "passive"))
      (node (ref "IC99") (pin "12") (pinfunction "12_12") (pintype "passive"))
    )
    (net (code "590") (name "Net-(IC100-Pad13)") (class "Default")
      (node (ref "IC100") (pin "13") (pinfunction "13_13") (pintype "passive"))
      (node (ref "IC101") (pin "13") (pinfunction "13_13") (pintype "passive"))
      (node (ref "IC98") (pin "13") (pinfunction "13_13") (pintype "passive"))
      (node (ref "IC99") (pin "13") (pinfunction "13_13") (pintype "passive"))
    )
    (net (code "591") (name "Net-(IC100-Pad14)") (class "Default")
      (node (ref "IC100") (pin "14") (pinfunction "14_14") (pintype "passive"))
      (node (ref "IC101") (pin "14") (pinfunction "14_14") (pintype "passive"))
      (node (ref "IC98") (pin "14") (pinfunction "14_14") (pintype "passive"))
      (node (ref "IC99") (pin "14") (pinfunction "14_14") (pintype "passive"))
    )
    (net (code "592") (name "Net-(IC100-Pad15)") (class "Default")
      (node (ref "IC100") (pin "15") (pinfunction "15_15") (pintype "passive"))
      (node (ref "IC101") (pin "15") (pinfunction "15_15") (pintype "passive"))
      (node (ref "IC98") (pin "15") (pinfunction "15_15") (pintype "passive"))
      (node (ref "IC99") (pin "15") (pinfunction "15_15") (pintype "passive"))
    )
    (net (code "593") (name "Net-(IC100-Pad16)") (class "Default")
      (node (ref "IC100") (pin "16") (pinfunction "16_16") (pintype "passive"))
      (node (ref "IC101") (pin "16") (pinfunction "16_16") (pintype "passive"))
      (node (ref "IC98") (pin "16") (pinfunction "16_16") (pintype "passive"))
      (node (ref "IC99") (pin "16") (pinfunction "16_16") (pintype "passive"))
    )
    (net (code "594") (name "Net-(IC100-Pad17)") (class "Default")
      (node (ref "IC100") (pin "17") (pinfunction "17_17") (pintype "passive"))
      (node (ref "IC101") (pin "17") (pinfunction "17_17") (pintype "passive"))
      (node (ref "IC98") (pin "17") (pinfunction "17_17") (pintype "passive"))
      (node (ref "IC99") (pin "17") (pinfunction "17_17") (pintype "passive"))
    )
    (net (code "595") (name "Net-(IC100-Pad18)") (class "Default")
      (node (ref "IC100") (pin "18") (pinfunction "18_18") (pintype "passive"))
      (node (ref "IC101") (pin "18") (pinfunction "18_18") (pintype "passive"))
      (node (ref "IC98") (pin "18") (pinfunction "18_18") (pintype "passive"))
      (node (ref "IC99") (pin "18") (pinfunction "18_18") (pintype "passive"))
    )
    (net (code "596") (name "Net-(IC100-Pad19)") (class "Default")
      (node (ref "IC100") (pin "19") (pinfunction "19_19") (pintype "passive"))
      (node (ref "IC101") (pin "19") (pinfunction "19_19") (pintype "passive"))
      (node (ref "IC98") (pin "19") (pinfunction "19_19") (pintype "passive"))
      (node (ref "IC99") (pin "19") (pinfunction "19_19") (pintype "passive"))
    )
    (net (code "597") (name "Net-(IC100-Pad20)") (class "Default")
      (node (ref "IC100") (pin "20") (pinfunction "20_20") (pintype "passive"))
      (node (ref "IC101") (pin "20") (pinfunction "20_20") (pintype "passive"))
      (node (ref "IC98") (pin "20") (pinfunction "20_20") (pintype "passive"))
      (node (ref "IC99") (pin "20") (pinfunction "20_20") (pintype "passive"))
    )
    (net (code "598") (name "Net-(IC100-Pad21)") (class "Default")
      (node (ref "IC100") (pin "21") (pinfunction "21_21") (pintype "passive"))
      (node (ref "IC101") (pin "21") (pinfunction "21_21") (pintype "passive"))
      (node (ref "IC98") (pin "21") (pinfunction "21_21") (pintype "passive"))
      (node (ref "IC99") (pin "21") (pinfunction "21_21") (pintype "passive"))
    )
    (net (code "599") (name "Net-(IC100-Pad22)") (class "Default")
      (node (ref "IC100") (pin "22") (pinfunction "22_22") (pintype "passive"))
      (node (ref "IC101") (pin "22") (pinfunction "22_22") (pintype "passive"))
      (node (ref "IC98") (pin "22") (pinfunction "22_22") (pintype "passive"))
      (node (ref "IC99") (pin "22") (pinfunction "22_22") (pintype "passive"))
    )
    (net (code "600") (name "Net-(IC100-Pad23)") (class "Default")
      (node (ref "IC100") (pin "23") (pinfunction "23_23") (pintype "passive"))
      (node (ref "IC101") (pin "23") (pinfunction "23_23") (pintype "passive"))
      (node (ref "IC98") (pin "23") (pinfunction "23_23") (pintype "passive"))
      (node (ref "IC99") (pin "23") (pinfunction "23_23") (pintype "passive"))
    )
    (net (code "601") (name "Net-(IC100-Pad24)") (class "Default")
      (node (ref "IC100") (pin "24") (pinfunction "24_24") (pintype "passive"))
      (node (ref "IC101") (pin "24") (pinfunction "24_24") (pintype "passive"))
      (node (ref "IC98") (pin "24") (pinfunction "24_24") (pintype "passive"))
      (node (ref "IC99") (pin "24") (pinfunction "24_24") (pintype "passive"))
    )
    (net (code "602") (name "Net-(IC102-Pad1)") (class "Default")
      (node (ref "IC102") (pin "1") (pinfunction "1_1") (pintype "passive"))
      (node (ref "IC103") (pin "1") (pinfunction "1_1") (pintype "passive"))
      (node (ref "IC104") (pin "1") (pinfunction "1_1") (pintype "passive"))
      (node (ref "IC105") (pin "1") (pinfunction "1_1") (pintype "passive"))
    )
    (net (code "603") (name "Net-(IC102-Pad2)") (class "Default")
      (node (ref "IC102") (pin "2") (pinfunction "2_2") (pintype "passive"))
      (node (ref "IC103") (pin "2") (pinfunction "2_2") (pintype "passive"))
      (node (ref "IC104") (pin "2") (pinfunction "2_2") (pintype "passive"))
      (node (ref "IC105") (pin "2") (pinfunction "2_2") (pintype "passive"))
    )
    (net (code "604") (name "Net-(IC102-Pad3)") (class "Default")
      (node (ref "IC102") (pin "3") (pinfunction "3_3") (pintype "passive"))
      (node (ref "IC103") (pin "3") (pinfunction "3_3") (pintype "passive"))
      (node (ref "IC104") (pin "3") (pinfunction "3_3") (pintype "passive"))
      (node (ref "IC105") (pin "3") (pinfunction "3_3") (pintype "passive"))
    )
    (net (code "605") (name "Net-(IC102-Pad4)") (class "Default")
      (node (ref "IC102") (pin "4") (pinfunction "4_4") (pintype "passive"))
      (node (ref "IC103") (pin "4") (pinfunction "4_4") (pintype "passive"))
      (node (ref "IC104") (pin "4") (pinfunction "4_4") (pintype "passive"))
      (node (ref "IC105") (pin "4") (pinfunction "4_4") (pintype "passive"))
    )
    (net (code "606") (name "Net-(IC102-Pad5)") (class "Default")
      (node (ref "IC102") (pin "5") (pinfunction "5_5") (pintype "passive"))
      (node (ref "IC103") (pin "5") (pinfunction "5_5") (pintype "passive"))
      (node (ref "IC104") (pin "5") (pinfunction "5_5") (pintype "passive"))
      (node (ref "IC105") (pin "5") (pinfunction "5_5") (pintype "passive"))
    )
    (net (code "607") (name "Net-(IC102-Pad6)") (class "Default")
      (node (ref "IC102") (pin "6") (pinfunction "6_6") (pintype "passive"))
      (node (ref "IC103") (pin "6") (pinfunction "6_6") (pintype "passive"))
      (node (ref "IC104") (pin "6") (pinfunction "6_6") (pintype "passive"))
      (node (ref "IC105") (pin "6") (pinfunction "6_6") (pintype "passive"))
    )
    (net (code "608") (name "Net-(IC102-Pad7)") (class "Default")
      (node (ref "IC102") (pin "7") (pinfunction "7_7") (pintype "passive"))
      (node (ref "IC103") (pin "7") (pinfunction "7_7") (pintype "passive"))
      (node (ref "IC104") (pin "7") (pinfunction "7_7") (pintype "passive"))
      (node (ref "IC105") (pin "7") (pinfunction "7_7") (pintype "passive"))
    )
    (net (code "609") (name "Net-(IC102-Pad8)") (class "Default")
      (node (ref "IC102") (pin "8") (pinfunction "8_8") (pintype "passive"))
      (node (ref "IC103") (pin "8") (pinfunction "8_8") (pintype "passive"))
      (node (ref "IC104") (pin "8") (pinfunction "8_8") (pintype "passive"))
      (node (ref "IC105") (pin "8") (pinfunction "8_8") (pintype "passive"))
    )
    (net (code "610") (name "Net-(IC102-Pad9)") (class "Default")
      (node (ref "IC102") (pin "9") (pinfunction "9_9") (pintype "passive"))
      (node (ref "IC103") (pin "9") (pinfunction "9_9") (pintype "passive"))
      (node (ref "IC104") (pin "9") (pinfunction "9_9") (pintype "passive"))
      (node (ref "IC105") (pin "9") (pinfunction "9_9") (pintype "passive"))
    )
    (net (code "611") (name "Net-(IC102-Pad10)") (class "Default")
      (node (ref "IC102") (pin "10") (pinfunction "10_10") (pintype "passive"))
      (node (ref "IC103") (pin "10") (pinfunction "10_10") (pintype "passive"))
      (node (ref "IC104") (pin "10") (pinfunction "10_10") (pintype "passive"))
      (node (ref "IC105") (pin "10") (pinfunction "10_10") (pintype "passive"))
    )
    (net (code "612") (name "Net-(IC102-Pad11)") (class "Default")
      (node (ref "IC102") (pin "11") (pinfunction "11_11") (pintype "passive"))
      (node (ref "IC103") (pin "11") (pinfunction "11_11") (pintype "passive"))
      (node (ref "IC104") (pin "11") (pinfunction "11_11") (pintype "passive"))
      (node (ref "IC105") (pin "11") (pinfunction "11_11") (pintype "passive"))
    )
    (net (code "613") (name "Net-(IC102-Pad12)") (class "Default")
      (node (ref "IC102") (pin "12") (pinfunction "12_12") (pintype "passive"))
      (node (ref "IC103") (pin "12") (pinfunction "12_12") (pintype "passive"))
      (node (ref "IC104") (pin "12") (pinfunction "12_12") (pintype "passive"))
      (node (ref "IC105") (pin "12") (pinfunction "12_12") (pintype "passive"))
    )
    (net (code "614") (name "Net-(IC102-Pad13)") (class "Default")
      (node (ref "IC102") (pin "13") (pinfunction "13_13") (pintype "passive"))
      (node (ref "IC103") (pin "13") (pinfunction "13_13") (pintype "passive"))
      (node (ref "IC104") (pin "13") (pinfunction "13_13") (pintype "passive"))
      (node (ref "IC105") (pin "13") (pinfunction "13_13") (pintype "passive"))
    )
    (net (code "615") (name "Net-(IC102-Pad14)") (class "Default")
      (node (ref "IC102") (pin "14") (pinfunction "14_14") (pintype "passive"))
      (node (ref "IC103") (pin "14") (pinfunction "14_14") (pintype "passive"))
      (node (ref "IC104") (pin "14") (pinfunction "14_14") (pintype "passive"))
      (node (ref "IC105") (pin "14") (pinfunction "14_14") (pintype "passive"))
    )
    (net (code "616") (name "Net-(IC102-Pad15)") (class "Default")
      (node (ref "IC102") (pin "15") (pinfunction "15_15") (pintype "passive"))
      (node (ref "IC103") (pin "15") (pinfunction "15_15") (pintype "passive"))
      (node (ref "IC104") (pin "15") (pinfunction "15_15") (pintype "passive"))
      (node (ref "IC105") (pin "15") (pinfunction "15_15") (pintype "passive"))
    )
    (net (code "617") (name "Net-(IC102-Pad16)") (class "Default")
      (node (ref "IC102") (pin "16") (pinfunction "16_16") (pintype "passive"))
      (node (ref "IC103") (pin "16") (pinfunction "16_16") (pintype "passive"))
      (node (ref "IC104") (pin "16") (pinfunction "16_16") (pintype "passive"))
      (node (ref "IC105") (pin "16") (pinfunction "16_16") (pintype "passive"))
    )
    (net (code "618") (name "Net-(IC102-Pad17)") (class "Default")
      (node (ref "IC102") (pin "17") (pinfunction "17_17") (pintype "passive"))
      (node (ref "IC103") (pin "17") (pinfunction "17_17") (pintype "passive"))
      (node (ref "IC104") (pin "17") (pinfunction "17_17") (pintype "passive"))
      (node (ref "IC105") (pin "17") (pinfunction "17_17") (pintype "passive"))
    )
    (net (code "619") (name "Net-(IC102-Pad18)") (class "Default")
      (node (ref "IC102") (pin "18") (pinfunction "18_18") (pintype "passive"))
      (node (ref "IC103") (pin "18") (pinfunction "18_18") (pintype "passive"))
      (node (ref "IC104") (pin "18") (pinfunction "18_18") (pintype "passive"))
      (node (ref "IC105") (pin "18") (pinfunction "18_18") (pintype "passive"))
    )
    (net (code "620") (name "Net-(IC102-Pad19)") (class "Default")
      (node (ref "IC102") (pin "19") (pinfunction "19_19") (pintype "passive"))
      (node (ref "IC103") (pin "19") (pinfunction "19_19") (pintype "passive"))
      (node (ref "IC104") (pin "19") (pinfunction "19_19") (pintype "passive"))
      (node (ref "IC105") (pin "19") (pinfunction "19_19") (pintype "passive"))
    )
    (net (code "621") (name "Net-(IC102-Pad20)") (class "Default")
      (node (ref "IC102") (pin "20") (pinfunction "20_20") (pintype "passive"))
      (node (ref "IC103") (pin "20") (pinfunction "20_20") (pintype "passive"))
      (node (ref "IC104") (pin "20") (pinfunction "20_20") (pintype "passive"))
      (node (ref "IC105") (pin "20") (pinfunction "20_20") (pintype "passive"))
    )
    (net (code "622") (name "Net-(IC102-Pad21)") (class "Default")
      (node (ref "IC102") (pin "21") (pinfunction "21_21") (pintype "passive"))
      (node (ref "IC103") (pin "21") (pinfunction "21_21") (pintype "passive"))
      (node (ref "IC104") (pin "21") (pinfunction "21_21") (pintype "passive"))
      (node (ref "IC105") (pin "21") (pinfunction "21_21") (pintype "passive"))
    )
    (net (code "623") (name "Net-(IC102-Pad22)") (class "Default")
      (node (ref "IC102") (pin "22") (pinfunction "22_22") (pintype "passive"))
      (node (ref "IC103") (pin "22") (pinfunction "22_22") (pintype "passive"))
      (node (ref "IC104") (pin "22") (pinfunction "22_22") (pintype "passive"))
      (node (ref "IC105") (pin "22") (pinfunction "22_22") (pintype "passive"))
    )
    (net (code "624") (name "Net-(IC102-Pad23)") (class "Default")
      (node (ref "IC102") (pin "23") (pinfunction "23_23") (pintype "passive"))
      (node (ref "IC103") (pin "23") (pinfunction "23_23") (pintype "passive"))
      (node (ref "IC104") (pin "23") (pinfunction "23_23") (pintype "passive"))
      (node (ref "IC105") (pin "23") (pinfunction "23_23") (pintype "passive"))
    )
    (net (code "625") (name "Net-(IC102-Pad24)") (class "Default")
      (node (ref "IC102") (pin "24") (pinfunction "24_24") (pintype "passive"))
      (node (ref "IC103") (pin "24") (pinfunction "24_24") (pintype "passive"))
      (node (ref "IC104") (pin "24") (pinfunction "24_24") (pintype "passive"))
      (node (ref "IC105") (pin "24") (pinfunction "24_24") (pintype "passive"))
    )
    (net (code "626") (name "Net-(IC106-Pad1)") (class "Default")
      (node (ref "IC106") (pin "1") (pinfunction "1_1") (pintype "passive"))
      (node (ref "IC107") (pin "1") (pinfunction "1_1") (pintype "passive"))
      (node (ref "IC108") (pin "1") (pinfunction "1_1") (pintype "passive"))
      (node (ref "IC109") (pin "1") (pinfunction "1_1") (pintype "passive"))
    )
    (net (code "627") (name "Net-(IC106-Pad2)") (class "Default")
      (node (ref "IC106") (pin "2") (pinfunction "2_2") (pintype "passive"))
      (node (ref "IC107") (pin "2") (pinfunction "2_2") (pintype "passive"))
      (node (ref "IC108") (pin "2") (pinfunction "2_2") (pintype "passive"))
      (node (ref "IC109") (pin "2") (pinfunction "2_2") (pintype "passive"))
    )
    (net (code "628") (name "Net-(IC106-Pad3)") (class "Default")
      (node (ref "IC106") (pin "3") (pinfunction "3_3") (pintype "passive"))
      (node (ref "IC107") (pin "3") (pinfunction "3_3") (pintype "passive"))
      (node (ref "IC108") (pin "3") (pinfunction "3_3") (pintype "passive"))
      (node (ref "IC109") (pin "3") (pinfunction "3_3") (pintype "passive"))
    )
    (net (code "629") (name "Net-(IC106-Pad4)") (class "Default")
      (node (ref "IC106") (pin "4") (pinfunction "4_4") (pintype "passive"))
      (node (ref "IC107") (pin "4") (pinfunction "4_4") (pintype "passive"))
      (node (ref "IC108") (pin "4") (pinfunction "4_4") (pintype "passive"))
      (node (ref "IC109") (pin "4") (pinfunction "4_4") (pintype "passive"))
    )
    (net (code "630") (name "Net-(IC106-Pad5)") (class "Default")
      (node (ref "IC106") (pin "5") (pinfunction "5_5") (pintype "passive"))
      (node (ref "IC107") (pin "5") (pinfunction "5_5") (pintype "passive"))
      (node (ref "IC108") (pin "5") (pinfunction "5_5") (pintype "passive"))
      (node (ref "IC109") (pin "5") (pinfunction "5_5") (pintype "passive"))
    )
    (net (code "631") (name "Net-(IC106-Pad6)") (class "Default")
      (node (ref "IC106") (pin "6") (pinfunction "6_6") (pintype "passive"))
      (node (ref "IC107") (pin "6") (pinfunction "6_6") (pintype "passive"))
      (node (ref "IC108") (pin "6") (pinfunction "6_6") (pintype "passive"))
      (node (ref "IC109") (pin "6") (pinfunction "6_6") (pintype "passive"))
    )
    (net (code "632") (name "Net-(IC106-Pad7)") (class "Default")
      (node (ref "IC106") (pin "7") (pinfunction "7_7") (pintype "passive"))
      (node (ref "IC107") (pin "7") (pinfunction "7_7") (pintype "passive"))
      (node (ref "IC108") (pin "7") (pinfunction "7_7") (pintype "passive"))
      (node (ref "IC109") (pin "7") (pinfunction "7_7") (pintype "passive"))
    )
    (net (code "633") (name "Net-(IC106-Pad8)") (class "Default")
      (node (ref "IC106") (pin "8") (pinfunction "8_8") (pintype "passive"))
      (node (ref "IC107") (pin "8") (pinfunction "8_8") (pintype "passive"))
      (node (ref "IC108") (pin "8") (pinfunction "8_8") (pintype "passive"))
      (node (ref "IC109") (pin "8") (pinfunction "8_8") (pintype "passive"))
    )
    (net (code "634") (name "Net-(IC106-Pad9)") (class "Default")
      (node (ref "IC106") (pin "9") (pinfunction "9_9") (pintype "passive"))
      (node (ref "IC107") (pin "9") (pinfunction "9_9") (pintype "passive"))
      (node (ref "IC108") (pin "9") (pinfunction "9_9") (pintype "passive"))
      (node (ref "IC109") (pin "9") (pinfunction "9_9") (pintype "passive"))
    )
    (net (code "635") (name "Net-(IC106-Pad10)") (class "Default")
      (node (ref "IC106") (pin "10") (pinfunction "10_10") (pintype "passive"))
      (node (ref "IC107") (pin "10") (pinfunction "10_10") (pintype "passive"))
      (node (ref "IC108") (pin "10") (pinfunction "10_10") (pintype "passive"))
      (node (ref "IC109") (pin "10") (pinfunction "10_10") (pintype "passive"))
    )
    (net (code "636") (name "Net-(IC106-Pad11)") (class "Default")
      (node (ref "IC106") (pin "11") (pinfunction "11_11") (pintype "passive"))
      (node (ref "IC107") (pin "11") (pinfunction "11_11") (pintype "passive"))
      (node (ref "IC108") (pin "11") (pinfunction "11_11") (pintype "passive"))
      (node (ref "IC109") (pin "11") (pinfunction "11_11") (pintype "passive"))
    )
    (net (code "637") (name "Net-(IC106-Pad12)") (class "Default")
      (node (ref "IC106") (pin "12") (pinfunction "12_12") (pintype "passive"))
      (node (ref "IC107") (pin "12") (pinfunction "12_12") (pintype "passive"))
      (node (ref "IC108") (pin "12") (pinfunction "12_12") (pintype "passive"))
      (node (ref "IC109") (pin "12") (pinfunction "12_12") (pintype "passive"))
    )
    (net (code "638") (name "Net-(IC106-Pad13)") (class "Default")
      (node (ref "IC106") (pin "13") (pinfunction "13_13") (pintype "passive"))
      (node (ref "IC107") (pin "13") (pinfunction "13_13") (pintype "passive"))
      (node (ref "IC108") (pin "13") (pinfunction "13_13") (pintype "passive"))
      (node (ref "IC109") (pin "13") (pinfunction "13_13") (pintype "passive"))
    )
    (net (code "639") (name "Net-(IC106-Pad14)") (class "Default")
      (node (ref "IC106") (pin "14") (pinfunction "14_14") (pintype "passive"))
      (node (ref "IC107") (pin "14") (pinfunction "14_14") (pintype "passive"))
      (node (ref "IC108") (pin "14") (pinfunction "14_14") (pintype "passive"))
      (node (ref "IC109") (pin "14") (pinfunction "14_14") (pintype "passive"))
    )
    (net (code "640") (name "Net-(IC106-Pad15)") (class "Default")
      (node (ref "IC106") (pin "15") (pinfunction "15_15") (pintype "passive"))
      (node (ref "IC107") (pin "15") (pinfunction "15_15") (pintype "passive"))
      (node (ref "IC108") (pin "15") (pinfunction "15_15") (pintype "passive"))
      (node (ref "IC109") (pin "15") (pinfunction "15_15") (pintype "passive"))
    )
    (net (code "641") (name "Net-(IC106-Pad16)") (class "Default")
      (node (ref "IC106") (pin "16") (pinfunction "16_16") (pintype "passive"))
      (node (ref "IC107") (pin "16") (pinfunction "16_16") (pintype "passive"))
      (node (ref "IC108") (pin "16") (pinfunction "16_16") (pintype "passive"))
      (node (ref "IC109") (pin "16") (pinfunction "16_16") (pintype "passive"))
    )
    (net (code "642") (name "Net-(IC106-Pad17)") (class "Default")
      (node (ref "IC106") (pin "17") (pinfunction "17_17") (pintype "passive"))
      (node (ref "IC107") (pin "17") (pinfunction "17_17") (pintype "passive"))
      (node (ref "IC108") (pin "17") (pinfunction "17_17") (pintype "passive"))
      (node (ref "IC109") (pin "17") (pinfunction "17_17") (pintype "passive"))
    )
    (net (code "643") (name "Net-(IC106-Pad18)") (class "Default")
      (node (ref "IC106") (pin "18") (pinfunction "18_18") (pintype "passive"))
      (node (ref "IC107") (pin "18") (pinfunction "18_18") (pintype "passive"))
      (node (ref "IC108") (pin "18") (pinfunction "18_18") (pintype "passive"))
      (node (ref "IC109") (pin "18") (pinfunction "18_18") (pintype "passive"))
    )
    (net (code "644") (name "Net-(IC106-Pad19)") (class "Default")
      (node (ref "IC106") (pin "19") (pinfunction "19_19") (pintype "passive"))
      (node (ref "IC107") (pin "19") (pinfunction "19_19") (pintype "passive"))
      (node (ref "IC108") (pin "19") (pinfunction "19_19") (pintype "passive"))
      (node (ref "IC109") (pin "19") (pinfunction "19_19") (pintype "passive"))
    )
    (net (code "645") (name "Net-(IC106-Pad20)") (class "Default")
      (node (ref "IC106") (pin "20") (pinfunction "20_20") (pintype "passive"))
      (node (ref "IC107") (pin "20") (pinfunction "20_20") (pintype "passive"))
      (node (ref "IC108") (pin "20") (pinfunction "20_20") (pintype "passive"))
      (node (ref "IC109") (pin "20") (pinfunction "20_20") (pintype "passive"))
    )
    (net (code "646") (name "Net-(IC106-Pad21)") (class "Default")
      (node (ref "IC106") (pin "21") (pinfunction "21_21") (pintype "passive"))
      (node (ref "IC107") (pin "21") (pinfunction "21_21") (pintype "passive"))
      (node (ref "IC108") (pin "21") (pinfunction "21_21") (pintype "passive"))
      (node (ref "IC109") (pin "21") (pinfunction "21_21") (pintype "passive"))
    )
    (net (code "647") (name "Net-(IC106-Pad22)") (class "Default")
      (node (ref "IC106") (pin "22") (pinfunction "22_22") (pintype "passive"))
      (node (ref "IC107") (pin "22") (pinfunction "22_22") (pintype "passive"))
      (node (ref "IC108") (pin "22") (pinfunction "22_22") (pintype "passive"))
      (node (ref "IC109") (pin "22") (pinfunction "22_22") (pintype "passive"))
    )
    (net (code "648") (name "Net-(IC106-Pad23)") (class "Default")
      (node (ref "IC106") (pin "23") (pinfunction "23_23") (pintype "passive"))
      (node (ref "IC107") (pin "23") (pinfunction "23_23") (pintype "passive"))
      (node (ref "IC108") (pin "23") (pinfunction "23_23") (pintype "passive"))
      (node (ref "IC109") (pin "23") (pinfunction "23_23") (pintype "passive"))
    )
    (net (code "649") (name "Net-(IC106-Pad24)") (class "Default")
      (node (ref "IC106") (pin "24") (pinfunction "24_24") (pintype "passive"))
      (node (ref "IC107") (pin "24") (pinfunction "24_24") (pintype "passive"))
      (node (ref "IC108") (pin "24") (pinfunction "24_24") (pintype "passive"))
      (node (ref "IC109") (pin "24") (pinfunction "24_24") (pintype "passive"))
    )
    (net (code "650") (name "Net-(IC110-Pad1)") (class "Default")
      (node (ref "IC110") (pin "1") (pinfunction "1_1") (pintype "passive"))
      (node (ref "IC111") (pin "1") (pinfunction "1_1") (pintype "passive"))
      (node (ref "IC112") (pin "1") (pinfunction "1_1") (pintype "passive"))
      (node (ref "IC9") (pin "1") (pinfunction "1_1") (pintype "passive"))
    )
    (net (code "651") (name "Net-(IC110-Pad2)") (class "Default")
      (node (ref "IC110") (pin "2") (pinfunction "2_2") (pintype "passive"))
      (node (ref "IC111") (pin "2") (pinfunction "2_2") (pintype "passive"))
      (node (ref "IC112") (pin "2") (pinfunction "2_2") (pintype "passive"))
      (node (ref "IC9") (pin "2") (pinfunction "2_2") (pintype "passive"))
    )
    (net (code "652") (name "Net-(IC110-Pad3)") (class "Default")
      (node (ref "IC110") (pin "3") (pinfunction "3_3") (pintype "passive"))
      (node (ref "IC111") (pin "3") (pinfunction "3_3") (pintype "passive"))
      (node (ref "IC112") (pin "3") (pinfunction "3_3") (pintype "passive"))
      (node (ref "IC9") (pin "3") (pinfunction "3_3") (pintype "passive"))
    )
    (net (code "653") (name "Net-(IC110-Pad4)") (class "Default")
      (node (ref "IC110") (pin "4") (pinfunction "4_4") (pintype "passive"))
      (node (ref "IC111") (pin "4") (pinfunction "4_4") (pintype "passive"))
      (node (ref "IC112") (pin "4") (pinfunction "4_4") (pintype "passive"))
      (node (ref "IC9") (pin "4") (pinfunction "4_4") (pintype "passive"))
    )
    (net (code "654") (name "Net-(IC110-Pad5)") (class "Default")
      (node (ref "IC110") (pin "5") (pinfunction "5_5") (pintype "passive"))
      (node (ref "IC111") (pin "5") (pinfunction "5_5") (pintype "passive"))
      (node (ref "IC112") (pin "5") (pinfunction "5_5") (pintype "passive"))
      (node (ref "IC9") (pin "5") (pinfunction "5_5") (pintype "passive"))
    )
    (net (code "655") (name "Net-(IC110-Pad6)") (class "Default")
      (node (ref "IC110") (pin "6") (pinfunction "6_6") (pintype "passive"))
      (node (ref "IC111") (pin "6") (pinfunction "6_6") (pintype "passive"))
      (node (ref "IC112") (pin "6") (pinfunction "6_6") (pintype "passive"))
      (node (ref "IC9") (pin "6") (pinfunction "6_6") (pintype "passive"))
    )
    (net (code "656") (name "Net-(IC110-Pad7)") (class "Default")
      (node (ref "IC110") (pin "7") (pinfunction "7_7") (pintype "passive"))
      (node (ref "IC111") (pin "7") (pinfunction "7_7") (pintype "passive"))
      (node (ref "IC112") (pin "7") (pinfunction "7_7") (pintype "passive"))
      (node (ref "IC9") (pin "7") (pinfunction "7_7") (pintype "passive"))
    )
    (net (code "657") (name "Net-(IC110-Pad8)") (class "Default")
      (node (ref "IC110") (pin "8") (pinfunction "8_8") (pintype "passive"))
      (node (ref "IC111") (pin "8") (pinfunction "8_8") (pintype "passive"))
      (node (ref "IC112") (pin "8") (pinfunction "8_8") (pintype "passive"))
      (node (ref "IC9") (pin "8") (pinfunction "8_8") (pintype "passive"))
    )
    (net (code "658") (name "Net-(IC110-Pad9)") (class "Default")
      (node (ref "IC110") (pin "9") (pinfunction "9_9") (pintype "passive"))
      (node (ref "IC111") (pin "9") (pinfunction "9_9") (pintype "passive"))
      (node (ref "IC112") (pin "9") (pinfunction "9_9") (pintype "passive"))
      (node (ref "IC9") (pin "9") (pinfunction "9_9") (pintype "passive"))
    )
    (net (code "659") (name "Net-(IC110-Pad10)") (class "Default")
      (node (ref "IC110") (pin "10") (pinfunction "10_10") (pintype "passive"))
      (node (ref "IC111") (pin "10") (pinfunction "10_10") (pintype "passive"))
      (node (ref "IC112") (pin "10") (pinfunction "10_10") (pintype "passive"))
      (node (ref "IC9") (pin "10") (pinfunction "10_10") (pintype "passive"))
    )
    (net (code "660") (name "Net-(IC110-Pad11)") (class "Default")
      (node (ref "IC110") (pin "11") (pinfunction "11_11") (pintype "passive"))
      (node (ref "IC111") (pin "11") (pinfunction "11_11") (pintype "passive"))
      (node (ref "IC112") (pin "11") (pinfunction "11_11") (pintype "passive"))
      (node (ref "IC9") (pin "11") (pinfunction "11_11") (pintype "passive"))
    )
    (net (code "661") (name "Net-(IC110-Pad12)") (class "Default")
      (node (ref "IC110") (pin "12") (pinfunction "12_12") (pintype "passive"))
      (node (ref "IC111") (pin "12") (pinfunction "12_12") (pintype "passive"))
      (node (ref "IC112") (pin "12") (pinfunction "12_12") (pintype "passive"))
      (node (ref "IC9") (pin "12") (pinfunction "12_12") (pintype "passive"))
    )
    (net (code "662") (name "Net-(IC110-Pad13)") (class "Default")
      (node (ref "IC110") (pin "13") (pinfunction "13_13") (pintype "passive"))
      (node (ref "IC111") (pin "13") (pinfunction "13_13") (pintype "passive"))
      (node (ref "IC112") (pin "13") (pinfunction "13_13") (pintype "passive"))
      (node (ref "IC9") (pin "13") (pinfunction "13_13") (pintype "passive"))
    )
    (net (code "663") (name "Net-(IC110-Pad14)") (class "Default")
      (node (ref "IC110") (pin "14") (pinfunction "14_14") (pintype "passive"))
      (node (ref "IC111") (pin "14") (pinfunction "14_14") (pintype "passive"))
      (node (ref "IC112") (pin "14") (pinfunction "14_14") (pintype "passive"))
      (node (ref "IC9") (pin "14") (pinfunction "14_14") (pintype "passive"))
    )
    (net (code "664") (name "Net-(IC110-Pad15)") (class "Default")
      (node (ref "IC110") (pin "15") (pinfunction "15_15") (pintype "passive"))
      (node (ref "IC111") (pin "15") (pinfunction "15_15") (pintype "passive"))
      (node (ref "IC112") (pin "15") (pinfunction "15_15") (pintype "passive"))
      (node (ref "IC9") (pin "15") (pinfunction "15_15") (pintype "passive"))
    )
    (net (code "665") (name "Net-(IC110-Pad16)") (class "Default")
      (node (ref "IC110") (pin "16") (pinfunction "16_16") (pintype "passive"))
      (node (ref "IC111") (pin "16") (pinfunction "16_16") (pintype "passive"))
      (node (ref "IC112") (pin "16") (pinfunction "16_16") (pintype "passive"))
      (node (ref "IC9") (pin "16") (pinfunction "16_16") (pintype "passive"))
    )
    (net (code "666") (name "Net-(IC110-Pad17)") (class "Default")
      (node (ref "IC110") (pin "17") (pinfunction "17_17") (pintype "passive"))
      (node (ref "IC111") (pin "17") (pinfunction "17_17") (pintype "passive"))
      (node (ref "IC112") (pin "17") (pinfunction "17_17") (pintype "passive"))
      (node (ref "IC9") (pin "17") (pinfunction "17_17") (pintype "passive"))
    )
    (net (code "667") (name "Net-(IC110-Pad18)") (class "Default")
      (node (ref "IC110") (pin "18") (pinfunction "18_18") (pintype "passive"))
      (node (ref "IC111") (pin "18") (pinfunction "18_18") (pintype "passive"))
      (node (ref "IC112") (pin "18") (pinfunction "18_18") (pintype "passive"))
      (node (ref "IC9") (pin "18") (pinfunction "18_18") (pintype "passive"))
    )
    (net (code "668") (name "Net-(IC110-Pad19)") (class "Default")
      (node (ref "IC110") (pin "19") (pinfunction "19_19") (pintype "passive"))
      (node (ref "IC111") (pin "19") (pinfunction "19_19") (pintype "passive"))
      (node (ref "IC112") (pin "19") (pinfunction "19_19") (pintype "passive"))
      (node (ref "IC9") (pin "19") (pinfunction "19_19") (pintype "passive"))
    )
    (net (code "669") (name "Net-(IC110-Pad20)") (class "Default")
      (node (ref "IC110") (pin "20") (pinfunction "20_20") (pintype "passive"))
      (node (ref "IC111") (pin "20") (pinfunction "20_20") (pintype "passive"))
      (node (ref "IC112") (pin "20") (pinfunction "20_20") (pintype "passive"))
      (node (ref "IC9") (pin "20") (pinfunction "20_20") (pintype "passive"))
    )
    (net (code "670") (name "Net-(IC110-Pad21)") (class "Default")
      (node (ref "IC110") (pin "21") (pinfunction "21_21") (pintype "passive"))
      (node (ref "IC111") (pin "21") (pinfunction "21_21") (pintype "passive"))
      (node (ref "IC112") (pin "21") (pinfunction "21_21") (pintype "passive"))
      (node (ref "IC9") (pin "21") (pinfunction "21_21") (pintype "passive"))
    )
    (net (code "671") (name "Net-(IC110-Pad22)") (class "Default")
      (node (ref "IC110") (pin "22") (pinfunction "22_22") (pintype "passive"))
      (node (ref "IC111") (pin "22") (pinfunction "22_22") (pintype "passive"))
      (node (ref "IC112") (pin "22") (pinfunction "22_22") (pintype "passive"))
      (node (ref "IC9") (pin "22") (pinfunction "22_22") (pintype "passive"))
    )
    (net (code "672") (name "Net-(IC110-Pad23)") (class "Default")
      (node (ref "IC110") (pin "23") (pinfunction "23_23") (pintype "passive"))
      (node (ref "IC111") (pin "23") (pinfunction "23_23") (pintype "passive"))
      (node (ref "IC112") (pin "23") (pinfunction "23_23") (pintype "passive"))
      (node (ref "IC9") (pin "23") (pinfunction "23_23") (pintype "passive"))
    )
    (net (code "673") (name "Net-(IC110-Pad24)") (class "Default")
      (node (ref "IC110") (pin "24") (pinfunction "24_24") (pintype "passive"))
      (node (ref "IC111") (pin "24") (pinfunction "24_24") (pintype "passive"))
      (node (ref "IC112") (pin "24") (pinfunction "24_24") (pintype "passive"))
      (node (ref "IC9") (pin "24") (pinfunction "24_24") (pintype "passive"))
    )
    (net (code "674") (name "Net-(IC113-Pad1)") (class "Default")
      (node (ref "IC113") (pin "1") (pinfunction "1_1") (pintype "passive"))
      (node (ref "IC114") (pin "1") (pinfunction "1_1") (pintype "passive"))
      (node (ref "IC115") (pin "1") (pinfunction "1_1") (pintype "passive"))
      (node (ref "IC116") (pin "1") (pinfunction "1_1") (pintype "passive"))
    )
    (net (code "675") (name "Net-(IC113-Pad2)") (class "Default")
      (node (ref "IC113") (pin "2") (pinfunction "2_2") (pintype "passive"))
      (node (ref "IC114") (pin "2") (pinfunction "2_2") (pintype "passive"))
      (node (ref "IC115") (pin "2") (pinfunction "2_2") (pintype "passive"))
      (node (ref "IC116") (pin "2") (pinfunction "2_2") (pintype "passive"))
    )
    (net (code "676") (name "Net-(IC113-Pad3)") (class "Default")
      (node (ref "IC113") (pin "3") (pinfunction "3_3") (pintype "passive"))
      (node (ref "IC114") (pin "3") (pinfunction "3_3") (pintype "passive"))
      (node (ref "IC115") (pin "3") (pinfunction "3_3") (pintype "passive"))
      (node (ref "IC116") (pin "3") (pinfunction "3_3") (pintype "passive"))
    )
    (net (code "677") (name "Net-(IC113-Pad4)") (class "Default")
      (node (ref "IC113") (pin "4") (pinfunction "4_4") (pintype "passive"))
      (node (ref "IC114") (pin "4") (pinfunction "4_4") (pintype "passive"))
      (node (ref "IC115") (pin "4") (pinfunction "4_4") (pintype "passive"))
      (node (ref "IC116") (pin "4") (pinfunction "4_4") (pintype "passive"))
    )
    (net (code "678") (name "Net-(IC113-Pad5)") (class "Default")
      (node (ref "IC113") (pin "5") (pinfunction "5_5") (pintype "passive"))
      (node (ref "IC114") (pin "5") (pinfunction "5_5") (pintype "passive"))
      (node (ref "IC115") (pin "5") (pinfunction "5_5") (pintype "passive"))
      (node (ref "IC116") (pin "5") (pinfunction "5_5") (pintype "passive"))
    )
    (net (code "679") (name "Net-(IC113-Pad6)") (class "Default")
      (node (ref "IC113") (pin "6") (pinfunction "6_6") (pintype "passive"))
      (node (ref "IC114") (pin "6") (pinfunction "6_6") (pintype "passive"))
      (node (ref "IC115") (pin "6") (pinfunction "6_6") (pintype "passive"))
      (node (ref "IC116") (pin "6") (pinfunction "6_6") (pintype "passive"))
    )
    (net (code "680") (name "Net-(IC113-Pad7)") (class "Default")
      (node (ref "IC113") (pin "7") (pinfunction "7_7") (pintype "passive"))
      (node (ref "IC114") (pin "7") (pinfunction "7_7") (pintype "passive"))
      (node (ref "IC115") (pin "7") (pinfunction "7_7") (pintype "passive"))
      (node (ref "IC116") (pin "7") (pinfunction "7_7") (pintype "passive"))
    )
    (net (code "681") (name "Net-(IC113-Pad8)") (class "Default")
      (node (ref "IC113") (pin "8") (pinfunction "8_8") (pintype "passive"))
      (node (ref "IC114") (pin "8") (pinfunction "8_8") (pintype "passive"))
      (node (ref "IC115") (pin "8") (pinfunction "8_8") (pintype "passive"))
      (node (ref "IC116") (pin "8") (pinfunction "8_8") (pintype "passive"))
    )
    (net (code "682") (name "Net-(IC113-Pad9)") (class "Default")
      (node (ref "IC113") (pin "9") (pinfunction "9_9") (pintype "passive"))
      (node (ref "IC114") (pin "9") (pinfunction "9_9") (pintype "passive"))
      (node (ref "IC115") (pin "9") (pinfunction "9_9") (pintype "passive"))
      (node (ref "IC116") (pin "9") (pinfunction "9_9") (pintype "passive"))
    )
    (net (code "683") (name "Net-(IC113-Pad10)") (class "Default")
      (node (ref "IC113") (pin "10") (pinfunction "10_10") (pintype "passive"))
      (node (ref "IC114") (pin "10") (pinfunction "10_10") (pintype "passive"))
      (node (ref "IC115") (pin "10") (pinfunction "10_10") (pintype "passive"))
      (node (ref "IC116") (pin "10") (pinfunction "10_10") (pintype "passive"))
    )
    (net (code "684") (name "Net-(IC113-Pad11)") (class "Default")
      (node (ref "IC113") (pin "11") (pinfunction "11_11") (pintype "passive"))
      (node (ref "IC114") (pin "11") (pinfunction "11_11") (pintype "passive"))
      (node (ref "IC115") (pin "11") (pinfunction "11_11") (pintype "passive"))
      (node (ref "IC116") (pin "11") (pinfunction "11_11") (pintype "passive"))
    )
    (net (code "685") (name "Net-(IC113-Pad12)") (class "Default")
      (node (ref "IC113") (pin "12") (pinfunction "12_12") (pintype "passive"))
      (node (ref "IC114") (pin "12") (pinfunction "12_12") (pintype "passive"))
      (node (ref "IC115") (pin "12") (pinfunction "12_12") (pintype "passive"))
      (node (ref "IC116") (pin "12") (pinfunction "12_12") (pintype "passive"))
    )
    (net (code "686") (name "Net-(IC113-Pad13)") (class "Default")
      (node (ref "IC113") (pin "13") (pinfunction "13_13") (pintype "passive"))
      (node (ref "IC114") (pin "13") (pinfunction "13_13") (pintype "passive"))
      (node (ref "IC115") (pin "13") (pinfunction "13_13") (pintype "passive"))
      (node (ref "IC116") (pin "13") (pinfunction "13_13") (pintype "passive"))
    )
    (net (code "687") (name "Net-(IC113-Pad14)") (class "Default")
      (node (ref "IC113") (pin "14") (pinfunction "14_14") (pintype "passive"))
      (node (ref "IC114") (pin "14") (pinfunction "14_14") (pintype "passive"))
      (node (ref "IC115") (pin "14") (pinfunction "14_14") (pintype "passive"))
      (node (ref "IC116") (pin "14") (pinfunction "14_14") (pintype "passive"))
    )
    (net (code "688") (name "Net-(IC113-Pad15)") (class "Default")
      (node (ref "IC113") (pin "15") (pinfunction "15_15") (pintype "passive"))
      (node (ref "IC114") (pin "15") (pinfunction "15_15") (pintype "passive"))
      (node (ref "IC115") (pin "15") (pinfunction "15_15") (pintype "passive"))
      (node (ref "IC116") (pin "15") (pinfunction "15_15") (pintype "passive"))
    )
    (net (code "689") (name "Net-(IC113-Pad16)") (class "Default")
      (node (ref "IC113") (pin "16") (pinfunction "16_16") (pintype "passive"))
      (node (ref "IC114") (pin "16") (pinfunction "16_16") (pintype "passive"))
      (node (ref "IC115") (pin "16") (pinfunction "16_16") (pintype "passive"))
      (node (ref "IC116") (pin "16") (pinfunction "16_16") (pintype "passive"))
    )
    (net (code "690") (name "Net-(IC113-Pad17)") (class "Default")
      (node (ref "IC113") (pin "17") (pinfunction "17_17") (pintype "passive"))
      (node (ref "IC114") (pin "17") (pinfunction "17_17") (pintype "passive"))
      (node (ref "IC115") (pin "17") (pinfunction "17_17") (pintype "passive"))
      (node (ref "IC116") (pin "17") (pinfunction "17_17") (pintype "passive"))
    )
    (net (code "691") (name "Net-(IC113-Pad18)") (class "Default")
      (node (ref "IC113") (pin "18") (pinfunction "18_18") (pintype "passive"))
      (node (ref "IC114") (pin "18") (pinfunction "18_18") (pintype "passive"))
      (node (ref "IC115") (pin "18") (pinfunction "18_18") (pintype "passive"))
      (node (ref "IC116") (pin "18") (pinfunction "18_18") (pintype "passive"))
    )
    (net (code "692") (name "Net-(IC113-Pad19)") (class "Default")
      (node (ref "IC113") (pin "19") (pinfunction "19_19") (pintype "passive"))
      (node (ref "IC114") (pin "19") (pinfunction "19_19") (pintype "passive"))
      (node (ref "IC115") (pin "19") (pinfunction "19_19") (pintype "passive"))
      (node (ref "IC116") (pin "19") (pinfunction "19_19") (pintype "passive"))
    )
    (net (code "693") (name "Net-(IC113-Pad20)") (class "Default")
      (node (ref "IC113") (pin "20") (pinfunction "20_20") (pintype "passive"))
      (node (ref "IC114") (pin "20") (pinfunction "20_20") (pintype "passive"))
      (node (ref "IC115") (pin "20") (pinfunction "20_20") (pintype "passive"))
      (node (ref "IC116") (pin "20") (pinfunction "20_20") (pintype "passive"))
    )
    (net (code "694") (name "Net-(IC113-Pad21)") (class "Default")
      (node (ref "IC113") (pin "21") (pinfunction "21_21") (pintype "passive"))
      (node (ref "IC114") (pin "21") (pinfunction "21_21") (pintype "passive"))
      (node (ref "IC115") (pin "21") (pinfunction "21_21") (pintype "passive"))
      (node (ref "IC116") (pin "21") (pinfunction "21_21") (pintype "passive"))
    )
    (net (code "695") (name "Net-(IC113-Pad22)") (class "Default")
      (node (ref "IC113") (pin "22") (pinfunction "22_22") (pintype "passive"))
      (node (ref "IC114") (pin "22") (pinfunction "22_22") (pintype "passive"))
      (node (ref "IC115") (pin "22") (pinfunction "22_22") (pintype "passive"))
      (node (ref "IC116") (pin "22") (pinfunction "22_22") (pintype "passive"))
    )
    (net (code "696") (name "Net-(IC113-Pad23)") (class "Default")
      (node (ref "IC113") (pin "23") (pinfunction "23_23") (pintype "passive"))
      (node (ref "IC114") (pin "23") (pinfunction "23_23") (pintype "passive"))
      (node (ref "IC115") (pin "23") (pinfunction "23_23") (pintype "passive"))
      (node (ref "IC116") (pin "23") (pinfunction "23_23") (pintype "passive"))
    )
    (net (code "697") (name "Net-(IC113-Pad24)") (class "Default")
      (node (ref "IC113") (pin "24") (pinfunction "24_24") (pintype "passive"))
      (node (ref "IC114") (pin "24") (pinfunction "24_24") (pintype "passive"))
      (node (ref "IC115") (pin "24") (pinfunction "24_24") (pintype "passive"))
      (node (ref "IC116") (pin "24") (pinfunction "24_24") (pintype "passive"))
    )
    (net (code "698") (name "Net-(IC117-Pad1)") (class "Default")
      (node (ref "IC117") (pin "1") (pinfunction "1_1") (pintype "passive"))
      (node (ref "IC118") (pin "1") (pinfunction "1_1") (pintype "passive"))
      (node (ref "IC119") (pin "1") (pinfunction "1_1") (pintype "passive"))
      (node (ref "IC120") (pin "1") (pinfunction "1_1") (pintype "passive"))
    )
    (net (code "699") (name "Net-(IC117-Pad2)") (class "Default")
      (node (ref "IC117") (pin "2") (pinfunction "2_2") (pintype "passive"))
      (node (ref "IC118") (pin "2") (pinfunction "2_2") (pintype "passive"))
      (node (ref "IC119") (pin "2") (pinfunction "2_2") (pintype "passive"))
      (node (ref "IC120") (pin "2") (pinfunction "2_2") (pintype "passive"))
    )
    (net (code "700") (name "Net-(IC117-Pad3)") (class "Default")
      (node (ref "IC117") (pin "3") (pinfunction "3_3") (pintype "passive"))
      (node (ref "IC118") (pin "3") (pinfunction "3_3") (pintype "passive"))
      (node (ref "IC119") (pin "3") (pinfunction "3_3") (pintype "passive"))
      (node (ref "IC120") (pin "3") (pinfunction "3_3") (pintype "passive"))
    )
    (net (code "701") (name "Net-(IC117-Pad4)") (class "Default")
      (node (ref "IC117") (pin "4") (pinfunction "4_4") (pintype "passive"))
      (node (ref "IC118") (pin "4") (pinfunction "4_4") (pintype "passive"))
      (node (ref "IC119") (pin "4") (pinfunction "4_4") (pintype "passive"))
      (node (ref "IC120") (pin "4") (pinfunction "4_4") (pintype "passive"))
    )
    (net (code "702") (name "Net-(IC117-Pad5)") (class "Default")
      (node (ref "IC117") (pin "5") (pinfunction "5_5") (pintype "passive"))
      (node (ref "IC118") (pin "5") (pinfunction "5_5") (pintype "passive"))
      (node (ref "IC119") (pin "5") (pinfunction "5_5") (pintype "passive"))
      (node (ref "IC120") (pin "5") (pinfunction "5_5") (pintype "passive"))
    )
    (net (code "703") (name "Net-(IC117-Pad6)") (class "Default")
      (node (ref "IC117") (pin "6") (pinfunction "6_6") (pintype "passive"))
      (node (ref "IC118") (pin "6") (pinfunction "6_6") (pintype "passive"))
      (node (ref "IC119") (pin "6") (pinfunction "6_6") (pintype "passive"))
      (node (ref "IC120") (pin "6") (pinfunction "6_6") (pintype "passive"))
    )
    (net (code "704") (name "Net-(IC117-Pad7)") (class "Default")
      (node (ref "IC117") (pin "7") (pinfunction "7_7") (pintype "passive"))
      (node (ref "IC118") (pin "7") (pinfunction "7_7") (pintype "passive"))
      (node (ref "IC119") (pin "7") (pinfunction "7_7") (pintype "passive"))
      (node (ref "IC120") (pin "7") (pinfunction "7_7") (pintype "passive"))
    )
    (net (code "705") (name "Net-(IC117-Pad8)") (class "Default")
      (node (ref "IC117") (pin "8") (pinfunction "8_8") (pintype "passive"))
      (node (ref "IC118") (pin "8") (pinfunction "8_8") (pintype "passive"))
      (node (ref "IC119") (pin "8") (pinfunction "8_8") (pintype "passive"))
      (node (ref "IC120") (pin "8") (pinfunction "8_8") (pintype "passive"))
    )
    (net (code "706") (name "Net-(IC117-Pad9)") (class "Default")
      (node (ref "IC117") (pin "9") (pinfunction "9_9") (pintype "passive"))
      (node (ref "IC118") (pin "9") (pinfunction "9_9") (pintype "passive"))
      (node (ref "IC119") (pin "9") (pinfunction "9_9") (pintype "passive"))
      (node (ref "IC120") (pin "9") (pinfunction "9_9") (pintype "passive"))
    )
    (net (code "707") (name "Net-(IC117-Pad10)") (class "Default")
      (node (ref "IC117") (pin "10") (pinfunction "10_10") (pintype "passive"))
      (node (ref "IC118") (pin "10") (pinfunction "10_10") (pintype "passive"))
      (node (ref "IC119") (pin "10") (pinfunction "10_10") (pintype "passive"))
      (node (ref "IC120") (pin "10") (pinfunction "10_10") (pintype "passive"))
    )
    (net (code "708") (name "Net-(IC117-Pad11)") (class "Default")
      (node (ref "IC117") (pin "11") (pinfunction "11_11") (pintype "passive"))
      (node (ref "IC118") (pin "11") (pinfunction "11_11") (pintype "passive"))
      (node (ref "IC119") (pin "11") (pinfunction "11_11") (pintype "passive"))
      (node (ref "IC120") (pin "11") (pinfunction "11_11") (pintype "passive"))
    )
    (net (code "709") (name "Net-(IC117-Pad12)") (class "Default")
      (node (ref "IC117") (pin "12") (pinfunction "12_12") (pintype "passive"))
      (node (ref "IC118") (pin "12") (pinfunction "12_12") (pintype "passive"))
      (node (ref "IC119") (pin "12") (pinfunction "12_12") (pintype "passive"))
      (node (ref "IC120") (pin "12") (pinfunction "12_12") (pintype "passive"))
    )
    (net (code "710") (name "Net-(IC117-Pad13)") (class "Default")
      (node (ref "IC117") (pin "13") (pinfunction "13_13") (pintype "passive"))
      (node (ref "IC118") (pin "13") (pinfunction "13_13") (pintype "passive"))
      (node (ref "IC119") (pin "13") (pinfunction "13_13") (pintype "passive"))
      (node (ref "IC120") (pin "13") (pinfunction "13_13") (pintype "passive"))
    )
    (net (code "711") (name "Net-(IC117-Pad14)") (class "Default")
      (node (ref "IC117") (pin "14") (pinfunction "14_14") (pintype "passive"))
      (node (ref "IC118") (pin "14") (pinfunction "14_14") (pintype "passive"))
      (node (ref "IC119") (pin "14") (pinfunction "14_14") (pintype "passive"))
      (node (ref "IC120") (pin "14") (pinfunction "14_14") (pintype "passive"))
    )
    (net (code "712") (name "Net-(IC117-Pad15)") (class "Default")
      (node (ref "IC117") (pin "15") (pinfunction "15_15") (pintype "passive"))
      (node (ref "IC118") (pin "15") (pinfunction "15_15") (pintype "passive"))
      (node (ref "IC119") (pin "15") (pinfunction "15_15") (pintype "passive"))
      (node (ref "IC120") (pin "15") (pinfunction "15_15") (pintype "passive"))
    )
    (net (code "713") (name "Net-(IC117-Pad16)") (class "Default")
      (node (ref "IC117") (pin "16") (pinfunction "16_16") (pintype "passive"))
      (node (ref "IC118") (pin "16") (pinfunction "16_16") (pintype "passive"))
      (node (ref "IC119") (pin "16") (pinfunction "16_16") (pintype "passive"))
      (node (ref "IC120") (pin "16") (pinfunction "16_16") (pintype "passive"))
    )
    (net (code "714") (name "Net-(IC117-Pad17)") (class "Default")
      (node (ref "IC117") (pin "17") (pinfunction "17_17") (pintype "passive"))
      (node (ref "IC118") (pin "17") (pinfunction "17_17") (pintype "passive"))
      (node (ref "IC119") (pin "17") (pinfunction "17_17") (pintype "passive"))
      (node (ref "IC120") (pin "17") (pinfunction "17_17") (pintype "passive"))
    )
    (net (code "715") (name "Net-(IC117-Pad18)") (class "Default")
      (node (ref "IC117") (pin "18") (pinfunction "18_18") (pintype "passive"))
      (node (ref "IC118") (pin "18") (pinfunction "18_18") (pintype "passive"))
      (node (ref "IC119") (pin "18") (pinfunction "18_18") (pintype "passive"))
      (node (ref "IC120") (pin "18") (pinfunction "18_18") (pintype "passive"))
    )
    (net (code "716") (name "Net-(IC117-Pad19)") (class "Default")
      (node (ref "IC117") (pin "19") (pinfunction "19_19") (pintype "passive"))
      (node (ref "IC118") (pin "19") (pinfunction "19_19") (pintype "passive"))
      (node (ref "IC119") (pin "19") (pinfunction "19_19") (pintype "passive"))
      (node (ref "IC120") (pin "19") (pinfunction "19_19") (pintype "passive"))
    )
    (net (code "717") (name "Net-(IC117-Pad20)") (class "Default")
      (node (ref "IC117") (pin "20") (pinfunction "20_20") (pintype "passive"))
      (node (ref "IC118") (pin "20") (pinfunction "20_20") (pintype "passive"))
      (node (ref "IC119") (pin "20") (pinfunction "20_20") (pintype "passive"))
      (node (ref "IC120") (pin "20") (pinfunction "20_20") (pintype "passive"))
    )
    (net (code "718") (name "Net-(IC117-Pad21)") (class "Default")
      (node (ref "IC117") (pin "21") (pinfunction "21_21") (pintype "passive"))
      (node (ref "IC118") (pin "21") (pinfunction "21_21") (pintype "passive"))
      (node (ref "IC119") (pin "21") (pinfunction "21_21") (pintype "passive"))
      (node (ref "IC120") (pin "21") (pinfunction "21_21") (pintype "passive"))
    )
    (net (code "719") (name "Net-(IC117-Pad22)") (class "Default")
      (node (ref "IC117") (pin "22") (pinfunction "22_22") (pintype "passive"))
      (node (ref "IC118") (pin "22") (pinfunction "22_22") (pintype "passive"))
      (node (ref "IC119") (pin "22") (pinfunction "22_22") (pintype "passive"))
      (node (ref "IC120") (pin "22") (pinfunction "22_22") (pintype "passive"))
    )
    (net (code "720") (name "Net-(IC117-Pad23)") (class "Default")
      (node (ref "IC117") (pin "23") (pinfunction "23_23") (pintype "passive"))
      (node (ref "IC118") (pin "23") (pinfunction "23_23") (pintype "passive"))
      (node (ref "IC119") (pin "23") (pinfunction "23_23") (pintype "passive"))
      (node (ref "IC120") (pin "23") (pinfunction "23_23") (pintype "passive"))
    )
    (net (code "721") (name "Net-(IC117-Pad24)") (class "Default")
      (node (ref "IC117") (pin "24") (pinfunction "24_24") (pintype "passive"))
      (node (ref "IC118") (pin "24") (pinfunction "24_24") (pintype "passive"))
      (node (ref "IC119") (pin "24") (pinfunction "24_24") (pintype "passive"))
      (node (ref "IC120") (pin "24") (pinfunction "24_24") (pintype "passive"))
    )
    (net (code "722") (name "Net-(IC121-Pad1)") (class "Default")
      (node (ref "IC121") (pin "1") (pinfunction "1_1") (pintype "passive"))
      (node (ref "IC122") (pin "1") (pinfunction "1_1") (pintype "passive"))
      (node (ref "IC123") (pin "1") (pinfunction "1_1") (pintype "passive"))
      (node (ref "IC124") (pin "1") (pinfunction "1_1") (pintype "passive"))
    )
    (net (code "723") (name "Net-(IC121-Pad2)") (class "Default")
      (node (ref "IC121") (pin "2") (pinfunction "2_2") (pintype "passive"))
      (node (ref "IC122") (pin "2") (pinfunction "2_2") (pintype "passive"))
      (node (ref "IC123") (pin "2") (pinfunction "2_2") (pintype "passive"))
      (node (ref "IC124") (pin "2") (pinfunction "2_2") (pintype "passive"))
    )
    (net (code "724") (name "Net-(IC121-Pad3)") (class "Default")
      (node (ref "IC121") (pin "3") (pinfunction "3_3") (pintype "passive"))
      (node (ref "IC122") (pin "3") (pinfunction "3_3") (pintype "passive"))
      (node (ref "IC123") (pin "3") (pinfunction "3_3") (pintype "passive"))
      (node (ref "IC124") (pin "3") (pinfunction "3_3") (pintype "passive"))
    )
    (net (code "725") (name "Net-(IC121-Pad4)") (class "Default")
      (node (ref "IC121") (pin "4") (pinfunction "4_4") (pintype "passive"))
      (node (ref "IC122") (pin "4") (pinfunction "4_4") (pintype "passive"))
      (node (ref "IC123") (pin "4") (pinfunction "4_4") (pintype "passive"))
      (node (ref "IC124") (pin "4") (pinfunction "4_4") (pintype "passive"))
    )
    (net (code "726") (name "Net-(IC121-Pad5)") (class "Default")
      (node (ref "IC121") (pin "5") (pinfunction "5_5") (pintype "passive"))
      (node (ref "IC122") (pin "5") (pinfunction "5_5") (pintype "passive"))
      (node (ref "IC123") (pin "5") (pinfunction "5_5") (pintype "passive"))
      (node (ref "IC124") (pin "5") (pinfunction "5_5") (pintype "passive"))
    )
    (net (code "727") (name "Net-(IC121-Pad6)") (class "Default")
      (node (ref "IC121") (pin "6") (pinfunction "6_6") (pintype "passive"))
      (node (ref "IC122") (pin "6") (pinfunction "6_6") (pintype "passive"))
      (node (ref "IC123") (pin "6") (pinfunction "6_6") (pintype "passive"))
      (node (ref "IC124") (pin "6") (pinfunction "6_6") (pintype "passive"))
    )
    (net (code "728") (name "Net-(IC121-Pad7)") (class "Default")
      (node (ref "IC121") (pin "7") (pinfunction "7_7") (pintype "passive"))
      (node (ref "IC122") (pin "7") (pinfunction "7_7") (pintype "passive"))
      (node (ref "IC123") (pin "7") (pinfunction "7_7") (pintype "passive"))
      (node (ref "IC124") (pin "7") (pinfunction "7_7") (pintype "passive"))
    )
    (net (code "729") (name "Net-(IC121-Pad8)") (class "Default")
      (node (ref "IC121") (pin "8") (pinfunction "8_8") (pintype "passive"))
      (node (ref "IC122") (pin "8") (pinfunction "8_8") (pintype "passive"))
      (node (ref "IC123") (pin "8") (pinfunction "8_8") (pintype "passive"))
      (node (ref "IC124") (pin "8") (pinfunction "8_8") (pintype "passive"))
    )
    (net (code "730") (name "Net-(IC121-Pad9)") (class "Default")
      (node (ref "IC121") (pin "9") (pinfunction "9_9") (pintype "passive"))
      (node (ref "IC122") (pin "9") (pinfunction "9_9") (pintype "passive"))
      (node (ref "IC123") (pin "9") (pinfunction "9_9") (pintype "passive"))
      (node (ref "IC124") (pin "9") (pinfunction "9_9") (pintype "passive"))
    )
    (net (code "731") (name "Net-(IC121-Pad10)") (class "Default")
      (node (ref "IC121") (pin "10") (pinfunction "10_10") (pintype "passive"))
      (node (ref "IC122") (pin "10") (pinfunction "10_10") (pintype "passive"))
      (node (ref "IC123") (pin "10") (pinfunction "10_10") (pintype "passive"))
      (node (ref "IC124") (pin "10") (pinfunction "10_10") (pintype "passive"))
    )
    (net (code "732") (name "Net-(IC121-Pad11)") (class "Default")
      (node (ref "IC121") (pin "11") (pinfunction "11_11") (pintype "passive"))
      (node (ref "IC122") (pin "11") (pinfunction "11_11") (pintype "passive"))
      (node (ref "IC123") (pin "11") (pinfunction "11_11") (pintype "passive"))
      (node (ref "IC124") (pin "11") (pinfunction "11_11") (pintype "passive"))
    )
    (net (code "733") (name "Net-(IC121-Pad12)") (class "Default")
      (node (ref "IC121") (pin "12") (pinfunction "12_12") (pintype "passive"))
      (node (ref "IC122") (pin "12") (pinfunction "12_12") (pintype "passive"))
      (node (ref "IC123") (pin "12") (pinfunction "12_12") (pintype "passive"))
      (node (ref "IC124") (pin "12") (pinfunction "12_12") (pintype "passive"))
    )
    (net (code "734") (name "Net-(IC121-Pad13)") (class "Default")
      (node (ref "IC121") (pin "13") (pinfunction "13_13") (pintype "passive"))
      (node (ref "IC122") (pin "13") (pinfunction "13_13") (pintype "passive"))
      (node (ref "IC123") (pin "13") (pinfunction "13_13") (pintype "passive"))
      (node (ref "IC124") (pin "13") (pinfunction "13_13") (pintype "passive"))
    )
    (net (code "735") (name "Net-(IC121-Pad14)") (class "Default")
      (node (ref "IC121") (pin "14") (pinfunction "14_14") (pintype "passive"))
      (node (ref "IC122") (pin "14") (pinfunction "14_14") (pintype "passive"))
      (node (ref "IC123") (pin "14") (pinfunction "14_14") (pintype "passive"))
      (node (ref "IC124") (pin "14") (pinfunction "14_14") (pintype "passive"))
    )
    (net (code "736") (name "Net-(IC121-Pad15)") (class "Default")
      (node (ref "IC121") (pin "15") (pinfunction "15_15") (pintype "passive"))
      (node (ref "IC122") (pin "15") (pinfunction "15_15") (pintype "passive"))
      (node (ref "IC123") (pin "15") (pinfunction "15_15") (pintype "passive"))
      (node (ref "IC124") (pin "15") (pinfunction "15_15") (pintype "passive"))
    )
    (net (code "737") (name "Net-(IC121-Pad16)") (class "Default")
      (node (ref "IC121") (pin "16") (pinfunction "16_16") (pintype "passive"))
      (node (ref "IC122") (pin "16") (pinfunction "16_16") (pintype "passive"))
      (node (ref "IC123") (pin "16") (pinfunction "16_16") (pintype "passive"))
      (node (ref "IC124") (pin "16") (pinfunction "16_16") (pintype "passive"))
    )
    (net (code "738") (name "Net-(IC121-Pad17)") (class "Default")
      (node (ref "IC121") (pin "17") (pinfunction "17_17") (pintype "passive"))
      (node (ref "IC122") (pin "17") (pinfunction "17_17") (pintype "passive"))
      (node (ref "IC123") (pin "17") (pinfunction "17_17") (pintype "passive"))
      (node (ref "IC124") (pin "17") (pinfunction "17_17") (pintype "passive"))
    )
    (net (code "739") (name "Net-(IC121-Pad18)") (class "Default")
      (node (ref "IC121") (pin "18") (pinfunction "18_18") (pintype "passive"))
      (node (ref "IC122") (pin "18") (pinfunction "18_18") (pintype "passive"))
      (node (ref "IC123") (pin "18") (pinfunction "18_18") (pintype "passive"))
      (node (ref "IC124") (pin "18") (pinfunction "18_18") (pintype "passive"))
    )
    (net (code "740") (name "Net-(IC121-Pad19)") (class "Default")
      (node (ref "IC121") (pin "19") (pinfunction "19_19") (pintype "passive"))
      (node (ref "IC122") (pin "19") (pinfunction "19_19") (pintype "passive"))
      (node (ref "IC123") (pin "19") (pinfunction "19_19") (pintype "passive"))
      (node (ref "IC124") (pin "19") (pinfunction "19_19") (pintype "passive"))
    )
    (net (code "741") (name "Net-(IC121-Pad20)") (class "Default")
      (node (ref "IC121") (pin "20") (pinfunction "20_20") (pintype "passive"))
      (node (ref "IC122") (pin "20") (pinfunction "20_20") (pintype "passive"))
      (node (ref "IC123") (pin "20") (pinfunction "20_20") (pintype "passive"))
      (node (ref "IC124") (pin "20") (pinfunction "20_20") (pintype "passive"))
    )
    (net (code "742") (name "Net-(IC121-Pad21)") (class "Default")
      (node (ref "IC121") (pin "21") (pinfunction "21_21") (pintype "passive"))
      (node (ref "IC122") (pin "21") (pinfunction "21_21") (pintype "passive"))
      (node (ref "IC123") (pin "21") (pinfunction "21_21") (pintype "passive"))
      (node (ref "IC124") (pin "21") (pinfunction "21_21") (pintype "passive"))
    )
    (net (code "743") (name "Net-(IC121-Pad22)") (class "Default")
      (node (ref "IC121") (pin "22") (pinfunction "22_22") (pintype "passive"))
      (node (ref "IC122") (pin "22") (pinfunction "22_22") (pintype "passive"))
      (node (ref "IC123") (pin "22") (pinfunction "22_22") (pintype "passive"))
      (node (ref "IC124") (pin "22") (pinfunction "22_22") (pintype "passive"))
    )
    (net (code "744") (name "Net-(IC121-Pad23)") (class "Default")
      (node (ref "IC121") (pin "23") (pinfunction "23_23") (pintype "passive"))
      (node (ref "IC122") (pin "23") (pinfunction "23_23") (pintype "passive"))
      (node (ref "IC123") (pin "23") (pinfunction "23_23") (pintype "passive"))
      (node (ref "IC124") (pin "23") (pinfunction "23_23") (pintype "passive"))
    )
    (net (code "745") (name "Net-(IC121-Pad24)") (class "Default")
      (node (ref "IC121") (pin "24") (pinfunction "24_24") (pintype "passive"))
      (node (ref "IC122") (pin "24") (pinfunction "24_24") (pintype "passive"))
      (node (ref "IC123") (pin "24") (pinfunction "24_24") (pintype "passive"))
      (node (ref "IC124") (pin "24") (pinfunction "24_24") (pintype "passive"))
    )
    (net (code "746") (name "Net-(IC125-Pad1)") (class "Default")
      (node (ref "IC125") (pin "1") (pinfunction "1_1") (pintype "passive"))
      (node (ref "IC126") (pin "1") (pinfunction "1_1") (pintype "passive"))
      (node (ref "IC127") (pin "1") (pinfunction "1_1") (pintype "passive"))
      (node (ref "IC128") (pin "1") (pinfunction "1_1") (pintype "passive"))
    )
    (net (code "747") (name "Net-(IC125-Pad2)") (class "Default")
      (node (ref "IC125") (pin "2") (pinfunction "2_2") (pintype "passive"))
      (node (ref "IC126") (pin "2") (pinfunction "2_2") (pintype "passive"))
      (node (ref "IC127") (pin "2") (pinfunction "2_2") (pintype "passive"))
      (node (ref "IC128") (pin "2") (pinfunction "2_2") (pintype "passive"))
    )
    (net (code "748") (name "Net-(IC125-Pad3)") (class "Default")
      (node (ref "IC125") (pin "3") (pinfunction "3_3") (pintype "passive"))
      (node (ref "IC126") (pin "3") (pinfunction "3_3") (pintype "passive"))
      (node (ref "IC127") (pin "3") (pinfunction "3_3") (pintype "passive"))
      (node (ref "IC128") (pin "3") (pinfunction "3_3") (pintype "passive"))
    )
    (net (code "749") (name "Net-(IC125-Pad4)") (class "Default")
      (node (ref "IC125") (pin "4") (pinfunction "4_4") (pintype "passive"))
      (node (ref "IC126") (pin "4") (pinfunction "4_4") (pintype "passive"))
      (node (ref "IC127") (pin "4") (pinfunction "4_4") (pintype "passive"))
      (node (ref "IC128") (pin "4") (pinfunction "4_4") (pintype "passive"))
    )
    (net (code "750") (name "Net-(IC125-Pad5)") (class "Default")
      (node (ref "IC125") (pin "5") (pinfunction "5_5") (pintype "passive"))
      (node (ref "IC126") (pin "5") (pinfunction "5_5") (pintype "passive"))
      (node (ref "IC127") (pin "5") (pinfunction "5_5") (pintype "passive"))
      (node (ref "IC128") (pin "5") (pinfunction "5_5") (pintype "passive"))
    )
    (net (code "751") (name "Net-(IC125-Pad6)") (class "Default")
      (node (ref "IC125") (pin "6") (pinfunction "6_6") (pintype "passive"))
      (node (ref "IC126") (pin "6") (pinfunction "6_6") (pintype "passive"))
      (node (ref "IC127") (pin "6") (pinfunction "6_6") (pintype "passive"))
      (node (ref "IC128") (pin "6") (pinfunction "6_6") (pintype "passive"))
    )
    (net (code "752") (name "Net-(IC125-Pad7)") (class "Default")
      (node (ref "IC125") (pin "7") (pinfunction "7_7") (pintype "passive"))
      (node (ref "IC126") (pin "7") (pinfunction "7_7") (pintype "passive"))
      (node (ref "IC127") (pin "7") (pinfunction "7_7") (pintype "passive"))
      (node (ref "IC128") (pin "7") (pinfunction "7_7") (pintype "passive"))
    )
    (net (code "753") (name "Net-(IC125-Pad8)") (class "Default")
      (node (ref "IC125") (pin "8") (pinfunction "8_8") (pintype "passive"))
      (node (ref "IC126") (pin "8") (pinfunction "8_8") (pintype "passive"))
      (node (ref "IC127") (pin "8") (pinfunction "8_8") (pintype "passive"))
      (node (ref "IC128") (pin "8") (pinfunction "8_8") (pintype "passive"))
    )
    (net (code "754") (name "Net-(IC125-Pad9)") (class "Default")
      (node (ref "IC125") (pin "9") (pinfunction "9_9") (pintype "passive"))
      (node (ref "IC126") (pin "9") (pinfunction "9_9") (pintype "passive"))
      (node (ref "IC127") (pin "9") (pinfunction "9_9") (pintype "passive"))
      (node (ref "IC128") (pin "9") (pinfunction "9_9") (pintype "passive"))
    )
    (net (code "755") (name "Net-(IC125-Pad10)") (class "Default")
      (node (ref "IC125") (pin "10") (pinfunction "10_10") (pintype "passive"))
      (node (ref "IC126") (pin "10") (pinfunction "10_10") (pintype "passive"))
      (node (ref "IC127") (pin "10") (pinfunction "10_10") (pintype "passive"))
      (node (ref "IC128") (pin "10") (pinfunction "10_10") (pintype "passive"))
    )
    (net (code "756") (name "Net-(IC125-Pad11)") (class "Default")
      (node (ref "IC125") (pin "11") (pinfunction "11_11") (pintype "passive"))
      (node (ref "IC126") (pin "11") (pinfunction "11_11") (pintype "passive"))
      (node (ref "IC127") (pin "11") (pinfunction "11_11") (pintype "passive"))
      (node (ref "IC128") (pin "11") (pinfunction "11_11") (pintype "passive"))
    )
    (net (code "757") (name "Net-(IC125-Pad12)") (class "Default")
      (node (ref "IC125") (pin "12") (pinfunction "12_12") (pintype "passive"))
      (node (ref "IC126") (pin "12") (pinfunction "12_12") (pintype "passive"))
      (node (ref "IC127") (pin "12") (pinfunction "12_12") (pintype "passive"))
      (node (ref "IC128") (pin "12") (pinfunction "12_12") (pintype "passive"))
    )
    (net (code "758") (name "Net-(IC125-Pad13)") (class "Default")
      (node (ref "IC125") (pin "13") (pinfunction "13_13") (pintype "passive"))
      (node (ref "IC126") (pin "13") (pinfunction "13_13") (pintype "passive"))
      (node (ref "IC127") (pin "13") (pinfunction "13_13") (pintype "passive"))
      (node (ref "IC128") (pin "13") (pinfunction "13_13") (pintype "passive"))
    )
    (net (code "759") (name "Net-(IC125-Pad14)") (class "Default")
      (node (ref "IC125") (pin "14") (pinfunction "14_14") (pintype "passive"))
      (node (ref "IC126") (pin "14") (pinfunction "14_14") (pintype "passive"))
      (node (ref "IC127") (pin "14") (pinfunction "14_14") (pintype "passive"))
      (node (ref "IC128") (pin "14") (pinfunction "14_14") (pintype "passive"))
    )
    (net (code "760") (name "Net-(IC125-Pad15)") (class "Default")
      (node (ref "IC125") (pin "15") (pinfunction "15_15") (pintype "passive"))
      (node (ref "IC126") (pin "15") (pinfunction "15_15") (pintype "passive"))
      (node (ref "IC127") (pin "15") (pinfunction "15_15") (pintype "passive"))
      (node (ref "IC128") (pin "15") (pinfunction "15_15") (pintype "passive"))
    )
    (net (code "761") (name "Net-(IC125-Pad16)") (class "Default")
      (node (ref "IC125") (pin "16") (pinfunction "16_16") (pintype "passive"))
      (node (ref "IC126") (pin "16") (pinfunction "16_16") (pintype "passive"))
      (node (ref "IC127") (pin "16") (pinfunction "16_16") (pintype "passive"))
      (node (ref "IC128") (pin "16") (pinfunction "16_16") (pintype "passive"))
    )
    (net (code "762") (name "Net-(IC125-Pad17)") (class "Default")
      (node (ref "IC125") (pin "17") (pinfunction "17_17") (pintype "passive"))
      (node (ref "IC126") (pin "17") (pinfunction "17_17") (pintype "passive"))
      (node (ref "IC127") (pin "17") (pinfunction "17_17") (pintype "passive"))
      (node (ref "IC128") (pin "17") (pinfunction "17_17") (pintype "passive"))
    )
    (net (code "763") (name "Net-(IC125-Pad18)") (class "Default")
      (node (ref "IC125") (pin "18") (pinfunction "18_18") (pintype "passive"))
      (node (ref "IC126") (pin "18") (pinfunction "18_18") (pintype "passive"))
      (node (ref "IC127") (pin "18") (pinfunction "18_18") (pintype "passive"))
      (node (ref "IC128") (pin "18") (pinfunction "18_18") (pintype "passive"))
    )
    (net (code "764") (name "Net-(IC125-Pad19)") (class "Default")
      (node (ref "IC125") (pin "19") (pinfunction "19_19") (pintype "passive"))
      (node (ref "IC126") (pin "19") (pinfunction "19_19") (pintype "passive"))
      (node (ref "IC127") (pin "19") (pinfunction "19_19") (pintype "passive"))
      (node (ref "IC128") (pin "19") (pinfunction "19_19") (pintype "passive"))
    )
    (net (code "765") (name "Net-(IC125-Pad20)") (class "Default")
      (node (ref "IC125") (pin "20") (pinfunction "20_20") (pintype "passive"))
      (node (ref "IC126") (pin "20") (pinfunction "20_20") (pintype "passive"))
      (node (ref "IC127") (pin "20") (pinfunction "20_20") (pintype "passive"))
      (node (ref "IC128") (pin "20") (pinfunction "20_20") (pintype "passive"))
    )
    (net (code "766") (name "Net-(IC125-Pad21)") (class "Default")
      (node (ref "IC125") (pin "21") (pinfunction "21_21") (pintype "passive"))
      (node (ref "IC126") (pin "21") (pinfunction "21_21") (pintype "passive"))
      (node (ref "IC127") (pin "21") (pinfunction "21_21") (pintype "passive"))
      (node (ref "IC128") (pin "21") (pinfunction "21_21") (pintype "passive"))
    )
    (net (code "767") (name "Net-(IC125-Pad22)") (class "Default")
      (node (ref "IC125") (pin "22") (pinfunction "22_22") (pintype "passive"))
      (node (ref "IC126") (pin "22") (pinfunction "22_22") (pintype "passive"))
      (node (ref "IC127") (pin "22") (pinfunction "22_22") (pintype "passive"))
      (node (ref "IC128") (pin "22") (pinfunction "22_22") (pintype "passive"))
    )
    (net (code "768") (name "Net-(IC125-Pad23)") (class "Default")
      (node (ref "IC125") (pin "23") (pinfunction "23_23") (pintype "passive"))
      (node (ref "IC126") (pin "23") (pinfunction "23_23") (pintype "passive"))
      (node (ref "IC127") (pin "23") (pinfunction "23_23") (pintype "passive"))
      (node (ref "IC128") (pin "23") (pinfunction "23_23") (pintype "passive"))
    )
    (net (code "769") (name "Net-(IC125-Pad24)") (class "Default")
      (node (ref "IC125") (pin "24") (pinfunction "24_24") (pintype "passive"))
      (node (ref "IC126") (pin "24") (pinfunction "24_24") (pintype "passive"))
      (node (ref "IC127") (pin "24") (pinfunction "24_24") (pintype "passive"))
      (node (ref "IC128") (pin "24") (pinfunction "24_24") (pintype "passive"))
    )
    (net (code "770") (name "Net-(IC129-Pad1)") (class "Default")
      (node (ref "IC129") (pin "1") (pinfunction "1_1") (pintype "passive"))
      (node (ref "IC130") (pin "1") (pinfunction "1_1") (pintype "passive"))
      (node (ref "IC131") (pin "1") (pinfunction "1_1") (pintype "passive"))
      (node (ref "IC132") (pin "1") (pinfunction "1_1") (pintype "passive"))
    )
    (net (code "771") (name "Net-(IC129-Pad2)") (class "Default")
      (node (ref "IC129") (pin "2") (pinfunction "2_2") (pintype "passive"))
      (node (ref "IC130") (pin "2") (pinfunction "2_2") (pintype "passive"))
      (node (ref "IC131") (pin "2") (pinfunction "2_2") (pintype "passive"))
      (node (ref "IC132") (pin "2") (pinfunction "2_2") (pintype "passive"))
    )
    (net (code "772") (name "Net-(IC129-Pad3)") (class "Default")
      (node (ref "IC129") (pin "3") (pinfunction "3_3") (pintype "passive"))
      (node (ref "IC130") (pin "3") (pinfunction "3_3") (pintype "passive"))
      (node (ref "IC131") (pin "3") (pinfunction "3_3") (pintype "passive"))
      (node (ref "IC132") (pin "3") (pinfunction "3_3") (pintype "passive"))
    )
    (net (code "773") (name "Net-(IC129-Pad4)") (class "Default")
      (node (ref "IC129") (pin "4") (pinfunction "4_4") (pintype "passive"))
      (node (ref "IC130") (pin "4") (pinfunction "4_4") (pintype "passive"))
      (node (ref "IC131") (pin "4") (pinfunction "4_4") (pintype "passive"))
      (node (ref "IC132") (pin "4") (pinfunction "4_4") (pintype "passive"))
    )
    (net (code "774") (name "Net-(IC129-Pad5)") (class "Default")
      (node (ref "IC129") (pin "5") (pinfunction "5_5") (pintype "passive"))
      (node (ref "IC130") (pin "5") (pinfunction "5_5") (pintype "passive"))
      (node (ref "IC131") (pin "5") (pinfunction "5_5") (pintype "passive"))
      (node (ref "IC132") (pin "5") (pinfunction "5_5") (pintype "passive"))
    )
    (net (code "775") (name "Net-(IC129-Pad6)") (class "Default")
      (node (ref "IC129") (pin "6") (pinfunction "6_6") (pintype "passive"))
      (node (ref "IC130") (pin "6") (pinfunction "6_6") (pintype "passive"))
      (node (ref "IC131") (pin "6") (pinfunction "6_6") (pintype "passive"))
      (node (ref "IC132") (pin "6") (pinfunction "6_6") (pintype "passive"))
    )
    (net (code "776") (name "Net-(IC129-Pad7)") (class "Default")
      (node (ref "IC129") (pin "7") (pinfunction "7_7") (pintype "passive"))
      (node (ref "IC130") (pin "7") (pinfunction "7_7") (pintype "passive"))
      (node (ref "IC131") (pin "7") (pinfunction "7_7") (pintype "passive"))
      (node (ref "IC132") (pin "7") (pinfunction "7_7") (pintype "passive"))
    )
    (net (code "777") (name "Net-(IC129-Pad8)") (class "Default")
      (node (ref "IC129") (pin "8") (pinfunction "8_8") (pintype "passive"))
      (node (ref "IC130") (pin "8") (pinfunction "8_8") (pintype "passive"))
      (node (ref "IC131") (pin "8") (pinfunction "8_8") (pintype "passive"))
      (node (ref "IC132") (pin "8") (pinfunction "8_8") (pintype "passive"))
    )
    (net (code "778") (name "Net-(IC129-Pad9)") (class "Default")
      (node (ref "IC129") (pin "9") (pinfunction "9_9") (pintype "passive"))
      (node (ref "IC130") (pin "9") (pinfunction "9_9") (pintype "passive"))
      (node (ref "IC131") (pin "9") (pinfunction "9_9") (pintype "passive"))
      (node (ref "IC132") (pin "9") (pinfunction "9_9") (pintype "passive"))
    )
    (net (code "779") (name "Net-(IC129-Pad10)") (class "Default")
      (node (ref "IC129") (pin "10") (pinfunction "10_10") (pintype "passive"))
      (node (ref "IC130") (pin "10") (pinfunction "10_10") (pintype "passive"))
      (node (ref "IC131") (pin "10") (pinfunction "10_10") (pintype "passive"))
      (node (ref "IC132") (pin "10") (pinfunction "10_10") (pintype "passive"))
    )
    (net (code "780") (name "Net-(IC129-Pad11)") (class "Default")
      (node (ref "IC129") (pin "11") (pinfunction "11_11") (pintype "passive"))
      (node (ref "IC130") (pin "11") (pinfunction "11_11") (pintype "passive"))
      (node (ref "IC131") (pin "11") (pinfunction "11_11") (pintype "passive"))
      (node (ref "IC132") (pin "11") (pinfunction "11_11") (pintype "passive"))
    )
    (net (code "781") (name "Net-(IC129-Pad12)") (class "Default")
      (node (ref "IC129") (pin "12") (pinfunction "12_12") (pintype "passive"))
      (node (ref "IC130") (pin "12") (pinfunction "12_12") (pintype "passive"))
      (node (ref "IC131") (pin "12") (pinfunction "12_12") (pintype "passive"))
      (node (ref "IC132") (pin "12") (pinfunction "12_12") (pintype "passive"))
    )
    (net (code "782") (name "Net-(IC129-Pad13)") (class "Default")
      (node (ref "IC129") (pin "13") (pinfunction "13_13") (pintype "passive"))
      (node (ref "IC130") (pin "13") (pinfunction "13_13") (pintype "passive"))
      (node (ref "IC131") (pin "13") (pinfunction "13_13") (pintype "passive"))
      (node (ref "IC132") (pin "13") (pinfunction "13_13") (pintype "passive"))
    )
    (net (code "783") (name "Net-(IC129-Pad14)") (class "Default")
      (node (ref "IC129") (pin "14") (pinfunction "14_14") (pintype "passive"))
      (node (ref "IC130") (pin "14") (pinfunction "14_14") (pintype "passive"))
      (node (ref "IC131") (pin "14") (pinfunction "14_14") (pintype "passive"))
      (node (ref "IC132") (pin "14") (pinfunction "14_14") (pintype "passive"))
    )
    (net (code "784") (name "Net-(IC129-Pad15)") (class "Default")
      (node (ref "IC129") (pin "15") (pinfunction "15_15") (pintype "passive"))
      (node (ref "IC130") (pin "15") (pinfunction "15_15") (pintype "passive"))
      (node (ref "IC131") (pin "15") (pinfunction "15_15") (pintype "passive"))
      (node (ref "IC132") (pin "15") (pinfunction "15_15") (pintype "passive"))
    )
    (net (code "785") (name "Net-(IC129-Pad16)") (class "Default")
      (node (ref "IC129") (pin "16") (pinfunction "16_16") (pintype "passive"))
      (node (ref "IC130") (pin "16") (pinfunction "16_16") (pintype "passive"))
      (node (ref "IC131") (pin "16") (pinfunction "16_16") (pintype "passive"))
      (node (ref "IC132") (pin "16") (pinfunction "16_16") (pintype "passive"))
    )
    (net (code "786") (name "Net-(IC129-Pad17)") (class "Default")
      (node (ref "IC129") (pin "17") (pinfunction "17_17") (pintype "passive"))
      (node (ref "IC130") (pin "17") (pinfunction "17_17") (pintype "passive"))
      (node (ref "IC131") (pin "17") (pinfunction "17_17") (pintype "passive"))
      (node (ref "IC132") (pin "17") (pinfunction "17_17") (pintype "passive"))
    )
    (net (code "787") (name "Net-(IC129-Pad18)") (class "Default")
      (node (ref "IC129") (pin "18") (pinfunction "18_18") (pintype "passive"))
      (node (ref "IC130") (pin "18") (pinfunction "18_18") (pintype "passive"))
      (node (ref "IC131") (pin "18") (pinfunction "18_18") (pintype "passive"))
      (node (ref "IC132") (pin "18") (pinfunction "18_18") (pintype "passive"))
    )
    (net (code "788") (name "Net-(IC129-Pad19)") (class "Default")
      (node (ref "IC129") (pin "19") (pinfunction "19_19") (pintype "passive"))
      (node (ref "IC130") (pin "19") (pinfunction "19_19") (pintype "passive"))
      (node (ref "IC131") (pin "19") (pinfunction "19_19") (pintype "passive"))
      (node (ref "IC132") (pin "19") (pinfunction "19_19") (pintype "passive"))
    )
    (net (code "789") (name "Net-(IC129-Pad20)") (class "Default")
      (node (ref "IC129") (pin "20") (pinfunction "20_20") (pintype "passive"))
      (node (ref "IC130") (pin "20") (pinfunction "20_20") (pintype "passive"))
      (node (ref "IC131") (pin "20") (pinfunction "20_20") (pintype "passive"))
      (node (ref "IC132") (pin "20") (pinfunction "20_20") (pintype "passive"))
    )
    (net (code "790") (name "Net-(IC129-Pad21)") (class "Default")
      (node (ref "IC129") (pin "21") (pinfunction "21_21") (pintype "passive"))
      (node (ref "IC130") (pin "21") (pinfunction "21_21") (pintype "passive"))
      (node (ref "IC131") (pin "21") (pinfunction "21_21") (pintype "passive"))
      (node (ref "IC132") (pin "21") (pinfunction "21_21") (pintype "passive"))
    )
    (net (code "791") (name "Net-(IC129-Pad22)") (class "Default")
      (node (ref "IC129") (pin "22") (pinfunction "22_22") (pintype "passive"))
      (node (ref "IC130") (pin "22") (pinfunction "22_22") (pintype "passive"))
      (node (ref "IC131") (pin "22") (pinfunction "22_22") (pintype "passive"))
      (node (ref "IC132") (pin "22") (pinfunction "22_22") (pintype "passive"))
    )
    (net (code "792") (name "Net-(IC129-Pad23)") (class "Default")
      (node (ref "IC129") (pin "23") (pinfunction "23_23") (pintype "passive"))
      (node (ref "IC130") (pin "23") (pinfunction "23_23") (pintype "passive"))
      (node (ref "IC131") (pin "23") (pinfunction "23_23") (pintype "passive"))
      (node (ref "IC132") (pin "23") (pinfunction "23_23") (pintype "passive"))
    )
    (net (code "793") (name "Net-(IC129-Pad24)") (class "Default")
      (node (ref "IC129") (pin "24") (pinfunction "24_24") (pintype "passive"))
      (node (ref "IC130") (pin "24") (pinfunction "24_24") (pintype "passive"))
      (node (ref "IC131") (pin "24") (pinfunction "24_24") (pintype "passive"))
      (node (ref "IC132") (pin "24") (pinfunction "24_24") (pintype "passive"))
    )
    (net (code "794") (name "Net-(IC133-Pad1)") (class "Default")
      (node (ref "IC133") (pin "1") (pinfunction "1_1") (pintype "passive"))
      (node (ref "IC134") (pin "1") (pinfunction "1_1") (pintype "passive"))
      (node (ref "IC135") (pin "1") (pinfunction "1_1") (pintype "passive"))
      (node (ref "IC136") (pin "1") (pinfunction "1_1") (pintype "passive"))
    )
    (net (code "795") (name "Net-(IC133-Pad2)") (class "Default")
      (node (ref "IC133") (pin "2") (pinfunction "2_2") (pintype "passive"))
      (node (ref "IC134") (pin "2") (pinfunction "2_2") (pintype "passive"))
      (node (ref "IC135") (pin "2") (pinfunction "2_2") (pintype "passive"))
      (node (ref "IC136") (pin "2") (pinfunction "2_2") (pintype "passive"))
    )
    (net (code "796") (name "Net-(IC133-Pad3)") (class "Default")
      (node (ref "IC133") (pin "3") (pinfunction "3_3") (pintype "passive"))
      (node (ref "IC134") (pin "3") (pinfunction "3_3") (pintype "passive"))
      (node (ref "IC135") (pin "3") (pinfunction "3_3") (pintype "passive"))
      (node (ref "IC136") (pin "3") (pinfunction "3_3") (pintype "passive"))
    )
    (net (code "797") (name "Net-(IC133-Pad4)") (class "Default")
      (node (ref "IC133") (pin "4") (pinfunction "4_4") (pintype "passive"))
      (node (ref "IC134") (pin "4") (pinfunction "4_4") (pintype "passive"))
      (node (ref "IC135") (pin "4") (pinfunction "4_4") (pintype "passive"))
      (node (ref "IC136") (pin "4") (pinfunction "4_4") (pintype "passive"))
    )
    (net (code "798") (name "Net-(IC133-Pad5)") (class "Default")
      (node (ref "IC133") (pin "5") (pinfunction "5_5") (pintype "passive"))
      (node (ref "IC134") (pin "5") (pinfunction "5_5") (pintype "passive"))
      (node (ref "IC135") (pin "5") (pinfunction "5_5") (pintype "passive"))
      (node (ref "IC136") (pin "5") (pinfunction "5_5") (pintype "passive"))
    )
    (net (code "799") (name "Net-(IC133-Pad6)") (class "Default")
      (node (ref "IC133") (pin "6") (pinfunction "6_6") (pintype "passive"))
      (node (ref "IC134") (pin "6") (pinfunction "6_6") (pintype "passive"))
      (node (ref "IC135") (pin "6") (pinfunction "6_6") (pintype "passive"))
      (node (ref "IC136") (pin "6") (pinfunction "6_6") (pintype "passive"))
    )
    (net (code "800") (name "Net-(IC133-Pad7)") (class "Default")
      (node (ref "IC133") (pin "7") (pinfunction "7_7") (pintype "passive"))
      (node (ref "IC134") (pin "7") (pinfunction "7_7") (pintype "passive"))
      (node (ref "IC135") (pin "7") (pinfunction "7_7") (pintype "passive"))
      (node (ref "IC136") (pin "7") (pinfunction "7_7") (pintype "passive"))
    )
    (net (code "801") (name "Net-(IC133-Pad8)") (class "Default")
      (node (ref "IC133") (pin "8") (pinfunction "8_8") (pintype "passive"))
      (node (ref "IC134") (pin "8") (pinfunction "8_8") (pintype "passive"))
      (node (ref "IC135") (pin "8") (pinfunction "8_8") (pintype "passive"))
      (node (ref "IC136") (pin "8") (pinfunction "8_8") (pintype "passive"))
    )
    (net (code "802") (name "Net-(IC133-Pad9)") (class "Default")
      (node (ref "IC133") (pin "9") (pinfunction "9_9") (pintype "passive"))
      (node (ref "IC134") (pin "9") (pinfunction "9_9") (pintype "passive"))
      (node (ref "IC135") (pin "9") (pinfunction "9_9") (pintype "passive"))
      (node (ref "IC136") (pin "9") (pinfunction "9_9") (pintype "passive"))
    )
    (net (code "803") (name "Net-(IC133-Pad10)") (class "Default")
      (node (ref "IC133") (pin "10") (pinfunction "10_10") (pintype "passive"))
      (node (ref "IC134") (pin "10") (pinfunction "10_10") (pintype "passive"))
      (node (ref "IC135") (pin "10") (pinfunction "10_10") (pintype "passive"))
      (node (ref "IC136") (pin "10") (pinfunction "10_10") (pintype "passive"))
    )
    (net (code "804") (name "Net-(IC133-Pad11)") (class "Default")
      (node (ref "IC133") (pin "11") (pinfunction "11_11") (pintype "passive"))
      (node (ref "IC134") (pin "11") (pinfunction "11_11") (pintype "passive"))
      (node (ref "IC135") (pin "11") (pinfunction "11_11") (pintype "passive"))
      (node (ref "IC136") (pin "11") (pinfunction "11_11") (pintype "passive"))
    )
    (net (code "805") (name "Net-(IC133-Pad12)") (class "Default")
      (node (ref "IC133") (pin "12") (pinfunction "12_12") (pintype "passive"))
      (node (ref "IC134") (pin "12") (pinfunction "12_12") (pintype "passive"))
      (node (ref "IC135") (pin "12") (pinfunction "12_12") (pintype "passive"))
      (node (ref "IC136") (pin "12") (pinfunction "12_12") (pintype "passive"))
    )
    (net (code "806") (name "Net-(IC133-Pad13)") (class "Default")
      (node (ref "IC133") (pin "13") (pinfunction "13_13") (pintype "passive"))
      (node (ref "IC134") (pin "13") (pinfunction "13_13") (pintype "passive"))
      (node (ref "IC135") (pin "13") (pinfunction "13_13") (pintype "passive"))
      (node (ref "IC136") (pin "13") (pinfunction "13_13") (pintype "passive"))
    )
    (net (code "807") (name "Net-(IC133-Pad14)") (class "Default")
      (node (ref "IC133") (pin "14") (pinfunction "14_14") (pintype "passive"))
      (node (ref "IC134") (pin "14") (pinfunction "14_14") (pintype "passive"))
      (node (ref "IC135") (pin "14") (pinfunction "14_14") (pintype "passive"))
      (node (ref "IC136") (pin "14") (pinfunction "14_14") (pintype "passive"))
    )
    (net (code "808") (name "Net-(IC133-Pad15)") (class "Default")
      (node (ref "IC133") (pin "15") (pinfunction "15_15") (pintype "passive"))
      (node (ref "IC134") (pin "15") (pinfunction "15_15") (pintype "passive"))
      (node (ref "IC135") (pin "15") (pinfunction "15_15") (pintype "passive"))
      (node (ref "IC136") (pin "15") (pinfunction "15_15") (pintype "passive"))
    )
    (net (code "809") (name "Net-(IC133-Pad16)") (class "Default")
      (node (ref "IC133") (pin "16") (pinfunction "16_16") (pintype "passive"))
      (node (ref "IC134") (pin "16") (pinfunction "16_16") (pintype "passive"))
      (node (ref "IC135") (pin "16") (pinfunction "16_16") (pintype "passive"))
      (node (ref "IC136") (pin "16") (pinfunction "16_16") (pintype "passive"))
    )
    (net (code "810") (name "Net-(IC133-Pad17)") (class "Default")
      (node (ref "IC133") (pin "17") (pinfunction "17_17") (pintype "passive"))
      (node (ref "IC134") (pin "17") (pinfunction "17_17") (pintype "passive"))
      (node (ref "IC135") (pin "17") (pinfunction "17_17") (pintype "passive"))
      (node (ref "IC136") (pin "17") (pinfunction "17_17") (pintype "passive"))
    )
    (net (code "811") (name "Net-(IC133-Pad18)") (class "Default")
      (node (ref "IC133") (pin "18") (pinfunction "18_18") (pintype "passive"))
      (node (ref "IC134") (pin "18") (pinfunction "18_18") (pintype "passive"))
      (node (ref "IC135") (pin "18") (pinfunction "18_18") (pintype "passive"))
      (node (ref "IC136") (pin "18") (pinfunction "18_18") (pintype "passive"))
    )
    (net (code "812") (name "Net-(IC133-Pad19)") (class "Default")
      (node (ref "IC133") (pin "19") (pinfunction "19_19") (pintype "passive"))
      (node (ref "IC134") (pin "19") (pinfunction "19_19") (pintype "passive"))
      (node (ref "IC135") (pin "19") (pinfunction "19_19") (pintype "passive"))
      (node (ref "IC136") (pin "19") (pinfunction "19_19") (pintype "passive"))
    )
    (net (code "813") (name "Net-(IC133-Pad20)") (class "Default")
      (node (ref "IC133") (pin "20") (pinfunction "20_20") (pintype "passive"))
      (node (ref "IC134") (pin "20") (pinfunction "20_20") (pintype "passive"))
      (node (ref "IC135") (pin "20") (pinfunction "20_20") (pintype "passive"))
      (node (ref "IC136") (pin "20") (pinfunction "20_20") (pintype "passive"))
    )
    (net (code "814") (name "Net-(IC133-Pad21)") (class "Default")
      (node (ref "IC133") (pin "21") (pinfunction "21_21") (pintype "passive"))
      (node (ref "IC134") (pin "21") (pinfunction "21_21") (pintype "passive"))
      (node (ref "IC135") (pin "21") (pinfunction "21_21") (pintype "passive"))
      (node (ref "IC136") (pin "21") (pinfunction "21_21") (pintype "passive"))
    )
    (net (code "815") (name "Net-(IC133-Pad22)") (class "Default")
      (node (ref "IC133") (pin "22") (pinfunction "22_22") (pintype "passive"))
      (node (ref "IC134") (pin "22") (pinfunction "22_22") (pintype "passive"))
      (node (ref "IC135") (pin "22") (pinfunction "22_22") (pintype "passive"))
      (node (ref "IC136") (pin "22") (pinfunction "22_22") (pintype "passive"))
    )
    (net (code "816") (name "Net-(IC133-Pad23)") (class "Default")
      (node (ref "IC133") (pin "23") (pinfunction "23_23") (pintype "passive"))
      (node (ref "IC134") (pin "23") (pinfunction "23_23") (pintype "passive"))
      (node (ref "IC135") (pin "23") (pinfunction "23_23") (pintype "passive"))
      (node (ref "IC136") (pin "23") (pinfunction "23_23") (pintype "passive"))
    )
    (net (code "817") (name "Net-(IC133-Pad24)") (class "Default")
      (node (ref "IC133") (pin "24") (pinfunction "24_24") (pintype "passive"))
      (node (ref "IC134") (pin "24") (pinfunction "24_24") (pintype "passive"))
      (node (ref "IC135") (pin "24") (pinfunction "24_24") (pintype "passive"))
      (node (ref "IC136") (pin "24") (pinfunction "24_24") (pintype "passive"))
    )
    (net (code "818") (name "Net-(IC137-Pad1)") (class "Default")
      (node (ref "IC137") (pin "1") (pinfunction "1_1") (pintype "passive"))
      (node (ref "IC138") (pin "1") (pinfunction "1_1") (pintype "passive"))
      (node (ref "IC139") (pin "1") (pinfunction "1_1") (pintype "passive"))
      (node (ref "IC140") (pin "1") (pinfunction "1_1") (pintype "passive"))
    )
    (net (code "819") (name "Net-(IC137-Pad2)") (class "Default")
      (node (ref "IC137") (pin "2") (pinfunction "2_2") (pintype "passive"))
      (node (ref "IC138") (pin "2") (pinfunction "2_2") (pintype "passive"))
      (node (ref "IC139") (pin "2") (pinfunction "2_2") (pintype "passive"))
      (node (ref "IC140") (pin "2") (pinfunction "2_2") (pintype "passive"))
    )
    (net (code "820") (name "Net-(IC137-Pad3)") (class "Default")
      (node (ref "IC137") (pin "3") (pinfunction "3_3") (pintype "passive"))
      (node (ref "IC138") (pin "3") (pinfunction "3_3") (pintype "passive"))
      (node (ref "IC139") (pin "3") (pinfunction "3_3") (pintype "passive"))
      (node (ref "IC140") (pin "3") (pinfunction "3_3") (pintype "passive"))
    )
    (net (code "821") (name "Net-(IC137-Pad4)") (class "Default")
      (node (ref "IC137") (pin "4") (pinfunction "4_4") (pintype "passive"))
      (node (ref "IC138") (pin "4") (pinfunction "4_4") (pintype "passive"))
      (node (ref "IC139") (pin "4") (pinfunction "4_4") (pintype "passive"))
      (node (ref "IC140") (pin "4") (pinfunction "4_4") (pintype "passive"))
    )
    (net (code "822") (name "Net-(IC137-Pad5)") (class "Default")
      (node (ref "IC137") (pin "5") (pinfunction "5_5") (pintype "passive"))
      (node (ref "IC138") (pin "5") (pinfunction "5_5") (pintype "passive"))
      (node (ref "IC139") (pin "5") (pinfunction "5_5") (pintype "passive"))
      (node (ref "IC140") (pin "5") (pinfunction "5_5") (pintype "passive"))
    )
    (net (code "823") (name "Net-(IC137-Pad6)") (class "Default")
      (node (ref "IC137") (pin "6") (pinfunction "6_6") (pintype "passive"))
      (node (ref "IC138") (pin "6") (pinfunction "6_6") (pintype "passive"))
      (node (ref "IC139") (pin "6") (pinfunction "6_6") (pintype "passive"))
      (node (ref "IC140") (pin "6") (pinfunction "6_6") (pintype "passive"))
    )
    (net (code "824") (name "Net-(IC137-Pad7)") (class "Default")
      (node (ref "IC137") (pin "7") (pinfunction "7_7") (pintype "passive"))
      (node (ref "IC138") (pin "7") (pinfunction "7_7") (pintype "passive"))
      (node (ref "IC139") (pin "7") (pinfunction "7_7") (pintype "passive"))
      (node (ref "IC140") (pin "7") (pinfunction "7_7") (pintype "passive"))
    )
    (net (code "825") (name "Net-(IC137-Pad8)") (class "Default")
      (node (ref "IC137") (pin "8") (pinfunction "8_8") (pintype "passive"))
      (node (ref "IC138") (pin "8") (pinfunction "8_8") (pintype "passive"))
      (node (ref "IC139") (pin "8") (pinfunction "8_8") (pintype "passive"))
      (node (ref "IC140") (pin "8") (pinfunction "8_8") (pintype "passive"))
    )
    (net (code "826") (name "Net-(IC137-Pad9)") (class "Default")
      (node (ref "IC137") (pin "9") (pinfunction "9_9") (pintype "passive"))
      (node (ref "IC138") (pin "9") (pinfunction "9_9") (pintype "passive"))
      (node (ref "IC139") (pin "9") (pinfunction "9_9") (pintype "passive"))
      (node (ref "IC140") (pin "9") (pinfunction "9_9") (pintype "passive"))
    )
    (net (code "827") (name "Net-(IC137-Pad10)") (class "Default")
      (node (ref "IC137") (pin "10") (pinfunction "10_10") (pintype "passive"))
      (node (ref "IC138") (pin "10") (pinfunction "10_10") (pintype "passive"))
      (node (ref "IC139") (pin "10") (pinfunction "10_10") (pintype "passive"))
      (node (ref "IC140") (pin "10") (pinfunction "10_10") (pintype "passive"))
    )
    (net (code "828") (name "Net-(IC137-Pad11)") (class "Default")
      (node (ref "IC137") (pin "11") (pinfunction "11_11") (pintype "passive"))
      (node (ref "IC138") (pin "11") (pinfunction "11_11") (pintype "passive"))
      (node (ref "IC139") (pin "11") (pinfunction "11_11") (pintype "passive"))
      (node (ref "IC140") (pin "11") (pinfunction "11_11") (pintype "passive"))
    )
    (net (code "829") (name "Net-(IC137-Pad12)") (class "Default")
      (node (ref "IC137") (pin "12") (pinfunction "12_12") (pintype "passive"))
      (node (ref "IC138") (pin "12") (pinfunction "12_12") (pintype "passive"))
      (node (ref "IC139") (pin "12") (pinfunction "12_12") (pintype "passive"))
      (node (ref "IC140") (pin "12") (pinfunction "12_12") (pintype "passive"))
    )
    (net (code "830") (name "Net-(IC137-Pad13)") (class "Default")
      (node (ref "IC137") (pin "13") (pinfunction "13_13") (pintype "passive"))
      (node (ref "IC138") (pin "13") (pinfunction "13_13") (pintype "passive"))
      (node (ref "IC139") (pin "13") (pinfunction "13_13") (pintype "passive"))
      (node (ref "IC140") (pin "13") (pinfunction "13_13") (pintype "passive"))
    )
    (net (code "831") (name "Net-(IC137-Pad14)") (class "Default")
      (node (ref "IC137") (pin "14") (pinfunction "14_14") (pintype "passive"))
      (node (ref "IC138") (pin "14") (pinfunction "14_14") (pintype "passive"))
      (node (ref "IC139") (pin "14") (pinfunction "14_14") (pintype "passive"))
      (node (ref "IC140") (pin "14") (pinfunction "14_14") (pintype "passive"))
    )
    (net (code "832") (name "Net-(IC137-Pad15)") (class "Default")
      (node (ref "IC137") (pin "15") (pinfunction "15_15") (pintype "passive"))
      (node (ref "IC138") (pin "15") (pinfunction "15_15") (pintype "passive"))
      (node (ref "IC139") (pin "15") (pinfunction "15_15") (pintype "passive"))
      (node (ref "IC140") (pin "15") (pinfunction "15_15") (pintype "passive"))
    )
    (net (code "833") (name "Net-(IC137-Pad16)") (class "Default")
      (node (ref "IC137") (pin "16") (pinfunction "16_16") (pintype "passive"))
      (node (ref "IC138") (pin "16") (pinfunction "16_16") (pintype "passive"))
      (node (ref "IC139") (pin "16") (pinfunction "16_16") (pintype "passive"))
      (node (ref "IC140") (pin "16") (pinfunction "16_16") (pintype "passive"))
    )
    (net (code "834") (name "Net-(IC137-Pad17)") (class "Default")
      (node (ref "IC137") (pin "17") (pinfunction "17_17") (pintype "passive"))
      (node (ref "IC138") (pin "17") (pinfunction "17_17") (pintype "passive"))
      (node (ref "IC139") (pin "17") (pinfunction "17_17") (pintype "passive"))
      (node (ref "IC140") (pin "17") (pinfunction "17_17") (pintype "passive"))
    )
    (net (code "835") (name "Net-(IC137-Pad18)") (class "Default")
      (node (ref "IC137") (pin "18") (pinfunction "18_18") (pintype "passive"))
      (node (ref "IC138") (pin "18") (pinfunction "18_18") (pintype "passive"))
      (node (ref "IC139") (pin "18") (pinfunction "18_18") (pintype "passive"))
      (node (ref "IC140") (pin "18") (pinfunction "18_18") (pintype "passive"))
    )
    (net (code "836") (name "Net-(IC137-Pad19)") (class "Default")
      (node (ref "IC137") (pin "19") (pinfunction "19_19") (pintype "passive"))
      (node (ref "IC138") (pin "19") (pinfunction "19_19") (pintype "passive"))
      (node (ref "IC139") (pin "19") (pinfunction "19_19") (pintype "passive"))
      (node (ref "IC140") (pin "19") (pinfunction "19_19") (pintype "passive"))
    )
    (net (code "837") (name "Net-(IC137-Pad20)") (class "Default")
      (node (ref "IC137") (pin "20") (pinfunction "20_20") (pintype "passive"))
      (node (ref "IC138") (pin "20") (pinfunction "20_20") (pintype "passive"))
      (node (ref "IC139") (pin "20") (pinfunction "20_20") (pintype "passive"))
      (node (ref "IC140") (pin "20") (pinfunction "20_20") (pintype "passive"))
    )
    (net (code "838") (name "Net-(IC137-Pad21)") (class "Default")
      (node (ref "IC137") (pin "21") (pinfunction "21_21") (pintype "passive"))
      (node (ref "IC138") (pin "21") (pinfunction "21_21") (pintype "passive"))
      (node (ref "IC139") (pin "21") (pinfunction "21_21") (pintype "passive"))
      (node (ref "IC140") (pin "21") (pinfunction "21_21") (pintype "passive"))
    )
    (net (code "839") (name "Net-(IC137-Pad22)") (class "Default")
      (node (ref "IC137") (pin "22") (pinfunction "22_22") (pintype "passive"))
      (node (ref "IC138") (pin "22") (pinfunction "22_22") (pintype "passive"))
      (node (ref "IC139") (pin "22") (pinfunction "22_22") (pintype "passive"))
      (node (ref "IC140") (pin "22") (pinfunction "22_22") (pintype "passive"))
    )
    (net (code "840") (name "Net-(IC137-Pad23)") (class "Default")
      (node (ref "IC137") (pin "23") (pinfunction "23_23") (pintype "passive"))
      (node (ref "IC138") (pin "23") (pinfunction "23_23") (pintype "passive"))
      (node (ref "IC139") (pin "23") (pinfunction "23_23") (pintype "passive"))
      (node (ref "IC140") (pin "23") (pinfunction "23_23") (pintype "passive"))
    )
    (net (code "841") (name "Net-(IC137-Pad24)") (class "Default")
      (node (ref "IC137") (pin "24") (pinfunction "24_24") (pintype "passive"))
      (node (ref "IC138") (pin "24") (pinfunction "24_24") (pintype "passive"))
      (node (ref "IC139") (pin "24") (pinfunction "24_24") (pintype "passive"))
      (node (ref "IC140") (pin "24") (pinfunction "24_24") (pintype "passive"))
    )
    (net (code "842") (name "Net-(IC141-Pad1)") (class "Default")
      (node (ref "IC141") (pin "1") (pinfunction "1_1") (pintype "passive"))
      (node (ref "IC142") (pin "1") (pinfunction "1_1") (pintype "passive"))
      (node (ref "IC143") (pin "1") (pinfunction "1_1") (pintype "passive"))
      (node (ref "IC144") (pin "1") (pinfunction "1_1") (pintype "passive"))
    )
    (net (code "843") (name "Net-(IC141-Pad2)") (class "Default")
      (node (ref "IC141") (pin "2") (pinfunction "2_2") (pintype "passive"))
      (node (ref "IC142") (pin "2") (pinfunction "2_2") (pintype "passive"))
      (node (ref "IC143") (pin "2") (pinfunction "2_2") (pintype "passive"))
      (node (ref "IC144") (pin "2") (pinfunction "2_2") (pintype "passive"))
    )
    (net (code "844") (name "Net-(IC141-Pad3)") (class "Default")
      (node (ref "IC141") (pin "3") (pinfunction "3_3") (pintype "passive"))
      (node (ref "IC142") (pin "3") (pinfunction "3_3") (pintype "passive"))
      (node (ref "IC143") (pin "3") (pinfunction "3_3") (pintype "passive"))
      (node (ref "IC144") (pin "3") (pinfunction "3_3") (pintype "passive"))
    )
    (net (code "845") (name "Net-(IC141-Pad4)") (class "Default")
      (node (ref "IC141") (pin "4") (pinfunction "4_4") (pintype "passive"))
      (node (ref "IC142") (pin "4") (pinfunction "4_4") (pintype "passive"))
      (node (ref "IC143") (pin "4") (pinfunction "4_4") (pintype "passive"))
      (node (ref "IC144") (pin "4") (pinfunction "4_4") (pintype "passive"))
    )
    (net (code "846") (name "Net-(IC141-Pad5)") (class "Default")
      (node (ref "IC141") (pin "5") (pinfunction "5_5") (pintype "passive"))
      (node (ref "IC142") (pin "5") (pinfunction "5_5") (pintype "passive"))
      (node (ref "IC143") (pin "5") (pinfunction "5_5") (pintype "passive"))
      (node (ref "IC144") (pin "5") (pinfunction "5_5") (pintype "passive"))
    )
    (net (code "847") (name "Net-(IC141-Pad6)") (class "Default")
      (node (ref "IC141") (pin "6") (pinfunction "6_6") (pintype "passive"))
      (node (ref "IC142") (pin "6") (pinfunction "6_6") (pintype "passive"))
      (node (ref "IC143") (pin "6") (pinfunction "6_6") (pintype "passive"))
      (node (ref "IC144") (pin "6") (pinfunction "6_6") (pintype "passive"))
    )
    (net (code "848") (name "Net-(IC141-Pad7)") (class "Default")
      (node (ref "IC141") (pin "7") (pinfunction "7_7") (pintype "passive"))
      (node (ref "IC142") (pin "7") (pinfunction "7_7") (pintype "passive"))
      (node (ref "IC143") (pin "7") (pinfunction "7_7") (pintype "passive"))
      (node (ref "IC144") (pin "7") (pinfunction "7_7") (pintype "passive"))
    )
    (net (code "849") (name "Net-(IC141-Pad8)") (class "Default")
      (node (ref "IC141") (pin "8") (pinfunction "8_8") (pintype "passive"))
      (node (ref "IC142") (pin "8") (pinfunction "8_8") (pintype "passive"))
      (node (ref "IC143") (pin "8") (pinfunction "8_8") (pintype "passive"))
      (node (ref "IC144") (pin "8") (pinfunction "8_8") (pintype "passive"))
    )
    (net (code "850") (name "Net-(IC141-Pad9)") (class "Default")
      (node (ref "IC141") (pin "9") (pinfunction "9_9") (pintype "passive"))
      (node (ref "IC142") (pin "9") (pinfunction "9_9") (pintype "passive"))
      (node (ref "IC143") (pin "9") (pinfunction "9_9") (pintype "passive"))
      (node (ref "IC144") (pin "9") (pinfunction "9_9") (pintype "passive"))
    )
    (net (code "851") (name "Net-(IC141-Pad10)") (class "Default")
      (node (ref "IC141") (pin "10") (pinfunction "10_10") (pintype "passive"))
      (node (ref "IC142") (pin "10") (pinfunction "10_10") (pintype "passive"))
      (node (ref "IC143") (pin "10") (pinfunction "10_10") (pintype "passive"))
      (node (ref "IC144") (pin "10") (pinfunction "10_10") (pintype "passive"))
    )
    (net (code "852") (name "Net-(IC141-Pad11)") (class "Default")
      (node (ref "IC141") (pin "11") (pinfunction "11_11") (pintype "passive"))
      (node (ref "IC142") (pin "11") (pinfunction "11_11") (pintype "passive"))
      (node (ref "IC143") (pin "11") (pinfunction "11_11") (pintype "passive"))
      (node (ref "IC144") (pin "11") (pinfunction "11_11") (pintype "passive"))
    )
    (net (code "853") (name "Net-(IC141-Pad12)") (class "Default")
      (node (ref "IC141") (pin "12") (pinfunction "12_12") (pintype "passive"))
      (node (ref "IC142") (pin "12") (pinfunction "12_12") (pintype "passive"))
      (node (ref "IC143") (pin "12") (pinfunction "12_12") (pintype "passive"))
      (node (ref "IC144") (pin "12") (pinfunction "12_12") (pintype "passive"))
    )
    (net (code "854") (name "Net-(IC141-Pad13)") (class "Default")
      (node (ref "IC141") (pin "13") (pinfunction "13_13") (pintype "passive"))
      (node (ref "IC142") (pin "13") (pinfunction "13_13") (pintype "passive"))
      (node (ref "IC143") (pin "13") (pinfunction "13_13") (pintype "passive"))
      (node (ref "IC144") (pin "13") (pinfunction "13_13") (pintype "passive"))
    )
    (net (code "855") (name "Net-(IC141-Pad14)") (class "Default")
      (node (ref "IC141") (pin "14") (pinfunction "14_14") (pintype "passive"))
      (node (ref "IC142") (pin "14") (pinfunction "14_14") (pintype "passive"))
      (node (ref "IC143") (pin "14") (pinfunction "14_14") (pintype "passive"))
      (node (ref "IC144") (pin "14") (pinfunction "14_14") (pintype "passive"))
    )
    (net (code "856") (name "Net-(IC141-Pad15)") (class "Default")
      (node (ref "IC141") (pin "15") (pinfunction "15_15") (pintype "passive"))
      (node (ref "IC142") (pin "15") (pinfunction "15_15") (pintype "passive"))
      (node (ref "IC143") (pin "15") (pinfunction "15_15") (pintype "passive"))
      (node (ref "IC144") (pin "15") (pinfunction "15_15") (pintype "passive"))
    )
    (net (code "857") (name "Net-(IC141-Pad16)") (class "Default")
      (node (ref "IC141") (pin "16") (pinfunction "16_16") (pintype "passive"))
      (node (ref "IC142") (pin "16") (pinfunction "16_16") (pintype "passive"))
      (node (ref "IC143") (pin "16") (pinfunction "16_16") (pintype "passive"))
      (node (ref "IC144") (pin "16") (pinfunction "16_16") (pintype "passive"))
    )
    (net (code "858") (name "Net-(IC141-Pad17)") (class "Default")
      (node (ref "IC141") (pin "17") (pinfunction "17_17") (pintype "passive"))
      (node (ref "IC142") (pin "17") (pinfunction "17_17") (pintype "passive"))
      (node (ref "IC143") (pin "17") (pinfunction "17_17") (pintype "passive"))
      (node (ref "IC144") (pin "17") (pinfunction "17_17") (pintype "passive"))
    )
    (net (code "859") (name "Net-(IC141-Pad18)") (class "Default")
      (node (ref "IC141") (pin "18") (pinfunction "18_18") (pintype "passive"))
      (node (ref "IC142") (pin "18") (pinfunction "18_18") (pintype "passive"))
      (node (ref "IC143") (pin "18") (pinfunction "18_18") (pintype "passive"))
      (node (ref "IC144") (pin "18") (pinfunction "18_18") (pintype "passive"))
    )
    (net (code "860") (name "Net-(IC141-Pad19)") (class "Default")
      (node (ref "IC141") (pin "19") (pinfunction "19_19") (pintype "passive"))
      (node (ref "IC142") (pin "19") (pinfunction "19_19") (pintype "passive"))
      (node (ref "IC143") (pin "19") (pinfunction "19_19") (pintype "passive"))
      (node (ref "IC144") (pin "19") (pinfunction "19_19") (pintype "passive"))
    )
    (net (code "861") (name "Net-(IC141-Pad20)") (class "Default")
      (node (ref "IC141") (pin "20") (pinfunction "20_20") (pintype "passive"))
      (node (ref "IC142") (pin "20") (pinfunction "20_20") (pintype "passive"))
      (node (ref "IC143") (pin "20") (pinfunction "20_20") (pintype "passive"))
      (node (ref "IC144") (pin "20") (pinfunction "20_20") (pintype "passive"))
    )
    (net (code "862") (name "Net-(IC141-Pad21)") (class "Default")
      (node (ref "IC141") (pin "21") (pinfunction "21_21") (pintype "passive"))
      (node (ref "IC142") (pin "21") (pinfunction "21_21") (pintype "passive"))
      (node (ref "IC143") (pin "21") (pinfunction "21_21") (pintype "passive"))
      (node (ref "IC144") (pin "21") (pinfunction "21_21") (pintype "passive"))
    )
    (net (code "863") (name "Net-(IC141-Pad22)") (class "Default")
      (node (ref "IC141") (pin "22") (pinfunction "22_22") (pintype "passive"))
      (node (ref "IC142") (pin "22") (pinfunction "22_22") (pintype "passive"))
      (node (ref "IC143") (pin "22") (pinfunction "22_22") (pintype "passive"))
      (node (ref "IC144") (pin "22") (pinfunction "22_22") (pintype "passive"))
    )
    (net (code "864") (name "Net-(IC141-Pad23)") (class "Default")
      (node (ref "IC141") (pin "23") (pinfunction "23_23") (pintype "passive"))
      (node (ref "IC142") (pin "23") (pinfunction "23_23") (pintype "passive"))
      (node (ref "IC143") (pin "23") (pinfunction "23_23") (pintype "passive"))
      (node (ref "IC144") (pin "23") (pinfunction "23_23") (pintype "passive"))
    )
    (net (code "865") (name "Net-(IC141-Pad24)") (class "Default")
      (node (ref "IC141") (pin "24") (pinfunction "24_24") (pintype "passive"))
      (node (ref "IC142") (pin "24") (pinfunction "24_24") (pintype "passive"))
      (node (ref "IC143") (pin "24") (pinfunction "24_24") (pintype "passive"))
      (node (ref "IC144") (pin "24") (pinfunction "24_24") (pintype "passive"))
    )
    (net (code "866") (name "Net-(IC145-Pad1)") (class "Default")
      (node (ref "IC145") (pin "1") (pinfunction "1_1") (pintype "passive"))
      (node (ref "IC146") (pin "1") (pinfunction "1_1") (pintype "passive"))
      (node (ref "IC147") (pin "1") (pinfunction "1_1") (pintype "passive"))
      (node (ref "IC148") (pin "1") (pinfunction "1_1") (pintype "passive"))
    )
    (net (code "867") (name "Net-(IC145-Pad2)") (class "Default")
      (node (ref "IC145") (pin "2") (pinfunction "2_2") (pintype "passive"))
      (node (ref "IC146") (pin "2") (pinfunction "2_2") (pintype "passive"))
      (node (ref "IC147") (pin "2") (pinfunction "2_2") (pintype "passive"))
      (node (ref "IC148") (pin "2") (pinfunction "2_2") (pintype "passive"))
    )
    (net (code "868") (name "Net-(IC145-Pad3)") (class "Default")
      (node (ref "IC145") (pin "3") (pinfunction "3_3") (pintype "passive"))
      (node (ref "IC146") (pin "3") (pinfunction "3_3") (pintype "passive"))
      (node (ref "IC147") (pin "3") (pinfunction "3_3") (pintype "passive"))
      (node (ref "IC148") (pin "3") (pinfunction "3_3") (pintype "passive"))
    )
    (net (code "869") (name "Net-(IC145-Pad4)") (class "Default")
      (node (ref "IC145") (pin "4") (pinfunction "4_4") (pintype "passive"))
      (node (ref "IC146") (pin "4") (pinfunction "4_4") (pintype "passive"))
      (node (ref "IC147") (pin "4") (pinfunction "4_4") (pintype "passive"))
      (node (ref "IC148") (pin "4") (pinfunction "4_4") (pintype "passive"))
    )
    (net (code "870") (name "Net-(IC145-Pad5)") (class "Default")
      (node (ref "IC145") (pin "5") (pinfunction "5_5") (pintype "passive"))
      (node (ref "IC146") (pin "5") (pinfunction "5_5") (pintype "passive"))
      (node (ref "IC147") (pin "5") (pinfunction "5_5") (pintype "passive"))
      (node (ref "IC148") (pin "5") (pinfunction "5_5") (pintype "passive"))
    )
    (net (code "871") (name "Net-(IC145-Pad6)") (class "Default")
      (node (ref "IC145") (pin "6") (pinfunction "6_6") (pintype "passive"))
      (node (ref "IC146") (pin "6") (pinfunction "6_6") (pintype "passive"))
      (node (ref "IC147") (pin "6") (pinfunction "6_6") (pintype "passive"))
      (node (ref "IC148") (pin "6") (pinfunction "6_6") (pintype "passive"))
    )
    (net (code "872") (name "Net-(IC145-Pad7)") (class "Default")
      (node (ref "IC145") (pin "7") (pinfunction "7_7") (pintype "passive"))
      (node (ref "IC146") (pin "7") (pinfunction "7_7") (pintype "passive"))
      (node (ref "IC147") (pin "7") (pinfunction "7_7") (pintype "passive"))
      (node (ref "IC148") (pin "7") (pinfunction "7_7") (pintype "passive"))
    )
    (net (code "873") (name "Net-(IC145-Pad8)") (class "Default")
      (node (ref "IC145") (pin "8") (pinfunction "8_8") (pintype "passive"))
      (node (ref "IC146") (pin "8") (pinfunction "8_8") (pintype "passive"))
      (node (ref "IC147") (pin "8") (pinfunction "8_8") (pintype "passive"))
      (node (ref "IC148") (pin "8") (pinfunction "8_8") (pintype "passive"))
    )
    (net (code "874") (name "Net-(IC145-Pad9)") (class "Default")
      (node (ref "IC145") (pin "9") (pinfunction "9_9") (pintype "passive"))
      (node (ref "IC146") (pin "9") (pinfunction "9_9") (pintype "passive"))
      (node (ref "IC147") (pin "9") (pinfunction "9_9") (pintype "passive"))
      (node (ref "IC148") (pin "9") (pinfunction "9_9") (pintype "passive"))
    )
    (net (code "875") (name "Net-(IC145-Pad10)") (class "Default")
      (node (ref "IC145") (pin "10") (pinfunction "10_10") (pintype "passive"))
      (node (ref "IC146") (pin "10") (pinfunction "10_10") (pintype "passive"))
      (node (ref "IC147") (pin "10") (pinfunction "10_10") (pintype "passive"))
      (node (ref "IC148") (pin "10") (pinfunction "10_10") (pintype "passive"))
    )
    (net (code "876") (name "Net-(IC145-Pad11)") (class "Default")
      (node (ref "IC145") (pin "11") (pinfunction "11_11") (pintype "passive"))
      (node (ref "IC146") (pin "11") (pinfunction "11_11") (pintype "passive"))
      (node (ref "IC147") (pin "11") (pinfunction "11_11") (pintype "passive"))
      (node (ref "IC148") (pin "11") (pinfunction "11_11") (pintype "passive"))
    )
    (net (code "877") (name "Net-(IC145-Pad12)") (class "Default")
      (node (ref "IC145") (pin "12") (pinfunction "12_12") (pintype "passive"))
      (node (ref "IC146") (pin "12") (pinfunction "12_12") (pintype "passive"))
      (node (ref "IC147") (pin "12") (pinfunction "12_12") (pintype "passive"))
      (node (ref "IC148") (pin "12") (pinfunction "12_12") (pintype "passive"))
    )
    (net (code "878") (name "Net-(IC145-Pad13)") (class "Default")
      (node (ref "IC145") (pin "13") (pinfunction "13_13") (pintype "passive"))
      (node (ref "IC146") (pin "13") (pinfunction "13_13") (pintype "passive"))
      (node (ref "IC147") (pin "13") (pinfunction "13_13") (pintype "passive"))
      (node (ref "IC148") (pin "13") (pinfunction "13_13") (pintype "passive"))
    )
    (net (code "879") (name "Net-(IC145-Pad14)") (class "Default")
      (node (ref "IC145") (pin "14") (pinfunction "14_14") (pintype "passive"))
      (node (ref "IC146") (pin "14") (pinfunction "14_14") (pintype "passive"))
      (node (ref "IC147") (pin "14") (pinfunction "14_14") (pintype "passive"))
      (node (ref "IC148") (pin "14") (pinfunction "14_14") (pintype "passive"))
    )
    (net (code "880") (name "Net-(IC145-Pad15)") (class "Default")
      (node (ref "IC145") (pin "15") (pinfunction "15_15") (pintype "passive"))
      (node (ref "IC146") (pin "15") (pinfunction "15_15") (pintype "passive"))
      (node (ref "IC147") (pin "15") (pinfunction "15_15") (pintype "passive"))
      (node (ref "IC148") (pin "15") (pinfunction "15_15") (pintype "passive"))
    )
    (net (code "881") (name "Net-(IC145-Pad16)") (class "Default")
      (node (ref "IC145") (pin "16") (pinfunction "16_16") (pintype "passive"))
      (node (ref "IC146") (pin "16") (pinfunction "16_16") (pintype "passive"))
      (node (ref "IC147") (pin "16") (pinfunction "16_16") (pintype "passive"))
      (node (ref "IC148") (pin "16") (pinfunction "16_16") (pintype "passive"))
    )
    (net (code "882") (name "Net-(IC145-Pad17)") (class "Default")
      (node (ref "IC145") (pin "17") (pinfunction "17_17") (pintype "passive"))
      (node (ref "IC146") (pin "17") (pinfunction "17_17") (pintype "passive"))
      (node (ref "IC147") (pin "17") (pinfunction "17_17") (pintype "passive"))
      (node (ref "IC148") (pin "17") (pinfunction "17_17") (pintype "passive"))
    )
    (net (code "883") (name "Net-(IC145-Pad18)") (class "Default")
      (node (ref "IC145") (pin "18") (pinfunction "18_18") (pintype "passive"))
      (node (ref "IC146") (pin "18") (pinfunction "18_18") (pintype "passive"))
      (node (ref "IC147") (pin "18") (pinfunction "18_18") (pintype "passive"))
      (node (ref "IC148") (pin "18") (pinfunction "18_18") (pintype "passive"))
    )
    (net (code "884") (name "Net-(IC145-Pad19)") (class "Default")
      (node (ref "IC145") (pin "19") (pinfunction "19_19") (pintype "passive"))
      (node (ref "IC146") (pin "19") (pinfunction "19_19") (pintype "passive"))
      (node (ref "IC147") (pin "19") (pinfunction "19_19") (pintype "passive"))
      (node (ref "IC148") (pin "19") (pinfunction "19_19") (pintype "passive"))
    )
    (net (code "885") (name "Net-(IC145-Pad20)") (class "Default")
      (node (ref "IC145") (pin "20") (pinfunction "20_20") (pintype "passive"))
      (node (ref "IC146") (pin "20") (pinfunction "20_20") (pintype "passive"))
      (node (ref "IC147") (pin "20") (pinfunction "20_20") (pintype "passive"))
      (node (ref "IC148") (pin "20") (pinfunction "20_20") (pintype "passive"))
    )
    (net (code "886") (name "Net-(IC145-Pad21)") (class "Default")
      (node (ref "IC145") (pin "21") (pinfunction "21_21") (pintype "passive"))
      (node (ref "IC146") (pin "21") (pinfunction "21_21") (pintype "passive"))
      (node (ref "IC147") (pin "21") (pinfunction "21_21") (pintype "passive"))
      (node (ref "IC148") (pin "21") (pinfunction "21_21") (pintype "passive"))
    )
    (net (code "887") (name "Net-(IC145-Pad22)") (class "Default")
      (node (ref "IC145") (pin "22") (pinfunction "22_22") (pintype "passive"))
      (node (ref "IC146") (pin "22") (pinfunction "22_22") (pintype "passive"))
      (node (ref "IC147") (pin "22") (pinfunction "22_22") (pintype "passive"))
      (node (ref "IC148") (pin "22") (pinfunction "22_22") (pintype "passive"))
    )
    (net (code "888") (name "Net-(IC145-Pad23)") (class "Default")
      (node (ref "IC145") (pin "23") (pinfunction "23_23") (pintype "passive"))
      (node (ref "IC146") (pin "23") (pinfunction "23_23") (pintype "passive"))
      (node (ref "IC147") (pin "23") (pinfunction "23_23") (pintype "passive"))
      (node (ref "IC148") (pin "23") (pinfunction "23_23") (pintype "passive"))
    )
    (net (code "889") (name "Net-(IC145-Pad24)") (class "Default")
      (node (ref "IC145") (pin "24") (pinfunction "24_24") (pintype "passive"))
      (node (ref "IC146") (pin "24") (pinfunction "24_24") (pintype "passive"))
      (node (ref "IC147") (pin "24") (pinfunction "24_24") (pintype "passive"))
      (node (ref "IC148") (pin "24") (pinfunction "24_24") (pintype "passive"))
    )
    (net (code "890") (name "Net-(IC149-Pad1)") (class "Default")
      (node (ref "IC149") (pin "1") (pinfunction "1_1") (pintype "passive"))
      (node (ref "IC150") (pin "1") (pinfunction "1_1") (pintype "passive"))
      (node (ref "IC151") (pin "1") (pinfunction "1_1") (pintype "passive"))
      (node (ref "IC152") (pin "1") (pinfunction "1_1") (pintype "passive"))
    )
    (net (code "891") (name "Net-(IC149-Pad2)") (class "Default")
      (node (ref "IC149") (pin "2") (pinfunction "2_2") (pintype "passive"))
      (node (ref "IC150") (pin "2") (pinfunction "2_2") (pintype "passive"))
      (node (ref "IC151") (pin "2") (pinfunction "2_2") (pintype "passive"))
      (node (ref "IC152") (pin "2") (pinfunction "2_2") (pintype "passive"))
    )
    (net (code "892") (name "Net-(IC149-Pad3)") (class "Default")
      (node (ref "IC149") (pin "3") (pinfunction "3_3") (pintype "passive"))
      (node (ref "IC150") (pin "3") (pinfunction "3_3") (pintype "passive"))
      (node (ref "IC151") (pin "3") (pinfunction "3_3") (pintype "passive"))
      (node (ref "IC152") (pin "3") (pinfunction "3_3") (pintype "passive"))
    )
    (net (code "893") (name "Net-(IC149-Pad4)") (class "Default")
      (node (ref "IC149") (pin "4") (pinfunction "4_4") (pintype "passive"))
      (node (ref "IC150") (pin "4") (pinfunction "4_4") (pintype "passive"))
      (node (ref "IC151") (pin "4") (pinfunction "4_4") (pintype "passive"))
      (node (ref "IC152") (pin "4") (pinfunction "4_4") (pintype "passive"))
    )
    (net (code "894") (name "Net-(IC149-Pad5)") (class "Default")
      (node (ref "IC149") (pin "5") (pinfunction "5_5") (pintype "passive"))
      (node (ref "IC150") (pin "5") (pinfunction "5_5") (pintype "passive"))
      (node (ref "IC151") (pin "5") (pinfunction "5_5") (pintype "passive"))
      (node (ref "IC152") (pin "5") (pinfunction "5_5") (pintype "passive"))
    )
    (net (code "895") (name "Net-(IC149-Pad6)") (class "Default")
      (node (ref "IC149") (pin "6") (pinfunction "6_6") (pintype "passive"))
      (node (ref "IC150") (pin "6") (pinfunction "6_6") (pintype "passive"))
      (node (ref "IC151") (pin "6") (pinfunction "6_6") (pintype "passive"))
      (node (ref "IC152") (pin "6") (pinfunction "6_6") (pintype "passive"))
    )
    (net (code "896") (name "Net-(IC149-Pad7)") (class "Default")
      (node (ref "IC149") (pin "7") (pinfunction "7_7") (pintype "passive"))
      (node (ref "IC150") (pin "7") (pinfunction "7_7") (pintype "passive"))
      (node (ref "IC151") (pin "7") (pinfunction "7_7") (pintype "passive"))
      (node (ref "IC152") (pin "7") (pinfunction "7_7") (pintype "passive"))
    )
    (net (code "897") (name "Net-(IC149-Pad8)") (class "Default")
      (node (ref "IC149") (pin "8") (pinfunction "8_8") (pintype "passive"))
      (node (ref "IC150") (pin "8") (pinfunction "8_8") (pintype "passive"))
      (node (ref "IC151") (pin "8") (pinfunction "8_8") (pintype "passive"))
      (node (ref "IC152") (pin "8") (pinfunction "8_8") (pintype "passive"))
    )
    (net (code "898") (name "Net-(IC149-Pad9)") (class "Default")
      (node (ref "IC149") (pin "9") (pinfunction "9_9") (pintype "passive"))
      (node (ref "IC150") (pin "9") (pinfunction "9_9") (pintype "passive"))
      (node (ref "IC151") (pin "9") (pinfunction "9_9") (pintype "passive"))
      (node (ref "IC152") (pin "9") (pinfunction "9_9") (pintype "passive"))
    )
    (net (code "899") (name "Net-(IC149-Pad10)") (class "Default")
      (node (ref "IC149") (pin "10") (pinfunction "10_10") (pintype "passive"))
      (node (ref "IC150") (pin "10") (pinfunction "10_10") (pintype "passive"))
      (node (ref "IC151") (pin "10") (pinfunction "10_10") (pintype "passive"))
      (node (ref "IC152") (pin "10") (pinfunction "10_10") (pintype "passive"))
    )
    (net (code "900") (name "Net-(IC149-Pad11)") (class "Default")
      (node (ref "IC149") (pin "11") (pinfunction "11_11") (pintype "passive"))
      (node (ref "IC150") (pin "11") (pinfunction "11_11") (pintype "passive"))
      (node (ref "IC151") (pin "11") (pinfunction "11_11") (pintype "passive"))
      (node (ref "IC152") (pin "11") (pinfunction "11_11") (pintype "passive"))
    )
    (net (code "901") (name "Net-(IC149-Pad12)") (class "Default")
      (node (ref "IC149") (pin "12") (pinfunction "12_12") (pintype "passive"))
      (node (ref "IC150") (pin "12") (pinfunction "12_12") (pintype "passive"))
      (node (ref "IC151") (pin "12") (pinfunction "12_12") (pintype "passive"))
      (node (ref "IC152") (pin "12") (pinfunction "12_12") (pintype "passive"))
    )
    (net (code "902") (name "Net-(IC149-Pad13)") (class "Default")
      (node (ref "IC149") (pin "13") (pinfunction "13_13") (pintype "passive"))
      (node (ref "IC150") (pin "13") (pinfunction "13_13") (pintype "passive"))
      (node (ref "IC151") (pin "13") (pinfunction "13_13") (pintype "passive"))
      (node (ref "IC152") (pin "13") (pinfunction "13_13") (pintype "passive"))
    )
    (net (code "903") (name "Net-(IC149-Pad14)") (class "Default")
      (node (ref "IC149") (pin "14") (pinfunction "14_14") (pintype "passive"))
      (node (ref "IC150") (pin "14") (pinfunction "14_14") (pintype "passive"))
      (node (ref "IC151") (pin "14") (pinfunction "14_14") (pintype "passive"))
      (node (ref "IC152") (pin "14") (pinfunction "14_14") (pintype "passive"))
    )
    (net (code "904") (name "Net-(IC149-Pad15)") (class "Default")
      (node (ref "IC149") (pin "15") (pinfunction "15_15") (pintype "passive"))
      (node (ref "IC150") (pin "15") (pinfunction "15_15") (pintype "passive"))
      (node (ref "IC151") (pin "15") (pinfunction "15_15") (pintype "passive"))
      (node (ref "IC152") (pin "15") (pinfunction "15_15") (pintype "passive"))
    )
    (net (code "905") (name "Net-(IC149-Pad16)") (class "Default")
      (node (ref "IC149") (pin "16") (pinfunction "16_16") (pintype "passive"))
      (node (ref "IC150") (pin "16") (pinfunction "16_16") (pintype "passive"))
      (node (ref "IC151") (pin "16") (pinfunction "16_16") (pintype "passive"))
      (node (ref "IC152") (pin "16") (pinfunction "16_16") (pintype "passive"))
    )
    (net (code "906") (name "Net-(IC149-Pad17)") (class "Default")
      (node (ref "IC149") (pin "17") (pinfunction "17_17") (pintype "passive"))
      (node (ref "IC150") (pin "17") (pinfunction "17_17") (pintype "passive"))
      (node (ref "IC151") (pin "17") (pinfunction "17_17") (pintype "passive"))
      (node (ref "IC152") (pin "17") (pinfunction "17_17") (pintype "passive"))
    )
    (net (code "907") (name "Net-(IC149-Pad18)") (class "Default")
      (node (ref "IC149") (pin "18") (pinfunction "18_18") (pintype "passive"))
      (node (ref "IC150") (pin "18") (pinfunction "18_18") (pintype "passive"))
      (node (ref "IC151") (pin "18") (pinfunction "18_18") (pintype "passive"))
      (node (ref "IC152") (pin "18") (pinfunction "18_18") (pintype "passive"))
    )
    (net (code "908") (name "Net-(IC149-Pad19)") (class "Default")
      (node (ref "IC149") (pin "19") (pinfunction "19_19") (pintype "passive"))
      (node (ref "IC150") (pin "19") (pinfunction "19_19") (pintype "passive"))
      (node (ref "IC151") (pin "19") (pinfunction "19_19") (pintype "passive"))
      (node (ref "IC152") (pin "19") (pinfunction "19_19") (pintype "passive"))
    )
    (net (code "909") (name "Net-(IC149-Pad20)") (class "Default")
      (node (ref "IC149") (pin "20") (pinfunction "20_20") (pintype "passive"))
      (node (ref "IC150") (pin "20") (pinfunction "20_20") (pintype "passive"))
      (node (ref "IC151") (pin "20") (pinfunction "20_20") (pintype "passive"))
      (node (ref "IC152") (pin "20") (pinfunction "20_20") (pintype "passive"))
    )
    (net (code "910") (name "Net-(IC149-Pad21)") (class "Default")
      (node (ref "IC149") (pin "21") (pinfunction "21_21") (pintype "passive"))
      (node (ref "IC150") (pin "21") (pinfunction "21_21") (pintype "passive"))
      (node (ref "IC151") (pin "21") (pinfunction "21_21") (pintype "passive"))
      (node (ref "IC152") (pin "21") (pinfunction "21_21") (pintype "passive"))
    )
    (net (code "911") (name "Net-(IC149-Pad22)") (class "Default")
      (node (ref "IC149") (pin "22") (pinfunction "22_22") (pintype "passive"))
      (node (ref "IC150") (pin "22") (pinfunction "22_22") (pintype "passive"))
      (node (ref "IC151") (pin "22") (pinfunction "22_22") (pintype "passive"))
      (node (ref "IC152") (pin "22") (pinfunction "22_22") (pintype "passive"))
    )
    (net (code "912") (name "Net-(IC149-Pad23)") (class "Default")
      (node (ref "IC149") (pin "23") (pinfunction "23_23") (pintype "passive"))
      (node (ref "IC150") (pin "23") (pinfunction "23_23") (pintype "passive"))
      (node (ref "IC151") (pin "23") (pinfunction "23_23") (pintype "passive"))
      (node (ref "IC152") (pin "23") (pinfunction "23_23") (pintype "passive"))
    )
    (net (code "913") (name "Net-(IC149-Pad24)") (class "Default")
      (node (ref "IC149") (pin "24") (pinfunction "24_24") (pintype "passive"))
      (node (ref "IC150") (pin "24") (pinfunction "24_24") (pintype "passive"))
      (node (ref "IC151") (pin "24") (pinfunction "24_24") (pintype "passive"))
      (node (ref "IC152") (pin "24") (pinfunction "24_24") (pintype "passive"))
    )
    (net (code "914") (name "Net-(IC153-Pad1)") (class "Default")
      (node (ref "IC153") (pin "1") (pinfunction "1_1") (pintype "passive"))
      (node (ref "IC154") (pin "1") (pinfunction "1_1") (pintype "passive"))
      (node (ref "IC155") (pin "1") (pinfunction "1_1") (pintype "passive"))
      (node (ref "IC156") (pin "1") (pinfunction "1_1") (pintype "passive"))
    )
    (net (code "915") (name "Net-(IC153-Pad2)") (class "Default")
      (node (ref "IC153") (pin "2") (pinfunction "2_2") (pintype "passive"))
      (node (ref "IC154") (pin "2") (pinfunction "2_2") (pintype "passive"))
      (node (ref "IC155") (pin "2") (pinfunction "2_2") (pintype "passive"))
      (node (ref "IC156") (pin "2") (pinfunction "2_2") (pintype "passive"))
    )
    (net (code "916") (name "Net-(IC153-Pad3)") (class "Default")
      (node (ref "IC153") (pin "3") (pinfunction "3_3") (pintype "passive"))
      (node (ref "IC154") (pin "3") (pinfunction "3_3") (pintype "passive"))
      (node (ref "IC155") (pin "3") (pinfunction "3_3") (pintype "passive"))
      (node (ref "IC156") (pin "3") (pinfunction "3_3") (pintype "passive"))
    )
    (net (code "917") (name "Net-(IC153-Pad4)") (class "Default")
      (node (ref "IC153") (pin "4") (pinfunction "4_4") (pintype "passive"))
      (node (ref "IC154") (pin "4") (pinfunction "4_4") (pintype "passive"))
      (node (ref "IC155") (pin "4") (pinfunction "4_4") (pintype "passive"))
      (node (ref "IC156") (pin "4") (pinfunction "4_4") (pintype "passive"))
    )
    (net (code "918") (name "Net-(IC153-Pad5)") (class "Default")
      (node (ref "IC153") (pin "5") (pinfunction "5_5") (pintype "passive"))
      (node (ref "IC154") (pin "5") (pinfunction "5_5") (pintype "passive"))
      (node (ref "IC155") (pin "5") (pinfunction "5_5") (pintype "passive"))
      (node (ref "IC156") (pin "5") (pinfunction "5_5") (pintype "passive"))
    )
    (net (code "919") (name "Net-(IC153-Pad6)") (class "Default")
      (node (ref "IC153") (pin "6") (pinfunction "6_6") (pintype "passive"))
      (node (ref "IC154") (pin "6") (pinfunction "6_6") (pintype "passive"))
      (node (ref "IC155") (pin "6") (pinfunction "6_6") (pintype "passive"))
      (node (ref "IC156") (pin "6") (pinfunction "6_6") (pintype "passive"))
    )
    (net (code "920") (name "Net-(IC153-Pad7)") (class "Default")
      (node (ref "IC153") (pin "7") (pinfunction "7_7") (pintype "passive"))
      (node (ref "IC154") (pin "7") (pinfunction "7_7") (pintype "passive"))
      (node (ref "IC155") (pin "7") (pinfunction "7_7") (pintype "passive"))
      (node (ref "IC156") (pin "7") (pinfunction "7_7") (pintype "passive"))
    )
    (net (code "921") (name "Net-(IC153-Pad8)") (class "Default")
      (node (ref "IC153") (pin "8") (pinfunction "8_8") (pintype "passive"))
      (node (ref "IC154") (pin "8") (pinfunction "8_8") (pintype "passive"))
      (node (ref "IC155") (pin "8") (pinfunction "8_8") (pintype "passive"))
      (node (ref "IC156") (pin "8") (pinfunction "8_8") (pintype "passive"))
    )
    (net (code "922") (name "Net-(IC153-Pad9)") (class "Default")
      (node (ref "IC153") (pin "9") (pinfunction "9_9") (pintype "passive"))
      (node (ref "IC154") (pin "9") (pinfunction "9_9") (pintype "passive"))
      (node (ref "IC155") (pin "9") (pinfunction "9_9") (pintype "passive"))
      (node (ref "IC156") (pin "9") (pinfunction "9_9") (pintype "passive"))
    )
    (net (code "923") (name "Net-(IC153-Pad10)") (class "Default")
      (node (ref "IC153") (pin "10") (pinfunction "10_10") (pintype "passive"))
      (node (ref "IC154") (pin "10") (pinfunction "10_10") (pintype "passive"))
      (node (ref "IC155") (pin "10") (pinfunction "10_10") (pintype "passive"))
      (node (ref "IC156") (pin "10") (pinfunction "10_10") (pintype "passive"))
    )
    (net (code "924") (name "Net-(IC153-Pad11)") (class "Default")
      (node (ref "IC153") (pin "11") (pinfunction "11_11") (pintype "passive"))
      (node (ref "IC154") (pin "11") (pinfunction "11_11") (pintype "passive"))
      (node (ref "IC155") (pin "11") (pinfunction "11_11") (pintype "passive"))
      (node (ref "IC156") (pin "11") (pinfunction "11_11") (pintype "passive"))
    )
    (net (code "925") (name "Net-(IC153-Pad12)") (class "Default")
      (node (ref "IC153") (pin "12") (pinfunction "12_12") (pintype "passive"))
      (node (ref "IC154") (pin "12") (pinfunction "12_12") (pintype "passive"))
      (node (ref "IC155") (pin "12") (pinfunction "12_12") (pintype "passive"))
      (node (ref "IC156") (pin "12") (pinfunction "12_12") (pintype "passive"))
    )
    (net (code "926") (name "Net-(IC153-Pad13)") (class "Default")
      (node (ref "IC153") (pin "13") (pinfunction "13_13") (pintype "passive"))
      (node (ref "IC154") (pin "13") (pinfunction "13_13") (pintype "passive"))
      (node (ref "IC155") (pin "13") (pinfunction "13_13") (pintype "passive"))
      (node (ref "IC156") (pin "13") (pinfunction "13_13") (pintype "passive"))
    )
    (net (code "927") (name "Net-(IC153-Pad14)") (class "Default")
      (node (ref "IC153") (pin "14") (pinfunction "14_14") (pintype "passive"))
      (node (ref "IC154") (pin "14") (pinfunction "14_14") (pintype "passive"))
      (node (ref "IC155") (pin "14") (pinfunction "14_14") (pintype "passive"))
      (node (ref "IC156") (pin "14") (pinfunction "14_14") (pintype "passive"))
    )
    (net (code "928") (name "Net-(IC153-Pad15)") (class "Default")
      (node (ref "IC153") (pin "15") (pinfunction "15_15") (pintype "passive"))
      (node (ref "IC154") (pin "15") (pinfunction "15_15") (pintype "passive"))
      (node (ref "IC155") (pin "15") (pinfunction "15_15") (pintype "passive"))
      (node (ref "IC156") (pin "15") (pinfunction "15_15") (pintype "passive"))
    )
    (net (code "929") (name "Net-(IC153-Pad16)") (class "Default")
      (node (ref "IC153") (pin "16") (pinfunction "16_16") (pintype "passive"))
      (node (ref "IC154") (pin "16") (pinfunction "16_16") (pintype "passive"))
      (node (ref "IC155") (pin "16") (pinfunction "16_16") (pintype "passive"))
      (node (ref "IC156") (pin "16") (pinfunction "16_16") (pintype "passive"))
    )
    (net (code "930") (name "Net-(IC153-Pad17)") (class "Default")
      (node (ref "IC153") (pin "17") (pinfunction "17_17") (pintype "passive"))
      (node (ref "IC154") (pin "17") (pinfunction "17_17") (pintype "passive"))
      (node (ref "IC155") (pin "17") (pinfunction "17_17") (pintype "passive"))
      (node (ref "IC156") (pin "17") (pinfunction "17_17") (pintype "passive"))
    )
    (net (code "931") (name "Net-(IC153-Pad18)") (class "Default")
      (node (ref "IC153") (pin "18") (pinfunction "18_18") (pintype "passive"))
      (node (ref "IC154") (pin "18") (pinfunction "18_18") (pintype "passive"))
      (node (ref "IC155") (pin "18") (pinfunction "18_18") (pintype "passive"))
      (node (ref "IC156") (pin "18") (pinfunction "18_18") (pintype "passive"))
    )
    (net (code "932") (name "Net-(IC153-Pad19)") (class "Default")
      (node (ref "IC153") (pin "19") (pinfunction "19_19") (pintype "passive"))
      (node (ref "IC154") (pin "19") (pinfunction "19_19") (pintype "passive"))
      (node (ref "IC155") (pin "19") (pinfunction "19_19") (pintype "passive"))
      (node (ref "IC156") (pin "19") (pinfunction "19_19") (pintype "passive"))
    )
    (net (code "933") (name "Net-(IC153-Pad20)") (class "Default")
      (node (ref "IC153") (pin "20") (pinfunction "20_20") (pintype "passive"))
      (node (ref "IC154") (pin "20") (pinfunction "20_20") (pintype "passive"))
      (node (ref "IC155") (pin "20") (pinfunction "20_20") (pintype "passive"))
      (node (ref "IC156") (pin "20") (pinfunction "20_20") (pintype "passive"))
    )
    (net (code "934") (name "Net-(IC153-Pad21)") (class "Default")
      (node (ref "IC153") (pin "21") (pinfunction "21_21") (pintype "passive"))
      (node (ref "IC154") (pin "21") (pinfunction "21_21") (pintype "passive"))
      (node (ref "IC155") (pin "21") (pinfunction "21_21") (pintype "passive"))
      (node (ref "IC156") (pin "21") (pinfunction "21_21") (pintype "passive"))
    )
    (net (code "935") (name "Net-(IC153-Pad22)") (class "Default")
      (node (ref "IC153") (pin "22") (pinfunction "22_22") (pintype "passive"))
      (node (ref "IC154") (pin "22") (pinfunction "22_22") (pintype "passive"))
      (node (ref "IC155") (pin "22") (pinfunction "22_22") (pintype "passive"))
      (node (ref "IC156") (pin "22") (pinfunction "22_22") (pintype "passive"))
    )
    (net (code "936") (name "Net-(IC153-Pad23)") (class "Default")
      (node (ref "IC153") (pin "23") (pinfunction "23_23") (pintype "passive"))
      (node (ref "IC154") (pin "23") (pinfunction "23_23") (pintype "passive"))
      (node (ref "IC155") (pin "23") (pinfunction "23_23") (pintype "passive"))
      (node (ref "IC156") (pin "23") (pinfunction "23_23") (pintype "passive"))
    )
    (net (code "937") (name "Net-(IC153-Pad24)") (class "Default")
      (node (ref "IC153") (pin "24") (pinfunction "24_24") (pintype "passive"))
      (node (ref "IC154") (pin "24") (pinfunction "24_24") (pintype "passive"))
      (node (ref "IC155") (pin "24") (pinfunction "24_24") (pintype "passive"))
      (node (ref "IC156") (pin "24") (pinfunction "24_24") (pintype "passive"))
    )
    (net (code "938") (name "Net-(IC157-Pad1)") (class "Default")
      (node (ref "IC157") (pin "1") (pinfunction "1_1") (pintype "passive"))
      (node (ref "IC158") (pin "1") (pinfunction "1_1") (pintype "passive"))
      (node (ref "IC159") (pin "1") (pinfunction "1_1") (pintype "passive"))
      (node (ref "IC160") (pin "1") (pinfunction "1_1") (pintype "passive"))
    )
    (net (code "939") (name "Net-(IC157-Pad2)") (class "Default")
      (node (ref "IC157") (pin "2") (pinfunction "2_2") (pintype "passive"))
      (node (ref "IC158") (pin "2") (pinfunction "2_2") (pintype "passive"))
      (node (ref "IC159") (pin "2") (pinfunction "2_2") (pintype "passive"))
      (node (ref "IC160") (pin "2") (pinfunction "2_2") (pintype "passive"))
    )
    (net (code "940") (name "Net-(IC157-Pad3)") (class "Default")
      (node (ref "IC157") (pin "3") (pinfunction "3_3") (pintype "passive"))
      (node (ref "IC158") (pin "3") (pinfunction "3_3") (pintype "passive"))
      (node (ref "IC159") (pin "3") (pinfunction "3_3") (pintype "passive"))
      (node (ref "IC160") (pin "3") (pinfunction "3_3") (pintype "passive"))
    )
    (net (code "941") (name "Net-(IC157-Pad4)") (class "Default")
      (node (ref "IC157") (pin "4") (pinfunction "4_4") (pintype "passive"))
      (node (ref "IC158") (pin "4") (pinfunction "4_4") (pintype "passive"))
      (node (ref "IC159") (pin "4") (pinfunction "4_4") (pintype "passive"))
      (node (ref "IC160") (pin "4") (pinfunction "4_4") (pintype "passive"))
    )
    (net (code "942") (name "Net-(IC157-Pad5)") (class "Default")
      (node (ref "IC157") (pin "5") (pinfunction "5_5") (pintype "passive"))
      (node (ref "IC158") (pin "5") (pinfunction "5_5") (pintype "passive"))
      (node (ref "IC159") (pin "5") (pinfunction "5_5") (pintype "passive"))
      (node (ref "IC160") (pin "5") (pinfunction "5_5") (pintype "passive"))
    )
    (net (code "943") (name "Net-(IC157-Pad6)") (class "Default")
      (node (ref "IC157") (pin "6") (pinfunction "6_6") (pintype "passive"))
      (node (ref "IC158") (pin "6") (pinfunction "6_6") (pintype "passive"))
      (node (ref "IC159") (pin "6") (pinfunction "6_6") (pintype "passive"))
      (node (ref "IC160") (pin "6") (pinfunction "6_6") (pintype "passive"))
    )
    (net (code "944") (name "Net-(IC157-Pad7)") (class "Default")
      (node (ref "IC157") (pin "7") (pinfunction "7_7") (pintype "passive"))
      (node (ref "IC158") (pin "7") (pinfunction "7_7") (pintype "passive"))
      (node (ref "IC159") (pin "7") (pinfunction "7_7") (pintype "passive"))
      (node (ref "IC160") (pin "7") (pinfunction "7_7") (pintype "passive"))
    )
    (net (code "945") (name "Net-(IC157-Pad8)") (class "Default")
      (node (ref "IC157") (pin "8") (pinfunction "8_8") (pintype "passive"))
      (node (ref "IC158") (pin "8") (pinfunction "8_8") (pintype "passive"))
      (node (ref "IC159") (pin "8") (pinfunction "8_8") (pintype "passive"))
      (node (ref "IC160") (pin "8") (pinfunction "8_8") (pintype "passive"))
    )
    (net (code "946") (name "Net-(IC157-Pad9)") (class "Default")
      (node (ref "IC157") (pin "9") (pinfunction "9_9") (pintype "passive"))
      (node (ref "IC158") (pin "9") (pinfunction "9_9") (pintype "passive"))
      (node (ref "IC159") (pin "9") (pinfunction "9_9") (pintype "passive"))
      (node (ref "IC160") (pin "9") (pinfunction "9_9") (pintype "passive"))
    )
    (net (code "947") (name "Net-(IC157-Pad10)") (class "Default")
      (node (ref "IC157") (pin "10") (pinfunction "10_10") (pintype "passive"))
      (node (ref "IC158") (pin "10") (pinfunction "10_10") (pintype "passive"))
      (node (ref "IC159") (pin "10") (pinfunction "10_10") (pintype "passive"))
      (node (ref "IC160") (pin "10") (pinfunction "10_10") (pintype "passive"))
    )
    (net (code "948") (name "Net-(IC157-Pad11)") (class "Default")
      (node (ref "IC157") (pin "11") (pinfunction "11_11") (pintype "passive"))
      (node (ref "IC158") (pin "11") (pinfunction "11_11") (pintype "passive"))
      (node (ref "IC159") (pin "11") (pinfunction "11_11") (pintype "passive"))
      (node (ref "IC160") (pin "11") (pinfunction "11_11") (pintype "passive"))
    )
    (net (code "949") (name "Net-(IC157-Pad12)") (class "Default")
      (node (ref "IC157") (pin "12") (pinfunction "12_12") (pintype "passive"))
      (node (ref "IC158") (pin "12") (pinfunction "12_12") (pintype "passive"))
      (node (ref "IC159") (pin "12") (pinfunction "12_12") (pintype "passive"))
      (node (ref "IC160") (pin "12") (pinfunction "12_12") (pintype "passive"))
    )
    (net (code "950") (name "Net-(IC157-Pad13)") (class "Default")
      (node (ref "IC157") (pin "13") (pinfunction "13_13") (pintype "passive"))
      (node (ref "IC158") (pin "13") (pinfunction "13_13") (pintype "passive"))
      (node (ref "IC159") (pin "13") (pinfunction "13_13") (pintype "passive"))
      (node (ref "IC160") (pin "13") (pinfunction "13_13") (pintype "passive"))
    )
    (net (code "951") (name "Net-(IC157-Pad14)") (class "Default")
      (node (ref "IC157") (pin "14") (pinfunction "14_14") (pintype "passive"))
      (node (ref "IC158") (pin "14") (pinfunction "14_14") (pintype "passive"))
      (node (ref "IC159") (pin "14") (pinfunction "14_14") (pintype "passive"))
      (node (ref "IC160") (pin "14") (pinfunction "14_14") (pintype "passive"))
    )
    (net (code "952") (name "Net-(IC157-Pad15)") (class "Default")
      (node (ref "IC157") (pin "15") (pinfunction "15_15") (pintype "passive"))
      (node (ref "IC158") (pin "15") (pinfunction "15_15") (pintype "passive"))
      (node (ref "IC159") (pin "15") (pinfunction "15_15") (pintype "passive"))
      (node (ref "IC160") (pin "15") (pinfunction "15_15") (pintype "passive"))
    )
    (net (code "953") (name "Net-(IC157-Pad16)") (class "Default")
      (node (ref "IC157") (pin "16") (pinfunction "16_16") (pintype "passive"))
      (node (ref "IC158") (pin "16") (pinfunction "16_16") (pintype "passive"))
      (node (ref "IC159") (pin "16") (pinfunction "16_16") (pintype "passive"))
      (node (ref "IC160") (pin "16") (pinfunction "16_16") (pintype "passive"))
    )
    (net (code "954") (name "Net-(IC157-Pad17)") (class "Default")
      (node (ref "IC157") (pin "17") (pinfunction "17_17") (pintype "passive"))
      (node (ref "IC158") (pin "17") (pinfunction "17_17") (pintype "passive"))
      (node (ref "IC159") (pin "17") (pinfunction "17_17") (pintype "passive"))
      (node (ref "IC160") (pin "17") (pinfunction "17_17") (pintype "passive"))
    )
    (net (code "955") (name "Net-(IC157-Pad18)") (class "Default")
      (node (ref "IC157") (pin "18") (pinfunction "18_18") (pintype "passive"))
      (node (ref "IC158") (pin "18") (pinfunction "18_18") (pintype "passive"))
      (node (ref "IC159") (pin "18") (pinfunction "18_18") (pintype "passive"))
      (node (ref "IC160") (pin "18") (pinfunction "18_18") (pintype "passive"))
    )
    (net (code "956") (name "Net-(IC157-Pad19)") (class "Default")
      (node (ref "IC157") (pin "19") (pinfunction "19_19") (pintype "passive"))
      (node (ref "IC158") (pin "19") (pinfunction "19_19") (pintype "passive"))
      (node (ref "IC159") (pin "19") (pinfunction "19_19") (pintype "passive"))
      (node (ref "IC160") (pin "19") (pinfunction "19_19") (pintype "passive"))
    )
    (net (code "957") (name "Net-(IC157-Pad20)") (class "Default")
      (node (ref "IC157") (pin "20") (pinfunction "20_20") (pintype "passive"))
      (node (ref "IC158") (pin "20") (pinfunction "20_20") (pintype "passive"))
      (node (ref "IC159") (pin "20") (pinfunction "20_20") (pintype "passive"))
      (node (ref "IC160") (pin "20") (pinfunction "20_20") (pintype "passive"))
    )
    (net (code "958") (name "Net-(IC157-Pad21)") (class "Default")
      (node (ref "IC157") (pin "21") (pinfunction "21_21") (pintype "passive"))
      (node (ref "IC158") (pin "21") (pinfunction "21_21") (pintype "passive"))
      (node (ref "IC159") (pin "21") (pinfunction "21_21") (pintype "passive"))
      (node (ref "IC160") (pin "21") (pinfunction "21_21") (pintype "passive"))
    )
    (net (code "959") (name "Net-(IC157-Pad22)") (class "Default")
      (node (ref "IC157") (pin "22") (pinfunction "22_22") (pintype "passive"))
      (node (ref "IC158") (pin "22") (pinfunction "22_22") (pintype "passive"))
      (node (ref "IC159") (pin "22") (pinfunction "22_22") (pintype "passive"))
      (node (ref "IC160") (pin "22") (pinfunction "22_22") (pintype "passive"))
    )
    (net (code "960") (name "Net-(IC157-Pad23)") (class "Default")
      (node (ref "IC157") (pin "23") (pinfunction "23_23") (pintype "passive"))
      (node (ref "IC158") (pin "23") (pinfunction "23_23") (pintype "passive"))
      (node (ref "IC159") (pin "23") (pinfunction "23_23") (pintype "passive"))
      (node (ref "IC160") (pin "23") (pinfunction "23_23") (pintype "passive"))
    )
    (net (code "961") (name "Net-(IC157-Pad24)") (class "Default")
      (node (ref "IC157") (pin "24") (pinfunction "24_24") (pintype "passive"))
      (node (ref "IC158") (pin "24") (pinfunction "24_24") (pintype "passive"))
      (node (ref "IC159") (pin "24") (pinfunction "24_24") (pintype "passive"))
      (node (ref "IC160") (pin "24") (pinfunction "24_24") (pintype "passive"))
    )
    (net (code "962") (name "Net-(IC161-Pad1)") (class "Default")
      (node (ref "IC161") (pin "1") (pinfunction "1_1") (pintype "passive"))
      (node (ref "IC162") (pin "1") (pinfunction "1_1") (pintype "passive"))
      (node (ref "IC163") (pin "1") (pinfunction "1_1") (pintype "passive"))
      (node (ref "IC164") (pin "1") (pinfunction "1_1") (pintype "passive"))
    )
    (net (code "963") (name "Net-(IC161-Pad2)") (class "Default")
      (node (ref "IC161") (pin "2") (pinfunction "2_2") (pintype "passive"))
      (node (ref "IC162") (pin "2") (pinfunction "2_2") (pintype "passive"))
      (node (ref "IC163") (pin "2") (pinfunction "2_2") (pintype "passive"))
      (node (ref "IC164") (pin "2") (pinfunction "2_2") (pintype "passive"))
    )
    (net (code "964") (name "Net-(IC161-Pad3)") (class "Default")
      (node (ref "IC161") (pin "3") (pinfunction "3_3") (pintype "passive"))
      (node (ref "IC162") (pin "3") (pinfunction "3_3") (pintype "passive"))
      (node (ref "IC163") (pin "3") (pinfunction "3_3") (pintype "passive"))
      (node (ref "IC164") (pin "3") (pinfunction "3_3") (pintype "passive"))
    )
    (net (code "965") (name "Net-(IC161-Pad4)") (class "Default")
      (node (ref "IC161") (pin "4") (pinfunction "4_4") (pintype "passive"))
      (node (ref "IC162") (pin "4") (pinfunction "4_4") (pintype "passive"))
      (node (ref "IC163") (pin "4") (pinfunction "4_4") (pintype "passive"))
      (node (ref "IC164") (pin "4") (pinfunction "4_4") (pintype "passive"))
    )
    (net (code "966") (name "Net-(IC161-Pad5)") (class "Default")
      (node (ref "IC161") (pin "5") (pinfunction "5_5") (pintype "passive"))
      (node (ref "IC162") (pin "5") (pinfunction "5_5") (pintype "passive"))
      (node (ref "IC163") (pin "5") (pinfunction "5_5") (pintype "passive"))
      (node (ref "IC164") (pin "5") (pinfunction "5_5") (pintype "passive"))
    )
    (net (code "967") (name "Net-(IC161-Pad6)") (class "Default")
      (node (ref "IC161") (pin "6") (pinfunction "6_6") (pintype "passive"))
      (node (ref "IC162") (pin "6") (pinfunction "6_6") (pintype "passive"))
      (node (ref "IC163") (pin "6") (pinfunction "6_6") (pintype "passive"))
      (node (ref "IC164") (pin "6") (pinfunction "6_6") (pintype "passive"))
    )
    (net (code "968") (name "Net-(IC161-Pad7)") (class "Default")
      (node (ref "IC161") (pin "7") (pinfunction "7_7") (pintype "passive"))
      (node (ref "IC162") (pin "7") (pinfunction "7_7") (pintype "passive"))
      (node (ref "IC163") (pin "7") (pinfunction "7_7") (pintype "passive"))
      (node (ref "IC164") (pin "7") (pinfunction "7_7") (pintype "passive"))
    )
    (net (code "969") (name "Net-(IC161-Pad8)") (class "Default")
      (node (ref "IC161") (pin "8") (pinfunction "8_8") (pintype "passive"))
      (node (ref "IC162") (pin "8") (pinfunction "8_8") (pintype "passive"))
      (node (ref "IC163") (pin "8") (pinfunction "8_8") (pintype "passive"))
      (node (ref "IC164") (pin "8") (pinfunction "8_8") (pintype "passive"))
    )
    (net (code "970") (name "Net-(IC161-Pad9)") (class "Default")
      (node (ref "IC161") (pin "9") (pinfunction "9_9") (pintype "passive"))
      (node (ref "IC162") (pin "9") (pinfunction "9_9") (pintype "passive"))
      (node (ref "IC163") (pin "9") (pinfunction "9_9") (pintype "passive"))
      (node (ref "IC164") (pin "9") (pinfunction "9_9") (pintype "passive"))
    )
    (net (code "971") (name "Net-(IC161-Pad10)") (class "Default")
      (node (ref "IC161") (pin "10") (pinfunction "10_10") (pintype "passive"))
      (node (ref "IC162") (pin "10") (pinfunction "10_10") (pintype "passive"))
      (node (ref "IC163") (pin "10") (pinfunction "10_10") (pintype "passive"))
      (node (ref "IC164") (pin "10") (pinfunction "10_10") (pintype "passive"))
    )
    (net (code "972") (name "Net-(IC161-Pad11)") (class "Default")
      (node (ref "IC161") (pin "11") (pinfunction "11_11") (pintype "passive"))
      (node (ref "IC162") (pin "11") (pinfunction "11_11") (pintype "passive"))
      (node (ref "IC163") (pin "11") (pinfunction "11_11") (pintype "passive"))
      (node (ref "IC164") (pin "11") (pinfunction "11_11") (pintype "passive"))
    )
    (net (code "973") (name "Net-(IC161-Pad12)") (class "Default")
      (node (ref "IC161") (pin "12") (pinfunction "12_12") (pintype "passive"))
      (node (ref "IC162") (pin "12") (pinfunction "12_12") (pintype "passive"))
      (node (ref "IC163") (pin "12") (pinfunction "12_12") (pintype "passive"))
      (node (ref "IC164") (pin "12") (pinfunction "12_12") (pintype "passive"))
    )
    (net (code "974") (name "Net-(IC161-Pad13)") (class "Default")
      (node (ref "IC161") (pin "13") (pinfunction "13_13") (pintype "passive"))
      (node (ref "IC162") (pin "13") (pinfunction "13_13") (pintype "passive"))
      (node (ref "IC163") (pin "13") (pinfunction "13_13") (pintype "passive"))
      (node (ref "IC164") (pin "13") (pinfunction "13_13") (pintype "passive"))
    )
    (net (code "975") (name "Net-(IC161-Pad14)") (class "Default")
      (node (ref "IC161") (pin "14") (pinfunction "14_14") (pintype "passive"))
      (node (ref "IC162") (pin "14") (pinfunction "14_14") (pintype "passive"))
      (node (ref "IC163") (pin "14") (pinfunction "14_14") (pintype "passive"))
      (node (ref "IC164") (pin "14") (pinfunction "14_14") (pintype "passive"))
    )
    (net (code "976") (name "Net-(IC161-Pad15)") (class "Default")
      (node (ref "IC161") (pin "15") (pinfunction "15_15") (pintype "passive"))
      (node (ref "IC162") (pin "15") (pinfunction "15_15") (pintype "passive"))
      (node (ref "IC163") (pin "15") (pinfunction "15_15") (pintype "passive"))
      (node (ref "IC164") (pin "15") (pinfunction "15_15") (pintype "passive"))
    )
    (net (code "977") (name "Net-(IC161-Pad16)") (class "Default")
      (node (ref "IC161") (pin "16") (pinfunction "16_16") (pintype "passive"))
      (node (ref "IC162") (pin "16") (pinfunction "16_16") (pintype "passive"))
      (node (ref "IC163") (pin "16") (pinfunction "16_16") (pintype "passive"))
      (node (ref "IC164") (pin "16") (pinfunction "16_16") (pintype "passive"))
    )
    (net (code "978") (name "Net-(IC161-Pad17)") (class "Default")
      (node (ref "IC161") (pin "17") (pinfunction "17_17") (pintype "passive"))
      (node (ref "IC162") (pin "17") (pinfunction "17_17") (pintype "passive"))
      (node (ref "IC163") (pin "17") (pinfunction "17_17") (pintype "passive"))
      (node (ref "IC164") (pin "17") (pinfunction "17_17") (pintype "passive"))
    )
    (net (code "979") (name "Net-(IC161-Pad18)") (class "Default")
      (node (ref "IC161") (pin "18") (pinfunction "18_18") (pintype "passive"))
      (node (ref "IC162") (pin "18") (pinfunction "18_18") (pintype "passive"))
      (node (ref "IC163") (pin "18") (pinfunction "18_18") (pintype "passive"))
      (node (ref "IC164") (pin "18") (pinfunction "18_18") (pintype "passive"))
    )
    (net (code "980") (name "Net-(IC161-Pad19)") (class "Default")
      (node (ref "IC161") (pin "19") (pinfunction "19_19") (pintype "passive"))
      (node (ref "IC162") (pin "19") (pinfunction "19_19") (pintype "passive"))
      (node (ref "IC163") (pin "19") (pinfunction "19_19") (pintype "passive"))
      (node (ref "IC164") (pin "19") (pinfunction "19_19") (pintype "passive"))
    )
    (net (code "981") (name "Net-(IC161-Pad20)") (class "Default")
      (node (ref "IC161") (pin "20") (pinfunction "20_20") (pintype "passive"))
      (node (ref "IC162") (pin "20") (pinfunction "20_20") (pintype "passive"))
      (node (ref "IC163") (pin "20") (pinfunction "20_20") (pintype "passive"))
      (node (ref "IC164") (pin "20") (pinfunction "20_20") (pintype "passive"))
    )
    (net (code "982") (name "Net-(IC161-Pad21)") (class "Default")
      (node (ref "IC161") (pin "21") (pinfunction "21_21") (pintype "passive"))
      (node (ref "IC162") (pin "21") (pinfunction "21_21") (pintype "passive"))
      (node (ref "IC163") (pin "21") (pinfunction "21_21") (pintype "passive"))
      (node (ref "IC164") (pin "21") (pinfunction "21_21") (pintype "passive"))
    )
    (net (code "983") (name "Net-(IC161-Pad22)") (class "Default")
      (node (ref "IC161") (pin "22") (pinfunction "22_22") (pintype "passive"))
      (node (ref "IC162") (pin "22") (pinfunction "22_22") (pintype "passive"))
      (node (ref "IC163") (pin "22") (pinfunction "22_22") (pintype "passive"))
      (node (ref "IC164") (pin "22") (pinfunction "22_22") (pintype "passive"))
    )
    (net (code "984") (name "Net-(IC161-Pad23)") (class "Default")
      (node (ref "IC161") (pin "23") (pinfunction "23_23") (pintype "passive"))
      (node (ref "IC162") (pin "23") (pinfunction "23_23") (pintype "passive"))
      (node (ref "IC163") (pin "23") (pinfunction "23_23") (pintype "passive"))
      (node (ref "IC164") (pin "23") (pinfunction "23_23") (pintype "passive"))
    )
    (net (code "985") (name "Net-(IC161-Pad24)") (class "Default")
      (node (ref "IC161") (pin "24") (pinfunction "24_24") (pintype "passive"))
      (node (ref "IC162") (pin "24") (pinfunction "24_24") (pintype "passive"))
      (node (ref "IC163") (pin "24") (pinfunction "24_24") (pintype "passive"))
      (node (ref "IC164") (pin "24") (pinfunction "24_24") (pintype "passive"))
    )
    (net (code "986") (name "Net-(IC165-Pad1)") (class "Default")
      (node (ref "IC165") (pin "1") (pinfunction "1_1") (pintype "passive"))
      (node (ref "IC166") (pin "1") (pinfunction "1_1") (pintype "passive"))
      (node (ref "IC167") (pin "1") (pinfunction "1_1") (pintype "passive"))
      (node (ref "IC168") (pin "1") (pinfunction "1_1") (pintype "passive"))
    )
    (net (code "987") (name "Net-(IC165-Pad2)") (class "Default")
      (node (ref "IC165") (pin "2") (pinfunction "2_2") (pintype "passive"))
      (node (ref "IC166") (pin "2") (pinfunction "2_2") (pintype "passive"))
      (node (ref "IC167") (pin "2") (pinfunction "2_2") (pintype "passive"))
      (node (ref "IC168") (pin "2") (pinfunction "2_2") (pintype "passive"))
    )
    (net (code "988") (name "Net-(IC165-Pad3)") (class "Default")
      (node (ref "IC165") (pin "3") (pinfunction "3_3") (pintype "passive"))
      (node (ref "IC166") (pin "3") (pinfunction "3_3") (pintype "passive"))
      (node (ref "IC167") (pin "3") (pinfunction "3_3") (pintype "passive"))
      (node (ref "IC168") (pin "3") (pinfunction "3_3") (pintype "passive"))
    )
    (net (code "989") (name "Net-(IC165-Pad4)") (class "Default")
      (node (ref "IC165") (pin "4") (pinfunction "4_4") (pintype "passive"))
      (node (ref "IC166") (pin "4") (pinfunction "4_4") (pintype "passive"))
      (node (ref "IC167") (pin "4") (pinfunction "4_4") (pintype "passive"))
      (node (ref "IC168") (pin "4") (pinfunction "4_4") (pintype "passive"))
    )
    (net (code "990") (name "Net-(IC165-Pad5)") (class "Default")
      (node (ref "IC165") (pin "5") (pinfunction "5_5") (pintype "passive"))
      (node (ref "IC166") (pin "5") (pinfunction "5_5") (pintype "passive"))
      (node (ref "IC167") (pin "5") (pinfunction "5_5") (pintype "passive"))
      (node (ref "IC168") (pin "5") (pinfunction "5_5") (pintype "passive"))
    )
    (net (code "991") (name "Net-(IC165-Pad6)") (class "Default")
      (node (ref "IC165") (pin "6") (pinfunction "6_6") (pintype "passive"))
      (node (ref "IC166") (pin "6") (pinfunction "6_6") (pintype "passive"))
      (node (ref "IC167") (pin "6") (pinfunction "6_6") (pintype "passive"))
      (node (ref "IC168") (pin "6") (pinfunction "6_6") (pintype "passive"))
    )
    (net (code "992") (name "Net-(IC165-Pad7)") (class "Default")
      (node (ref "IC165") (pin "7") (pinfunction "7_7") (pintype "passive"))
      (node (ref "IC166") (pin "7") (pinfunction "7_7") (pintype "passive"))
      (node (ref "IC167") (pin "7") (pinfunction "7_7") (pintype "passive"))
      (node (ref "IC168") (pin "7") (pinfunction "7_7") (pintype "passive"))
    )
    (net (code "993") (name "Net-(IC165-Pad8)") (class "Default")
      (node (ref "IC165") (pin "8") (pinfunction "8_8") (pintype "passive"))
      (node (ref "IC166") (pin "8") (pinfunction "8_8") (pintype "passive"))
      (node (ref "IC167") (pin "8") (pinfunction "8_8") (pintype "passive"))
      (node (ref "IC168") (pin "8") (pinfunction "8_8") (pintype "passive"))
    )
    (net (code "994") (name "Net-(IC165-Pad9)") (class "Default")
      (node (ref "IC165") (pin "9") (pinfunction "9_9") (pintype "passive"))
      (node (ref "IC166") (pin "9") (pinfunction "9_9") (pintype "passive"))
      (node (ref "IC167") (pin "9") (pinfunction "9_9") (pintype "passive"))
      (node (ref "IC168") (pin "9") (pinfunction "9_9") (pintype "passive"))
    )
    (net (code "995") (name "Net-(IC165-Pad10)") (class "Default")
      (node (ref "IC165") (pin "10") (pinfunction "10_10") (pintype "passive"))
      (node (ref "IC166") (pin "10") (pinfunction "10_10") (pintype "passive"))
      (node (ref "IC167") (pin "10") (pinfunction "10_10") (pintype "passive"))
      (node (ref "IC168") (pin "10") (pinfunction "10_10") (pintype "passive"))
    )
    (net (code "996") (name "Net-(IC165-Pad11)") (class "Default")
      (node (ref "IC165") (pin "11") (pinfunction "11_11") (pintype "passive"))
      (node (ref "IC166") (pin "11") (pinfunction "11_11") (pintype "passive"))
      (node (ref "IC167") (pin "11") (pinfunction "11_11") (pintype "passive"))
      (node (ref "IC168") (pin "11") (pinfunction "11_11") (pintype "passive"))
    )
    (net (code "997") (name "Net-(IC165-Pad12)") (class "Default")
      (node (ref "IC165") (pin "12") (pinfunction "12_12") (pintype "passive"))
      (node (ref "IC166") (pin "12") (pinfunction "12_12") (pintype "passive"))
      (node (ref "IC167") (pin "12") (pinfunction "12_12") (pintype "passive"))
      (node (ref "IC168") (pin "12") (pinfunction "12_12") (pintype "passive"))
    )
    (net (code "998") (name "Net-(IC165-Pad13)") (class "Default")
      (node (ref "IC165") (pin "13") (pinfunction "13_13") (pintype "passive"))
      (node (ref "IC166") (pin "13") (pinfunction "13_13") (pintype "passive"))
      (node (ref "IC167") (pin "13") (pinfunction "13_13") (pintype "passive"))
      (node (ref "IC168") (pin "13") (pinfunction "13_13") (pintype "passive"))
    )
    (net (code "999") (name "Net-(IC165-Pad14)") (class "Default")
      (node (ref "IC165") (pin "14") (pinfunction "14_14") (pintype "passive"))
      (node (ref "IC166") (pin "14") (pinfunction "14_14") (pintype "passive"))
      (node (ref "IC167") (pin "14") (pinfunction "14_14") (pintype "passive"))
      (node (ref "IC168") (pin "14") (pinfunction "14_14") (pintype "passive"))
    )
    (net (code "1000") (name "Net-(IC165-Pad15)") (class "Default")
      (node (ref "IC165") (pin "15") (pinfunction "15_15") (pintype "passive"))
      (node (ref "IC166") (pin "15") (pinfunction "15_15") (pintype "passive"))
      (node (ref "IC167") (pin "15") (pinfunction "15_15") (pintype "passive"))
      (node (ref "IC168") (pin "15") (pinfunction "15_15") (pintype "passive"))
    )
    (net (code "1001") (name "Net-(IC165-Pad16)") (class "Default")
      (node (ref "IC165") (pin "16") (pinfunction "16_16") (pintype "passive"))
      (node (ref "IC166") (pin "16") (pinfunction "16_16") (pintype "passive"))
      (node (ref "IC167") (pin "16") (pinfunction "16_16") (pintype "passive"))
      (node (ref "IC168") (pin "16") (pinfunction "16_16") (pintype "passive"))
    )
    (net (code "1002") (name "Net-(IC165-Pad17)") (class "Default")
      (node (ref "IC165") (pin "17") (pinfunction "17_17") (pintype "passive"))
      (node (ref "IC166") (pin "17") (pinfunction "17_17") (pintype "passive"))
      (node (ref "IC167") (pin "17") (pinfunction "17_17") (pintype "passive"))
      (node (ref "IC168") (pin "17") (pinfunction "17_17") (pintype "passive"))
    )
    (net (code "1003") (name "Net-(IC165-Pad18)") (class "Default")
      (node (ref "IC165") (pin "18") (pinfunction "18_18") (pintype "passive"))
      (node (ref "IC166") (pin "18") (pinfunction "18_18") (pintype "passive"))
      (node (ref "IC167") (pin "18") (pinfunction "18_18") (pintype "passive"))
      (node (ref "IC168") (pin "18") (pinfunction "18_18") (pintype "passive"))
    )
    (net (code "1004") (name "Net-(IC165-Pad19)") (class "Default")
      (node (ref "IC165") (pin "19") (pinfunction "19_19") (pintype "passive"))
      (node (ref "IC166") (pin "19") (pinfunction "19_19") (pintype "passive"))
      (node (ref "IC167") (pin "19") (pinfunction "19_19") (pintype "passive"))
      (node (ref "IC168") (pin "19") (pinfunction "19_19") (pintype "passive"))
    )
    (net (code "1005") (name "Net-(IC165-Pad20)") (class "Default")
      (node (ref "IC165") (pin "20") (pinfunction "20_20") (pintype "passive"))
      (node (ref "IC166") (pin "20") (pinfunction "20_20") (pintype "passive"))
      (node (ref "IC167") (pin "20") (pinfunction "20_20") (pintype "passive"))
      (node (ref "IC168") (pin "20") (pinfunction "20_20") (pintype "passive"))
    )
    (net (code "1006") (name "Net-(IC165-Pad21)") (class "Default")
      (node (ref "IC165") (pin "21") (pinfunction "21_21") (pintype "passive"))
      (node (ref "IC166") (pin "21") (pinfunction "21_21") (pintype "passive"))
      (node (ref "IC167") (pin "21") (pinfunction "21_21") (pintype "passive"))
      (node (ref "IC168") (pin "21") (pinfunction "21_21") (pintype "passive"))
    )
    (net (code "1007") (name "Net-(IC165-Pad22)") (class "Default")
      (node (ref "IC165") (pin "22") (pinfunction "22_22") (pintype "passive"))
      (node (ref "IC166") (pin "22") (pinfunction "22_22") (pintype "passive"))
      (node (ref "IC167") (pin "22") (pinfunction "22_22") (pintype "passive"))
      (node (ref "IC168") (pin "22") (pinfunction "22_22") (pintype "passive"))
    )
    (net (code "1008") (name "Net-(IC165-Pad23)") (class "Default")
      (node (ref "IC165") (pin "23") (pinfunction "23_23") (pintype "passive"))
      (node (ref "IC166") (pin "23") (pinfunction "23_23") (pintype "passive"))
      (node (ref "IC167") (pin "23") (pinfunction "23_23") (pintype "passive"))
      (node (ref "IC168") (pin "23") (pinfunction "23_23") (pintype "passive"))
    )
    (net (code "1009") (name "Net-(IC165-Pad24)") (class "Default")
      (node (ref "IC165") (pin "24") (pinfunction "24_24") (pintype "passive"))
      (node (ref "IC166") (pin "24") (pinfunction "24_24") (pintype "passive"))
      (node (ref "IC167") (pin "24") (pinfunction "24_24") (pintype "passive"))
      (node (ref "IC168") (pin "24") (pinfunction "24_24") (pintype "passive"))
    )
    (net (code "1010") (name "Net-(IC169-Pad1)") (class "Default")
      (node (ref "IC169") (pin "1") (pinfunction "1_1") (pintype "passive"))
      (node (ref "IC170") (pin "1") (pinfunction "1_1") (pintype "passive"))
      (node (ref "IC171") (pin "1") (pinfunction "1_1") (pintype "passive"))
      (node (ref "IC172") (pin "1") (pinfunction "1_1") (pintype "passive"))
    )
    (net (code "1011") (name "Net-(IC169-Pad2)") (class "Default")
      (node (ref "IC169") (pin "2") (pinfunction "2_2") (pintype "passive"))
      (node (ref "IC170") (pin "2") (pinfunction "2_2") (pintype "passive"))
      (node (ref "IC171") (pin "2") (pinfunction "2_2") (pintype "passive"))
      (node (ref "IC172") (pin "2") (pinfunction "2_2") (pintype "passive"))
    )
    (net (code "1012") (name "Net-(IC169-Pad3)") (class "Default")
      (node (ref "IC169") (pin "3") (pinfunction "3_3") (pintype "passive"))
      (node (ref "IC170") (pin "3") (pinfunction "3_3") (pintype "passive"))
      (node (ref "IC171") (pin "3") (pinfunction "3_3") (pintype "passive"))
      (node (ref "IC172") (pin "3") (pinfunction "3_3") (pintype "passive"))
    )
    (net (code "1013") (name "Net-(IC169-Pad4)") (class "Default")
      (node (ref "IC169") (pin "4") (pinfunction "4_4") (pintype "passive"))
      (node (ref "IC170") (pin "4") (pinfunction "4_4") (pintype "passive"))
      (node (ref "IC171") (pin "4") (pinfunction "4_4") (pintype "passive"))
      (node (ref "IC172") (pin "4") (pinfunction "4_4") (pintype "passive"))
    )
    (net (code "1014") (name "Net-(IC169-Pad5)") (class "Default")
      (node (ref "IC169") (pin "5") (pinfunction "5_5") (pintype "passive"))
      (node (ref "IC170") (pin "5") (pinfunction "5_5") (pintype "passive"))
      (node (ref "IC171") (pin "5") (pinfunction "5_5") (pintype "passive"))
      (node (ref "IC172") (pin "5") (pinfunction "5_5") (pintype "passive"))
    )
    (net (code "1015") (name "Net-(IC169-Pad6)") (class "Default")
      (node (ref "IC169") (pin "6") (pinfunction "6_6") (pintype "passive"))
      (node (ref "IC170") (pin "6") (pinfunction "6_6") (pintype "passive"))
      (node (ref "IC171") (pin "6") (pinfunction "6_6") (pintype "passive"))
      (node (ref "IC172") (pin "6") (pinfunction "6_6") (pintype "passive"))
    )
    (net (code "1016") (name "Net-(IC169-Pad7)") (class "Default")
      (node (ref "IC169") (pin "7") (pinfunction "7_7") (pintype "passive"))
      (node (ref "IC170") (pin "7") (pinfunction "7_7") (pintype "passive"))
      (node (ref "IC171") (pin "7") (pinfunction "7_7") (pintype "passive"))
      (node (ref "IC172") (pin "7") (pinfunction "7_7") (pintype "passive"))
    )
    (net (code "1017") (name "Net-(IC169-Pad8)") (class "Default")
      (node (ref "IC169") (pin "8") (pinfunction "8_8") (pintype "passive"))
      (node (ref "IC170") (pin "8") (pinfunction "8_8") (pintype "passive"))
      (node (ref "IC171") (pin "8") (pinfunction "8_8") (pintype "passive"))
      (node (ref "IC172") (pin "8") (pinfunction "8_8") (pintype "passive"))
    )
    (net (code "1018") (name "Net-(IC169-Pad9)") (class "Default")
      (node (ref "IC169") (pin "9") (pinfunction "9_9") (pintype "passive"))
      (node (ref "IC170") (pin "9") (pinfunction "9_9") (pintype "passive"))
      (node (ref "IC171") (pin "9") (pinfunction "9_9") (pintype "passive"))
      (node (ref "IC172") (pin "9") (pinfunction "9_9") (pintype "passive"))
    )
    (net (code "1019") (name "Net-(IC169-Pad10)") (class "Default")
      (node (ref "IC169") (pin "10") (pinfunction "10_10") (pintype "passive"))
      (node (ref "IC170") (pin "10") (pinfunction "10_10") (pintype "passive"))
      (node (ref "IC171") (pin "10") (pinfunction "10_10") (pintype "passive"))
      (node (ref "IC172") (pin "10") (pinfunction "10_10") (pintype "passive"))
    )
    (net (code "1020") (name "Net-(IC169-Pad11)") (class "Default")
      (node (ref "IC169") (pin "11") (pinfunction "11_11") (pintype "passive"))
      (node (ref "IC170") (pin "11") (pinfunction "11_11") (pintype "passive"))
      (node (ref "IC171") (pin "11") (pinfunction "11_11") (pintype "passive"))
      (node (ref "IC172") (pin "11") (pinfunction "11_11") (pintype "passive"))
    )
    (net (code "1021") (name "Net-(IC169-Pad12)") (class "Default")
      (node (ref "IC169") (pin "12") (pinfunction "12_12") (pintype "passive"))
      (node (ref "IC170") (pin "12") (pinfunction "12_12") (pintype "passive"))
      (node (ref "IC171") (pin "12") (pinfunction "12_12") (pintype "passive"))
      (node (ref "IC172") (pin "12") (pinfunction "12_12") (pintype "passive"))
    )
    (net (code "1022") (name "Net-(IC169-Pad13)") (class "Default")
      (node (ref "IC169") (pin "13") (pinfunction "13_13") (pintype "passive"))
      (node (ref "IC170") (pin "13") (pinfunction "13_13") (pintype "passive"))
      (node (ref "IC171") (pin "13") (pinfunction "13_13") (pintype "passive"))
      (node (ref "IC172") (pin "13") (pinfunction "13_13") (pintype "passive"))
    )
    (net (code "1023") (name "Net-(IC169-Pad14)") (class "Default")
      (node (ref "IC169") (pin "14") (pinfunction "14_14") (pintype "passive"))
      (node (ref "IC170") (pin "14") (pinfunction "14_14") (pintype "passive"))
      (node (ref "IC171") (pin "14") (pinfunction "14_14") (pintype "passive"))
      (node (ref "IC172") (pin "14") (pinfunction "14_14") (pintype "passive"))
    )
    (net (code "1024") (name "Net-(IC169-Pad15)") (class "Default")
      (node (ref "IC169") (pin "15") (pinfunction "15_15") (pintype "passive"))
      (node (ref "IC170") (pin "15") (pinfunction "15_15") (pintype "passive"))
      (node (ref "IC171") (pin "15") (pinfunction "15_15") (pintype "passive"))
      (node (ref "IC172") (pin "15") (pinfunction "15_15") (pintype "passive"))
    )
    (net (code "1025") (name "Net-(IC169-Pad16)") (class "Default")
      (node (ref "IC169") (pin "16") (pinfunction "16_16") (pintype "passive"))
      (node (ref "IC170") (pin "16") (pinfunction "16_16") (pintype "passive"))
      (node (ref "IC171") (pin "16") (pinfunction "16_16") (pintype "passive"))
      (node (ref "IC172") (pin "16") (pinfunction "16_16") (pintype "passive"))
    )
    (net (code "1026") (name "Net-(IC169-Pad17)") (class "Default")
      (node (ref "IC169") (pin "17") (pinfunction "17_17") (pintype "passive"))
      (node (ref "IC170") (pin "17") (pinfunction "17_17") (pintype "passive"))
      (node (ref "IC171") (pin "17") (pinfunction "17_17") (pintype "passive"))
      (node (ref "IC172") (pin "17") (pinfunction "17_17") (pintype "passive"))
    )
    (net (code "1027") (name "Net-(IC169-Pad18)") (class "Default")
      (node (ref "IC169") (pin "18") (pinfunction "18_18") (pintype "passive"))
      (node (ref "IC170") (pin "18") (pinfunction "18_18") (pintype "passive"))
      (node (ref "IC171") (pin "18") (pinfunction "18_18") (pintype "passive"))
      (node (ref "IC172") (pin "18") (pinfunction "18_18") (pintype "passive"))
    )
    (net (code "1028") (name "Net-(IC169-Pad19)") (class "Default")
      (node (ref "IC169") (pin "19") (pinfunction "19_19") (pintype "passive"))
      (node (ref "IC170") (pin "19") (pinfunction "19_19") (pintype "passive"))
      (node (ref "IC171") (pin "19") (pinfunction "19_19") (pintype "passive"))
      (node (ref "IC172") (pin "19") (pinfunction "19_19") (pintype "passive"))
    )
    (net (code "1029") (name "Net-(IC169-Pad20)") (class "Default")
      (node (ref "IC169") (pin "20") (pinfunction "20_20") (pintype "passive"))
      (node (ref "IC170") (pin "20") (pinfunction "20_20") (pintype "passive"))
      (node (ref "IC171") (pin "20") (pinfunction "20_20") (pintype "passive"))
      (node (ref "IC172") (pin "20") (pinfunction "20_20") (pintype "passive"))
    )
    (net (code "1030") (name "Net-(IC169-Pad21)") (class "Default")
      (node (ref "IC169") (pin "21") (pinfunction "21_21") (pintype "passive"))
      (node (ref "IC170") (pin "21") (pinfunction "21_21") (pintype "passive"))
      (node (ref "IC171") (pin "21") (pinfunction "21_21") (pintype "passive"))
      (node (ref "IC172") (pin "21") (pinfunction "21_21") (pintype "passive"))
    )
    (net (code "1031") (name "Net-(IC169-Pad22)") (class "Default")
      (node (ref "IC169") (pin "22") (pinfunction "22_22") (pintype "passive"))
      (node (ref "IC170") (pin "22") (pinfunction "22_22") (pintype "passive"))
      (node (ref "IC171") (pin "22") (pinfunction "22_22") (pintype "passive"))
      (node (ref "IC172") (pin "22") (pinfunction "22_22") (pintype "passive"))
    )
    (net (code "1032") (name "Net-(IC169-Pad23)") (class "Default")
      (node (ref "IC169") (pin "23") (pinfunction "23_23") (pintype "passive"))
      (node (ref "IC170") (pin "23") (pinfunction "23_23") (pintype "passive"))
      (node (ref "IC171") (pin "23") (pinfunction "23_23") (pintype "passive"))
      (node (ref "IC172") (pin "23") (pinfunction "23_23") (pintype "passive"))
    )
    (net (code "1033") (name "Net-(IC169-Pad24)") (class "Default")
      (node (ref "IC169") (pin "24") (pinfunction "24_24") (pintype "passive"))
      (node (ref "IC170") (pin "24") (pinfunction "24_24") (pintype "passive"))
      (node (ref "IC171") (pin "24") (pinfunction "24_24") (pintype "passive"))
      (node (ref "IC172") (pin "24") (pinfunction "24_24") (pintype "passive"))
    )
    (net (code "1034") (name "Net-(IC173-Pad1)") (class "Default")
      (node (ref "IC173") (pin "1") (pinfunction "1_1") (pintype "passive"))
      (node (ref "IC174") (pin "1") (pinfunction "1_1") (pintype "passive"))
      (node (ref "IC175") (pin "1") (pinfunction "1_1") (pintype "passive"))
      (node (ref "IC176") (pin "1") (pinfunction "1_1") (pintype "passive"))
    )
    (net (code "1035") (name "Net-(IC173-Pad2)") (class "Default")
      (node (ref "IC173") (pin "2") (pinfunction "2_2") (pintype "passive"))
      (node (ref "IC174") (pin "2") (pinfunction "2_2") (pintype "passive"))
      (node (ref "IC175") (pin "2") (pinfunction "2_2") (pintype "passive"))
      (node (ref "IC176") (pin "2") (pinfunction "2_2") (pintype "passive"))
    )
    (net (code "1036") (name "Net-(IC173-Pad3)") (class "Default")
      (node (ref "IC173") (pin "3") (pinfunction "3_3") (pintype "passive"))
      (node (ref "IC174") (pin "3") (pinfunction "3_3") (pintype "passive"))
      (node (ref "IC175") (pin "3") (pinfunction "3_3") (pintype "passive"))
      (node (ref "IC176") (pin "3") (pinfunction "3_3") (pintype "passive"))
    )
    (net (code "1037") (name "Net-(IC173-Pad4)") (class "Default")
      (node (ref "IC173") (pin "4") (pinfunction "4_4") (pintype "passive"))
      (node (ref "IC174") (pin "4") (pinfunction "4_4") (pintype "passive"))
      (node (ref "IC175") (pin "4") (pinfunction "4_4") (pintype "passive"))
      (node (ref "IC176") (pin "4") (pinfunction "4_4") (pintype "passive"))
    )
    (net (code "1038") (name "Net-(IC173-Pad5)") (class "Default")
      (node (ref "IC173") (pin "5") (pinfunction "5_5") (pintype "passive"))
      (node (ref "IC174") (pin "5") (pinfunction "5_5") (pintype "passive"))
      (node (ref "IC175") (pin "5") (pinfunction "5_5") (pintype "passive"))
      (node (ref "IC176") (pin "5") (pinfunction "5_5") (pintype "passive"))
    )
    (net (code "1039") (name "Net-(IC173-Pad6)") (class "Default")
      (node (ref "IC173") (pin "6") (pinfunction "6_6") (pintype "passive"))
      (node (ref "IC174") (pin "6") (pinfunction "6_6") (pintype "passive"))
      (node (ref "IC175") (pin "6") (pinfunction "6_6") (pintype "passive"))
      (node (ref "IC176") (pin "6") (pinfunction "6_6") (pintype "passive"))
    )
    (net (code "1040") (name "Net-(IC173-Pad7)") (class "Default")
      (node (ref "IC173") (pin "7") (pinfunction "7_7") (pintype "passive"))
      (node (ref "IC174") (pin "7") (pinfunction "7_7") (pintype "passive"))
      (node (ref "IC175") (pin "7") (pinfunction "7_7") (pintype "passive"))
      (node (ref "IC176") (pin "7") (pinfunction "7_7") (pintype "passive"))
    )
    (net (code "1041") (name "Net-(IC173-Pad8)") (class "Default")
      (node (ref "IC173") (pin "8") (pinfunction "8_8") (pintype "passive"))
      (node (ref "IC174") (pin "8") (pinfunction "8_8") (pintype "passive"))
      (node (ref "IC175") (pin "8") (pinfunction "8_8") (pintype "passive"))
      (node (ref "IC176") (pin "8") (pinfunction "8_8") (pintype "passive"))
    )
    (net (code "1042") (name "Net-(IC173-Pad9)") (class "Default")
      (node (ref "IC173") (pin "9") (pinfunction "9_9") (pintype "passive"))
      (node (ref "IC174") (pin "9") (pinfunction "9_9") (pintype "passive"))
      (node (ref "IC175") (pin "9") (pinfunction "9_9") (pintype "passive"))
      (node (ref "IC176") (pin "9") (pinfunction "9_9") (pintype "passive"))
    )
    (net (code "1043") (name "Net-(IC173-Pad10)") (class "Default")
      (node (ref "IC173") (pin "10") (pinfunction "10_10") (pintype "passive"))
      (node (ref "IC174") (pin "10") (pinfunction "10_10") (pintype "passive"))
      (node (ref "IC175") (pin "10") (pinfunction "10_10") (pintype "passive"))
      (node (ref "IC176") (pin "10") (pinfunction "10_10") (pintype "passive"))
    )
    (net (code "1044") (name "Net-(IC173-Pad11)") (class "Default")
      (node (ref "IC173") (pin "11") (pinfunction "11_11") (pintype "passive"))
      (node (ref "IC174") (pin "11") (pinfunction "11_11") (pintype "passive"))
      (node (ref "IC175") (pin "11") (pinfunction "11_11") (pintype "passive"))
      (node (ref "IC176") (pin "11") (pinfunction "11_11") (pintype "passive"))
    )
    (net (code "1045") (name "Net-(IC173-Pad12)") (class "Default")
      (node (ref "IC173") (pin "12") (pinfunction "12_12") (pintype "passive"))
      (node (ref "IC174") (pin "12") (pinfunction "12_12") (pintype "passive"))
      (node (ref "IC175") (pin "12") (pinfunction "12_12") (pintype "passive"))
      (node (ref "IC176") (pin "12") (pinfunction "12_12") (pintype "passive"))
    )
    (net (code "1046") (name "Net-(IC173-Pad13)") (class "Default")
      (node (ref "IC173") (pin "13") (pinfunction "13_13") (pintype "passive"))
      (node (ref "IC174") (pin "13") (pinfunction "13_13") (pintype "passive"))
      (node (ref "IC175") (pin "13") (pinfunction "13_13") (pintype "passive"))
      (node (ref "IC176") (pin "13") (pinfunction "13_13") (pintype "passive"))
    )
    (net (code "1047") (name "Net-(IC173-Pad14)") (class "Default")
      (node (ref "IC173") (pin "14") (pinfunction "14_14") (pintype "passive"))
      (node (ref "IC174") (pin "14") (pinfunction "14_14") (pintype "passive"))
      (node (ref "IC175") (pin "14") (pinfunction "14_14") (pintype "passive"))
      (node (ref "IC176") (pin "14") (pinfunction "14_14") (pintype "passive"))
    )
    (net (code "1048") (name "Net-(IC173-Pad15)") (class "Default")
      (node (ref "IC173") (pin "15") (pinfunction "15_15") (pintype "passive"))
      (node (ref "IC174") (pin "15") (pinfunction "15_15") (pintype "passive"))
      (node (ref "IC175") (pin "15") (pinfunction "15_15") (pintype "passive"))
      (node (ref "IC176") (pin "15") (pinfunction "15_15") (pintype "passive"))
    )
    (net (code "1049") (name "Net-(IC173-Pad16)") (class "Default")
      (node (ref "IC173") (pin "16") (pinfunction "16_16") (pintype "passive"))
      (node (ref "IC174") (pin "16") (pinfunction "16_16") (pintype "passive"))
      (node (ref "IC175") (pin "16") (pinfunction "16_16") (pintype "passive"))
      (node (ref "IC176") (pin "16") (pinfunction "16_16") (pintype "passive"))
    )
    (net (code "1050") (name "Net-(IC173-Pad17)") (class "Default")
      (node (ref "IC173") (pin "17") (pinfunction "17_17") (pintype "passive"))
      (node (ref "IC174") (pin "17") (pinfunction "17_17") (pintype "passive"))
      (node (ref "IC175") (pin "17") (pinfunction "17_17") (pintype "passive"))
      (node (ref "IC176") (pin "17") (pinfunction "17_17") (pintype "passive"))
    )
    (net (code "1051") (name "Net-(IC173-Pad18)") (class "Default")
      (node (ref "IC173") (pin "18") (pinfunction "18_18") (pintype "passive"))
      (node (ref "IC174") (pin "18") (pinfunction "18_18") (pintype "passive"))
      (node (ref "IC175") (pin "18") (pinfunction "18_18") (pintype "passive"))
      (node (ref "IC176") (pin "18") (pinfunction "18_18") (pintype "passive"))
    )
    (net (code "1052") (name "Net-(IC173-Pad19)") (class "Default")
      (node (ref "IC173") (pin "19") (pinfunction "19_19") (pintype "passive"))
      (node (ref "IC174") (pin "19") (pinfunction "19_19") (pintype "passive"))
      (node (ref "IC175") (pin "19") (pinfunction "19_19") (pintype "passive"))
      (node (ref "IC176") (pin "19") (pinfunction "19_19") (pintype "passive"))
    )
    (net (code "1053") (name "Net-(IC173-Pad20)") (class "Default")
      (node (ref "IC173") (pin "20") (pinfunction "20_20") (pintype "passive"))
      (node (ref "IC174") (pin "20") (pinfunction "20_20") (pintype "passive"))
      (node (ref "IC175") (pin "20") (pinfunction "20_20") (pintype "passive"))
      (node (ref "IC176") (pin "20") (pinfunction "20_20") (pintype "passive"))
    )
    (net (code "1054") (name "Net-(IC173-Pad21)") (class "Default")
      (node (ref "IC173") (pin "21") (pinfunction "21_21") (pintype "passive"))
      (node (ref "IC174") (pin "21") (pinfunction "21_21") (pintype "passive"))
      (node (ref "IC175") (pin "21") (pinfunction "21_21") (pintype "passive"))
      (node (ref "IC176") (pin "21") (pinfunction "21_21") (pintype "passive"))
    )
    (net (code "1055") (name "Net-(IC173-Pad22)") (class "Default")
      (node (ref "IC173") (pin "22") (pinfunction "22_22") (pintype "passive"))
      (node (ref "IC174") (pin "22") (pinfunction "22_22") (pintype "passive"))
      (node (ref "IC175") (pin "22") (pinfunction "22_22") (pintype "passive"))
      (node (ref "IC176") (pin "22") (pinfunction "22_22") (pintype "passive"))
    )
    (net (code "1056") (name "Net-(IC173-Pad23)") (class "Default")
      (node (ref "IC173") (pin "23") (pinfunction "23_23") (pintype "passive"))
      (node (ref "IC174") (pin "23") (pinfunction "23_23") (pintype "passive"))
      (node (ref "IC175") (pin "23") (pinfunction "23_23") (pintype "passive"))
      (node (ref "IC176") (pin "23") (pinfunction "23_23") (pintype "passive"))
    )
    (net (code "1057") (name "Net-(IC173-Pad24)") (class "Default")
      (node (ref "IC173") (pin "24") (pinfunction "24_24") (pintype "passive"))
      (node (ref "IC174") (pin "24") (pinfunction "24_24") (pintype "passive"))
      (node (ref "IC175") (pin "24") (pinfunction "24_24") (pintype "passive"))
      (node (ref "IC176") (pin "24") (pinfunction "24_24") (pintype "passive"))
    )
    (net (code "1058") (name "Net-(IC177-Pad1)") (class "Default")
      (node (ref "IC177") (pin "1") (pinfunction "1_1") (pintype "passive"))
      (node (ref "IC178") (pin "1") (pinfunction "1_1") (pintype "passive"))
      (node (ref "IC179") (pin "1") (pinfunction "1_1") (pintype "passive"))
      (node (ref "IC180") (pin "1") (pinfunction "1_1") (pintype "passive"))
    )
    (net (code "1059") (name "Net-(IC177-Pad2)") (class "Default")
      (node (ref "IC177") (pin "2") (pinfunction "2_2") (pintype "passive"))
      (node (ref "IC178") (pin "2") (pinfunction "2_2") (pintype "passive"))
      (node (ref "IC179") (pin "2") (pinfunction "2_2") (pintype "passive"))
      (node (ref "IC180") (pin "2") (pinfunction "2_2") (pintype "passive"))
    )
    (net (code "1060") (name "Net-(IC177-Pad3)") (class "Default")
      (node (ref "IC177") (pin "3") (pinfunction "3_3") (pintype "passive"))
      (node (ref "IC178") (pin "3") (pinfunction "3_3") (pintype "passive"))
      (node (ref "IC179") (pin "3") (pinfunction "3_3") (pintype "passive"))
      (node (ref "IC180") (pin "3") (pinfunction "3_3") (pintype "passive"))
    )
    (net (code "1061") (name "Net-(IC177-Pad4)") (class "Default")
      (node (ref "IC177") (pin "4") (pinfunction "4_4") (pintype "passive"))
      (node (ref "IC178") (pin "4") (pinfunction "4_4") (pintype "passive"))
      (node (ref "IC179") (pin "4") (pinfunction "4_4") (pintype "passive"))
      (node (ref "IC180") (pin "4") (pinfunction "4_4") (pintype "passive"))
    )
    (net (code "1062") (name "Net-(IC177-Pad5)") (class "Default")
      (node (ref "IC177") (pin "5") (pinfunction "5_5") (pintype "passive"))
      (node (ref "IC178") (pin "5") (pinfunction "5_5") (pintype "passive"))
      (node (ref "IC179") (pin "5") (pinfunction "5_5") (pintype "passive"))
      (node (ref "IC180") (pin "5") (pinfunction "5_5") (pintype "passive"))
    )
    (net (code "1063") (name "Net-(IC177-Pad6)") (class "Default")
      (node (ref "IC177") (pin "6") (pinfunction "6_6") (pintype "passive"))
      (node (ref "IC178") (pin "6") (pinfunction "6_6") (pintype "passive"))
      (node (ref "IC179") (pin "6") (pinfunction "6_6") (pintype "passive"))
      (node (ref "IC180") (pin "6") (pinfunction "6_6") (pintype "passive"))
    )
    (net (code "1064") (name "Net-(IC177-Pad7)") (class "Default")
      (node (ref "IC177") (pin "7") (pinfunction "7_7") (pintype "passive"))
      (node (ref "IC178") (pin "7") (pinfunction "7_7") (pintype "passive"))
      (node (ref "IC179") (pin "7") (pinfunction "7_7") (pintype "passive"))
      (node (ref "IC180") (pin "7") (pinfunction "7_7") (pintype "passive"))
    )
    (net (code "1065") (name "Net-(IC177-Pad8)") (class "Default")
      (node (ref "IC177") (pin "8") (pinfunction "8_8") (pintype "passive"))
      (node (ref "IC178") (pin "8") (pinfunction "8_8") (pintype "passive"))
      (node (ref "IC179") (pin "8") (pinfunction "8_8") (pintype "passive"))
      (node (ref "IC180") (pin "8") (pinfunction "8_8") (pintype "passive"))
    )
    (net (code "1066") (name "Net-(IC177-Pad9)") (class "Default")
      (node (ref "IC177") (pin "9") (pinfunction "9_9") (pintype "passive"))
      (node (ref "IC178") (pin "9") (pinfunction "9_9") (pintype "passive"))
      (node (ref "IC179") (pin "9") (pinfunction "9_9") (pintype "passive"))
      (node (ref "IC180") (pin "9") (pinfunction "9_9") (pintype "passive"))
    )
    (net (code "1067") (name "Net-(IC177-Pad10)") (class "Default")
      (node (ref "IC177") (pin "10") (pinfunction "10_10") (pintype "passive"))
      (node (ref "IC178") (pin "10") (pinfunction "10_10") (pintype "passive"))
      (node (ref "IC179") (pin "10") (pinfunction "10_10") (pintype "passive"))
      (node (ref "IC180") (pin "10") (pinfunction "10_10") (pintype "passive"))
    )
    (net (code "1068") (name "Net-(IC177-Pad11)") (class "Default")
      (node (ref "IC177") (pin "11") (pinfunction "11_11") (pintype "passive"))
      (node (ref "IC178") (pin "11") (pinfunction "11_11") (pintype "passive"))
      (node (ref "IC179") (pin "11") (pinfunction "11_11") (pintype "passive"))
      (node (ref "IC180") (pin "11") (pinfunction "11_11") (pintype "passive"))
    )
    (net (code "1069") (name "Net-(IC177-Pad12)") (class "Default")
      (node (ref "IC177") (pin "12") (pinfunction "12_12") (pintype "passive"))
      (node (ref "IC178") (pin "12") (pinfunction "12_12") (pintype "passive"))
      (node (ref "IC179") (pin "12") (pinfunction "12_12") (pintype "passive"))
      (node (ref "IC180") (pin "12") (pinfunction "12_12") (pintype "passive"))
    )
    (net (code "1070") (name "Net-(IC177-Pad13)") (class "Default")
      (node (ref "IC177") (pin "13") (pinfunction "13_13") (pintype "passive"))
      (node (ref "IC178") (pin "13") (pinfunction "13_13") (pintype "passive"))
      (node (ref "IC179") (pin "13") (pinfunction "13_13") (pintype "passive"))
      (node (ref "IC180") (pin "13") (pinfunction "13_13") (pintype "passive"))
    )
    (net (code "1071") (name "Net-(IC177-Pad14)") (class "Default")
      (node (ref "IC177") (pin "14") (pinfunction "14_14") (pintype "passive"))
      (node (ref "IC178") (pin "14") (pinfunction "14_14") (pintype "passive"))
      (node (ref "IC179") (pin "14") (pinfunction "14_14") (pintype "passive"))
      (node (ref "IC180") (pin "14") (pinfunction "14_14") (pintype "passive"))
    )
    (net (code "1072") (name "Net-(IC177-Pad15)") (class "Default")
      (node (ref "IC177") (pin "15") (pinfunction "15_15") (pintype "passive"))
      (node (ref "IC178") (pin "15") (pinfunction "15_15") (pintype "passive"))
      (node (ref "IC179") (pin "15") (pinfunction "15_15") (pintype "passive"))
      (node (ref "IC180") (pin "15") (pinfunction "15_15") (pintype "passive"))
    )
    (net (code "1073") (name "Net-(IC177-Pad16)") (class "Default")
      (node (ref "IC177") (pin "16") (pinfunction "16_16") (pintype "passive"))
      (node (ref "IC178") (pin "16") (pinfunction "16_16") (pintype "passive"))
      (node (ref "IC179") (pin "16") (pinfunction "16_16") (pintype "passive"))
      (node (ref "IC180") (pin "16") (pinfunction "16_16") (pintype "passive"))
    )
    (net (code "1074") (name "Net-(IC177-Pad17)") (class "Default")
      (node (ref "IC177") (pin "17") (pinfunction "17_17") (pintype "passive"))
      (node (ref "IC178") (pin "17") (pinfunction "17_17") (pintype "passive"))
      (node (ref "IC179") (pin "17") (pinfunction "17_17") (pintype "passive"))
      (node (ref "IC180") (pin "17") (pinfunction "17_17") (pintype "passive"))
    )
    (net (code "1075") (name "Net-(IC177-Pad18)") (class "Default")
      (node (ref "IC177") (pin "18") (pinfunction "18_18") (pintype "passive"))
      (node (ref "IC178") (pin "18") (pinfunction "18_18") (pintype "passive"))
      (node (ref "IC179") (pin "18") (pinfunction "18_18") (pintype "passive"))
      (node (ref "IC180") (pin "18") (pinfunction "18_18") (pintype "passive"))
    )
    (net (code "1076") (name "Net-(IC177-Pad19)") (class "Default")
      (node (ref "IC177") (pin "19") (pinfunction "19_19") (pintype "passive"))
      (node (ref "IC178") (pin "19") (pinfunction "19_19") (pintype "passive"))
      (node (ref "IC179") (pin "19") (pinfunction "19_19") (pintype "passive"))
      (node (ref "IC180") (pin "19") (pinfunction "19_19") (pintype "passive"))
    )
    (net (code "1077") (name "Net-(IC177-Pad20)") (class "Default")
      (node (ref "IC177") (pin "20") (pinfunction "20_20") (pintype "passive"))
      (node (ref "IC178") (pin "20") (pinfunction "20_20") (pintype "passive"))
      (node (ref "IC179") (pin "20") (pinfunction "20_20") (pintype "passive"))
      (node (ref "IC180") (pin "20") (pinfunction "20_20") (pintype "passive"))
    )
    (net (code "1078") (name "Net-(IC177-Pad21)") (class "Default")
      (node (ref "IC177") (pin "21") (pinfunction "21_21") (pintype "passive"))
      (node (ref "IC178") (pin "21") (pinfunction "21_21") (pintype "passive"))
      (node (ref "IC179") (pin "21") (pinfunction "21_21") (pintype "passive"))
      (node (ref "IC180") (pin "21") (pinfunction "21_21") (pintype "passive"))
    )
    (net (code "1079") (name "Net-(IC177-Pad22)") (class "Default")
      (node (ref "IC177") (pin "22") (pinfunction "22_22") (pintype "passive"))
      (node (ref "IC178") (pin "22") (pinfunction "22_22") (pintype "passive"))
      (node (ref "IC179") (pin "22") (pinfunction "22_22") (pintype "passive"))
      (node (ref "IC180") (pin "22") (pinfunction "22_22") (pintype "passive"))
    )
    (net (code "1080") (name "Net-(IC177-Pad23)") (class "Default")
      (node (ref "IC177") (pin "23") (pinfunction "23_23") (pintype "passive"))
      (node (ref "IC178") (pin "23") (pinfunction "23_23") (pintype "passive"))
      (node (ref "IC179") (pin "23") (pinfunction "23_23") (pintype "passive"))
      (node (ref "IC180") (pin "23") (pinfunction "23_23") (pintype "passive"))
    )
    (net (code "1081") (name "Net-(IC177-Pad24)") (class "Default")
      (node (ref "IC177") (pin "24") (pinfunction "24_24") (pintype "passive"))
      (node (ref "IC178") (pin "24") (pinfunction "24_24") (pintype "passive"))
      (node (ref "IC179") (pin "24") (pinfunction "24_24") (pintype "passive"))
      (node (ref "IC180") (pin "24") (pinfunction "24_24") (pintype "passive"))
    )
    (net (code "1082") (name "Net-(IC181-Pad1)") (class "Default")
      (node (ref "IC181") (pin "1") (pinfunction "1_1") (pintype "passive"))
      (node (ref "IC182") (pin "1") (pinfunction "1_1") (pintype "passive"))
      (node (ref "IC183") (pin "1") (pinfunction "1_1") (pintype "passive"))
      (node (ref "IC184") (pin "1") (pinfunction "1_1") (pintype "passive"))
    )
    (net (code "1083") (name "Net-(IC181-Pad2)") (class "Default")
      (node (ref "IC181") (pin "2") (pinfunction "2_2") (pintype "passive"))
      (node (ref "IC182") (pin "2") (pinfunction "2_2") (pintype "passive"))
      (node (ref "IC183") (pin "2") (pinfunction "2_2") (pintype "passive"))
      (node (ref "IC184") (pin "2") (pinfunction "2_2") (pintype "passive"))
    )
    (net (code "1084") (name "Net-(IC181-Pad3)") (class "Default")
      (node (ref "IC181") (pin "3") (pinfunction "3_3") (pintype "passive"))
      (node (ref "IC182") (pin "3") (pinfunction "3_3") (pintype "passive"))
      (node (ref "IC183") (pin "3") (pinfunction "3_3") (pintype "passive"))
      (node (ref "IC184") (pin "3") (pinfunction "3_3") (pintype "passive"))
    )
    (net (code "1085") (name "Net-(IC181-Pad4)") (class "Default")
      (node (ref "IC181") (pin "4") (pinfunction "4_4") (pintype "passive"))
      (node (ref "IC182") (pin "4") (pinfunction "4_4") (pintype "passive"))
      (node (ref "IC183") (pin "4") (pinfunction "4_4") (pintype "passive"))
      (node (ref "IC184") (pin "4") (pinfunction "4_4") (pintype "passive"))
    )
    (net (code "1086") (name "Net-(IC181-Pad5)") (class "Default")
      (node (ref "IC181") (pin "5") (pinfunction "5_5") (pintype "passive"))
      (node (ref "IC182") (pin "5") (pinfunction "5_5") (pintype "passive"))
      (node (ref "IC183") (pin "5") (pinfunction "5_5") (pintype "passive"))
      (node (ref "IC184") (pin "5") (pinfunction "5_5") (pintype "passive"))
    )
    (net (code "1087") (name "Net-(IC181-Pad6)") (class "Default")
      (node (ref "IC181") (pin "6") (pinfunction "6_6") (pintype "passive"))
      (node (ref "IC182") (pin "6") (pinfunction "6_6") (pintype "passive"))
      (node (ref "IC183") (pin "6") (pinfunction "6_6") (pintype "passive"))
      (node (ref "IC184") (pin "6") (pinfunction "6_6") (pintype "passive"))
    )
    (net (code "1088") (name "Net-(IC181-Pad7)") (class "Default")
      (node (ref "IC181") (pin "7") (pinfunction "7_7") (pintype "passive"))
      (node (ref "IC182") (pin "7") (pinfunction "7_7") (pintype "passive"))
      (node (ref "IC183") (pin "7") (pinfunction "7_7") (pintype "passive"))
      (node (ref "IC184") (pin "7") (pinfunction "7_7") (pintype "passive"))
    )
    (net (code "1089") (name "Net-(IC181-Pad8)") (class "Default")
      (node (ref "IC181") (pin "8") (pinfunction "8_8") (pintype "passive"))
      (node (ref "IC182") (pin "8") (pinfunction "8_8") (pintype "passive"))
      (node (ref "IC183") (pin "8") (pinfunction "8_8") (pintype "passive"))
      (node (ref "IC184") (pin "8") (pinfunction "8_8") (pintype "passive"))
    )
    (net (code "1090") (name "Net-(IC181-Pad9)") (class "Default")
      (node (ref "IC181") (pin "9") (pinfunction "9_9") (pintype "passive"))
      (node (ref "IC182") (pin "9") (pinfunction "9_9") (pintype "passive"))
      (node (ref "IC183") (pin "9") (pinfunction "9_9") (pintype "passive"))
      (node (ref "IC184") (pin "9") (pinfunction "9_9") (pintype "passive"))
    )
    (net (code "1091") (name "Net-(IC181-Pad10)") (class "Default")
      (node (ref "IC181") (pin "10") (pinfunction "10_10") (pintype "passive"))
      (node (ref "IC182") (pin "10") (pinfunction "10_10") (pintype "passive"))
      (node (ref "IC183") (pin "10") (pinfunction "10_10") (pintype "passive"))
      (node (ref "IC184") (pin "10") (pinfunction "10_10") (pintype "passive"))
    )
    (net (code "1092") (name "Net-(IC181-Pad11)") (class "Default")
      (node (ref "IC181") (pin "11") (pinfunction "11_11") (pintype "passive"))
      (node (ref "IC182") (pin "11") (pinfunction "11_11") (pintype "passive"))
      (node (ref "IC183") (pin "11") (pinfunction "11_11") (pintype "passive"))
      (node (ref "IC184") (pin "11") (pinfunction "11_11") (pintype "passive"))
    )
    (net (code "1093") (name "Net-(IC181-Pad12)") (class "Default")
      (node (ref "IC181") (pin "12") (pinfunction "12_12") (pintype "passive"))
      (node (ref "IC182") (pin "12") (pinfunction "12_12") (pintype "passive"))
      (node (ref "IC183") (pin "12") (pinfunction "12_12") (pintype "passive"))
      (node (ref "IC184") (pin "12") (pinfunction "12_12") (pintype "passive"))
    )
    (net (code "1094") (name "Net-(IC181-Pad13)") (class "Default")
      (node (ref "IC181") (pin "13") (pinfunction "13_13") (pintype "passive"))
      (node (ref "IC182") (pin "13") (pinfunction "13_13") (pintype "passive"))
      (node (ref "IC183") (pin "13") (pinfunction "13_13") (pintype "passive"))
      (node (ref "IC184") (pin "13") (pinfunction "13_13") (pintype "passive"))
    )
    (net (code "1095") (name "Net-(IC181-Pad14)") (class "Default")
      (node (ref "IC181") (pin "14") (pinfunction "14_14") (pintype "passive"))
      (node (ref "IC182") (pin "14") (pinfunction "14_14") (pintype "passive"))
      (node (ref "IC183") (pin "14") (pinfunction "14_14") (pintype "passive"))
      (node (ref "IC184") (pin "14") (pinfunction "14_14") (pintype "passive"))
    )
    (net (code "1096") (name "Net-(IC181-Pad15)") (class "Default")
      (node (ref "IC181") (pin "15") (pinfunction "15_15") (pintype "passive"))
      (node (ref "IC182") (pin "15") (pinfunction "15_15") (pintype "passive"))
      (node (ref "IC183") (pin "15") (pinfunction "15_15") (pintype "passive"))
      (node (ref "IC184") (pin "15") (pinfunction "15_15") (pintype "passive"))
    )
    (net (code "1097") (name "Net-(IC181-Pad16)") (class "Default")
      (node (ref "IC181") (pin "16") (pinfunction "16_16") (pintype "passive"))
      (node (ref "IC182") (pin "16") (pinfunction "16_16") (pintype "passive"))
      (node (ref "IC183") (pin "16") (pinfunction "16_16") (pintype "passive"))
      (node (ref "IC184") (pin "16") (pinfunction "16_16") (pintype "passive"))
    )
    (net (code "1098") (name "Net-(IC181-Pad17)") (class "Default")
      (node (ref "IC181") (pin "17") (pinfunction "17_17") (pintype "passive"))
      (node (ref "IC182") (pin "17") (pinfunction "17_17") (pintype "passive"))
      (node (ref "IC183") (pin "17") (pinfunction "17_17") (pintype "passive"))
      (node (ref "IC184") (pin "17") (pinfunction "17_17") (pintype "passive"))
    )
    (net (code "1099") (name "Net-(IC181-Pad18)") (class "Default")
      (node (ref "IC181") (pin "18") (pinfunction "18_18") (pintype "passive"))
      (node (ref "IC182") (pin "18") (pinfunction "18_18") (pintype "passive"))
      (node (ref "IC183") (pin "18") (pinfunction "18_18") (pintype "passive"))
      (node (ref "IC184") (pin "18") (pinfunction "18_18") (pintype "passive"))
    )
    (net (code "1100") (name "Net-(IC181-Pad19)") (class "Default")
      (node (ref "IC181") (pin "19") (pinfunction "19_19") (pintype "passive"))
      (node (ref "IC182") (pin "19") (pinfunction "19_19") (pintype "passive"))
      (node (ref "IC183") (pin "19") (pinfunction "19_19") (pintype "passive"))
      (node (ref "IC184") (pin "19") (pinfunction "19_19") (pintype "passive"))
    )
    (net (code "1101") (name "Net-(IC181-Pad20)") (class "Default")
      (node (ref "IC181") (pin "20") (pinfunction "20_20") (pintype "passive"))
      (node (ref "IC182") (pin "20") (pinfunction "20_20") (pintype "passive"))
      (node (ref "IC183") (pin "20") (pinfunction "20_20") (pintype "passive"))
      (node (ref "IC184") (pin "20") (pinfunction "20_20") (pintype "passive"))
    )
    (net (code "1102") (name "Net-(IC181-Pad21)") (class "Default")
      (node (ref "IC181") (pin "21") (pinfunction "21_21") (pintype "passive"))
      (node (ref "IC182") (pin "21") (pinfunction "21_21") (pintype "passive"))
      (node (ref "IC183") (pin "21") (pinfunction "21_21") (pintype "passive"))
      (node (ref "IC184") (pin "21") (pinfunction "21_21") (pintype "passive"))
    )
    (net (code "1103") (name "Net-(IC181-Pad22)") (class "Default")
      (node (ref "IC181") (pin "22") (pinfunction "22_22") (pintype "passive"))
      (node (ref "IC182") (pin "22") (pinfunction "22_22") (pintype "passive"))
      (node (ref "IC183") (pin "22") (pinfunction "22_22") (pintype "passive"))
      (node (ref "IC184") (pin "22") (pinfunction "22_22") (pintype "passive"))
    )
    (net (code "1104") (name "Net-(IC181-Pad23)") (class "Default")
      (node (ref "IC181") (pin "23") (pinfunction "23_23") (pintype "passive"))
      (node (ref "IC182") (pin "23") (pinfunction "23_23") (pintype "passive"))
      (node (ref "IC183") (pin "23") (pinfunction "23_23") (pintype "passive"))
      (node (ref "IC184") (pin "23") (pinfunction "23_23") (pintype "passive"))
    )
    (net (code "1105") (name "Net-(IC181-Pad24)") (class "Default")
      (node (ref "IC181") (pin "24") (pinfunction "24_24") (pintype "passive"))
      (node (ref "IC182") (pin "24") (pinfunction "24_24") (pintype "passive"))
      (node (ref "IC183") (pin "24") (pinfunction "24_24") (pintype "passive"))
      (node (ref "IC184") (pin "24") (pinfunction "24_24") (pintype "passive"))
    )
    (net (code "1106") (name "Net-(IC185-Pad1)") (class "Default")
      (node (ref "IC185") (pin "1") (pinfunction "1_1") (pintype "passive"))
      (node (ref "IC186") (pin "1") (pinfunction "1_1") (pintype "passive"))
      (node (ref "IC187") (pin "1") (pinfunction "1_1") (pintype "passive"))
      (node (ref "IC188") (pin "1") (pinfunction "1_1") (pintype "passive"))
    )
    (net (code "1107") (name "Net-(IC185-Pad2)") (class "Default")
      (node (ref "IC185") (pin "2") (pinfunction "2_2") (pintype "passive"))
      (node (ref "IC186") (pin "2") (pinfunction "2_2") (pintype "passive"))
      (node (ref "IC187") (pin "2") (pinfunction "2_2") (pintype "passive"))
      (node (ref "IC188") (pin "2") (pinfunction "2_2") (pintype "passive"))
    )
    (net (code "1108") (name "Net-(IC185-Pad3)") (class "Default")
      (node (ref "IC185") (pin "3") (pinfunction "3_3") (pintype "passive"))
      (node (ref "IC186") (pin "3") (pinfunction "3_3") (pintype "passive"))
      (node (ref "IC187") (pin "3") (pinfunction "3_3") (pintype "passive"))
      (node (ref "IC188") (pin "3") (pinfunction "3_3") (pintype "passive"))
    )
    (net (code "1109") (name "Net-(IC185-Pad4)") (class "Default")
      (node (ref "IC185") (pin "4") (pinfunction "4_4") (pintype "passive"))
      (node (ref "IC186") (pin "4") (pinfunction "4_4") (pintype "passive"))
      (node (ref "IC187") (pin "4") (pinfunction "4_4") (pintype "passive"))
      (node (ref "IC188") (pin "4") (pinfunction "4_4") (pintype "passive"))
    )
    (net (code "1110") (name "Net-(IC185-Pad5)") (class "Default")
      (node (ref "IC185") (pin "5") (pinfunction "5_5") (pintype "passive"))
      (node (ref "IC186") (pin "5") (pinfunction "5_5") (pintype "passive"))
      (node (ref "IC187") (pin "5") (pinfunction "5_5") (pintype "passive"))
      (node (ref "IC188") (pin "5") (pinfunction "5_5") (pintype "passive"))
    )
    (net (code "1111") (name "Net-(IC185-Pad6)") (class "Default")
      (node (ref "IC185") (pin "6") (pinfunction "6_6") (pintype "passive"))
      (node (ref "IC186") (pin "6") (pinfunction "6_6") (pintype "passive"))
      (node (ref "IC187") (pin "6") (pinfunction "6_6") (pintype "passive"))
      (node (ref "IC188") (pin "6") (pinfunction "6_6") (pintype "passive"))
    )
    (net (code "1112") (name "Net-(IC185-Pad7)") (class "Default")
      (node (ref "IC185") (pin "7") (pinfunction "7_7") (pintype "passive"))
      (node (ref "IC186") (pin "7") (pinfunction "7_7") (pintype "passive"))
      (node (ref "IC187") (pin "7") (pinfunction "7_7") (pintype "passive"))
      (node (ref "IC188") (pin "7") (pinfunction "7_7") (pintype "passive"))
    )
    (net (code "1113") (name "Net-(IC185-Pad8)") (class "Default")
      (node (ref "IC185") (pin "8") (pinfunction "8_8") (pintype "passive"))
      (node (ref "IC186") (pin "8") (pinfunction "8_8") (pintype "passive"))
      (node (ref "IC187") (pin "8") (pinfunction "8_8") (pintype "passive"))
      (node (ref "IC188") (pin "8") (pinfunction "8_8") (pintype "passive"))
    )
    (net (code "1114") (name "Net-(IC185-Pad9)") (class "Default")
      (node (ref "IC185") (pin "9") (pinfunction "9_9") (pintype "passive"))
      (node (ref "IC186") (pin "9") (pinfunction "9_9") (pintype "passive"))
      (node (ref "IC187") (pin "9") (pinfunction "9_9") (pintype "passive"))
      (node (ref "IC188") (pin "9") (pinfunction "9_9") (pintype "passive"))
    )
    (net (code "1115") (name "Net-(IC185-Pad10)") (class "Default")
      (node (ref "IC185") (pin "10") (pinfunction "10_10") (pintype "passive"))
      (node (ref "IC186") (pin "10") (pinfunction "10_10") (pintype "passive"))
      (node (ref "IC187") (pin "10") (pinfunction "10_10") (pintype "passive"))
      (node (ref "IC188") (pin "10") (pinfunction "10_10") (pintype "passive"))
    )
    (net (code "1116") (name "Net-(IC185-Pad11)") (class "Default")
      (node (ref "IC185") (pin "11") (pinfunction "11_11") (pintype "passive"))
      (node (ref "IC186") (pin "11") (pinfunction "11_11") (pintype "passive"))
      (node (ref "IC187") (pin "11") (pinfunction "11_11") (pintype "passive"))
      (node (ref "IC188") (pin "11") (pinfunction "11_11") (pintype "passive"))
    )
    (net (code "1117") (name "Net-(IC185-Pad12)") (class "Default")
      (node (ref "IC185") (pin "12") (pinfunction "12_12") (pintype "passive"))
      (node (ref "IC186") (pin "12") (pinfunction "12_12") (pintype "passive"))
      (node (ref "IC187") (pin "12") (pinfunction "12_12") (pintype "passive"))
      (node (ref "IC188") (pin "12") (pinfunction "12_12") (pintype "passive"))
    )
    (net (code "1118") (name "Net-(IC185-Pad13)") (class "Default")
      (node (ref "IC185") (pin "13") (pinfunction "13_13") (pintype "passive"))
      (node (ref "IC186") (pin "13") (pinfunction "13_13") (pintype "passive"))
      (node (ref "IC187") (pin "13") (pinfunction "13_13") (pintype "passive"))
      (node (ref "IC188") (pin "13") (pinfunction "13_13") (pintype "passive"))
    )
    (net (code "1119") (name "Net-(IC185-Pad14)") (class "Default")
      (node (ref "IC185") (pin "14") (pinfunction "14_14") (pintype "passive"))
      (node (ref "IC186") (pin "14") (pinfunction "14_14") (pintype "passive"))
      (node (ref "IC187") (pin "14") (pinfunction "14_14") (pintype "passive"))
      (node (ref "IC188") (pin "14") (pinfunction "14_14") (pintype "passive"))
    )
    (net (code "1120") (name "Net-(IC185-Pad15)") (class "Default")
      (node (ref "IC185") (pin "15") (pinfunction "15_15") (pintype "passive"))
      (node (ref "IC186") (pin "15") (pinfunction "15_15") (pintype "passive"))
      (node (ref "IC187") (pin "15") (pinfunction "15_15") (pintype "passive"))
      (node (ref "IC188") (pin "15") (pinfunction "15_15") (pintype "passive"))
    )
    (net (code "1121") (name "Net-(IC185-Pad16)") (class "Default")
      (node (ref "IC185") (pin "16") (pinfunction "16_16") (pintype "passive"))
      (node (ref "IC186") (pin "16") (pinfunction "16_16") (pintype "passive"))
      (node (ref "IC187") (pin "16") (pinfunction "16_16") (pintype "passive"))
      (node (ref "IC188") (pin "16") (pinfunction "16_16") (pintype "passive"))
    )
    (net (code "1122") (name "Net-(IC185-Pad17)") (class "Default")
      (node (ref "IC185") (pin "17") (pinfunction "17_17") (pintype "passive"))
      (node (ref "IC186") (pin "17") (pinfunction "17_17") (pintype "passive"))
      (node (ref "IC187") (pin "17") (pinfunction "17_17") (pintype "passive"))
      (node (ref "IC188") (pin "17") (pinfunction "17_17") (pintype "passive"))
    )
    (net (code "1123") (name "Net-(IC185-Pad18)") (class "Default")
      (node (ref "IC185") (pin "18") (pinfunction "18_18") (pintype "passive"))
      (node (ref "IC186") (pin "18") (pinfunction "18_18") (pintype "passive"))
      (node (ref "IC187") (pin "18") (pinfunction "18_18") (pintype "passive"))
      (node (ref "IC188") (pin "18") (pinfunction "18_18") (pintype "passive"))
    )
    (net (code "1124") (name "Net-(IC185-Pad19)") (class "Default")
      (node (ref "IC185") (pin "19") (pinfunction "19_19") (pintype "passive"))
      (node (ref "IC186") (pin "19") (pinfunction "19_19") (pintype "passive"))
      (node (ref "IC187") (pin "19") (pinfunction "19_19") (pintype "passive"))
      (node (ref "IC188") (pin "19") (pinfunction "19_19") (pintype "passive"))
    )
    (net (code "1125") (name "Net-(IC185-Pad20)") (class "Default")
      (node (ref "IC185") (pin "20") (pinfunction "20_20") (pintype "passive"))
      (node (ref "IC186") (pin "20") (pinfunction "20_20") (pintype "passive"))
      (node (ref "IC187") (pin "20") (pinfunction "20_20") (pintype "passive"))
      (node (ref "IC188") (pin "20") (pinfunction "20_20") (pintype "passive"))
    )
    (net (code "1126") (name "Net-(IC185-Pad21)") (class "Default")
      (node (ref "IC185") (pin "21") (pinfunction "21_21") (pintype "passive"))
      (node (ref "IC186") (pin "21") (pinfunction "21_21") (pintype "passive"))
      (node (ref "IC187") (pin "21") (pinfunction "21_21") (pintype "passive"))
      (node (ref "IC188") (pin "21") (pinfunction "21_21") (pintype "passive"))
    )
    (net (code "1127") (name "Net-(IC185-Pad22)") (class "Default")
      (node (ref "IC185") (pin "22") (pinfunction "22_22") (pintype "passive"))
      (node (ref "IC186") (pin "22") (pinfunction "22_22") (pintype "passive"))
      (node (ref "IC187") (pin "22") (pinfunction "22_22") (pintype "passive"))
      (node (ref "IC188") (pin "22") (pinfunction "22_22") (pintype "passive"))
    )
    (net (code "1128") (name "Net-(IC185-Pad23)") (class "Default")
      (node (ref "IC185") (pin "23") (pinfunction "23_23") (pintype "passive"))
      (node (ref "IC186") (pin "23") (pinfunction "23_23") (pintype "passive"))
      (node (ref "IC187") (pin "23") (pinfunction "23_23") (pintype "passive"))
      (node (ref "IC188") (pin "23") (pinfunction "23_23") (pintype "passive"))
    )
    (net (code "1129") (name "Net-(IC185-Pad24)") (class "Default")
      (node (ref "IC185") (pin "24") (pinfunction "24_24") (pintype "passive"))
      (node (ref "IC186") (pin "24") (pinfunction "24_24") (pintype "passive"))
      (node (ref "IC187") (pin "24") (pinfunction "24_24") (pintype "passive"))
      (node (ref "IC188") (pin "24") (pinfunction "24_24") (pintype "passive"))
    )
    (net (code "1130") (name "Net-(IC189-Pad1)") (class "Default")
      (node (ref "IC189") (pin "1") (pinfunction "1_1") (pintype "passive"))
      (node (ref "IC190") (pin "1") (pinfunction "1_1") (pintype "passive"))
      (node (ref "IC191") (pin "1") (pinfunction "1_1") (pintype "passive"))
      (node (ref "IC192") (pin "1") (pinfunction "1_1") (pintype "passive"))
    )
    (net (code "1131") (name "Net-(IC189-Pad2)") (class "Default")
      (node (ref "IC189") (pin "2") (pinfunction "2_2") (pintype "passive"))
      (node (ref "IC190") (pin "2") (pinfunction "2_2") (pintype "passive"))
      (node (ref "IC191") (pin "2") (pinfunction "2_2") (pintype "passive"))
      (node (ref "IC192") (pin "2") (pinfunction "2_2") (pintype "passive"))
    )
    (net (code "1132") (name "Net-(IC189-Pad3)") (class "Default")
      (node (ref "IC189") (pin "3") (pinfunction "3_3") (pintype "passive"))
      (node (ref "IC190") (pin "3") (pinfunction "3_3") (pintype "passive"))
      (node (ref "IC191") (pin "3") (pinfunction "3_3") (pintype "passive"))
      (node (ref "IC192") (pin "3") (pinfunction "3_3") (pintype "passive"))
    )
    (net (code "1133") (name "Net-(IC189-Pad4)") (class "Default")
      (node (ref "IC189") (pin "4") (pinfunction "4_4") (pintype "passive"))
      (node (ref "IC190") (pin "4") (pinfunction "4_4") (pintype "passive"))
      (node (ref "IC191") (pin "4") (pinfunction "4_4") (pintype "passive"))
      (node (ref "IC192") (pin "4") (pinfunction "4_4") (pintype "passive"))
    )
    (net (code "1134") (name "Net-(IC189-Pad5)") (class "Default")
      (node (ref "IC189") (pin "5") (pinfunction "5_5") (pintype "passive"))
      (node (ref "IC190") (pin "5") (pinfunction "5_5") (pintype "passive"))
      (node (ref "IC191") (pin "5") (pinfunction "5_5") (pintype "passive"))
      (node (ref "IC192") (pin "5") (pinfunction "5_5") (pintype "passive"))
    )
    (net (code "1135") (name "Net-(IC189-Pad6)") (class "Default")
      (node (ref "IC189") (pin "6") (pinfunction "6_6") (pintype "passive"))
      (node (ref "IC190") (pin "6") (pinfunction "6_6") (pintype "passive"))
      (node (ref "IC191") (pin "6") (pinfunction "6_6") (pintype "passive"))
      (node (ref "IC192") (pin "6") (pinfunction "6_6") (pintype "passive"))
    )
    (net (code "1136") (name "Net-(IC189-Pad7)") (class "Default")
      (node (ref "IC189") (pin "7") (pinfunction "7_7") (pintype "passive"))
      (node (ref "IC190") (pin "7") (pinfunction "7_7") (pintype "passive"))
      (node (ref "IC191") (pin "7") (pinfunction "7_7") (pintype "passive"))
      (node (ref "IC192") (pin "7") (pinfunction "7_7") (pintype "passive"))
    )
    (net (code "1137") (name "Net-(IC189-Pad8)") (class "Default")
      (node (ref "IC189") (pin "8") (pinfunction "8_8") (pintype "passive"))
      (node (ref "IC190") (pin "8") (pinfunction "8_8") (pintype "passive"))
      (node (ref "IC191") (pin "8") (pinfunction "8_8") (pintype "passive"))
      (node (ref "IC192") (pin "8") (pinfunction "8_8") (pintype "passive"))
    )
    (net (code "1138") (name "Net-(IC189-Pad9)") (class "Default")
      (node (ref "IC189") (pin "9") (pinfunction "9_9") (pintype "passive"))
      (node (ref "IC190") (pin "9") (pinfunction "9_9") (pintype "passive"))
      (node (ref "IC191") (pin "9") (pinfunction "9_9") (pintype "passive"))
      (node (ref "IC192") (pin "9") (pinfunction "9_9") (pintype "passive"))
    )
    (net (code "1139") (name "Net-(IC189-Pad10)") (class "Default")
      (node (ref "IC189") (pin "10") (pinfunction "10_10") (pintype "passive"))
      (node (ref "IC190") (pin "10") (pinfunction "10_10") (pintype "passive"))
      (node (ref "IC191") (pin "10") (pinfunction "10_10") (pintype "passive"))
      (node (ref "IC192") (pin "10") (pinfunction "10_10") (pintype "passive"))
    )
    (net (code "1140") (name "Net-(IC189-Pad11)") (class "Default")
      (node (ref "IC189") (pin "11") (pinfunction "11_11") (pintype "passive"))
      (node (ref "IC190") (pin "11") (pinfunction "11_11") (pintype "passive"))
      (node (ref "IC191") (pin "11") (pinfunction "11_11") (pintype "passive"))
      (node (ref "IC192") (pin "11") (pinfunction "11_11") (pintype "passive"))
    )
    (net (code "1141") (name "Net-(IC189-Pad12)") (class "Default")
      (node (ref "IC189") (pin "12") (pinfunction "12_12") (pintype "passive"))
      (node (ref "IC190") (pin "12") (pinfunction "12_12") (pintype "passive"))
      (node (ref "IC191") (pin "12") (pinfunction "12_12") (pintype "passive"))
      (node (ref "IC192") (pin "12") (pinfunction "12_12") (pintype "passive"))
    )
    (net (code "1142") (name "Net-(IC189-Pad13)") (class "Default")
      (node (ref "IC189") (pin "13") (pinfunction "13_13") (pintype "passive"))
      (node (ref "IC190") (pin "13") (pinfunction "13_13") (pintype "passive"))
      (node (ref "IC191") (pin "13") (pinfunction "13_13") (pintype "passive"))
      (node (ref "IC192") (pin "13") (pinfunction "13_13") (pintype "passive"))
    )
    (net (code "1143") (name "Net-(IC189-Pad14)") (class "Default")
      (node (ref "IC189") (pin "14") (pinfunction "14_14") (pintype "passive"))
      (node (ref "IC190") (pin "14") (pinfunction "14_14") (pintype "passive"))
      (node (ref "IC191") (pin "14") (pinfunction "14_14") (pintype "passive"))
      (node (ref "IC192") (pin "14") (pinfunction "14_14") (pintype "passive"))
    )
    (net (code "1144") (name "Net-(IC189-Pad15)") (class "Default")
      (node (ref "IC189") (pin "15") (pinfunction "15_15") (pintype "passive"))
      (node (ref "IC190") (pin "15") (pinfunction "15_15") (pintype "passive"))
      (node (ref "IC191") (pin "15") (pinfunction "15_15") (pintype "passive"))
      (node (ref "IC192") (pin "15") (pinfunction "15_15") (pintype "passive"))
    )
    (net (code "1145") (name "Net-(IC189-Pad16)") (class "Default")
      (node (ref "IC189") (pin "16") (pinfunction "16_16") (pintype "passive"))
      (node (ref "IC190") (pin "16") (pinfunction "16_16") (pintype "passive"))
      (node (ref "IC191") (pin "16") (pinfunction "16_16") (pintype "passive"))
      (node (ref "IC192") (pin "16") (pinfunction "16_16") (pintype "passive"))
    )
    (net (code "1146") (name "Net-(IC189-Pad17)") (class "Default")
      (node (ref "IC189") (pin "17") (pinfunction "17_17") (pintype "passive"))
      (node (ref "IC190") (pin "17") (pinfunction "17_17") (pintype "passive"))
      (node (ref "IC191") (pin "17") (pinfunction "17_17") (pintype "passive"))
      (node (ref "IC192") (pin "17") (pinfunction "17_17") (pintype "passive"))
    )
    (net (code "1147") (name "Net-(IC189-Pad18)") (class "Default")
      (node (ref "IC189") (pin "18") (pinfunction "18_18") (pintype "passive"))
      (node (ref "IC190") (pin "18") (pinfunction "18_18") (pintype "passive"))
      (node (ref "IC191") (pin "18") (pinfunction "18_18") (pintype "passive"))
      (node (ref "IC192") (pin "18") (pinfunction "18_18") (pintype "passive"))
    )
    (net (code "1148") (name "Net-(IC189-Pad19)") (class "Default")
      (node (ref "IC189") (pin "19") (pinfunction "19_19") (pintype "passive"))
      (node (ref "IC190") (pin "19") (pinfunction "19_19") (pintype "passive"))
      (node (ref "IC191") (pin "19") (pinfunction "19_19") (pintype "passive"))
      (node (ref "IC192") (pin "19") (pinfunction "19_19") (pintype "passive"))
    )
    (net (code "1149") (name "Net-(IC189-Pad20)") (class "Default")
      (node (ref "IC189") (pin "20") (pinfunction "20_20") (pintype "passive"))
      (node (ref "IC190") (pin "20") (pinfunction "20_20") (pintype "passive"))
      (node (ref "IC191") (pin "20") (pinfunction "20_20") (pintype "passive"))
      (node (ref "IC192") (pin "20") (pinfunction "20_20") (pintype "passive"))
    )
    (net (code "1150") (name "Net-(IC189-Pad21)") (class "Default")
      (node (ref "IC189") (pin "21") (pinfunction "21_21") (pintype "passive"))
      (node (ref "IC190") (pin "21") (pinfunction "21_21") (pintype "passive"))
      (node (ref "IC191") (pin "21") (pinfunction "21_21") (pintype "passive"))
      (node (ref "IC192") (pin "21") (pinfunction "21_21") (pintype "passive"))
    )
    (net (code "1151") (name "Net-(IC189-Pad22)") (class "Default")
      (node (ref "IC189") (pin "22") (pinfunction "22_22") (pintype "passive"))
      (node (ref "IC190") (pin "22") (pinfunction "22_22") (pintype "passive"))
      (node (ref "IC191") (pin "22") (pinfunction "22_22") (pintype "passive"))
      (node (ref "IC192") (pin "22") (pinfunction "22_22") (pintype "passive"))
    )
    (net (code "1152") (name "Net-(IC189-Pad23)") (class "Default")
      (node (ref "IC189") (pin "23") (pinfunction "23_23") (pintype "passive"))
      (node (ref "IC190") (pin "23") (pinfunction "23_23") (pintype "passive"))
      (node (ref "IC191") (pin "23") (pinfunction "23_23") (pintype "passive"))
      (node (ref "IC192") (pin "23") (pinfunction "23_23") (pintype "passive"))
    )
    (net (code "1153") (name "Net-(IC189-Pad24)") (class "Default")
      (node (ref "IC189") (pin "24") (pinfunction "24_24") (pintype "passive"))
      (node (ref "IC190") (pin "24") (pinfunction "24_24") (pintype "passive"))
      (node (ref "IC191") (pin "24") (pinfunction "24_24") (pintype "passive"))
      (node (ref "IC192") (pin "24") (pinfunction "24_24") (pintype "passive"))
    )
    (net (code "1154") (name "Net-(IC193-Pad1)") (class "Default")
      (node (ref "IC193") (pin "1") (pinfunction "1_1") (pintype "passive"))
      (node (ref "IC194") (pin "1") (pinfunction "1_1") (pintype "passive"))
      (node (ref "IC195") (pin "1") (pinfunction "1_1") (pintype "passive"))
      (node (ref "IC196") (pin "1") (pinfunction "1_1") (pintype "passive"))
    )
    (net (code "1155") (name "Net-(IC193-Pad2)") (class "Default")
      (node (ref "IC193") (pin "2") (pinfunction "2_2") (pintype "passive"))
      (node (ref "IC194") (pin "2") (pinfunction "2_2") (pintype "passive"))
      (node (ref "IC195") (pin "2") (pinfunction "2_2") (pintype "passive"))
      (node (ref "IC196") (pin "2") (pinfunction "2_2") (pintype "passive"))
    )
    (net (code "1156") (name "Net-(IC193-Pad3)") (class "Default")
      (node (ref "IC193") (pin "3") (pinfunction "3_3") (pintype "passive"))
      (node (ref "IC194") (pin "3") (pinfunction "3_3") (pintype "passive"))
      (node (ref "IC195") (pin "3") (pinfunction "3_3") (pintype "passive"))
      (node (ref "IC196") (pin "3") (pinfunction "3_3") (pintype "passive"))
    )
    (net (code "1157") (name "Net-(IC193-Pad4)") (class "Default")
      (node (ref "IC193") (pin "4") (pinfunction "4_4") (pintype "passive"))
      (node (ref "IC194") (pin "4") (pinfunction "4_4") (pintype "passive"))
      (node (ref "IC195") (pin "4") (pinfunction "4_4") (pintype "passive"))
      (node (ref "IC196") (pin "4") (pinfunction "4_4") (pintype "passive"))
    )
    (net (code "1158") (name "Net-(IC193-Pad5)") (class "Default")
      (node (ref "IC193") (pin "5") (pinfunction "5_5") (pintype "passive"))
      (node (ref "IC194") (pin "5") (pinfunction "5_5") (pintype "passive"))
      (node (ref "IC195") (pin "5") (pinfunction "5_5") (pintype "passive"))
      (node (ref "IC196") (pin "5") (pinfunction "5_5") (pintype "passive"))
    )
    (net (code "1159") (name "Net-(IC193-Pad6)") (class "Default")
      (node (ref "IC193") (pin "6") (pinfunction "6_6") (pintype "passive"))
      (node (ref "IC194") (pin "6") (pinfunction "6_6") (pintype "passive"))
      (node (ref "IC195") (pin "6") (pinfunction "6_6") (pintype "passive"))
      (node (ref "IC196") (pin "6") (pinfunction "6_6") (pintype "passive"))
    )
    (net (code "1160") (name "Net-(IC193-Pad7)") (class "Default")
      (node (ref "IC193") (pin "7") (pinfunction "7_7") (pintype "passive"))
      (node (ref "IC194") (pin "7") (pinfunction "7_7") (pintype "passive"))
      (node (ref "IC195") (pin "7") (pinfunction "7_7") (pintype "passive"))
      (node (ref "IC196") (pin "7") (pinfunction "7_7") (pintype "passive"))
    )
    (net (code "1161") (name "Net-(IC193-Pad8)") (class "Default")
      (node (ref "IC193") (pin "8") (pinfunction "8_8") (pintype "passive"))
      (node (ref "IC194") (pin "8") (pinfunction "8_8") (pintype "passive"))
      (node (ref "IC195") (pin "8") (pinfunction "8_8") (pintype "passive"))
      (node (ref "IC196") (pin "8") (pinfunction "8_8") (pintype "passive"))
    )
    (net (code "1162") (name "Net-(IC193-Pad9)") (class "Default")
      (node (ref "IC193") (pin "9") (pinfunction "9_9") (pintype "passive"))
      (node (ref "IC194") (pin "9") (pinfunction "9_9") (pintype "passive"))
      (node (ref "IC195") (pin "9") (pinfunction "9_9") (pintype "passive"))
      (node (ref "IC196") (pin "9") (pinfunction "9_9") (pintype "passive"))
    )
    (net (code "1163") (name "Net-(IC193-Pad10)") (class "Default")
      (node (ref "IC193") (pin "10") (pinfunction "10_10") (pintype "passive"))
      (node (ref "IC194") (pin "10") (pinfunction "10_10") (pintype "passive"))
      (node (ref "IC195") (pin "10") (pinfunction "10_10") (pintype "passive"))
      (node (ref "IC196") (pin "10") (pinfunction "10_10") (pintype "passive"))
    )
    (net (code "1164") (name "Net-(IC193-Pad11)") (class "Default")
      (node (ref "IC193") (pin "11") (pinfunction "11_11") (pintype "passive"))
      (node (ref "IC194") (pin "11") (pinfunction "11_11") (pintype "passive"))
      (node (ref "IC195") (pin "11") (pinfunction "11_11") (pintype "passive"))
      (node (ref "IC196") (pin "11") (pinfunction "11_11") (pintype "passive"))
    )
    (net (code "1165") (name "Net-(IC193-Pad12)") (class "Default")
      (node (ref "IC193") (pin "12") (pinfunction "12_12") (pintype "passive"))
      (node (ref "IC194") (pin "12") (pinfunction "12_12") (pintype "passive"))
      (node (ref "IC195") (pin "12") (pinfunction "12_12") (pintype "passive"))
      (node (ref "IC196") (pin "12") (pinfunction "12_12") (pintype "passive"))
    )
    (net (code "1166") (name "Net-(IC193-Pad13)") (class "Default")
      (node (ref "IC193") (pin "13") (pinfunction "13_13") (pintype "passive"))
      (node (ref "IC194") (pin "13") (pinfunction "13_13") (pintype "passive"))
      (node (ref "IC195") (pin "13") (pinfunction "13_13") (pintype "passive"))
      (node (ref "IC196") (pin "13") (pinfunction "13_13") (pintype "passive"))
    )
    (net (code "1167") (name "Net-(IC193-Pad14)") (class "Default")
      (node (ref "IC193") (pin "14") (pinfunction "14_14") (pintype "passive"))
      (node (ref "IC194") (pin "14") (pinfunction "14_14") (pintype "passive"))
      (node (ref "IC195") (pin "14") (pinfunction "14_14") (pintype "passive"))
      (node (ref "IC196") (pin "14") (pinfunction "14_14") (pintype "passive"))
    )
    (net (code "1168") (name "Net-(IC193-Pad15)") (class "Default")
      (node (ref "IC193") (pin "15") (pinfunction "15_15") (pintype "passive"))
      (node (ref "IC194") (pin "15") (pinfunction "15_15") (pintype "passive"))
      (node (ref "IC195") (pin "15") (pinfunction "15_15") (pintype "passive"))
      (node (ref "IC196") (pin "15") (pinfunction "15_15") (pintype "passive"))
    )
    (net (code "1169") (name "Net-(IC193-Pad16)") (class "Default")
      (node (ref "IC193") (pin "16") (pinfunction "16_16") (pintype "passive"))
      (node (ref "IC194") (pin "16") (pinfunction "16_16") (pintype "passive"))
      (node (ref "IC195") (pin "16") (pinfunction "16_16") (pintype "passive"))
      (node (ref "IC196") (pin "16") (pinfunction "16_16") (pintype "passive"))
    )
    (net (code "1170") (name "Net-(IC193-Pad17)") (class "Default")
      (node (ref "IC193") (pin "17") (pinfunction "17_17") (pintype "passive"))
      (node (ref "IC194") (pin "17") (pinfunction "17_17") (pintype "passive"))
      (node (ref "IC195") (pin "17") (pinfunction "17_17") (pintype "passive"))
      (node (ref "IC196") (pin "17") (pinfunction "17_17") (pintype "passive"))
    )
    (net (code "1171") (name "Net-(IC193-Pad18)") (class "Default")
      (node (ref "IC193") (pin "18") (pinfunction "18_18") (pintype "passive"))
      (node (ref "IC194") (pin "18") (pinfunction "18_18") (pintype "passive"))
      (node (ref "IC195") (pin "18") (pinfunction "18_18") (pintype "passive"))
      (node (ref "IC196") (pin "18") (pinfunction "18_18") (pintype "passive"))
    )
    (net (code "1172") (name "Net-(IC193-Pad19)") (class "Default")
      (node (ref "IC193") (pin "19") (pinfunction "19_19") (pintype "passive"))
      (node (ref "IC194") (pin "19") (pinfunction "19_19") (pintype "passive"))
      (node (ref "IC195") (pin "19") (pinfunction "19_19") (pintype "passive"))
      (node (ref "IC196") (pin "19") (pinfunction "19_19") (pintype "passive"))
    )
    (net (code "1173") (name "Net-(IC193-Pad20)") (class "Default")
      (node (ref "IC193") (pin "20") (pinfunction "20_20") (pintype "passive"))
      (node (ref "IC194") (pin "20") (pinfunction "20_20") (pintype "passive"))
      (node (ref "IC195") (pin "20") (pinfunction "20_20") (pintype "passive"))
      (node (ref "IC196") (pin "20") (pinfunction "20_20") (pintype "passive"))
    )
    (net (code "1174") (name "Net-(IC193-Pad21)") (class "Default")
      (node (ref "IC193") (pin "21") (pinfunction "21_21") (pintype "passive"))
      (node (ref "IC194") (pin "21") (pinfunction "21_21") (pintype "passive"))
      (node (ref "IC195") (pin "21") (pinfunction "21_21") (pintype "passive"))
      (node (ref "IC196") (pin "21") (pinfunction "21_21") (pintype "passive"))
    )
    (net (code "1175") (name "Net-(IC193-Pad22)") (class "Default")
      (node (ref "IC193") (pin "22") (pinfunction "22_22") (pintype "passive"))
      (node (ref "IC194") (pin "22") (pinfunction "22_22") (pintype "passive"))
      (node (ref "IC195") (pin "22") (pinfunction "22_22") (pintype "passive"))
      (node (ref "IC196") (pin "22") (pinfunction "22_22") (pintype "passive"))
    )
    (net (code "1176") (name "Net-(IC193-Pad23)") (class "Default")
      (node (ref "IC193") (pin "23") (pinfunction "23_23") (pintype "passive"))
      (node (ref "IC194") (pin "23") (pinfunction "23_23") (pintype "passive"))
      (node (ref "IC195") (pin "23") (pinfunction "23_23") (pintype "passive"))
      (node (ref "IC196") (pin "23") (pinfunction "23_23") (pintype "passive"))
    )
    (net (code "1177") (name "Net-(IC193-Pad24)") (class "Default")
      (node (ref "IC193") (pin "24") (pinfunction "24_24") (pintype "passive"))
      (node (ref "IC194") (pin "24") (pinfunction "24_24") (pintype "passive"))
      (node (ref "IC195") (pin "24") (pinfunction "24_24") (pintype "passive"))
      (node (ref "IC196") (pin "24") (pinfunction "24_24") (pintype "passive"))
    )
    (net (code "1178") (name "Net-(IC197-Pad1)") (class "Default")
      (node (ref "IC197") (pin "1") (pinfunction "1_1") (pintype "passive"))
      (node (ref "IC198") (pin "1") (pinfunction "1_1") (pintype "passive"))
      (node (ref "IC199") (pin "1") (pinfunction "1_1") (pintype "passive"))
      (node (ref "IC200") (pin "1") (pinfunction "1_1") (pintype "passive"))
    )
    (net (code "1179") (name "Net-(IC197-Pad2)") (class "Default")
      (node (ref "IC197") (pin "2") (pinfunction "2_2") (pintype "passive"))
      (node (ref "IC198") (pin "2") (pinfunction "2_2") (pintype "passive"))
      (node (ref "IC199") (pin "2") (pinfunction "2_2") (pintype "passive"))
      (node (ref "IC200") (pin "2") (pinfunction "2_2") (pintype "passive"))
    )
    (net (code "1180") (name "Net-(IC197-Pad3)") (class "Default")
      (node (ref "IC197") (pin "3") (pinfunction "3_3") (pintype "passive"))
      (node (ref "IC198") (pin "3") (pinfunction "3_3") (pintype "passive"))
      (node (ref "IC199") (pin "3") (pinfunction "3_3") (pintype "passive"))
      (node (ref "IC200") (pin "3") (pinfunction "3_3") (pintype "passive"))
    )
    (net (code "1181") (name "Net-(IC197-Pad4)") (class "Default")
      (node (ref "IC197") (pin "4") (pinfunction "4_4") (pintype "passive"))
      (node (ref "IC198") (pin "4") (pinfunction "4_4") (pintype "passive"))
      (node (ref "IC199") (pin "4") (pinfunction "4_4") (pintype "passive"))
      (node (ref "IC200") (pin "4") (pinfunction "4_4") (pintype "passive"))
    )
    (net (code "1182") (name "Net-(IC197-Pad5)") (class "Default")
      (node (ref "IC197") (pin "5") (pinfunction "5_5") (pintype "passive"))
      (node (ref "IC198") (pin "5") (pinfunction "5_5") (pintype "passive"))
      (node (ref "IC199") (pin "5") (pinfunction "5_5") (pintype "passive"))
      (node (ref "IC200") (pin "5") (pinfunction "5_5") (pintype "passive"))
    )
    (net (code "1183") (name "Net-(IC197-Pad6)") (class "Default")
      (node (ref "IC197") (pin "6") (pinfunction "6_6") (pintype "passive"))
      (node (ref "IC198") (pin "6") (pinfunction "6_6") (pintype "passive"))
      (node (ref "IC199") (pin "6") (pinfunction "6_6") (pintype "passive"))
      (node (ref "IC200") (pin "6") (pinfunction "6_6") (pintype "passive"))
    )
    (net (code "1184") (name "Net-(IC197-Pad7)") (class "Default")
      (node (ref "IC197") (pin "7") (pinfunction "7_7") (pintype "passive"))
      (node (ref "IC198") (pin "7") (pinfunction "7_7") (pintype "passive"))
      (node (ref "IC199") (pin "7") (pinfunction "7_7") (pintype "passive"))
      (node (ref "IC200") (pin "7") (pinfunction "7_7") (pintype "passive"))
    )
    (net (code "1185") (name "Net-(IC197-Pad8)") (class "Default")
      (node (ref "IC197") (pin "8") (pinfunction "8_8") (pintype "passive"))
      (node (ref "IC198") (pin "8") (pinfunction "8_8") (pintype "passive"))
      (node (ref "IC199") (pin "8") (pinfunction "8_8") (pintype "passive"))
      (node (ref "IC200") (pin "8") (pinfunction "8_8") (pintype "passive"))
    )
    (net (code "1186") (name "Net-(IC197-Pad9)") (class "Default")
      (node (ref "IC197") (pin "9") (pinfunction "9_9") (pintype "passive"))
      (node (ref "IC198") (pin "9") (pinfunction "9_9") (pintype "passive"))
      (node (ref "IC199") (pin "9") (pinfunction "9_9") (pintype "passive"))
      (node (ref "IC200") (pin "9") (pinfunction "9_9") (pintype "passive"))
    )
    (net (code "1187") (name "Net-(IC197-Pad10)") (class "Default")
      (node (ref "IC197") (pin "10") (pinfunction "10_10") (pintype "passive"))
      (node (ref "IC198") (pin "10") (pinfunction "10_10") (pintype "passive"))
      (node (ref "IC199") (pin "10") (pinfunction "10_10") (pintype "passive"))
      (node (ref "IC200") (pin "10") (pinfunction "10_10") (pintype "passive"))
    )
    (net (code "1188") (name "Net-(IC197-Pad11)") (class "Default")
      (node (ref "IC197") (pin "11") (pinfunction "11_11") (pintype "passive"))
      (node (ref "IC198") (pin "11") (pinfunction "11_11") (pintype "passive"))
      (node (ref "IC199") (pin "11") (pinfunction "11_11") (pintype "passive"))
      (node (ref "IC200") (pin "11") (pinfunction "11_11") (pintype "passive"))
    )
    (net (code "1189") (name "Net-(IC197-Pad12)") (class "Default")
      (node (ref "IC197") (pin "12") (pinfunction "12_12") (pintype "passive"))
      (node (ref "IC198") (pin "12") (pinfunction "12_12") (pintype "passive"))
      (node (ref "IC199") (pin "12") (pinfunction "12_12") (pintype "passive"))
      (node (ref "IC200") (pin "12") (pinfunction "12_12") (pintype "passive"))
    )
    (net (code "1190") (name "Net-(IC197-Pad13)") (class "Default")
      (node (ref "IC197") (pin "13") (pinfunction "13_13") (pintype "passive"))
      (node (ref "IC198") (pin "13") (pinfunction "13_13") (pintype "passive"))
      (node (ref "IC199") (pin "13") (pinfunction "13_13") (pintype "passive"))
      (node (ref "IC200") (pin "13") (pinfunction "13_13") (pintype "passive"))
    )
    (net (code "1191") (name "Net-(IC197-Pad14)") (class "Default")
      (node (ref "IC197") (pin "14") (pinfunction "14_14") (pintype "passive"))
      (node (ref "IC198") (pin "14") (pinfunction "14_14") (pintype "passive"))
      (node (ref "IC199") (pin "14") (pinfunction "14_14") (pintype "passive"))
      (node (ref "IC200") (pin "14") (pinfunction "14_14") (pintype "passive"))
    )
    (net (code "1192") (name "Net-(IC197-Pad15)") (class "Default")
      (node (ref "IC197") (pin "15") (pinfunction "15_15") (pintype "passive"))
      (node (ref "IC198") (pin "15") (pinfunction "15_15") (pintype "passive"))
      (node (ref "IC199") (pin "15") (pinfunction "15_15") (pintype "passive"))
      (node (ref "IC200") (pin "15") (pinfunction "15_15") (pintype "passive"))
    )
    (net (code "1193") (name "Net-(IC197-Pad16)") (class "Default")
      (node (ref "IC197") (pin "16") (pinfunction "16_16") (pintype "passive"))
      (node (ref "IC198") (pin "16") (pinfunction "16_16") (pintype "passive"))
      (node (ref "IC199") (pin "16") (pinfunction "16_16") (pintype "passive"))
      (node (ref "IC200") (pin "16") (pinfunction "16_16") (pintype "passive"))
    )
    (net (code "1194") (name "Net-(IC197-Pad17)") (class "Default")
      (node (ref "IC197") (pin "17") (pinfunction "17_17") (pintype "passive"))
      (node (ref "IC198") (pin "17") (pinfunction "17_17") (pintype "passive"))
      (node (ref "IC199") (pin "17") (pinfunction "17_17") (pintype "passive"))
      (node (ref "IC200") (pin "17") (pinfunction "17_17") (pintype "passive"))
    )
    (net (code "1195") (name "Net-(IC197-Pad18)") (class "Default")
      (node (ref "IC197") (pin "18") (pinfunction "18_18") (pintype "passive"))
      (node (ref "IC198") (pin "18") (pinfunction "18_18") (pintype "passive"))
      (node (ref "IC199") (pin "18") (pinfunction "18_18") (pintype "passive"))
      (node (ref "IC200") (pin "18") (pinfunction "18_18") (pintype "passive"))
    )
    (net (code "1196") (name "Net-(IC197-Pad19)") (class "Default")
      (node (ref "IC197") (pin "19") (pinfunction "19_19") (pintype "passive"))
      (node (ref "IC198") (pin "19") (pinfunction "19_19") (pintype "passive"))
      (node (ref "IC199") (pin "19") (pinfunction "19_19") (pintype "passive"))
      (node (ref "IC200") (pin "19") (pinfunction "19_19") (pintype "passive"))
    )
    (net (code "1197") (name "Net-(IC197-Pad20)") (class "Default")
      (node (ref "IC197") (pin "20") (pinfunction "20_20") (pintype "passive"))
      (node (ref "IC198") (pin "20") (pinfunction "20_20") (pintype "passive"))
      (node (ref "IC199") (pin "20") (pinfunction "20_20") (pintype "passive"))
      (node (ref "IC200") (pin "20") (pinfunction "20_20") (pintype "passive"))
    )
    (net (code "1198") (name "Net-(IC197-Pad21)") (class "Default")
      (node (ref "IC197") (pin "21") (pinfunction "21_21") (pintype "passive"))
      (node (ref "IC198") (pin "21") (pinfunction "21_21") (pintype "passive"))
      (node (ref "IC199") (pin "21") (pinfunction "21_21") (pintype "passive"))
      (node (ref "IC200") (pin "21") (pinfunction "21_21") (pintype "passive"))
    )
    (net (code "1199") (name "Net-(IC197-Pad22)") (class "Default")
      (node (ref "IC197") (pin "22") (pinfunction "22_22") (pintype "passive"))
      (node (ref "IC198") (pin "22") (pinfunction "22_22") (pintype "passive"))
      (node (ref "IC199") (pin "22") (pinfunction "22_22") (pintype "passive"))
      (node (ref "IC200") (pin "22") (pinfunction "22_22") (pintype "passive"))
    )
    (net (code "1200") (name "Net-(IC197-Pad23)") (class "Default")
      (node (ref "IC197") (pin "23") (pinfunction "23_23") (pintype "passive"))
      (node (ref "IC198") (pin "23") (pinfunction "23_23") (pintype "passive"))
      (node (ref "IC199") (pin "23") (pinfunction "23_23") (pintype "passive"))
      (node (ref "IC200") (pin "23") (pinfunction "23_23") (pintype "passive"))
    )
    (net (code "1201") (name "Net-(IC197-Pad24)") (class "Default")
      (node (ref "IC197") (pin "24") (pinfunction "24_24") (pintype "passive"))
      (node (ref "IC198") (pin "24") (pinfunction "24_24") (pintype "passive"))
      (node (ref "IC199") (pin "24") (pinfunction "24_24") (pintype "passive"))
      (node (ref "IC200") (pin "24") (pinfunction "24_24") (pintype "passive"))
    )
    (net (code "1202") (name "Net-(U$2A-1)") (class "Default")
      (node (ref "SV105") (pin "1") (pinfunction "1_1") (pintype "passive"))
      (node (ref "U$2") (pin "AA1") (pinfunction "1_AA1") (pintype "bidirectional"))
    )
    (net (code "1203") (name "Net-(U$2AA-1)") (class "Default")
      (node (ref "SV107") (pin "5") (pinfunction "5_5") (pintype "passive"))
      (node (ref "U$2") (pin "AR1") (pinfunction "1_AR1") (pintype "bidirectional"))
    )
    (net (code "1204") (name "Net-(U$2AB-1)") (class "Default")
      (node (ref "SV104") (pin "5") (pinfunction "5_5") (pintype "passive"))
      (node (ref "U$2") (pin "AR2") (pinfunction "1_AR2") (pintype "bidirectional"))
    )
    (net (code "1205") (name "Net-(U$2AC-1)") (class "Default")
      (node (ref "SV107") (pin "6") (pinfunction "6_6") (pintype "passive"))
      (node (ref "U$2") (pin "AS1") (pinfunction "1_AS1") (pintype "bidirectional"))
    )
    (net (code "1206") (name "Net-(U$2AD-1)") (class "Default")
      (node (ref "SV104") (pin "6") (pinfunction "6_6") (pintype "passive"))
      (node (ref "U$2") (pin "AS2") (pinfunction "1_AS2") (pintype "bidirectional"))
    )
    (net (code "1207") (name "Net-(U$2AE-1)") (class "Default")
      (node (ref "JP1") (pin "1") (pinfunction "1_1") (pintype "passive"))
      (node (ref "SV107") (pin "7") (pinfunction "7_7") (pintype "passive"))
      (node (ref "U$2") (pin "AT1") (pinfunction "1_AT1") (pintype "bidirectional"))
    )
    (net (code "1208") (name "Net-(U$2AF-1)") (class "Default")
      (node (ref "SV104") (pin "7") (pinfunction "7_7") (pintype "passive"))
      (node (ref "U$2") (pin "AT2") (pinfunction "1_AT2") (pintype "bidirectional"))
    )
    (net (code "1209") (name "Net-(U$2AG-1)") (class "Default")
      (node (ref "SV107") (pin "8") (pinfunction "8_8") (pintype "passive"))
      (node (ref "U$2") (pin "AU1") (pinfunction "1_AU1") (pintype "bidirectional"))
    )
    (net (code "1210") (name "Net-(U$2AH-1)") (class "Default")
      (node (ref "SV104") (pin "8") (pinfunction "8_8") (pintype "passive"))
      (node (ref "U$2") (pin "AU2") (pinfunction "1_AU2") (pintype "bidirectional"))
    )
    (net (code "1211") (name "Net-(U$2AI-1)") (class "Default")
      (node (ref "SV107") (pin "9") (pinfunction "9_9") (pintype "passive"))
      (node (ref "U$2") (pin "AV1") (pinfunction "1_AV1") (pintype "bidirectional"))
    )
    (net (code "1212") (name "Net-(U$2AJ-1)") (class "Default")
      (node (ref "SV104") (pin "9") (pinfunction "9_9") (pintype "passive"))
      (node (ref "U$2") (pin "AV2") (pinfunction "1_AV2") (pintype "bidirectional"))
    )
    (net (code "1213") (name "Net-(U$2AK-1)") (class "Default")
      (node (ref "SV109") (pin "1") (pinfunction "1_1") (pintype "passive"))
      (node (ref "U$2") (pin "BA1") (pinfunction "1_BA1") (pintype "bidirectional"))
    )
    (net (code "1214") (name "Net-(U$2AL-1)") (class "Default")
      (node (ref "SV41") (pin "1") (pinfunction "1_1") (pintype "passive"))
      (node (ref "U$2") (pin "BA2") (pinfunction "1_BA2") (pintype "bidirectional"))
    )
    (net (code "1215") (name "Net-(U$2AM-1)") (class "Default")
      (node (ref "SV109") (pin "2") (pinfunction "2_2") (pintype "passive"))
      (node (ref "U$2") (pin "BB1") (pinfunction "1_BB1") (pintype "bidirectional"))
    )
    (net (code "1216") (name "Net-(U$2AN-1)") (class "Default")
      (node (ref "SV41") (pin "2") (pinfunction "2_2") (pintype "passive"))
      (node (ref "SV94") (pin "2") (pinfunction "2_2") (pintype "passive"))
      (node (ref "U$2") (pin "BB2") (pinfunction "1_BB2") (pintype "bidirectional"))
    )
    (net (code "1217") (name "Net-(U$2AO-1)") (class "Default")
      (node (ref "SV109") (pin "3") (pinfunction "3_3") (pintype "passive"))
      (node (ref "U$2") (pin "BC1") (pinfunction "1_BC1") (pintype "bidirectional"))
    )
    (net (code "1218") (name "Net-(U$2AP-1)") (class "Default")
      (node (ref "SV41") (pin "3") (pinfunction "3_3") (pintype "passive"))
      (node (ref "U$2") (pin "BC2") (pinfunction "1_BC2") (pintype "bidirectional"))
    )
    (net (code "1219") (name "Net-(U$2AQ-1)") (class "Default")
      (node (ref "SV109") (pin "4") (pinfunction "4_4") (pintype "passive"))
      (node (ref "U$2") (pin "BD1") (pinfunction "1_BD1") (pintype "bidirectional"))
    )
    (net (code "1220") (name "Net-(U$2AR-1)") (class "Default")
      (node (ref "SV41") (pin "4") (pinfunction "4_4") (pintype "passive"))
      (node (ref "U$2") (pin "BD2") (pinfunction "1_BD2") (pintype "bidirectional"))
    )
    (net (code "1221") (name "Net-(U$2AS-1)") (class "Default")
      (node (ref "SV109") (pin "5") (pinfunction "5_5") (pintype "passive"))
      (node (ref "U$2") (pin "BE1") (pinfunction "1_BE1") (pintype "bidirectional"))
    )
    (net (code "1222") (name "Net-(U$2AT-1)") (class "Default")
      (node (ref "SV41") (pin "5") (pinfunction "5_5") (pintype "passive"))
      (node (ref "U$2") (pin "BE2") (pinfunction "1_BE2") (pintype "bidirectional"))
    )
    (net (code "1223") (name "Net-(U$2AU-1)") (class "Default")
      (node (ref "SV109") (pin "6") (pinfunction "6_6") (pintype "passive"))
      (node (ref "U$2") (pin "BF1") (pinfunction "1_BF1") (pintype "bidirectional"))
    )
    (net (code "1224") (name "Net-(U$2AV-1)") (class "Default")
      (node (ref "SV41") (pin "6") (pinfunction "6_6") (pintype "passive"))
      (node (ref "U$2") (pin "BF2") (pinfunction "1_BF2") (pintype "bidirectional"))
    )
    (net (code "1225") (name "Net-(U$2AW-1)") (class "Default")
      (node (ref "SV109") (pin "7") (pinfunction "7_7") (pintype "passive"))
      (node (ref "U$2") (pin "BH1") (pinfunction "1_BH1") (pintype "bidirectional"))
    )
    (net (code "1226") (name "Net-(U$2AX-1)") (class "Default")
      (node (ref "SV41") (pin "7") (pinfunction "7_7") (pintype "passive"))
      (node (ref "U$2") (pin "BH2") (pinfunction "1_BH2") (pintype "bidirectional"))
    )
    (net (code "1227") (name "Net-(U$2AY-1)") (class "Default")
      (node (ref "SV109") (pin "8") (pinfunction "8_8") (pintype "passive"))
      (node (ref "U$2") (pin "BJ1") (pinfunction "1_BJ1") (pintype "bidirectional"))
    )
    (net (code "1228") (name "Net-(U$2AZ-1)") (class "Default")
      (node (ref "SV41") (pin "8") (pinfunction "8_8") (pintype "passive"))
      (node (ref "U$2") (pin "BJ2") (pinfunction "1_BJ2") (pintype "bidirectional"))
    )
    (net (code "1229") (name "Net-(U$2B-1)") (class "Default")
      (node (ref "SV106") (pin "1") (pinfunction "1_1") (pintype "passive"))
      (node (ref "U$2") (pin "AA2") (pinfunction "1_AA2") (pintype "bidirectional"))
    )
    (net (code "1230") (name "Net-(U$2BA-1)") (class "Default")
      (node (ref "SV109") (pin "9") (pinfunction "9_9") (pintype "passive"))
      (node (ref "U$2") (pin "BK1") (pinfunction "1_BK1") (pintype "bidirectional"))
    )
    (net (code "1231") (name "Net-(U$2BB-1)") (class "Default")
      (node (ref "SV41") (pin "9") (pinfunction "9_9") (pintype "passive"))
      (node (ref "U$2") (pin "BK2") (pinfunction "1_BK2") (pintype "bidirectional"))
    )
    (net (code "1232") (name "Net-(U$2BC-1)") (class "Default")
      (node (ref "SV110") (pin "1") (pinfunction "1_1") (pintype "passive"))
      (node (ref "U$2") (pin "BL1") (pinfunction "1_BL1") (pintype "bidirectional"))
    )
    (net (code "1233") (name "Net-(U$2BD-1)") (class "Default")
      (node (ref "SV108") (pin "1") (pinfunction "1_1") (pintype "passive"))
      (node (ref "U$2") (pin "BL2") (pinfunction "1_BL2") (pintype "bidirectional"))
    )
    (net (code "1234") (name "Net-(U$2BE-1)") (class "Default")
      (node (ref "SV110") (pin "2") (pinfunction "2_2") (pintype "passive"))
      (node (ref "U$2") (pin "BM1") (pinfunction "1_BM1") (pintype "bidirectional"))
    )
    (net (code "1235") (name "Net-(U$2BF-1)") (class "Default")
      (node (ref "SV108") (pin "2") (pinfunction "2_2") (pintype "passive"))
      (node (ref "U$2") (pin "BM2") (pinfunction "1_BM2") (pintype "bidirectional"))
    )
    (net (code "1236") (name "Net-(U$2BG-1)") (class "Default")
      (node (ref "SV110") (pin "3") (pinfunction "3_3") (pintype "passive"))
      (node (ref "U$2") (pin "BN1") (pinfunction "1_BN1") (pintype "bidirectional"))
    )
    (net (code "1237") (name "Net-(U$2BH-1)") (class "Default")
      (node (ref "SV108") (pin "3") (pinfunction "3_3") (pintype "passive"))
      (node (ref "U$2") (pin "BN2") (pinfunction "1_BN2") (pintype "bidirectional"))
    )
    (net (code "1238") (name "Net-(U$2BI-1)") (class "Default")
      (node (ref "SV110") (pin "4") (pinfunction "4_4") (pintype "passive"))
      (node (ref "U$2") (pin "BP1") (pinfunction "1_BP1") (pintype "bidirectional"))
    )
    (net (code "1239") (name "Net-(U$2BJ-1)") (class "Default")
      (node (ref "SV108") (pin "4") (pinfunction "4_4") (pintype "passive"))
      (node (ref "U$2") (pin "BP2") (pinfunction "1_BP2") (pintype "bidirectional"))
    )
    (net (code "1240") (name "Net-(U$2BK-1)") (class "Default")
      (node (ref "SV110") (pin "5") (pinfunction "5_5") (pintype "passive"))
      (node (ref "U$2") (pin "BR1") (pinfunction "1_BR1") (pintype "bidirectional"))
    )
    (net (code "1241") (name "Net-(U$2BL-1)") (class "Default")
      (node (ref "SV108") (pin "5") (pinfunction "5_5") (pintype "passive"))
      (node (ref "U$2") (pin "BR2") (pinfunction "1_BR2") (pintype "bidirectional"))
    )
    (net (code "1242") (name "Net-(U$2BM-1)") (class "Default")
      (node (ref "SV110") (pin "6") (pinfunction "6_6") (pintype "passive"))
      (node (ref "U$2") (pin "BS1") (pinfunction "1_BS1") (pintype "bidirectional"))
    )
    (net (code "1243") (name "Net-(U$2BN-1)") (class "Default")
      (node (ref "SV108") (pin "6") (pinfunction "6_6") (pintype "passive"))
      (node (ref "U$2") (pin "BS2") (pinfunction "1_BS2") (pintype "bidirectional"))
    )
    (net (code "1244") (name "Net-(U$2BO-1)") (class "Default")
      (node (ref "JP2") (pin "1") (pinfunction "1_1") (pintype "passive"))
      (node (ref "SV110") (pin "7") (pinfunction "7_7") (pintype "passive"))
      (node (ref "U$2") (pin "BT1") (pinfunction "1_BT1") (pintype "bidirectional"))
    )
    (net (code "1245") (name "Net-(U$2BP-1)") (class "Default")
      (node (ref "SV108") (pin "7") (pinfunction "7_7") (pintype "passive"))
      (node (ref "U$2") (pin "BT2") (pinfunction "1_BT2") (pintype "bidirectional"))
    )
    (net (code "1246") (name "Net-(U$2BQ-1)") (class "Default")
      (node (ref "SV110") (pin "8") (pinfunction "8_8") (pintype "passive"))
      (node (ref "U$2") (pin "BU1") (pinfunction "1_BU1") (pintype "bidirectional"))
    )
    (net (code "1247") (name "Net-(U$2BR-1)") (class "Default")
      (node (ref "SV108") (pin "8") (pinfunction "8_8") (pintype "passive"))
      (node (ref "U$2") (pin "BU2") (pinfunction "1_BU2") (pintype "bidirectional"))
    )
    (net (code "1248") (name "Net-(U$2BS-1)") (class "Default")
      (node (ref "SV110") (pin "9") (pinfunction "9_9") (pintype "passive"))
      (node (ref "U$2") (pin "BV1") (pinfunction "1_BV1") (pintype "bidirectional"))
    )
    (net (code "1249") (name "Net-(U$2BT-1)") (class "Default")
      (node (ref "SV108") (pin "9") (pinfunction "9_9") (pintype "passive"))
      (node (ref "U$2") (pin "BV2") (pinfunction "1_BV2") (pintype "bidirectional"))
    )
    (net (code "1250") (name "Net-(U$2BU-1)") (class "Default")
      (node (ref "SV112") (pin "1") (pinfunction "1_1") (pintype "passive"))
      (node (ref "U$2") (pin "CA1") (pinfunction "1_CA1") (pintype "bidirectional"))
    )
    (net (code "1251") (name "Net-(U$2BV-1)") (class "Default")
      (node (ref "SV92") (pin "1") (pinfunction "1_1") (pintype "passive"))
      (node (ref "U$2") (pin "CA2") (pinfunction "1_CA2") (pintype "bidirectional"))
    )
    (net (code "1252") (name "Net-(U$2BW-1)") (class "Default")
      (node (ref "SV112") (pin "2") (pinfunction "2_2") (pintype "passive"))
      (node (ref "U$2") (pin "CB1") (pinfunction "1_CB1") (pintype "bidirectional"))
    )
    (net (code "1253") (name "Net-(U$2BX-1)") (class "Default")
      (node (ref "SV92") (pin "2") (pinfunction "2_2") (pintype "passive"))
      (node (ref "SV95") (pin "2") (pinfunction "2_2") (pintype "passive"))
      (node (ref "U$2") (pin "CB2") (pinfunction "1_CB2") (pintype "bidirectional"))
    )
    (net (code "1254") (name "Net-(U$2BY-1)") (class "Default")
      (node (ref "SV112") (pin "3") (pinfunction "3_3") (pintype "passive"))
      (node (ref "U$2") (pin "CC1") (pinfunction "1_CC1") (pintype "bidirectional"))
    )
    (net (code "1255") (name "Net-(U$2BZ-1)") (class "Default")
      (node (ref "SV92") (pin "3") (pinfunction "3_3") (pintype "passive"))
      (node (ref "U$2") (pin "CC2") (pinfunction "1_CC2") (pintype "bidirectional"))
    )
    (net (code "1256") (name "Net-(U$2C-1)") (class "Default")
      (node (ref "SV105") (pin "2") (pinfunction "2_2") (pintype "passive"))
      (node (ref "U$2") (pin "AB1") (pinfunction "1_AB1") (pintype "bidirectional"))
    )
    (net (code "1257") (name "Net-(U$2CA-1)") (class "Default")
      (node (ref "SV112") (pin "4") (pinfunction "4_4") (pintype "passive"))
      (node (ref "U$2") (pin "CD1") (pinfunction "1_CD1") (pintype "bidirectional"))
    )
    (net (code "1258") (name "Net-(U$2CB-1)") (class "Default")
      (node (ref "SV92") (pin "4") (pinfunction "4_4") (pintype "passive"))
      (node (ref "U$2") (pin "CD2") (pinfunction "1_CD2") (pintype "bidirectional"))
    )
    (net (code "1259") (name "Net-(U$2CC-1)") (class "Default")
      (node (ref "SV112") (pin "5") (pinfunction "5_5") (pintype "passive"))
      (node (ref "U$2") (pin "CE1") (pinfunction "1_CE1") (pintype "bidirectional"))
    )
    (net (code "1260") (name "Net-(U$2CD-1)") (class "Default")
      (node (ref "SV92") (pin "5") (pinfunction "5_5") (pintype "passive"))
      (node (ref "U$2") (pin "CE2") (pinfunction "1_CE2") (pintype "bidirectional"))
    )
    (net (code "1261") (name "Net-(U$2CE-1)") (class "Default")
      (node (ref "SV112") (pin "6") (pinfunction "6_6") (pintype "passive"))
      (node (ref "U$2") (pin "CF1") (pinfunction "1_CF1") (pintype "bidirectional"))
    )
    (net (code "1262") (name "Net-(U$2CF-1)") (class "Default")
      (node (ref "SV92") (pin "6") (pinfunction "6_6") (pintype "passive"))
      (node (ref "U$2") (pin "CF2") (pinfunction "1_CF2") (pintype "bidirectional"))
    )
    (net (code "1263") (name "Net-(U$2CG-1)") (class "Default")
      (node (ref "SV112") (pin "7") (pinfunction "7_7") (pintype "passive"))
      (node (ref "U$2") (pin "CH1") (pinfunction "1_CH1") (pintype "bidirectional"))
    )
    (net (code "1264") (name "Net-(U$2CH-1)") (class "Default")
      (node (ref "SV92") (pin "7") (pinfunction "7_7") (pintype "passive"))
      (node (ref "U$2") (pin "CH2") (pinfunction "1_CH2") (pintype "bidirectional"))
    )
    (net (code "1265") (name "Net-(U$2CI-1)") (class "Default")
      (node (ref "SV112") (pin "8") (pinfunction "8_8") (pintype "passive"))
      (node (ref "U$2") (pin "CJ1") (pinfunction "1_CJ1") (pintype "bidirectional"))
    )
    (net (code "1266") (name "Net-(U$2CJ-1)") (class "Default")
      (node (ref "SV92") (pin "8") (pinfunction "8_8") (pintype "passive"))
      (node (ref "U$2") (pin "CJ2") (pinfunction "1_CJ2") (pintype "bidirectional"))
    )
    (net (code "1267") (name "Net-(U$2CK-1)") (class "Default")
      (node (ref "SV112") (pin "9") (pinfunction "9_9") (pintype "passive"))
      (node (ref "U$2") (pin "CK1") (pinfunction "1_CK1") (pintype "bidirectional"))
    )
    (net (code "1268") (name "Net-(U$2CL-1)") (class "Default")
      (node (ref "SV92") (pin "9") (pinfunction "9_9") (pintype "passive"))
      (node (ref "U$2") (pin "CK2") (pinfunction "1_CK2") (pintype "bidirectional"))
    )
    (net (code "1269") (name "Net-(U$2CM-1)") (class "Default")
      (node (ref "SV113") (pin "1") (pinfunction "1_1") (pintype "passive"))
      (node (ref "U$2") (pin "CL1") (pinfunction "1_CL1") (pintype "bidirectional"))
    )
    (net (code "1270") (name "Net-(U$2CN-1)") (class "Default")
      (node (ref "SV111") (pin "1") (pinfunction "1_1") (pintype "passive"))
      (node (ref "U$2") (pin "CL2") (pinfunction "1_CL2") (pintype "bidirectional"))
    )
    (net (code "1271") (name "Net-(U$2CO-1)") (class "Default")
      (node (ref "SV113") (pin "2") (pinfunction "2_2") (pintype "passive"))
      (node (ref "U$2") (pin "CM1") (pinfunction "1_CM1") (pintype "bidirectional"))
    )
    (net (code "1272") (name "Net-(U$2CP-1)") (class "Default")
      (node (ref "SV111") (pin "2") (pinfunction "2_2") (pintype "passive"))
      (node (ref "U$2") (pin "CM2") (pinfunction "1_CM2") (pintype "bidirectional"))
    )
    (net (code "1273") (name "Net-(U$2CQ-1)") (class "Default")
      (node (ref "SV113") (pin "3") (pinfunction "3_3") (pintype "passive"))
      (node (ref "U$2") (pin "CN1") (pinfunction "1_CN1") (pintype "bidirectional"))
    )
    (net (code "1274") (name "Net-(U$2CR-1)") (class "Default")
      (node (ref "SV111") (pin "3") (pinfunction "3_3") (pintype "passive"))
      (node (ref "U$2") (pin "CN2") (pinfunction "1_CN2") (pintype "bidirectional"))
    )
    (net (code "1275") (name "Net-(U$2CS-1)") (class "Default")
      (node (ref "SV113") (pin "4") (pinfunction "4_4") (pintype "passive"))
      (node (ref "U$2") (pin "CP1") (pinfunction "1_CP1") (pintype "bidirectional"))
    )
    (net (code "1276") (name "Net-(U$2CT-1)") (class "Default")
      (node (ref "SV111") (pin "4") (pinfunction "4_4") (pintype "passive"))
      (node (ref "U$2") (pin "CP2") (pinfunction "1_CP2") (pintype "bidirectional"))
    )
    (net (code "1277") (name "Net-(U$2CU-1)") (class "Default")
      (node (ref "SV113") (pin "5") (pinfunction "5_5") (pintype "passive"))
      (node (ref "U$2") (pin "CR1") (pinfunction "1_CR1") (pintype "bidirectional"))
    )
    (net (code "1278") (name "Net-(U$2CV-1)") (class "Default")
      (node (ref "SV111") (pin "5") (pinfunction "5_5") (pintype "passive"))
      (node (ref "U$2") (pin "CR2") (pinfunction "1_CR2") (pintype "bidirectional"))
    )
    (net (code "1279") (name "Net-(U$2CW-1)") (class "Default")
      (node (ref "SV113") (pin "6") (pinfunction "6_6") (pintype "passive"))
      (node (ref "U$2") (pin "CS1") (pinfunction "1_CS1") (pintype "bidirectional"))
    )
    (net (code "1280") (name "Net-(U$2CX-1)") (class "Default")
      (node (ref "SV111") (pin "6") (pinfunction "6_6") (pintype "passive"))
      (node (ref "U$2") (pin "CS2") (pinfunction "1_CS2") (pintype "bidirectional"))
    )
    (net (code "1281") (name "Net-(U$2CY-1)") (class "Default")
      (node (ref "JP3") (pin "1") (pinfunction "1_1") (pintype "passive"))
      (node (ref "SV113") (pin "7") (pinfunction "7_7") (pintype "passive"))
      (node (ref "U$2") (pin "CT1") (pinfunction "1_CT1") (pintype "bidirectional"))
    )
    (net (code "1282") (name "Net-(U$2CZ-1)") (class "Default")
      (node (ref "SV111") (pin "7") (pinfunction "7_7") (pintype "passive"))
      (node (ref "U$2") (pin "CT2") (pinfunction "1_CT2") (pintype "bidirectional"))
    )
    (net (code "1283") (name "Net-(U$2D-1)") (class "Default")
      (node (ref "SV106") (pin "2") (pinfunction "2_2") (pintype "passive"))
      (node (ref "SV93") (pin "2") (pinfunction "2_2") (pintype "passive"))
      (node (ref "U$2") (pin "AB2") (pinfunction "1_AB2") (pintype "bidirectional"))
    )
    (net (code "1284") (name "Net-(U$2DA-1)") (class "Default")
      (node (ref "SV113") (pin "8") (pinfunction "8_8") (pintype "passive"))
      (node (ref "U$2") (pin "CU1") (pinfunction "1_CU1") (pintype "bidirectional"))
    )
    (net (code "1285") (name "Net-(U$2DB-1)") (class "Default")
      (node (ref "SV111") (pin "8") (pinfunction "8_8") (pintype "passive"))
      (node (ref "U$2") (pin "CU2") (pinfunction "1_CU2") (pintype "bidirectional"))
    )
    (net (code "1286") (name "Net-(U$2DC-1)") (class "Default")
      (node (ref "SV113") (pin "9") (pinfunction "9_9") (pintype "passive"))
      (node (ref "U$2") (pin "CV1") (pinfunction "1_CV1") (pintype "bidirectional"))
    )
    (net (code "1287") (name "Net-(U$2DD-1)") (class "Default")
      (node (ref "SV111") (pin "9") (pinfunction "9_9") (pintype "passive"))
      (node (ref "U$2") (pin "CV2") (pinfunction "1_CV2") (pintype "bidirectional"))
    )
    (net (code "1288") (name "Net-(U$2DE-1)") (class "Default")
      (node (ref "SV116") (pin "1") (pinfunction "1_1") (pintype "passive"))
      (node (ref "U$2") (pin "DA1") (pinfunction "1_DA1") (pintype "bidirectional"))
    )
    (net (code "1289") (name "Net-(U$2DF-1)") (class "Default")
      (node (ref "SV114") (pin "1") (pinfunction "1_1") (pintype "passive"))
      (node (ref "SV96") (pin "1") (pinfunction "1_1") (pintype "passive"))
      (node (ref "U$2") (pin "DA2") (pinfunction "1_DA2") (pintype "bidirectional"))
    )
    (net (code "1290") (name "Net-(U$2DG-1)") (class "Default")
      (node (ref "SV116") (pin "2") (pinfunction "2_2") (pintype "passive"))
      (node (ref "U$2") (pin "DB1") (pinfunction "1_DB1") (pintype "bidirectional"))
    )
    (net (code "1291") (name "Net-(U$2DH-1)") (class "Default")
      (node (ref "SV114") (pin "2") (pinfunction "2_2") (pintype "passive"))
      (node (ref "SV96") (pin "2") (pinfunction "2_2") (pintype "passive"))
      (node (ref "U$2") (pin "DB2") (pinfunction "1_DB2") (pintype "bidirectional"))
    )
    (net (code "1292") (name "Net-(U$2DI-1)") (class "Default")
      (node (ref "SV116") (pin "3") (pinfunction "3_3") (pintype "passive"))
      (node (ref "U$2") (pin "DC1") (pinfunction "1_DC1") (pintype "bidirectional"))
    )
    (net (code "1293") (name "Net-(U$2DJ-1)") (class "Default")
      (node (ref "SV114") (pin "3") (pinfunction "3_3") (pintype "passive"))
      (node (ref "U$2") (pin "DC2") (pinfunction "1_DC2") (pintype "bidirectional"))
    )
    (net (code "1294") (name "Net-(U$2DK-1)") (class "Default")
      (node (ref "SV116") (pin "4") (pinfunction "4_4") (pintype "passive"))
      (node (ref "U$2") (pin "DD1") (pinfunction "1_DD1") (pintype "bidirectional"))
    )
    (net (code "1295") (name "Net-(U$2DL-1)") (class "Default")
      (node (ref "SV114") (pin "4") (pinfunction "4_4") (pintype "passive"))
      (node (ref "U$2") (pin "DD2") (pinfunction "1_DD2") (pintype "bidirectional"))
    )
    (net (code "1296") (name "Net-(U$2DM-1)") (class "Default")
      (node (ref "SV116") (pin "5") (pinfunction "5_5") (pintype "passive"))
      (node (ref "U$2") (pin "DE1") (pinfunction "1_DE1") (pintype "bidirectional"))
    )
    (net (code "1297") (name "Net-(U$2DN-1)") (class "Default")
      (node (ref "SV114") (pin "5") (pinfunction "5_5") (pintype "passive"))
      (node (ref "U$2") (pin "DE2") (pinfunction "1_DE2") (pintype "bidirectional"))
    )
    (net (code "1298") (name "Net-(U$2DO-1)") (class "Default")
      (node (ref "SV116") (pin "6") (pinfunction "6_6") (pintype "passive"))
      (node (ref "U$2") (pin "DF1") (pinfunction "1_DF1") (pintype "bidirectional"))
    )
    (net (code "1299") (name "Net-(U$2DP-1)") (class "Default")
      (node (ref "SV114") (pin "6") (pinfunction "6_6") (pintype "passive"))
      (node (ref "U$2") (pin "DF2") (pinfunction "1_DF2") (pintype "bidirectional"))
    )
    (net (code "1300") (name "Net-(U$2DQ-1)") (class "Default")
      (node (ref "SV116") (pin "7") (pinfunction "7_7") (pintype "passive"))
      (node (ref "U$2") (pin "DH1") (pinfunction "1_DH1") (pintype "bidirectional"))
    )
    (net (code "1301") (name "Net-(U$2DR-1)") (class "Default")
      (node (ref "SV114") (pin "7") (pinfunction "7_7") (pintype "passive"))
      (node (ref "U$2") (pin "DH2") (pinfunction "1_DH2") (pintype "bidirectional"))
    )
    (net (code "1302") (name "Net-(U$2DS-1)") (class "Default")
      (node (ref "SV116") (pin "8") (pinfunction "8_8") (pintype "passive"))
      (node (ref "U$2") (pin "DJ1") (pinfunction "1_DJ1") (pintype "bidirectional"))
    )
    (net (code "1303") (name "Net-(U$2DT-1)") (class "Default")
      (node (ref "SV114") (pin "8") (pinfunction "8_8") (pintype "passive"))
      (node (ref "U$2") (pin "DJ2") (pinfunction "1_DJ2") (pintype "bidirectional"))
    )
    (net (code "1304") (name "Net-(U$2DU-1)") (class "Default")
      (node (ref "SV116") (pin "9") (pinfunction "9_9") (pintype "passive"))
      (node (ref "U$2") (pin "DK1") (pinfunction "1_DK1") (pintype "bidirectional"))
    )
    (net (code "1305") (name "Net-(U$2DV-1)") (class "Default")
      (node (ref "SV114") (pin "9") (pinfunction "9_9") (pintype "passive"))
      (node (ref "U$2") (pin "DK2") (pinfunction "1_DK2") (pintype "bidirectional"))
    )
    (net (code "1306") (name "Net-(U$2DW-1)") (class "Default")
      (node (ref "SV117") (pin "1") (pinfunction "1_1") (pintype "passive"))
      (node (ref "U$2") (pin "DL1") (pinfunction "1_DL1") (pintype "bidirectional"))
    )
    (net (code "1307") (name "Net-(U$2DX-1)") (class "Default")
      (node (ref "SV115") (pin "1") (pinfunction "1_1") (pintype "passive"))
      (node (ref "U$2") (pin "DL2") (pinfunction "1_DL2") (pintype "bidirectional"))
    )
    (net (code "1308") (name "Net-(U$2DY-1)") (class "Default")
      (node (ref "SV117") (pin "2") (pinfunction "2_2") (pintype "passive"))
      (node (ref "U$2") (pin "DM1") (pinfunction "1_DM1") (pintype "bidirectional"))
    )
    (net (code "1309") (name "Net-(U$2DZ-1)") (class "Default")
      (node (ref "SV115") (pin "2") (pinfunction "2_2") (pintype "passive"))
      (node (ref "U$2") (pin "DM2") (pinfunction "1_DM2") (pintype "bidirectional"))
    )
    (net (code "1310") (name "Net-(U$2E-1)") (class "Default")
      (node (ref "SV105") (pin "3") (pinfunction "3_3") (pintype "passive"))
      (node (ref "U$2") (pin "AC1") (pinfunction "1_AC1") (pintype "bidirectional"))
    )
    (net (code "1311") (name "Net-(U$2EA-1)") (class "Default")
      (node (ref "SV117") (pin "3") (pinfunction "3_3") (pintype "passive"))
      (node (ref "U$2") (pin "DN1") (pinfunction "1_DN1") (pintype "bidirectional"))
    )
    (net (code "1312") (name "Net-(U$2EB-1)") (class "Default")
      (node (ref "SV115") (pin "3") (pinfunction "3_3") (pintype "passive"))
      (node (ref "U$2") (pin "DN2") (pinfunction "1_DN2") (pintype "bidirectional"))
    )
    (net (code "1313") (name "Net-(U$2EC-1)") (class "Default")
      (node (ref "SV117") (pin "4") (pinfunction "4_4") (pintype "passive"))
      (node (ref "U$2") (pin "DP1") (pinfunction "1_DP1") (pintype "bidirectional"))
    )
    (net (code "1314") (name "Net-(U$2ED-1)") (class "Default")
      (node (ref "SV115") (pin "4") (pinfunction "4_4") (pintype "passive"))
      (node (ref "U$2") (pin "DP2") (pinfunction "1_DP2") (pintype "bidirectional"))
    )
    (net (code "1315") (name "Net-(U$2EE-1)") (class "Default")
      (node (ref "SV117") (pin "5") (pinfunction "5_5") (pintype "passive"))
      (node (ref "U$2") (pin "DR1") (pinfunction "1_DR1") (pintype "bidirectional"))
    )
    (net (code "1316") (name "Net-(U$2EF-1)") (class "Default")
      (node (ref "SV115") (pin "5") (pinfunction "5_5") (pintype "passive"))
      (node (ref "U$2") (pin "DR2") (pinfunction "1_DR2") (pintype "bidirectional"))
    )
    (net (code "1317") (name "Net-(U$2EG-1)") (class "Default")
      (node (ref "SV117") (pin "6") (pinfunction "6_6") (pintype "passive"))
      (node (ref "U$2") (pin "DS1") (pinfunction "1_DS1") (pintype "bidirectional"))
    )
    (net (code "1318") (name "Net-(U$2EH-1)") (class "Default")
      (node (ref "SV115") (pin "6") (pinfunction "6_6") (pintype "passive"))
      (node (ref "U$2") (pin "DS2") (pinfunction "1_DS2") (pintype "bidirectional"))
    )
    (net (code "1319") (name "Net-(U$2EI-1)") (class "Default")
      (node (ref "JP4") (pin "1") (pinfunction "1_1") (pintype "passive"))
      (node (ref "SV117") (pin "7") (pinfunction "7_7") (pintype "passive"))
      (node (ref "U$2") (pin "DT1") (pinfunction "1_DT1") (pintype "bidirectional"))
    )
    (net (code "1320") (name "Net-(U$2EJ-1)") (class "Default")
      (node (ref "SV115") (pin "7") (pinfunction "7_7") (pintype "passive"))
      (node (ref "U$2") (pin "DT2") (pinfunction "1_DT2") (pintype "bidirectional"))
    )
    (net (code "1321") (name "Net-(U$2EK-1)") (class "Default")
      (node (ref "SV117") (pin "8") (pinfunction "8_8") (pintype "passive"))
      (node (ref "U$2") (pin "DU1") (pinfunction "1_DU1") (pintype "bidirectional"))
    )
    (net (code "1322") (name "Net-(U$2EL-1)") (class "Default")
      (node (ref "SV115") (pin "8") (pinfunction "8_8") (pintype "passive"))
      (node (ref "U$2") (pin "DU2") (pinfunction "1_DU2") (pintype "bidirectional"))
    )
    (net (code "1323") (name "Net-(U$2EM-1)") (class "Default")
      (node (ref "SV117") (pin "9") (pinfunction "9_9") (pintype "passive"))
      (node (ref "U$2") (pin "DV1") (pinfunction "1_DV1") (pintype "bidirectional"))
    )
    (net (code "1324") (name "Net-(U$2EN-1)") (class "Default")
      (node (ref "SV115") (pin "9") (pinfunction "9_9") (pintype "passive"))
      (node (ref "U$2") (pin "DV2") (pinfunction "1_DV2") (pintype "bidirectional"))
    )
    (net (code "1325") (name "Net-(U$2F-1)") (class "Default")
      (node (ref "SV106") (pin "3") (pinfunction "3_3") (pintype "passive"))
      (node (ref "U$2") (pin "AC2") (pinfunction "1_AC2") (pintype "bidirectional"))
    )
    (net (code "1326") (name "Net-(U$2G-1)") (class "Default")
      (node (ref "SV105") (pin "4") (pinfunction "4_4") (pintype "passive"))
      (node (ref "U$2") (pin "AD1") (pinfunction "1_AD1") (pintype "bidirectional"))
    )
    (net (code "1327") (name "Net-(U$2H-1)") (class "Default")
      (node (ref "SV106") (pin "4") (pinfunction "4_4") (pintype "passive"))
      (node (ref "U$2") (pin "AD2") (pinfunction "1_AD2") (pintype "bidirectional"))
    )
    (net (code "1328") (name "Net-(U$2I-1)") (class "Default")
      (node (ref "SV105") (pin "5") (pinfunction "5_5") (pintype "passive"))
      (node (ref "U$2") (pin "AE1") (pinfunction "1_AE1") (pintype "bidirectional"))
    )
    (net (code "1329") (name "Net-(U$2J-1)") (class "Default")
      (node (ref "SV106") (pin "5") (pinfunction "5_5") (pintype "passive"))
      (node (ref "U$2") (pin "AE2") (pinfunction "1_AE2") (pintype "bidirectional"))
    )
    (net (code "1330") (name "Net-(U$2K-1)") (class "Default")
      (node (ref "SV105") (pin "6") (pinfunction "6_6") (pintype "passive"))
      (node (ref "U$2") (pin "AF1") (pinfunction "1_AF1") (pintype "bidirectional"))
    )
    (net (code "1331") (name "Net-(U$2L-1)") (class "Default")
      (node (ref "SV106") (pin "6") (pinfunction "6_6") (pintype "passive"))
      (node (ref "U$2") (pin "AF2") (pinfunction "1_AF2") (pintype "bidirectional"))
    )
    (net (code "1332") (name "Net-(U$2M-1)") (class "Default")
      (node (ref "SV105") (pin "7") (pinfunction "7_7") (pintype "passive"))
      (node (ref "U$2") (pin "AH1") (pinfunction "1_AH1") (pintype "bidirectional"))
    )
    (net (code "1333") (name "Net-(U$2N-1)") (class "Default")
      (node (ref "SV106") (pin "7") (pinfunction "7_7") (pintype "passive"))
      (node (ref "U$2") (pin "AH2") (pinfunction "1_AH2") (pintype "bidirectional"))
    )
    (net (code "1334") (name "Net-(U$2O-1)") (class "Default")
      (node (ref "SV105") (pin "8") (pinfunction "8_8") (pintype "passive"))
      (node (ref "U$2") (pin "AJ1") (pinfunction "1_AJ1") (pintype "bidirectional"))
    )
    (net (code "1335") (name "Net-(U$2P-1)") (class "Default")
      (node (ref "SV106") (pin "8") (pinfunction "8_8") (pintype "passive"))
      (node (ref "U$2") (pin "AJ2") (pinfunction "1_AJ2") (pintype "bidirectional"))
    )
    (net (code "1336") (name "Net-(U$2Q-1)") (class "Default")
      (node (ref "SV105") (pin "9") (pinfunction "9_9") (pintype "passive"))
      (node (ref "U$2") (pin "AK1") (pinfunction "1_AK1") (pintype "bidirectional"))
    )
    (net (code "1337") (name "Net-(U$2R-1)") (class "Default")
      (node (ref "SV106") (pin "9") (pinfunction "9_9") (pintype "passive"))
      (node (ref "U$2") (pin "AK2") (pinfunction "1_AK2") (pintype "bidirectional"))
    )
    (net (code "1338") (name "Net-(U$2S-1)") (class "Default")
      (node (ref "SV107") (pin "1") (pinfunction "1_1") (pintype "passive"))
      (node (ref "U$2") (pin "AL1") (pinfunction "1_AL1") (pintype "bidirectional"))
    )
    (net (code "1339") (name "Net-(U$2T-1)") (class "Default")
      (node (ref "SV104") (pin "1") (pinfunction "1_1") (pintype "passive"))
      (node (ref "U$2") (pin "AL2") (pinfunction "1_AL2") (pintype "bidirectional"))
    )
    (net (code "1340") (name "Net-(U$2U-1)") (class "Default")
      (node (ref "SV107") (pin "2") (pinfunction "2_2") (pintype "passive"))
      (node (ref "U$2") (pin "AM1") (pinfunction "1_AM1") (pintype "bidirectional"))
    )
    (net (code "1341") (name "Net-(U$2V-1)") (class "Default")
      (node (ref "SV104") (pin "2") (pinfunction "2_2") (pintype "passive"))
      (node (ref "U$2") (pin "AM2") (pinfunction "1_AM2") (pintype "bidirectional"))
    )
    (net (code "1342") (name "Net-(U$2W-1)") (class "Default")
      (node (ref "SV107") (pin "3") (pinfunction "3_3") (pintype "passive"))
      (node (ref "U$2") (pin "AN1") (pinfunction "1_AN1") (pintype "bidirectional"))
    )
    (net (code "1343") (name "Net-(U$2X-1)") (class "Default")
      (node (ref "SV104") (pin "3") (pinfunction "3_3") (pintype "passive"))
      (node (ref "U$2") (pin "AN2") (pinfunction "1_AN2") (pintype "bidirectional"))
    )
    (net (code "1344") (name "Net-(U$2Y-1)") (class "Default")
      (node (ref "SV107") (pin "4") (pinfunction "4_4") (pintype "passive"))
      (node (ref "U$2") (pin "AP1") (pinfunction "1_AP1") (pintype "bidirectional"))
    )
    (net (code "1345") (name "Net-(U$2Z-1)") (class "Default")
      (node (ref "SV104") (pin "4") (pinfunction "4_4") (pintype "passive"))
      (node (ref "U$2") (pin "AP2") (pinfunction "1_AP2") (pintype "bidirectional"))
    )
    (net (code "1346") (name "VCC") (class "Default")
      (node (ref "C1") (pin "+") (pinfunction "+_+") (pintype "passive"))
      (node (ref "C2") (pin "+") (pinfunction "+_+") (pintype "passive"))
      (node (ref "C3") (pin "+") (pinfunction "+_+") (pintype "passive"))
      (node (ref "C4") (pin "+") (pinfunction "+_+") (pintype "passive"))
      (node (ref "SV1") (pin "1") (pinfunction "1_1") (pintype "passive"))
      (node (ref "SV1") (pin "10") (pinfunction "10_10") (pintype "passive"))
      (node (ref "SV1") (pin "11") (pinfunction "11_11") (pintype "passive"))
      (node (ref "SV1") (pin "12") (pinfunction "12_12") (pintype "passive"))
      (node (ref "SV1") (pin "2") (pinfunction "2_2") (pintype "passive"))
      (node (ref "SV1") (pin "3") (pinfunction "3_3") (pintype "passive"))
      (node (ref "SV1") (pin "4") (pinfunction "4_4") (pintype "passive"))
      (node (ref "SV1") (pin "5") (pinfunction "5_5") (pintype "passive"))
      (node (ref "SV1") (pin "6") (pinfunction "6_6") (pintype "passive"))
      (node (ref "SV1") (pin "7") (pinfunction "7_7") (pintype "passive"))
      (node (ref "SV1") (pin "8") (pinfunction "8_8") (pintype "passive"))
      (node (ref "SV1") (pin "9") (pinfunction "9_9") (pintype "passive"))
      (node (ref "SV11") (pin "1") (pinfunction "1_1") (pintype "passive"))
      (node (ref "SV11") (pin "10") (pinfunction "10_10") (pintype "passive"))
      (node (ref "SV11") (pin "11") (pinfunction "11_11") (pintype "passive"))
      (node (ref "SV11") (pin "12") (pinfunction "12_12") (pintype "passive"))
      (node (ref "SV11") (pin "2") (pinfunction "2_2") (pintype "passive"))
      (node (ref "SV11") (pin "3") (pinfunction "3_3") (pintype "passive"))
      (node (ref "SV11") (pin "4") (pinfunction "4_4") (pintype "passive"))
      (node (ref "SV11") (pin "5") (pinfunction "5_5") (pintype "passive"))
      (node (ref "SV11") (pin "6") (pinfunction "6_6") (pintype "passive"))
      (node (ref "SV11") (pin "7") (pinfunction "7_7") (pintype "passive"))
      (node (ref "SV11") (pin "8") (pinfunction "8_8") (pintype "passive"))
      (node (ref "SV11") (pin "9") (pinfunction "9_9") (pintype "passive"))
      (node (ref "SV13") (pin "1") (pinfunction "1_1") (pintype "passive"))
      (node (ref "SV13") (pin "10") (pinfunction "10_10") (pintype "passive"))
      (node (ref "SV13") (pin "11") (pinfunction "11_11") (pintype "passive"))
      (node (ref "SV13") (pin "12") (pinfunction "12_12") (pintype "passive"))
      (node (ref "SV13") (pin "2") (pinfunction "2_2") (pintype "passive"))
      (node (ref "SV13") (pin "3") (pinfunction "3_3") (pintype "passive"))
      (node (ref "SV13") (pin "4") (pinfunction "4_4") (pintype "passive"))
      (node (ref "SV13") (pin "5") (pinfunction "5_5") (pintype "passive"))
      (node (ref "SV13") (pin "6") (pinfunction "6_6") (pintype "passive"))
      (node (ref "SV13") (pin "7") (pinfunction "7_7") (pintype "passive"))
      (node (ref "SV13") (pin "8") (pinfunction "8_8") (pintype "passive"))
      (node (ref "SV13") (pin "9") (pinfunction "9_9") (pintype "passive"))
      (node (ref "SV15") (pin "1") (pinfunction "1_1") (pintype "passive"))
      (node (ref "SV15") (pin "10") (pinfunction "10_10") (pintype "passive"))
      (node (ref "SV15") (pin "11") (pinfunction "11_11") (pintype "passive"))
      (node (ref "SV15") (pin "12") (pinfunction "12_12") (pintype "passive"))
      (node (ref "SV15") (pin "2") (pinfunction "2_2") (pintype "passive"))
      (node (ref "SV15") (pin "3") (pinfunction "3_3") (pintype "passive"))
      (node (ref "SV15") (pin "4") (pinfunction "4_4") (pintype "passive"))
      (node (ref "SV15") (pin "5") (pinfunction "5_5") (pintype "passive"))
      (node (ref "SV15") (pin "6") (pinfunction "6_6") (pintype "passive"))
      (node (ref "SV15") (pin "7") (pinfunction "7_7") (pintype "passive"))
      (node (ref "SV15") (pin "8") (pinfunction "8_8") (pintype "passive"))
      (node (ref "SV15") (pin "9") (pinfunction "9_9") (pintype "passive"))
      (node (ref "SV17") (pin "1") (pinfunction "1_1") (pintype "passive"))
      (node (ref "SV17") (pin "10") (pinfunction "10_10") (pintype "passive"))
      (node (ref "SV17") (pin "11") (pinfunction "11_11") (pintype "passive"))
      (node (ref "SV17") (pin "12") (pinfunction "12_12") (pintype "passive"))
      (node (ref "SV17") (pin "2") (pinfunction "2_2") (pintype "passive"))
      (node (ref "SV17") (pin "3") (pinfunction "3_3") (pintype "passive"))
      (node (ref "SV17") (pin "4") (pinfunction "4_4") (pintype "passive"))
      (node (ref "SV17") (pin "5") (pinfunction "5_5") (pintype "passive"))
      (node (ref "SV17") (pin "6") (pinfunction "6_6") (pintype "passive"))
      (node (ref "SV17") (pin "7") (pinfunction "7_7") (pintype "passive"))
      (node (ref "SV17") (pin "8") (pinfunction "8_8") (pintype "passive"))
      (node (ref "SV17") (pin "9") (pinfunction "9_9") (pintype "passive"))
      (node (ref "SV183") (pin "1") (pinfunction "1_1") (pintype "passive"))
      (node (ref "SV183") (pin "10") (pinfunction "10_10") (pintype "passive"))
      (node (ref "SV183") (pin "11") (pinfunction "11_11") (pintype "passive"))
      (node (ref "SV183") (pin "12") (pinfunction "12_12") (pintype "passive"))
      (node (ref "SV183") (pin "2") (pinfunction "2_2") (pintype "passive"))
      (node (ref "SV183") (pin "3") (pinfunction "3_3") (pintype "passive"))
      (node (ref "SV183") (pin "4") (pinfunction "4_4") (pintype "passive"))
      (node (ref "SV183") (pin "5") (pinfunction "5_5") (pintype "passive"))
      (node (ref "SV183") (pin "6") (pinfunction "6_6") (pintype "passive"))
      (node (ref "SV183") (pin "7") (pinfunction "7_7") (pintype "passive"))
      (node (ref "SV183") (pin "8") (pinfunction "8_8") (pintype "passive"))
      (node (ref "SV183") (pin "9") (pinfunction "9_9") (pintype "passive"))
      (node (ref "SV185") (pin "1") (pinfunction "1_1") (pintype "passive"))
      (node (ref "SV185") (pin "10") (pinfunction "10_10") (pintype "passive"))
      (node (ref "SV185") (pin "11") (pinfunction "11_11") (pintype "passive"))
      (node (ref "SV185") (pin "12") (pinfunction "12_12") (pintype "passive"))
      (node (ref "SV185") (pin "2") (pinfunction "2_2") (pintype "passive"))
      (node (ref "SV185") (pin "3") (pinfunction "3_3") (pintype "passive"))
      (node (ref "SV185") (pin "4") (pinfunction "4_4") (pintype "passive"))
      (node (ref "SV185") (pin "5") (pinfunction "5_5") (pintype "passive"))
      (node (ref "SV185") (pin "6") (pinfunction "6_6") (pintype "passive"))
      (node (ref "SV185") (pin "7") (pinfunction "7_7") (pintype "passive"))
      (node (ref "SV185") (pin "8") (pinfunction "8_8") (pintype "passive"))
      (node (ref "SV185") (pin "9") (pinfunction "9_9") (pintype "passive"))
      (node (ref "SV187") (pin "1") (pinfunction "1_1") (pintype "passive"))
      (node (ref "SV187") (pin "10") (pinfunction "10_10") (pintype "passive"))
      (node (ref "SV187") (pin "11") (pinfunction "11_11") (pintype "passive"))
      (node (ref "SV187") (pin "12") (pinfunction "12_12") (pintype "passive"))
      (node (ref "SV187") (pin "2") (pinfunction "2_2") (pintype "passive"))
      (node (ref "SV187") (pin "3") (pinfunction "3_3") (pintype "passive"))
      (node (ref "SV187") (pin "4") (pinfunction "4_4") (pintype "passive"))
      (node (ref "SV187") (pin "5") (pinfunction "5_5") (pintype "passive"))
      (node (ref "SV187") (pin "6") (pinfunction "6_6") (pintype "passive"))
      (node (ref "SV187") (pin "7") (pinfunction "7_7") (pintype "passive"))
      (node (ref "SV187") (pin "8") (pinfunction "8_8") (pintype "passive"))
      (node (ref "SV187") (pin "9") (pinfunction "9_9") (pintype "passive"))
      (node (ref "SV189") (pin "1") (pinfunction "1_1") (pintype "passive"))
      (node (ref "SV189") (pin "10") (pinfunction "10_10") (pintype "passive"))
      (node (ref "SV189") (pin "11") (pinfunction "11_11") (pintype "passive"))
      (node (ref "SV189") (pin "12") (pinfunction "12_12") (pintype "passive"))
      (node (ref "SV189") (pin "2") (pinfunction "2_2") (pintype "passive"))
      (node (ref "SV189") (pin "3") (pinfunction "3_3") (pintype "passive"))
      (node (ref "SV189") (pin "4") (pinfunction "4_4") (pintype "passive"))
      (node (ref "SV189") (pin "5") (pinfunction "5_5") (pintype "passive"))
      (node (ref "SV189") (pin "6") (pinfunction "6_6") (pintype "passive"))
      (node (ref "SV189") (pin "7") (pinfunction "7_7") (pintype "passive"))
      (node (ref "SV189") (pin "8") (pinfunction "8_8") (pintype "passive"))
      (node (ref "SV189") (pin "9") (pinfunction "9_9") (pintype "passive"))
      (node (ref "SV19") (pin "1") (pinfunction "1_1") (pintype "passive"))
      (node (ref "SV19") (pin "10") (pinfunction "10_10") (pintype "passive"))
      (node (ref "SV19") (pin "11") (pinfunction "11_11") (pintype "passive"))
      (node (ref "SV19") (pin "12") (pinfunction "12_12") (pintype "passive"))
      (node (ref "SV19") (pin "2") (pinfunction "2_2") (pintype "passive"))
      (node (ref "SV19") (pin "3") (pinfunction "3_3") (pintype "passive"))
      (node (ref "SV19") (pin "4") (pinfunction "4_4") (pintype "passive"))
      (node (ref "SV19") (pin "5") (pinfunction "5_5") (pintype "passive"))
      (node (ref "SV19") (pin "6") (pinfunction "6_6") (pintype "passive"))
      (node (ref "SV19") (pin "7") (pinfunction "7_7") (pintype "passive"))
      (node (ref "SV19") (pin "8") (pinfunction "8_8") (pintype "passive"))
      (node (ref "SV19") (pin "9") (pinfunction "9_9") (pintype "passive"))
      (node (ref "SV191") (pin "1") (pinfunction "1_1") (pintype "passive"))
      (node (ref "SV191") (pin "10") (pinfunction "10_10") (pintype "passive"))
      (node (ref "SV191") (pin "11") (pinfunction "11_11") (pintype "passive"))
      (node (ref "SV191") (pin "12") (pinfunction "12_12") (pintype "passive"))
      (node (ref "SV191") (pin "2") (pinfunction "2_2") (pintype "passive"))
      (node (ref "SV191") (pin "3") (pinfunction "3_3") (pintype "passive"))
      (node (ref "SV191") (pin "4") (pinfunction "4_4") (pintype "passive"))
      (node (ref "SV191") (pin "5") (pinfunction "5_5") (pintype "passive"))
      (node (ref "SV191") (pin "6") (pinfunction "6_6") (pintype "passive"))
      (node (ref "SV191") (pin "7") (pinfunction "7_7") (pintype "passive"))
      (node (ref "SV191") (pin "8") (pinfunction "8_8") (pintype "passive"))
      (node (ref "SV191") (pin "9") (pinfunction "9_9") (pintype "passive"))
      (node (ref "SV21") (pin "1") (pinfunction "1_1") (pintype "passive"))
      (node (ref "SV21") (pin "10") (pinfunction "10_10") (pintype "passive"))
      (node (ref "SV21") (pin "11") (pinfunction "11_11") (pintype "passive"))
      (node (ref "SV21") (pin "12") (pinfunction "12_12") (pintype "passive"))
      (node (ref "SV21") (pin "2") (pinfunction "2_2") (pintype "passive"))
      (node (ref "SV21") (pin "3") (pinfunction "3_3") (pintype "passive"))
      (node (ref "SV21") (pin "4") (pinfunction "4_4") (pintype "passive"))
      (node (ref "SV21") (pin "5") (pinfunction "5_5") (pintype "passive"))
      (node (ref "SV21") (pin "6") (pinfunction "6_6") (pintype "passive"))
      (node (ref "SV21") (pin "7") (pinfunction "7_7") (pintype "passive"))
      (node (ref "SV21") (pin "8") (pinfunction "8_8") (pintype "passive"))
      (node (ref "SV21") (pin "9") (pinfunction "9_9") (pintype "passive"))
      (node (ref "SV23") (pin "1") (pinfunction "1_1") (pintype "passive"))
      (node (ref "SV23") (pin "10") (pinfunction "10_10") (pintype "passive"))
      (node (ref "SV23") (pin "11") (pinfunction "11_11") (pintype "passive"))
      (node (ref "SV23") (pin "12") (pinfunction "12_12") (pintype "passive"))
      (node (ref "SV23") (pin "2") (pinfunction "2_2") (pintype "passive"))
      (node (ref "SV23") (pin "3") (pinfunction "3_3") (pintype "passive"))
      (node (ref "SV23") (pin "4") (pinfunction "4_4") (pintype "passive"))
      (node (ref "SV23") (pin "5") (pinfunction "5_5") (pintype "passive"))
      (node (ref "SV23") (pin "6") (pinfunction "6_6") (pintype "passive"))
      (node (ref "SV23") (pin "7") (pinfunction "7_7") (pintype "passive"))
      (node (ref "SV23") (pin "8") (pinfunction "8_8") (pintype "passive"))
      (node (ref "SV23") (pin "9") (pinfunction "9_9") (pintype "passive"))
      (node (ref "SV25") (pin "1") (pinfunction "1_1") (pintype "passive"))
      (node (ref "SV25") (pin "10") (pinfunction "10_10") (pintype "passive"))
      (node (ref "SV25") (pin "11") (pinfunction "11_11") (pintype "passive"))
      (node (ref "SV25") (pin "12") (pinfunction "12_12") (pintype "passive"))
      (node (ref "SV25") (pin "2") (pinfunction "2_2") (pintype "passive"))
      (node (ref "SV25") (pin "3") (pinfunction "3_3") (pintype "passive"))
      (node (ref "SV25") (pin "4") (pinfunction "4_4") (pintype "passive"))
      (node (ref "SV25") (pin "5") (pinfunction "5_5") (pintype "passive"))
      (node (ref "SV25") (pin "6") (pinfunction "6_6") (pintype "passive"))
      (node (ref "SV25") (pin "7") (pinfunction "7_7") (pintype "passive"))
      (node (ref "SV25") (pin "8") (pinfunction "8_8") (pintype "passive"))
      (node (ref "SV25") (pin "9") (pinfunction "9_9") (pintype "passive"))
      (node (ref "SV27") (pin "1") (pinfunction "1_1") (pintype "passive"))
      (node (ref "SV27") (pin "10") (pinfunction "10_10") (pintype "passive"))
      (node (ref "SV27") (pin "11") (pinfunction "11_11") (pintype "passive"))
      (node (ref "SV27") (pin "12") (pinfunction "12_12") (pintype "passive"))
      (node (ref "SV27") (pin "2") (pinfunction "2_2") (pintype "passive"))
      (node (ref "SV27") (pin "3") (pinfunction "3_3") (pintype "passive"))
      (node (ref "SV27") (pin "4") (pinfunction "4_4") (pintype "passive"))
      (node (ref "SV27") (pin "5") (pinfunction "5_5") (pintype "passive"))
      (node (ref "SV27") (pin "6") (pinfunction "6_6") (pintype "passive"))
      (node (ref "SV27") (pin "7") (pinfunction "7_7") (pintype "passive"))
      (node (ref "SV27") (pin "8") (pinfunction "8_8") (pintype "passive"))
      (node (ref "SV27") (pin "9") (pinfunction "9_9") (pintype "passive"))
      (node (ref "SV29") (pin "1") (pinfunction "1_1") (pintype "passive"))
      (node (ref "SV29") (pin "10") (pinfunction "10_10") (pintype "passive"))
      (node (ref "SV29") (pin "11") (pinfunction "11_11") (pintype "passive"))
      (node (ref "SV29") (pin "12") (pinfunction "12_12") (pintype "passive"))
      (node (ref "SV29") (pin "2") (pinfunction "2_2") (pintype "passive"))
      (node (ref "SV29") (pin "3") (pinfunction "3_3") (pintype "passive"))
      (node (ref "SV29") (pin "4") (pinfunction "4_4") (pintype "passive"))
      (node (ref "SV29") (pin "5") (pinfunction "5_5") (pintype "passive"))
      (node (ref "SV29") (pin "6") (pinfunction "6_6") (pintype "passive"))
      (node (ref "SV29") (pin "7") (pinfunction "7_7") (pintype "passive"))
      (node (ref "SV29") (pin "8") (pinfunction "8_8") (pintype "passive"))
      (node (ref "SV29") (pin "9") (pinfunction "9_9") (pintype "passive"))
      (node (ref "SV3") (pin "1") (pinfunction "1_1") (pintype "passive"))
      (node (ref "SV3") (pin "10") (pinfunction "10_10") (pintype "passive"))
      (node (ref "SV3") (pin "11") (pinfunction "11_11") (pintype "passive"))
      (node (ref "SV3") (pin "12") (pinfunction "12_12") (pintype "passive"))
      (node (ref "SV3") (pin "2") (pinfunction "2_2") (pintype "passive"))
      (node (ref "SV3") (pin "3") (pinfunction "3_3") (pintype "passive"))
      (node (ref "SV3") (pin "4") (pinfunction "4_4") (pintype "passive"))
      (node (ref "SV3") (pin "5") (pinfunction "5_5") (pintype "passive"))
      (node (ref "SV3") (pin "6") (pinfunction "6_6") (pintype "passive"))
      (node (ref "SV3") (pin "7") (pinfunction "7_7") (pintype "passive"))
      (node (ref "SV3") (pin "8") (pinfunction "8_8") (pintype "passive"))
      (node (ref "SV3") (pin "9") (pinfunction "9_9") (pintype "passive"))
      (node (ref "SV31") (pin "1") (pinfunction "1_1") (pintype "passive"))
      (node (ref "SV31") (pin "10") (pinfunction "10_10") (pintype "passive"))
      (node (ref "SV31") (pin "11") (pinfunction "11_11") (pintype "passive"))
      (node (ref "SV31") (pin "12") (pinfunction "12_12") (pintype "passive"))
      (node (ref "SV31") (pin "2") (pinfunction "2_2") (pintype "passive"))
      (node (ref "SV31") (pin "3") (pinfunction "3_3") (pintype "passive"))
      (node (ref "SV31") (pin "4") (pinfunction "4_4") (pintype "passive"))
      (node (ref "SV31") (pin "5") (pinfunction "5_5") (pintype "passive"))
      (node (ref "SV31") (pin "6") (pinfunction "6_6") (pintype "passive"))
      (node (ref "SV31") (pin "7") (pinfunction "7_7") (pintype "passive"))
      (node (ref "SV31") (pin "8") (pinfunction "8_8") (pintype "passive"))
      (node (ref "SV31") (pin "9") (pinfunction "9_9") (pintype "passive"))
      (node (ref "SV33") (pin "1") (pinfunction "1_1") (pintype "passive"))
      (node (ref "SV33") (pin "10") (pinfunction "10_10") (pintype "passive"))
      (node (ref "SV33") (pin "11") (pinfunction "11_11") (pintype "passive"))
      (node (ref "SV33") (pin "12") (pinfunction "12_12") (pintype "passive"))
      (node (ref "SV33") (pin "2") (pinfunction "2_2") (pintype "passive"))
      (node (ref "SV33") (pin "3") (pinfunction "3_3") (pintype "passive"))
      (node (ref "SV33") (pin "4") (pinfunction "4_4") (pintype "passive"))
      (node (ref "SV33") (pin "5") (pinfunction "5_5") (pintype "passive"))
      (node (ref "SV33") (pin "6") (pinfunction "6_6") (pintype "passive"))
      (node (ref "SV33") (pin "7") (pinfunction "7_7") (pintype "passive"))
      (node (ref "SV33") (pin "8") (pinfunction "8_8") (pintype "passive"))
      (node (ref "SV33") (pin "9") (pinfunction "9_9") (pintype "passive"))
      (node (ref "SV35") (pin "1") (pinfunction "1_1") (pintype "passive"))
      (node (ref "SV35") (pin "10") (pinfunction "10_10") (pintype "passive"))
      (node (ref "SV35") (pin "11") (pinfunction "11_11") (pintype "passive"))
      (node (ref "SV35") (pin "12") (pinfunction "12_12") (pintype "passive"))
      (node (ref "SV35") (pin "2") (pinfunction "2_2") (pintype "passive"))
      (node (ref "SV35") (pin "3") (pinfunction "3_3") (pintype "passive"))
      (node (ref "SV35") (pin "4") (pinfunction "4_4") (pintype "passive"))
      (node (ref "SV35") (pin "5") (pinfunction "5_5") (pintype "passive"))
      (node (ref "SV35") (pin "6") (pinfunction "6_6") (pintype "passive"))
      (node (ref "SV35") (pin "7") (pinfunction "7_7") (pintype "passive"))
      (node (ref "SV35") (pin "8") (pinfunction "8_8") (pintype "passive"))
      (node (ref "SV35") (pin "9") (pinfunction "9_9") (pintype "passive"))
      (node (ref "SV37") (pin "1") (pinfunction "1_1") (pintype "passive"))
      (node (ref "SV37") (pin "10") (pinfunction "10_10") (pintype "passive"))
      (node (ref "SV37") (pin "11") (pinfunction "11_11") (pintype "passive"))
      (node (ref "SV37") (pin "12") (pinfunction "12_12") (pintype "passive"))
      (node (ref "SV37") (pin "2") (pinfunction "2_2") (pintype "passive"))
      (node (ref "SV37") (pin "3") (pinfunction "3_3") (pintype "passive"))
      (node (ref "SV37") (pin "4") (pinfunction "4_4") (pintype "passive"))
      (node (ref "SV37") (pin "5") (pinfunction "5_5") (pintype "passive"))
      (node (ref "SV37") (pin "6") (pinfunction "6_6") (pintype "passive"))
      (node (ref "SV37") (pin "7") (pinfunction "7_7") (pintype "passive"))
      (node (ref "SV37") (pin "8") (pinfunction "8_8") (pintype "passive"))
      (node (ref "SV37") (pin "9") (pinfunction "9_9") (pintype "passive"))
      (node (ref "SV39") (pin "1") (pinfunction "1_1") (pintype "passive"))
      (node (ref "SV39") (pin "10") (pinfunction "10_10") (pintype "passive"))
      (node (ref "SV39") (pin "11") (pinfunction "11_11") (pintype "passive"))
      (node (ref "SV39") (pin "12") (pinfunction "12_12") (pintype "passive"))
      (node (ref "SV39") (pin "2") (pinfunction "2_2") (pintype "passive"))
      (node (ref "SV39") (pin "3") (pinfunction "3_3") (pintype "passive"))
      (node (ref "SV39") (pin "4") (pinfunction "4_4") (pintype "passive"))
      (node (ref "SV39") (pin "5") (pinfunction "5_5") (pintype "passive"))
      (node (ref "SV39") (pin "6") (pinfunction "6_6") (pintype "passive"))
      (node (ref "SV39") (pin "7") (pinfunction "7_7") (pintype "passive"))
      (node (ref "SV39") (pin "8") (pinfunction "8_8") (pintype "passive"))
      (node (ref "SV39") (pin "9") (pinfunction "9_9") (pintype "passive"))
      (node (ref "SV43") (pin "1") (pinfunction "1_1") (pintype "passive"))
      (node (ref "SV43") (pin "10") (pinfunction "10_10") (pintype "passive"))
      (node (ref "SV43") (pin "11") (pinfunction "11_11") (pintype "passive"))
      (node (ref "SV43") (pin "12") (pinfunction "12_12") (pintype "passive"))
      (node (ref "SV43") (pin "2") (pinfunction "2_2") (pintype "passive"))
      (node (ref "SV43") (pin "3") (pinfunction "3_3") (pintype "passive"))
      (node (ref "SV43") (pin "4") (pinfunction "4_4") (pintype "passive"))
      (node (ref "SV43") (pin "5") (pinfunction "5_5") (pintype "passive"))
      (node (ref "SV43") (pin "6") (pinfunction "6_6") (pintype "passive"))
      (node (ref "SV43") (pin "7") (pinfunction "7_7") (pintype "passive"))
      (node (ref "SV43") (pin "8") (pinfunction "8_8") (pintype "passive"))
      (node (ref "SV43") (pin "9") (pinfunction "9_9") (pintype "passive"))
      (node (ref "SV45") (pin "1") (pinfunction "1_1") (pintype "passive"))
      (node (ref "SV45") (pin "10") (pinfunction "10_10") (pintype "passive"))
      (node (ref "SV45") (pin "11") (pinfunction "11_11") (pintype "passive"))
      (node (ref "SV45") (pin "12") (pinfunction "12_12") (pintype "passive"))
      (node (ref "SV45") (pin "2") (pinfunction "2_2") (pintype "passive"))
      (node (ref "SV45") (pin "3") (pinfunction "3_3") (pintype "passive"))
      (node (ref "SV45") (pin "4") (pinfunction "4_4") (pintype "passive"))
      (node (ref "SV45") (pin "5") (pinfunction "5_5") (pintype "passive"))
      (node (ref "SV45") (pin "6") (pinfunction "6_6") (pintype "passive"))
      (node (ref "SV45") (pin "7") (pinfunction "7_7") (pintype "passive"))
      (node (ref "SV45") (pin "8") (pinfunction "8_8") (pintype "passive"))
      (node (ref "SV45") (pin "9") (pinfunction "9_9") (pintype "passive"))
      (node (ref "SV47") (pin "1") (pinfunction "1_1") (pintype "passive"))
      (node (ref "SV47") (pin "10") (pinfunction "10_10") (pintype "passive"))
      (node (ref "SV47") (pin "11") (pinfunction "11_11") (pintype "passive"))
      (node (ref "SV47") (pin "12") (pinfunction "12_12") (pintype "passive"))
      (node (ref "SV47") (pin "2") (pinfunction "2_2") (pintype "passive"))
      (node (ref "SV47") (pin "3") (pinfunction "3_3") (pintype "passive"))
      (node (ref "SV47") (pin "4") (pinfunction "4_4") (pintype "passive"))
      (node (ref "SV47") (pin "5") (pinfunction "5_5") (pintype "passive"))
      (node (ref "SV47") (pin "6") (pinfunction "6_6") (pintype "passive"))
      (node (ref "SV47") (pin "7") (pinfunction "7_7") (pintype "passive"))
      (node (ref "SV47") (pin "8") (pinfunction "8_8") (pintype "passive"))
      (node (ref "SV47") (pin "9") (pinfunction "9_9") (pintype "passive"))
      (node (ref "SV49") (pin "1") (pinfunction "1_1") (pintype "passive"))
      (node (ref "SV49") (pin "10") (pinfunction "10_10") (pintype "passive"))
      (node (ref "SV49") (pin "11") (pinfunction "11_11") (pintype "passive"))
      (node (ref "SV49") (pin "12") (pinfunction "12_12") (pintype "passive"))
      (node (ref "SV49") (pin "2") (pinfunction "2_2") (pintype "passive"))
      (node (ref "SV49") (pin "3") (pinfunction "3_3") (pintype "passive"))
      (node (ref "SV49") (pin "4") (pinfunction "4_4") (pintype "passive"))
      (node (ref "SV49") (pin "5") (pinfunction "5_5") (pintype "passive"))
      (node (ref "SV49") (pin "6") (pinfunction "6_6") (pintype "passive"))
      (node (ref "SV49") (pin "7") (pinfunction "7_7") (pintype "passive"))
      (node (ref "SV49") (pin "8") (pinfunction "8_8") (pintype "passive"))
      (node (ref "SV49") (pin "9") (pinfunction "9_9") (pintype "passive"))
      (node (ref "SV5") (pin "1") (pinfunction "1_1") (pintype "passive"))
      (node (ref "SV5") (pin "10") (pinfunction "10_10") (pintype "passive"))
      (node (ref "SV5") (pin "11") (pinfunction "11_11") (pintype "passive"))
      (node (ref "SV5") (pin "12") (pinfunction "12_12") (pintype "passive"))
      (node (ref "SV5") (pin "2") (pinfunction "2_2") (pintype "passive"))
      (node (ref "SV5") (pin "3") (pinfunction "3_3") (pintype "passive"))
      (node (ref "SV5") (pin "4") (pinfunction "4_4") (pintype "passive"))
      (node (ref "SV5") (pin "5") (pinfunction "5_5") (pintype "passive"))
      (node (ref "SV5") (pin "6") (pinfunction "6_6") (pintype "passive"))
      (node (ref "SV5") (pin "7") (pinfunction "7_7") (pintype "passive"))
      (node (ref "SV5") (pin "8") (pinfunction "8_8") (pintype "passive"))
      (node (ref "SV5") (pin "9") (pinfunction "9_9") (pintype "passive"))
      (node (ref "SV51") (pin "1") (pinfunction "1_1") (pintype "passive"))
      (node (ref "SV51") (pin "10") (pinfunction "10_10") (pintype "passive"))
      (node (ref "SV51") (pin "11") (pinfunction "11_11") (pintype "passive"))
      (node (ref "SV51") (pin "12") (pinfunction "12_12") (pintype "passive"))
      (node (ref "SV51") (pin "2") (pinfunction "2_2") (pintype "passive"))
      (node (ref "SV51") (pin "3") (pinfunction "3_3") (pintype "passive"))
      (node (ref "SV51") (pin "4") (pinfunction "4_4") (pintype "passive"))
      (node (ref "SV51") (pin "5") (pinfunction "5_5") (pintype "passive"))
      (node (ref "SV51") (pin "6") (pinfunction "6_6") (pintype "passive"))
      (node (ref "SV51") (pin "7") (pinfunction "7_7") (pintype "passive"))
      (node (ref "SV51") (pin "8") (pinfunction "8_8") (pintype "passive"))
      (node (ref "SV51") (pin "9") (pinfunction "9_9") (pintype "passive"))
      (node (ref "SV53") (pin "1") (pinfunction "1_1") (pintype "passive"))
      (node (ref "SV53") (pin "10") (pinfunction "10_10") (pintype "passive"))
      (node (ref "SV53") (pin "11") (pinfunction "11_11") (pintype "passive"))
      (node (ref "SV53") (pin "12") (pinfunction "12_12") (pintype "passive"))
      (node (ref "SV53") (pin "2") (pinfunction "2_2") (pintype "passive"))
      (node (ref "SV53") (pin "3") (pinfunction "3_3") (pintype "passive"))
      (node (ref "SV53") (pin "4") (pinfunction "4_4") (pintype "passive"))
      (node (ref "SV53") (pin "5") (pinfunction "5_5") (pintype "passive"))
      (node (ref "SV53") (pin "6") (pinfunction "6_6") (pintype "passive"))
      (node (ref "SV53") (pin "7") (pinfunction "7_7") (pintype "passive"))
      (node (ref "SV53") (pin "8") (pinfunction "8_8") (pintype "passive"))
      (node (ref "SV53") (pin "9") (pinfunction "9_9") (pintype "passive"))
      (node (ref "SV55") (pin "1") (pinfunction "1_1") (pintype "passive"))
      (node (ref "SV55") (pin "10") (pinfunction "10_10") (pintype "passive"))
      (node (ref "SV55") (pin "11") (pinfunction "11_11") (pintype "passive"))
      (node (ref "SV55") (pin "12") (pinfunction "12_12") (pintype "passive"))
      (node (ref "SV55") (pin "2") (pinfunction "2_2") (pintype "passive"))
      (node (ref "SV55") (pin "3") (pinfunction "3_3") (pintype "passive"))
      (node (ref "SV55") (pin "4") (pinfunction "4_4") (pintype "passive"))
      (node (ref "SV55") (pin "5") (pinfunction "5_5") (pintype "passive"))
      (node (ref "SV55") (pin "6") (pinfunction "6_6") (pintype "passive"))
      (node (ref "SV55") (pin "7") (pinfunction "7_7") (pintype "passive"))
      (node (ref "SV55") (pin "8") (pinfunction "8_8") (pintype "passive"))
      (node (ref "SV55") (pin "9") (pinfunction "9_9") (pintype "passive"))
      (node (ref "SV57") (pin "1") (pinfunction "1_1") (pintype "passive"))
      (node (ref "SV57") (pin "10") (pinfunction "10_10") (pintype "passive"))
      (node (ref "SV57") (pin "11") (pinfunction "11_11") (pintype "passive"))
      (node (ref "SV57") (pin "12") (pinfunction "12_12") (pintype "passive"))
      (node (ref "SV57") (pin "2") (pinfunction "2_2") (pintype "passive"))
      (node (ref "SV57") (pin "3") (pinfunction "3_3") (pintype "passive"))
      (node (ref "SV57") (pin "4") (pinfunction "4_4") (pintype "passive"))
      (node (ref "SV57") (pin "5") (pinfunction "5_5") (pintype "passive"))
      (node (ref "SV57") (pin "6") (pinfunction "6_6") (pintype "passive"))
      (node (ref "SV57") (pin "7") (pinfunction "7_7") (pintype "passive"))
      (node (ref "SV57") (pin "8") (pinfunction "8_8") (pintype "passive"))
      (node (ref "SV57") (pin "9") (pinfunction "9_9") (pintype "passive"))
      (node (ref "SV59") (pin "1") (pinfunction "1_1") (pintype "passive"))
      (node (ref "SV59") (pin "10") (pinfunction "10_10") (pintype "passive"))
      (node (ref "SV59") (pin "11") (pinfunction "11_11") (pintype "passive"))
      (node (ref "SV59") (pin "12") (pinfunction "12_12") (pintype "passive"))
      (node (ref "SV59") (pin "2") (pinfunction "2_2") (pintype "passive"))
      (node (ref "SV59") (pin "3") (pinfunction "3_3") (pintype "passive"))
      (node (ref "SV59") (pin "4") (pinfunction "4_4") (pintype "passive"))
      (node (ref "SV59") (pin "5") (pinfunction "5_5") (pintype "passive"))
      (node (ref "SV59") (pin "6") (pinfunction "6_6") (pintype "passive"))
      (node (ref "SV59") (pin "7") (pinfunction "7_7") (pintype "passive"))
      (node (ref "SV59") (pin "8") (pinfunction "8_8") (pintype "passive"))
      (node (ref "SV59") (pin "9") (pinfunction "9_9") (pintype "passive"))
      (node (ref "SV61") (pin "1") (pinfunction "1_1") (pintype "passive"))
      (node (ref "SV61") (pin "10") (pinfunction "10_10") (pintype "passive"))
      (node (ref "SV61") (pin "11") (pinfunction "11_11") (pintype "passive"))
      (node (ref "SV61") (pin "12") (pinfunction "12_12") (pintype "passive"))
      (node (ref "SV61") (pin "2") (pinfunction "2_2") (pintype "passive"))
      (node (ref "SV61") (pin "3") (pinfunction "3_3") (pintype "passive"))
      (node (ref "SV61") (pin "4") (pinfunction "4_4") (pintype "passive"))
      (node (ref "SV61") (pin "5") (pinfunction "5_5") (pintype "passive"))
      (node (ref "SV61") (pin "6") (pinfunction "6_6") (pintype "passive"))
      (node (ref "SV61") (pin "7") (pinfunction "7_7") (pintype "passive"))
      (node (ref "SV61") (pin "8") (pinfunction "8_8") (pintype "passive"))
      (node (ref "SV61") (pin "9") (pinfunction "9_9") (pintype "passive"))
      (node (ref "SV63") (pin "1") (pinfunction "1_1") (pintype "passive"))
      (node (ref "SV63") (pin "10") (pinfunction "10_10") (pintype "passive"))
      (node (ref "SV63") (pin "11") (pinfunction "11_11") (pintype "passive"))
      (node (ref "SV63") (pin "12") (pinfunction "12_12") (pintype "passive"))
      (node (ref "SV63") (pin "2") (pinfunction "2_2") (pintype "passive"))
      (node (ref "SV63") (pin "3") (pinfunction "3_3") (pintype "passive"))
      (node (ref "SV63") (pin "4") (pinfunction "4_4") (pintype "passive"))
      (node (ref "SV63") (pin "5") (pinfunction "5_5") (pintype "passive"))
      (node (ref "SV63") (pin "6") (pinfunction "6_6") (pintype "passive"))
      (node (ref "SV63") (pin "7") (pinfunction "7_7") (pintype "passive"))
      (node (ref "SV63") (pin "8") (pinfunction "8_8") (pintype "passive"))
      (node (ref "SV63") (pin "9") (pinfunction "9_9") (pintype "passive"))
      (node (ref "SV65") (pin "1") (pinfunction "1_1") (pintype "passive"))
      (node (ref "SV65") (pin "10") (pinfunction "10_10") (pintype "passive"))
      (node (ref "SV65") (pin "11") (pinfunction "11_11") (pintype "passive"))
      (node (ref "SV65") (pin "12") (pinfunction "12_12") (pintype "passive"))
      (node (ref "SV65") (pin "2") (pinfunction "2_2") (pintype "passive"))
      (node (ref "SV65") (pin "3") (pinfunction "3_3") (pintype "passive"))
      (node (ref "SV65") (pin "4") (pinfunction "4_4") (pintype "passive"))
      (node (ref "SV65") (pin "5") (pinfunction "5_5") (pintype "passive"))
      (node (ref "SV65") (pin "6") (pinfunction "6_6") (pintype "passive"))
      (node (ref "SV65") (pin "7") (pinfunction "7_7") (pintype "passive"))
      (node (ref "SV65") (pin "8") (pinfunction "8_8") (pintype "passive"))
      (node (ref "SV65") (pin "9") (pinfunction "9_9") (pintype "passive"))
      (node (ref "SV67") (pin "1") (pinfunction "1_1") (pintype "passive"))
      (node (ref "SV67") (pin "10") (pinfunction "10_10") (pintype "passive"))
      (node (ref "SV67") (pin "11") (pinfunction "11_11") (pintype "passive"))
      (node (ref "SV67") (pin "12") (pinfunction "12_12") (pintype "passive"))
      (node (ref "SV67") (pin "2") (pinfunction "2_2") (pintype "passive"))
      (node (ref "SV67") (pin "3") (pinfunction "3_3") (pintype "passive"))
      (node (ref "SV67") (pin "4") (pinfunction "4_4") (pintype "passive"))
      (node (ref "SV67") (pin "5") (pinfunction "5_5") (pintype "passive"))
      (node (ref "SV67") (pin "6") (pinfunction "6_6") (pintype "passive"))
      (node (ref "SV67") (pin "7") (pinfunction "7_7") (pintype "passive"))
      (node (ref "SV67") (pin "8") (pinfunction "8_8") (pintype "passive"))
      (node (ref "SV67") (pin "9") (pinfunction "9_9") (pintype "passive"))
      (node (ref "SV69") (pin "1") (pinfunction "1_1") (pintype "passive"))
      (node (ref "SV69") (pin "10") (pinfunction "10_10") (pintype "passive"))
      (node (ref "SV69") (pin "11") (pinfunction "11_11") (pintype "passive"))
      (node (ref "SV69") (pin "12") (pinfunction "12_12") (pintype "passive"))
      (node (ref "SV69") (pin "2") (pinfunction "2_2") (pintype "passive"))
      (node (ref "SV69") (pin "3") (pinfunction "3_3") (pintype "passive"))
      (node (ref "SV69") (pin "4") (pinfunction "4_4") (pintype "passive"))
      (node (ref "SV69") (pin "5") (pinfunction "5_5") (pintype "passive"))
      (node (ref "SV69") (pin "6") (pinfunction "6_6") (pintype "passive"))
      (node (ref "SV69") (pin "7") (pinfunction "7_7") (pintype "passive"))
      (node (ref "SV69") (pin "8") (pinfunction "8_8") (pintype "passive"))
      (node (ref "SV69") (pin "9") (pinfunction "9_9") (pintype "passive"))
      (node (ref "SV7") (pin "1") (pinfunction "1_1") (pintype "passive"))
      (node (ref "SV7") (pin "10") (pinfunction "10_10") (pintype "passive"))
      (node (ref "SV7") (pin "11") (pinfunction "11_11") (pintype "passive"))
      (node (ref "SV7") (pin "12") (pinfunction "12_12") (pintype "passive"))
      (node (ref "SV7") (pin "2") (pinfunction "2_2") (pintype "passive"))
      (node (ref "SV7") (pin "3") (pinfunction "3_3") (pintype "passive"))
      (node (ref "SV7") (pin "4") (pinfunction "4_4") (pintype "passive"))
      (node (ref "SV7") (pin "5") (pinfunction "5_5") (pintype "passive"))
      (node (ref "SV7") (pin "6") (pinfunction "6_6") (pintype "passive"))
      (node (ref "SV7") (pin "7") (pinfunction "7_7") (pintype "passive"))
      (node (ref "SV7") (pin "8") (pinfunction "8_8") (pintype "passive"))
      (node (ref "SV7") (pin "9") (pinfunction "9_9") (pintype "passive"))
      (node (ref "SV71") (pin "1") (pinfunction "1_1") (pintype "passive"))
      (node (ref "SV71") (pin "10") (pinfunction "10_10") (pintype "passive"))
      (node (ref "SV71") (pin "11") (pinfunction "11_11") (pintype "passive"))
      (node (ref "SV71") (pin "12") (pinfunction "12_12") (pintype "passive"))
      (node (ref "SV71") (pin "2") (pinfunction "2_2") (pintype "passive"))
      (node (ref "SV71") (pin "3") (pinfunction "3_3") (pintype "passive"))
      (node (ref "SV71") (pin "4") (pinfunction "4_4") (pintype "passive"))
      (node (ref "SV71") (pin "5") (pinfunction "5_5") (pintype "passive"))
      (node (ref "SV71") (pin "6") (pinfunction "6_6") (pintype "passive"))
      (node (ref "SV71") (pin "7") (pinfunction "7_7") (pintype "passive"))
      (node (ref "SV71") (pin "8") (pinfunction "8_8") (pintype "passive"))
      (node (ref "SV71") (pin "9") (pinfunction "9_9") (pintype "passive"))
      (node (ref "SV73") (pin "1") (pinfunction "1_1") (pintype "passive"))
      (node (ref "SV73") (pin "10") (pinfunction "10_10") (pintype "passive"))
      (node (ref "SV73") (pin "11") (pinfunction "11_11") (pintype "passive"))
      (node (ref "SV73") (pin "12") (pinfunction "12_12") (pintype "passive"))
      (node (ref "SV73") (pin "2") (pinfunction "2_2") (pintype "passive"))
      (node (ref "SV73") (pin "3") (pinfunction "3_3") (pintype "passive"))
      (node (ref "SV73") (pin "4") (pinfunction "4_4") (pintype "passive"))
      (node (ref "SV73") (pin "5") (pinfunction "5_5") (pintype "passive"))
      (node (ref "SV73") (pin "6") (pinfunction "6_6") (pintype "passive"))
      (node (ref "SV73") (pin "7") (pinfunction "7_7") (pintype "passive"))
      (node (ref "SV73") (pin "8") (pinfunction "8_8") (pintype "passive"))
      (node (ref "SV73") (pin "9") (pinfunction "9_9") (pintype "passive"))
      (node (ref "SV75") (pin "1") (pinfunction "1_1") (pintype "passive"))
      (node (ref "SV75") (pin "10") (pinfunction "10_10") (pintype "passive"))
      (node (ref "SV75") (pin "11") (pinfunction "11_11") (pintype "passive"))
      (node (ref "SV75") (pin "12") (pinfunction "12_12") (pintype "passive"))
      (node (ref "SV75") (pin "2") (pinfunction "2_2") (pintype "passive"))
      (node (ref "SV75") (pin "3") (pinfunction "3_3") (pintype "passive"))
      (node (ref "SV75") (pin "4") (pinfunction "4_4") (pintype "passive"))
      (node (ref "SV75") (pin "5") (pinfunction "5_5") (pintype "passive"))
      (node (ref "SV75") (pin "6") (pinfunction "6_6") (pintype "passive"))
      (node (ref "SV75") (pin "7") (pinfunction "7_7") (pintype "passive"))
      (node (ref "SV75") (pin "8") (pinfunction "8_8") (pintype "passive"))
      (node (ref "SV75") (pin "9") (pinfunction "9_9") (pintype "passive"))
      (node (ref "SV77") (pin "1") (pinfunction "1_1") (pintype "passive"))
      (node (ref "SV77") (pin "10") (pinfunction "10_10") (pintype "passive"))
      (node (ref "SV77") (pin "11") (pinfunction "11_11") (pintype "passive"))
      (node (ref "SV77") (pin "12") (pinfunction "12_12") (pintype "passive"))
      (node (ref "SV77") (pin "2") (pinfunction "2_2") (pintype "passive"))
      (node (ref "SV77") (pin "3") (pinfunction "3_3") (pintype "passive"))
      (node (ref "SV77") (pin "4") (pinfunction "4_4") (pintype "passive"))
      (node (ref "SV77") (pin "5") (pinfunction "5_5") (pintype "passive"))
      (node (ref "SV77") (pin "6") (pinfunction "6_6") (pintype "passive"))
      (node (ref "SV77") (pin "7") (pinfunction "7_7") (pintype "passive"))
      (node (ref "SV77") (pin "8") (pinfunction "8_8") (pintype "passive"))
      (node (ref "SV77") (pin "9") (pinfunction "9_9") (pintype "passive"))
      (node (ref "SV79") (pin "1") (pinfunction "1_1") (pintype "passive"))
      (node (ref "SV79") (pin "10") (pinfunction "10_10") (pintype "passive"))
      (node (ref "SV79") (pin "11") (pinfunction "11_11") (pintype "passive"))
      (node (ref "SV79") (pin "12") (pinfunction "12_12") (pintype "passive"))
      (node (ref "SV79") (pin "2") (pinfunction "2_2") (pintype "passive"))
      (node (ref "SV79") (pin "3") (pinfunction "3_3") (pintype "passive"))
      (node (ref "SV79") (pin "4") (pinfunction "4_4") (pintype "passive"))
      (node (ref "SV79") (pin "5") (pinfunction "5_5") (pintype "passive"))
      (node (ref "SV79") (pin "6") (pinfunction "6_6") (pintype "passive"))
      (node (ref "SV79") (pin "7") (pinfunction "7_7") (pintype "passive"))
      (node (ref "SV79") (pin "8") (pinfunction "8_8") (pintype "passive"))
      (node (ref "SV79") (pin "9") (pinfunction "9_9") (pintype "passive"))
      (node (ref "SV81") (pin "1") (pinfunction "1_1") (pintype "passive"))
      (node (ref "SV81") (pin "10") (pinfunction "10_10") (pintype "passive"))
      (node (ref "SV81") (pin "11") (pinfunction "11_11") (pintype "passive"))
      (node (ref "SV81") (pin "12") (pinfunction "12_12") (pintype "passive"))
      (node (ref "SV81") (pin "2") (pinfunction "2_2") (pintype "passive"))
      (node (ref "SV81") (pin "3") (pinfunction "3_3") (pintype "passive"))
      (node (ref "SV81") (pin "4") (pinfunction "4_4") (pintype "passive"))
      (node (ref "SV81") (pin "5") (pinfunction "5_5") (pintype "passive"))
      (node (ref "SV81") (pin "6") (pinfunction "6_6") (pintype "passive"))
      (node (ref "SV81") (pin "7") (pinfunction "7_7") (pintype "passive"))
      (node (ref "SV81") (pin "8") (pinfunction "8_8") (pintype "passive"))
      (node (ref "SV81") (pin "9") (pinfunction "9_9") (pintype "passive"))
      (node (ref "SV83") (pin "1") (pinfunction "1_1") (pintype "passive"))
      (node (ref "SV83") (pin "10") (pinfunction "10_10") (pintype "passive"))
      (node (ref "SV83") (pin "11") (pinfunction "11_11") (pintype "passive"))
      (node (ref "SV83") (pin "12") (pinfunction "12_12") (pintype "passive"))
      (node (ref "SV83") (pin "2") (pinfunction "2_2") (pintype "passive"))
      (node (ref "SV83") (pin "3") (pinfunction "3_3") (pintype "passive"))
      (node (ref "SV83") (pin "4") (pinfunction "4_4") (pintype "passive"))
      (node (ref "SV83") (pin "5") (pinfunction "5_5") (pintype "passive"))
      (node (ref "SV83") (pin "6") (pinfunction "6_6") (pintype "passive"))
      (node (ref "SV83") (pin "7") (pinfunction "7_7") (pintype "passive"))
      (node (ref "SV83") (pin "8") (pinfunction "8_8") (pintype "passive"))
      (node (ref "SV83") (pin "9") (pinfunction "9_9") (pintype "passive"))
      (node (ref "SV85") (pin "1") (pinfunction "1_1") (pintype "passive"))
      (node (ref "SV85") (pin "10") (pinfunction "10_10") (pintype "passive"))
      (node (ref "SV85") (pin "11") (pinfunction "11_11") (pintype "passive"))
      (node (ref "SV85") (pin "12") (pinfunction "12_12") (pintype "passive"))
      (node (ref "SV85") (pin "2") (pinfunction "2_2") (pintype "passive"))
      (node (ref "SV85") (pin "3") (pinfunction "3_3") (pintype "passive"))
      (node (ref "SV85") (pin "4") (pinfunction "4_4") (pintype "passive"))
      (node (ref "SV85") (pin "5") (pinfunction "5_5") (pintype "passive"))
      (node (ref "SV85") (pin "6") (pinfunction "6_6") (pintype "passive"))
      (node (ref "SV85") (pin "7") (pinfunction "7_7") (pintype "passive"))
      (node (ref "SV85") (pin "8") (pinfunction "8_8") (pintype "passive"))
      (node (ref "SV85") (pin "9") (pinfunction "9_9") (pintype "passive"))
      (node (ref "SV87") (pin "1") (pinfunction "1_1") (pintype "passive"))
      (node (ref "SV87") (pin "10") (pinfunction "10_10") (pintype "passive"))
      (node (ref "SV87") (pin "11") (pinfunction "11_11") (pintype "passive"))
      (node (ref "SV87") (pin "12") (pinfunction "12_12") (pintype "passive"))
      (node (ref "SV87") (pin "2") (pinfunction "2_2") (pintype "passive"))
      (node (ref "SV87") (pin "3") (pinfunction "3_3") (pintype "passive"))
      (node (ref "SV87") (pin "4") (pinfunction "4_4") (pintype "passive"))
      (node (ref "SV87") (pin "5") (pinfunction "5_5") (pintype "passive"))
      (node (ref "SV87") (pin "6") (pinfunction "6_6") (pintype "passive"))
      (node (ref "SV87") (pin "7") (pinfunction "7_7") (pintype "passive"))
      (node (ref "SV87") (pin "8") (pinfunction "8_8") (pintype "passive"))
      (node (ref "SV87") (pin "9") (pinfunction "9_9") (pintype "passive"))
      (node (ref "SV89") (pin "1") (pinfunction "1_1") (pintype "passive"))
      (node (ref "SV89") (pin "10") (pinfunction "10_10") (pintype "passive"))
      (node (ref "SV89") (pin "11") (pinfunction "11_11") (pintype "passive"))
      (node (ref "SV89") (pin "12") (pinfunction "12_12") (pintype "passive"))
      (node (ref "SV89") (pin "2") (pinfunction "2_2") (pintype "passive"))
      (node (ref "SV89") (pin "3") (pinfunction "3_3") (pintype "passive"))
      (node (ref "SV89") (pin "4") (pinfunction "4_4") (pintype "passive"))
      (node (ref "SV89") (pin "5") (pinfunction "5_5") (pintype "passive"))
      (node (ref "SV89") (pin "6") (pinfunction "6_6") (pintype "passive"))
      (node (ref "SV89") (pin "7") (pinfunction "7_7") (pintype "passive"))
      (node (ref "SV89") (pin "8") (pinfunction "8_8") (pintype "passive"))
      (node (ref "SV89") (pin "9") (pinfunction "9_9") (pintype "passive"))
      (node (ref "SV9") (pin "1") (pinfunction "1_1") (pintype "passive"))
      (node (ref "SV9") (pin "10") (pinfunction "10_10") (pintype "passive"))
      (node (ref "SV9") (pin "11") (pinfunction "11_11") (pintype "passive"))
      (node (ref "SV9") (pin "12") (pinfunction "12_12") (pintype "passive"))
      (node (ref "SV9") (pin "2") (pinfunction "2_2") (pintype "passive"))
      (node (ref "SV9") (pin "3") (pinfunction "3_3") (pintype "passive"))
      (node (ref "SV9") (pin "4") (pinfunction "4_4") (pintype "passive"))
      (node (ref "SV9") (pin "5") (pinfunction "5_5") (pintype "passive"))
      (node (ref "SV9") (pin "6") (pinfunction "6_6") (pintype "passive"))
      (node (ref "SV9") (pin "7") (pinfunction "7_7") (pintype "passive"))
      (node (ref "SV9") (pin "8") (pinfunction "8_8") (pintype "passive"))
      (node (ref "SV9") (pin "9") (pinfunction "9_9") (pintype "passive"))
      (node (ref "SV91") (pin "1") (pinfunction "1_1") (pintype "passive"))
      (node (ref "SV91") (pin "10") (pinfunction "10_10") (pintype "passive"))
      (node (ref "SV91") (pin "11") (pinfunction "11_11") (pintype "passive"))
      (node (ref "SV91") (pin "12") (pinfunction "12_12") (pintype "passive"))
      (node (ref "SV91") (pin "2") (pinfunction "2_2") (pintype "passive"))
      (node (ref "SV91") (pin "3") (pinfunction "3_3") (pintype "passive"))
      (node (ref "SV91") (pin "4") (pinfunction "4_4") (pintype "passive"))
      (node (ref "SV91") (pin "5") (pinfunction "5_5") (pintype "passive"))
      (node (ref "SV91") (pin "6") (pinfunction "6_6") (pintype "passive"))
      (node (ref "SV91") (pin "7") (pinfunction "7_7") (pintype "passive"))
      (node (ref "SV91") (pin "8") (pinfunction "8_8") (pintype "passive"))
      (node (ref "SV91") (pin "9") (pinfunction "9_9") (pintype "passive"))
      (node (ref "SV93") (pin "1") (pinfunction "1_1") (pintype "passive"))
      (node (ref "SV94") (pin "1") (pinfunction "1_1") (pintype "passive"))
      (node (ref "SV95") (pin "1") (pinfunction "1_1") (pintype "passive"))
      (node (ref "SV97") (pin "1") (pinfunction "1_1") (pintype "passive"))
    )
  )
)
